# CPU_Logic.net
KiCad netlist of a schematic drawn in Altium Designer
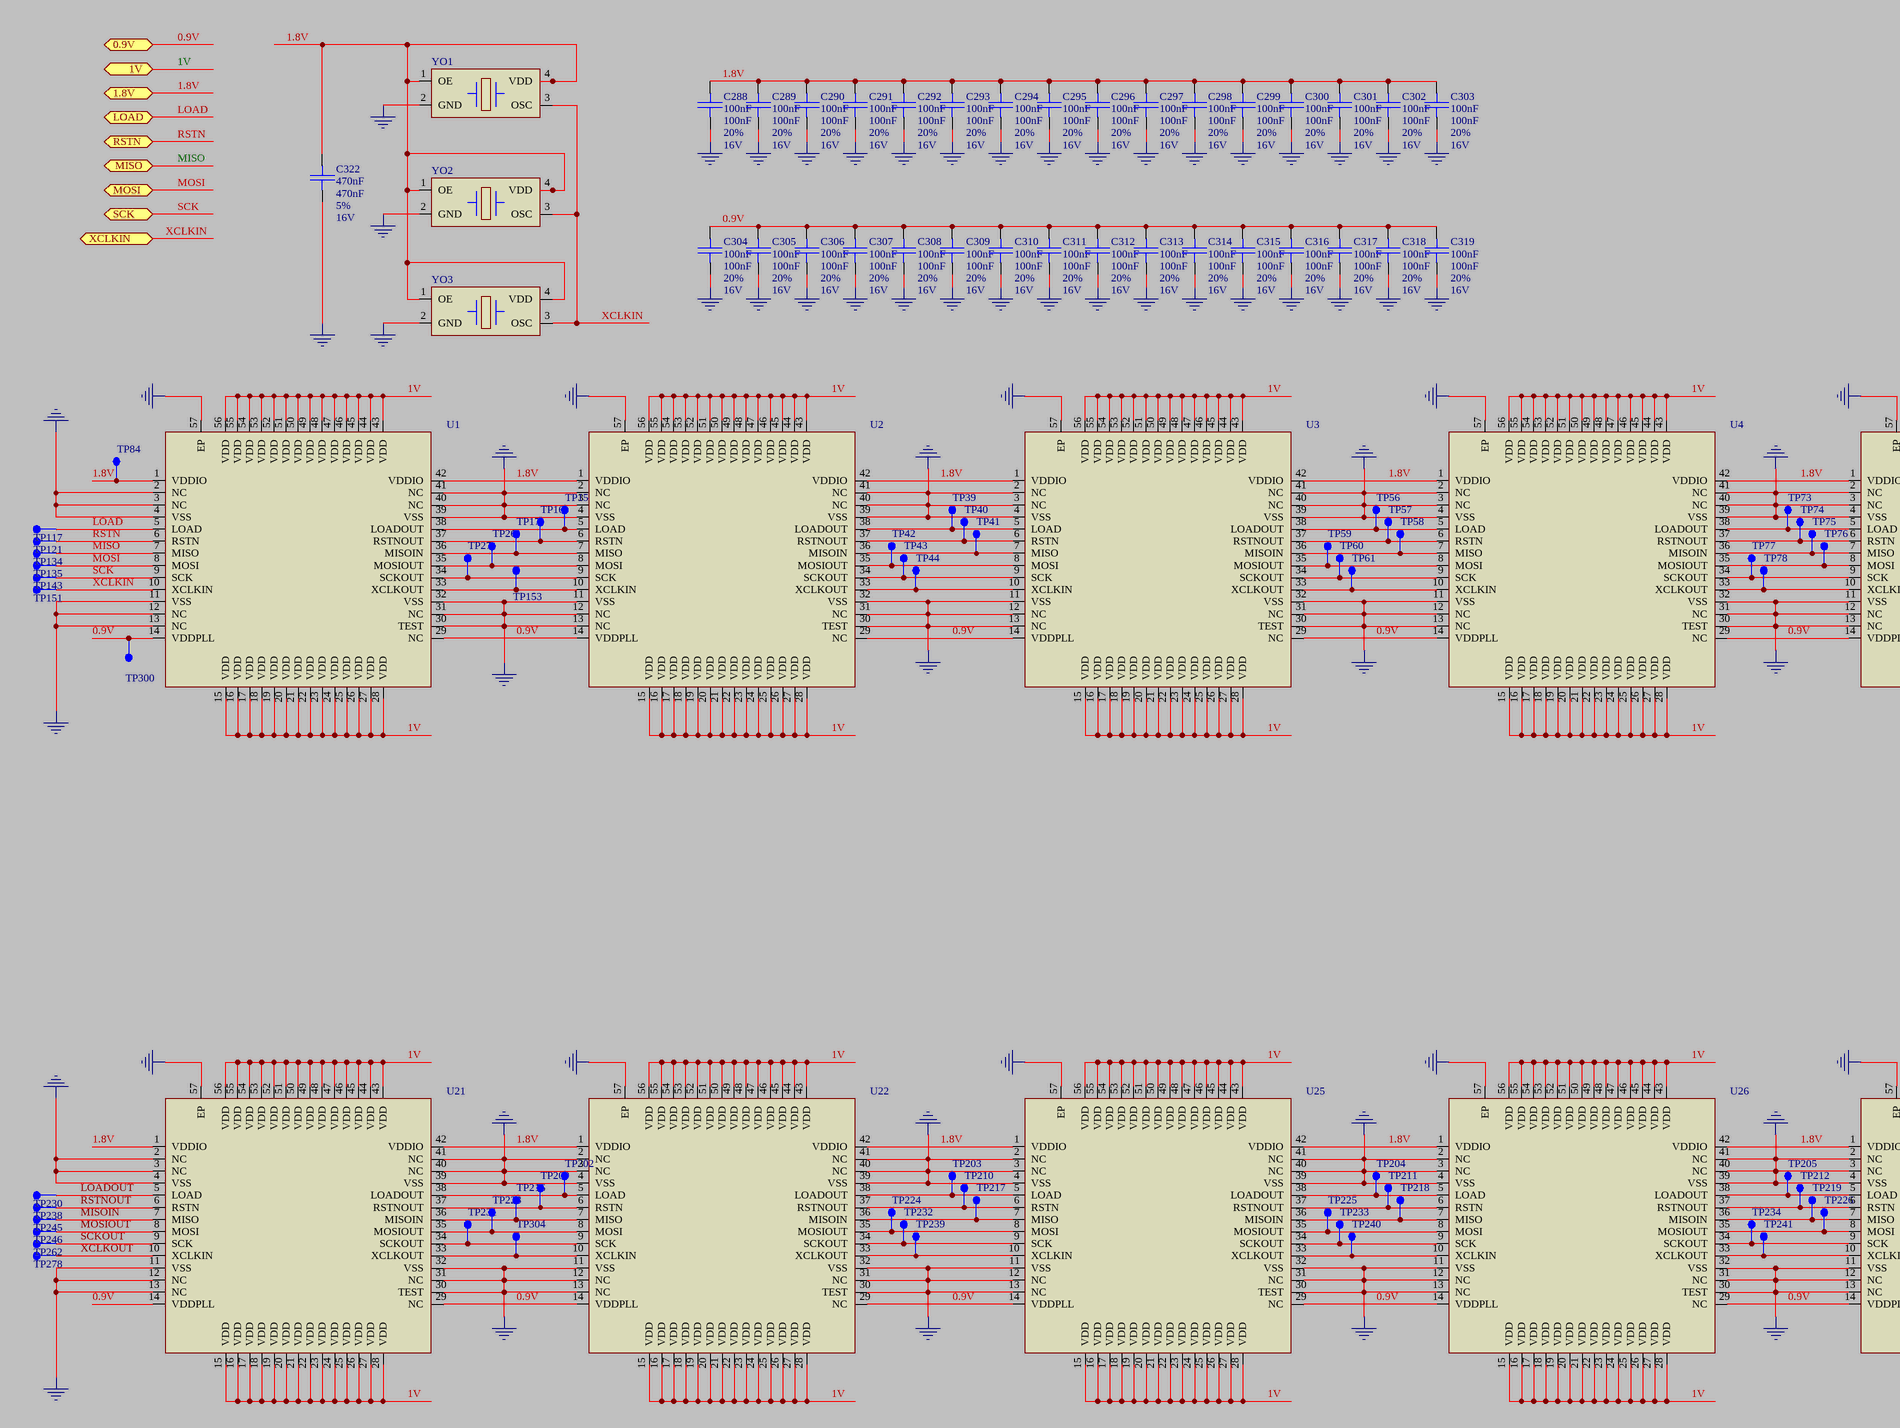
[diagram p0: CPU_Logic.SchDoc, top left]
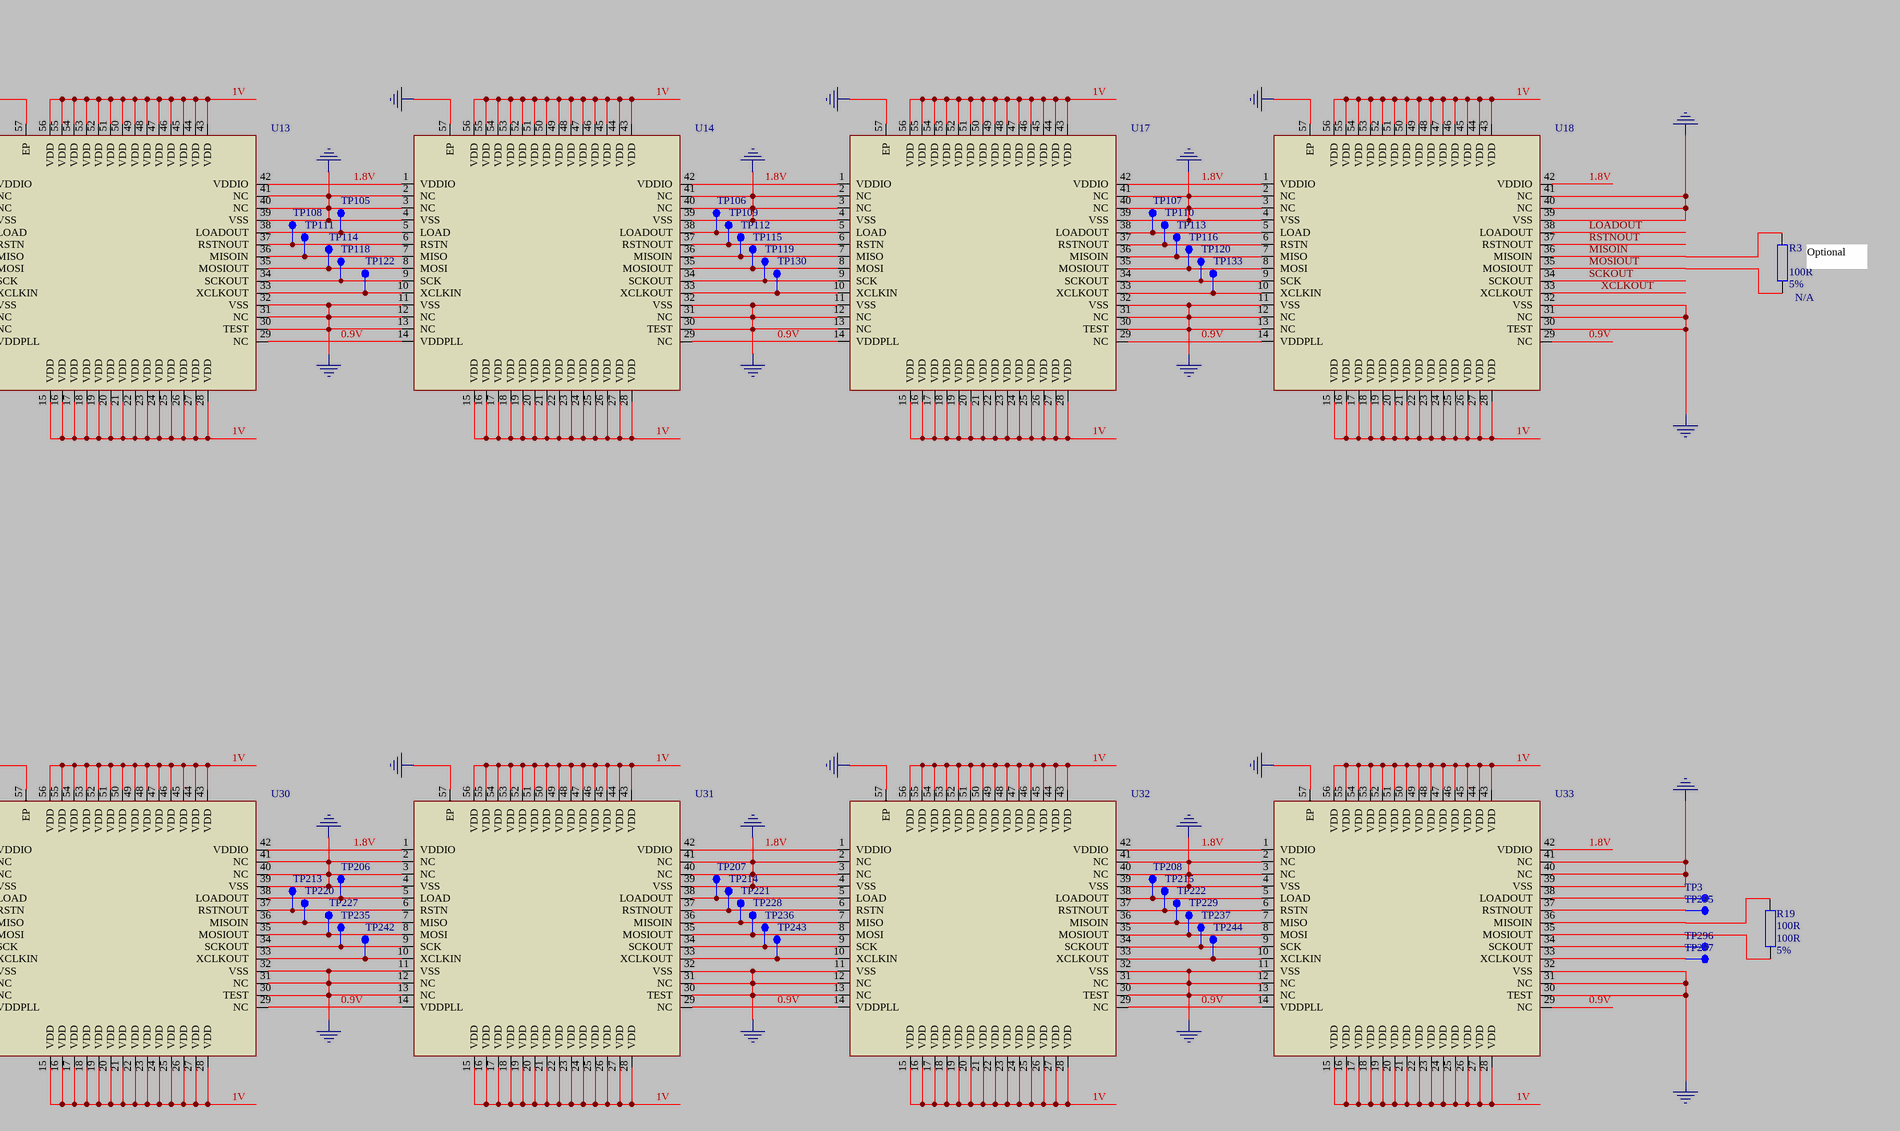
[diagram p1: CPU_Logic.SchDoc, top right]
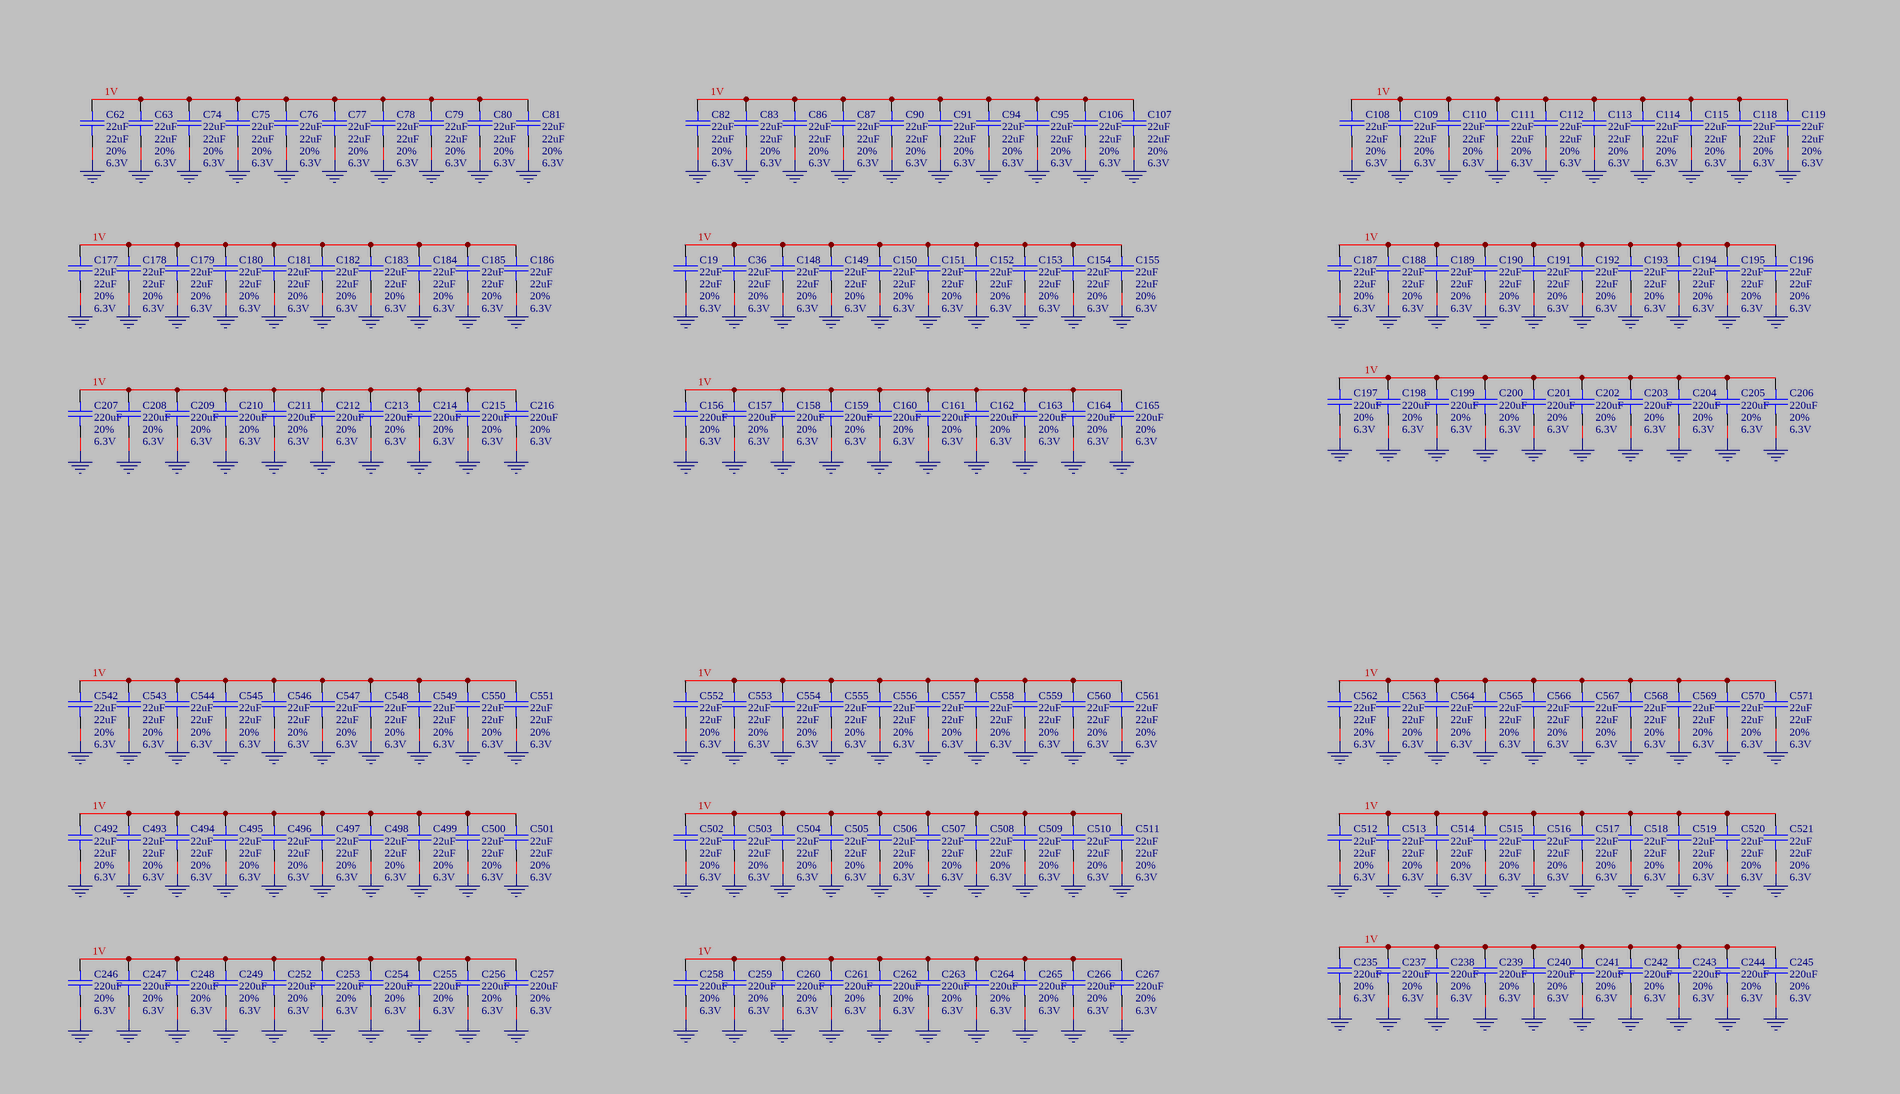
[diagram p2: CPU_Logic.SchDoc, bottom left]
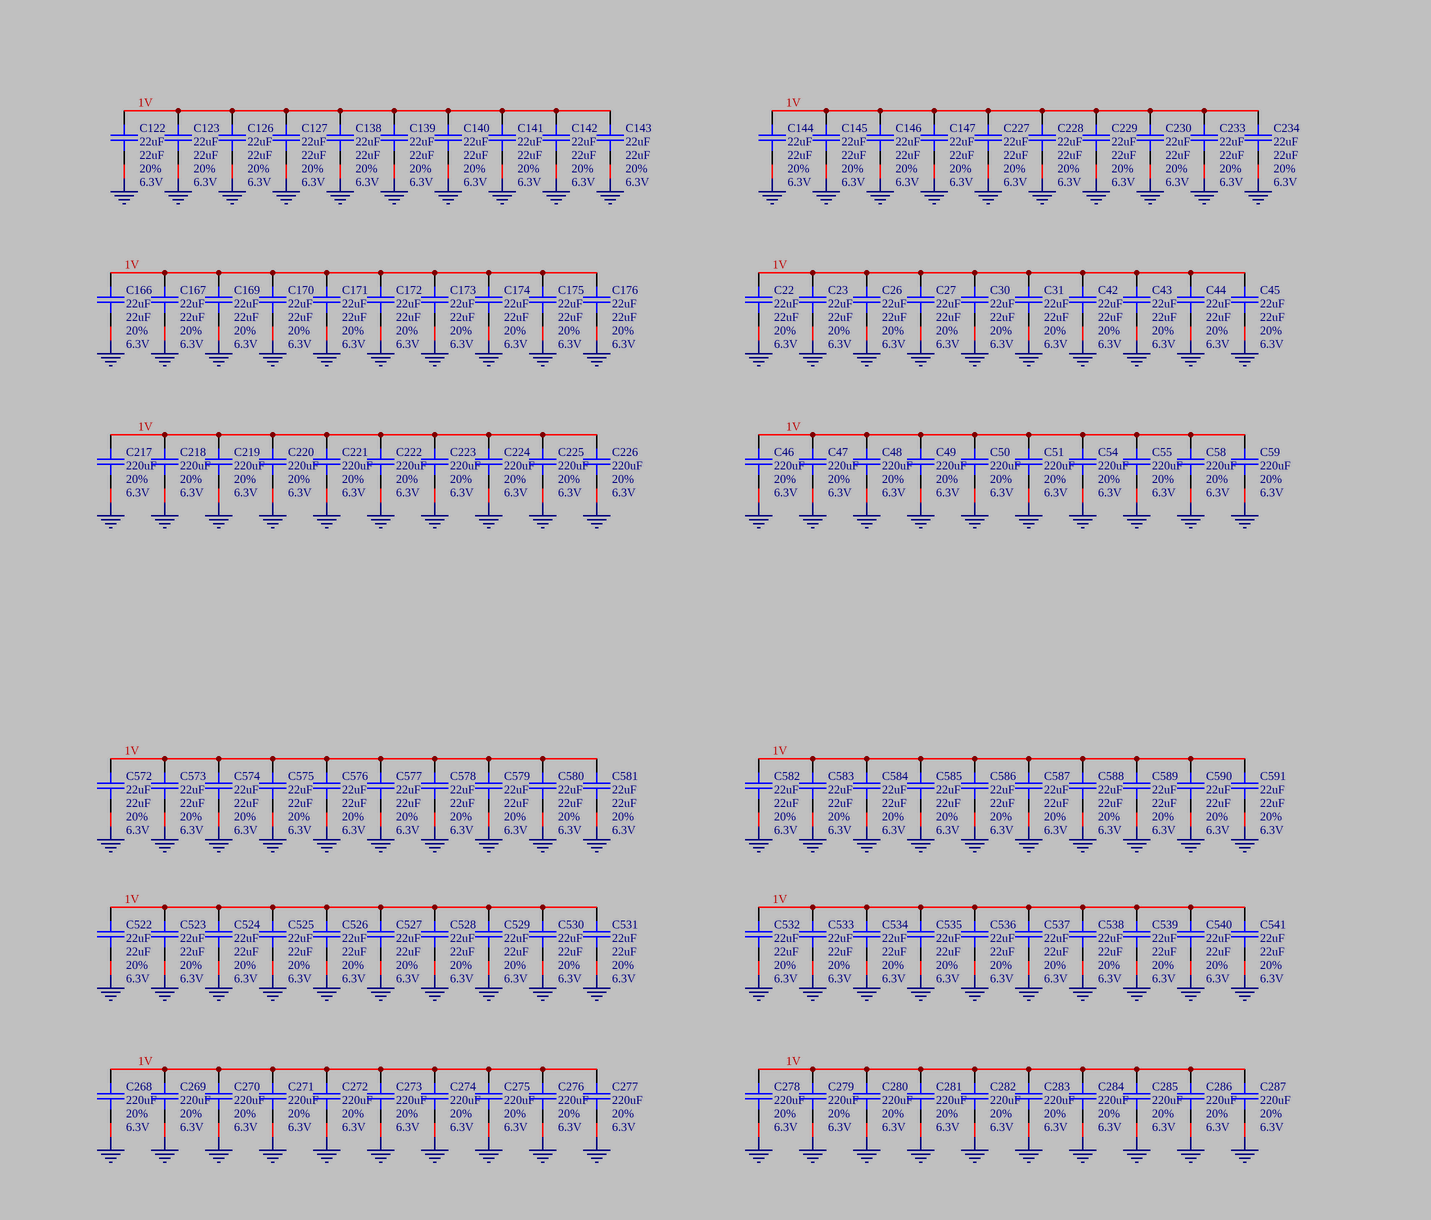
[diagram p3: CPU_Logic.SchDoc, bottom right]

(export (version "E")
  (design (tool "Eeschema 10.0.6"))
  (components
    (comp (ref "C19")
      (value "22uF")
      (footprint "SMD_0805_CAPC2012X145N")
      (fields
        (field (name "DB_PART_NUMBER") "CAP000043686")
        (field (name "DB_VALUE") "22uF")
        (field (name "DB_TOLERANCE") "20%")
        (field (name "DB_VOLTAGE") "6.3V")
        (field (name "DB_MANUFACTURER_PART") "KEMET    C0805C226M9PAC")
        (field (name "DB_APPROVED_BY") "ISHIDDEN=T")
      )
      (libsource (lib "Database_Libs1") (part "C"))
    )
    (comp (ref "C22")
      (value "22uF")
      (footprint "SMD_0805_CAPC2012X145N")
      (fields
        (field (name "DB_PART_NUMBER") "CAP000043686")
        (field (name "DB_VALUE") "22uF")
        (field (name "DB_TOLERANCE") "20%")
        (field (name "DB_VOLTAGE") "6.3V")
        (field (name "DB_MANUFACTURER_PART") "KEMET    C0805C226M9PAC")
        (field (name "DB_APPROVED_BY") "ISHIDDEN=T")
      )
      (libsource (lib "Database_Libs1") (part "C"))
    )
    (comp (ref "C23")
      (value "22uF")
      (footprint "SMD_0805_CAPC2012X145N")
      (fields
        (field (name "DB_PART_NUMBER") "CAP000043686")
        (field (name "DB_VALUE") "22uF")
        (field (name "DB_TOLERANCE") "20%")
        (field (name "DB_VOLTAGE") "6.3V")
        (field (name "DB_MANUFACTURER_PART") "KEMET    C0805C226M9PAC")
        (field (name "DB_APPROVED_BY") "ISHIDDEN=T")
      )
      (libsource (lib "Database_Libs1") (part "C"))
    )
    (comp (ref "C26")
      (value "22uF")
      (footprint "SMD_0805_CAPC2012X145N")
      (fields
        (field (name "DB_PART_NUMBER") "CAP000043686")
        (field (name "DB_VALUE") "22uF")
        (field (name "DB_TOLERANCE") "20%")
        (field (name "DB_VOLTAGE") "6.3V")
        (field (name "DB_MANUFACTURER_PART") "KEMET    C0805C226M9PAC")
        (field (name "DB_APPROVED_BY") "ISHIDDEN=T")
      )
      (libsource (lib "Database_Libs1") (part "C"))
    )
    (comp (ref "C27")
      (value "22uF")
      (footprint "SMD_0805_CAPC2012X145N")
      (fields
        (field (name "DB_PART_NUMBER") "CAP000043686")
        (field (name "DB_VALUE") "22uF")
        (field (name "DB_TOLERANCE") "20%")
        (field (name "DB_VOLTAGE") "6.3V")
        (field (name "DB_MANUFACTURER_PART") "KEMET    C0805C226M9PAC")
        (field (name "DB_APPROVED_BY") "ISHIDDEN=T")
      )
      (libsource (lib "Database_Libs1") (part "C"))
    )
    (comp (ref "C30")
      (value "22uF")
      (footprint "SMD_0805_CAPC2012X145N")
      (fields
        (field (name "DB_PART_NUMBER") "CAP000043686")
        (field (name "DB_VALUE") "22uF")
        (field (name "DB_TOLERANCE") "20%")
        (field (name "DB_VOLTAGE") "6.3V")
        (field (name "DB_MANUFACTURER_PART") "KEMET    C0805C226M9PAC")
        (field (name "DB_APPROVED_BY") "ISHIDDEN=T")
      )
      (libsource (lib "Database_Libs1") (part "C"))
    )
    (comp (ref "C31")
      (value "22uF")
      (footprint "SMD_0805_CAPC2012X145N")
      (fields
        (field (name "DB_PART_NUMBER") "CAP000043686")
        (field (name "DB_VALUE") "22uF")
        (field (name "DB_TOLERANCE") "20%")
        (field (name "DB_VOLTAGE") "6.3V")
        (field (name "DB_MANUFACTURER_PART") "KEMET    C0805C226M9PAC")
        (field (name "DB_APPROVED_BY") "ISHIDDEN=T")
      )
      (libsource (lib "Database_Libs1") (part "C"))
    )
    (comp (ref "C36")
      (value "22uF")
      (footprint "SMD_0805_CAPC2012X145N")
      (fields
        (field (name "DB_PART_NUMBER") "CAP000043686")
        (field (name "DB_VALUE") "22uF")
        (field (name "DB_TOLERANCE") "20%")
        (field (name "DB_VOLTAGE") "6.3V")
        (field (name "DB_MANUFACTURER_PART") "KEMET    C0805C226M9PAC")
        (field (name "DB_APPROVED_BY") "ISHIDDEN=T")
      )
      (libsource (lib "Database_Libs1") (part "C"))
    )
    (comp (ref "C42")
      (value "22uF")
      (footprint "SMD_0805_CAPC2012X145N")
      (fields
        (field (name "DB_PART_NUMBER") "CAP000043686")
        (field (name "DB_VALUE") "22uF")
        (field (name "DB_TOLERANCE") "20%")
        (field (name "DB_VOLTAGE") "6.3V")
        (field (name "DB_MANUFACTURER_PART") "KEMET    C0805C226M9PAC")
        (field (name "DB_APPROVED_BY") "ISHIDDEN=T")
      )
      (libsource (lib "Database_Libs1") (part "C"))
    )
    (comp (ref "C43")
      (value "22uF")
      (footprint "SMD_0805_CAPC2012X145N")
      (fields
        (field (name "DB_PART_NUMBER") "CAP000043686")
        (field (name "DB_VALUE") "22uF")
        (field (name "DB_TOLERANCE") "20%")
        (field (name "DB_VOLTAGE") "6.3V")
        (field (name "DB_MANUFACTURER_PART") "KEMET    C0805C226M9PAC")
        (field (name "DB_APPROVED_BY") "ISHIDDEN=T")
      )
      (libsource (lib "Database_Libs1") (part "C"))
    )
    (comp (ref "C44")
      (value "22uF")
      (footprint "SMD_0805_CAPC2012X145N")
      (fields
        (field (name "DB_PART_NUMBER") "CAP000043686")
        (field (name "DB_VALUE") "22uF")
        (field (name "DB_TOLERANCE") "20%")
        (field (name "DB_VOLTAGE") "6.3V")
        (field (name "DB_MANUFACTURER_PART") "KEMET    C0805C226M9PAC")
        (field (name "DB_APPROVED_BY") "ISHIDDEN=T")
      )
      (libsource (lib "Database_Libs1") (part "C"))
    )
    (comp (ref "C45")
      (value "22uF")
      (footprint "SMD_0805_CAPC2012X145N")
      (fields
        (field (name "DB_PART_NUMBER") "CAP000043686")
        (field (name "DB_VALUE") "22uF")
        (field (name "DB_TOLERANCE") "20%")
        (field (name "DB_VOLTAGE") "6.3V")
        (field (name "DB_MANUFACTURER_PART") "KEMET    C0805C226M9PAC")
        (field (name "DB_APPROVED_BY") "ISHIDDEN=T")
      )
      (libsource (lib "Database_Libs1") (part "C"))
    )
    (comp (ref "C46")
      (value "220uF")
      (footprint "SMD_1210_CAPC3225X279N")
      (fields
        (field (name "DB_PART_NUMBER") "CAP000047355")
        (field (name "DB_VALUE") "220uF")
        (field (name "DB_TOLERANCE") "20%")
        (field (name "DB_VOLTAGE") "6.3V")
        (field (name "DB_MANUFACTURER_PART") "SAMSUNG    CL32A227MQVNNNE")
        (field (name "DB_APPROVED_BY") "VSN")
      )
      (libsource (lib "Database_Libs1") (part "C"))
    )
    (comp (ref "C47")
      (value "220uF")
      (footprint "SMD_1210_CAPC3225X279N")
      (fields
        (field (name "DB_PART_NUMBER") "CAP000047355")
        (field (name "DB_VALUE") "220uF")
        (field (name "DB_TOLERANCE") "20%")
        (field (name "DB_VOLTAGE") "6.3V")
        (field (name "DB_MANUFACTURER_PART") "SAMSUNG    CL32A227MQVNNNE")
        (field (name "DB_APPROVED_BY") "VSN")
      )
      (libsource (lib "Database_Libs1") (part "C"))
    )
    (comp (ref "C48")
      (value "220uF")
      (footprint "SMD_1210_CAPC3225X279N")
      (fields
        (field (name "DB_PART_NUMBER") "CAP000047355")
        (field (name "DB_VALUE") "220uF")
        (field (name "DB_TOLERANCE") "20%")
        (field (name "DB_VOLTAGE") "6.3V")
        (field (name "DB_MANUFACTURER_PART") "SAMSUNG    CL32A227MQVNNNE")
        (field (name "DB_APPROVED_BY") "VSN")
      )
      (libsource (lib "Database_Libs1") (part "C"))
    )
    (comp (ref "C49")
      (value "220uF")
      (footprint "SMD_1210_CAPC3225X279N")
      (fields
        (field (name "DB_PART_NUMBER") "CAP000047355")
        (field (name "DB_VALUE") "220uF")
        (field (name "DB_TOLERANCE") "20%")
        (field (name "DB_VOLTAGE") "6.3V")
        (field (name "DB_MANUFACTURER_PART") "SAMSUNG    CL32A227MQVNNNE")
        (field (name "DB_APPROVED_BY") "VSN")
      )
      (libsource (lib "Database_Libs1") (part "C"))
    )
    (comp (ref "C50")
      (value "220uF")
      (footprint "SMD_1210_CAPC3225X279N")
      (fields
        (field (name "DB_PART_NUMBER") "CAP000047355")
        (field (name "DB_VALUE") "220uF")
        (field (name "DB_TOLERANCE") "20%")
        (field (name "DB_VOLTAGE") "6.3V")
        (field (name "DB_MANUFACTURER_PART") "SAMSUNG    CL32A227MQVNNNE")
        (field (name "DB_APPROVED_BY") "VSN")
      )
      (libsource (lib "Database_Libs1") (part "C"))
    )
    (comp (ref "C51")
      (value "220uF")
      (footprint "SMD_1210_CAPC3225X279N")
      (fields
        (field (name "DB_PART_NUMBER") "CAP000047355")
        (field (name "DB_VALUE") "220uF")
        (field (name "DB_TOLERANCE") "20%")
        (field (name "DB_VOLTAGE") "6.3V")
        (field (name "DB_MANUFACTURER_PART") "SAMSUNG    CL32A227MQVNNNE")
        (field (name "DB_APPROVED_BY") "VSN")
      )
      (libsource (lib "Database_Libs1") (part "C"))
    )
    (comp (ref "C54")
      (value "220uF")
      (footprint "SMD_1210_CAPC3225X279N")
      (fields
        (field (name "DB_PART_NUMBER") "CAP000047355")
        (field (name "DB_VALUE") "220uF")
        (field (name "DB_TOLERANCE") "20%")
        (field (name "DB_VOLTAGE") "6.3V")
        (field (name "DB_MANUFACTURER_PART") "SAMSUNG    CL32A227MQVNNNE")
        (field (name "DB_APPROVED_BY") "VSN")
      )
      (libsource (lib "Database_Libs1") (part "C"))
    )
    (comp (ref "C55")
      (value "220uF")
      (footprint "SMD_1210_CAPC3225X279N")
      (fields
        (field (name "DB_PART_NUMBER") "CAP000047355")
        (field (name "DB_VALUE") "220uF")
        (field (name "DB_TOLERANCE") "20%")
        (field (name "DB_VOLTAGE") "6.3V")
        (field (name "DB_MANUFACTURER_PART") "SAMSUNG    CL32A227MQVNNNE")
        (field (name "DB_APPROVED_BY") "VSN")
      )
      (libsource (lib "Database_Libs1") (part "C"))
    )
    (comp (ref "C58")
      (value "220uF")
      (footprint "SMD_1210_CAPC3225X279N")
      (fields
        (field (name "DB_PART_NUMBER") "CAP000047355")
        (field (name "DB_VALUE") "220uF")
        (field (name "DB_TOLERANCE") "20%")
        (field (name "DB_VOLTAGE") "6.3V")
        (field (name "DB_MANUFACTURER_PART") "SAMSUNG    CL32A227MQVNNNE")
        (field (name "DB_APPROVED_BY") "VSN")
      )
      (libsource (lib "Database_Libs1") (part "C"))
    )
    (comp (ref "C59")
      (value "220uF")
      (footprint "SMD_1210_CAPC3225X279N")
      (fields
        (field (name "DB_PART_NUMBER") "CAP000047355")
        (field (name "DB_VALUE") "220uF")
        (field (name "DB_TOLERANCE") "20%")
        (field (name "DB_VOLTAGE") "6.3V")
        (field (name "DB_MANUFACTURER_PART") "SAMSUNG    CL32A227MQVNNNE")
        (field (name "DB_APPROVED_BY") "VSN")
      )
      (libsource (lib "Database_Libs1") (part "C"))
    )
    (comp (ref "C62")
      (value "22uF")
      (footprint "SMD_0805_CAPC2012X145N")
      (fields
        (field (name "DB_PART_NUMBER") "CAP000043686")
        (field (name "DB_VALUE") "22uF")
        (field (name "DB_TOLERANCE") "20%")
        (field (name "DB_VOLTAGE") "6.3V")
        (field (name "DB_MANUFACTURER_PART") "KEMET    C0805C226M9PAC")
        (field (name "DB_APPROVED_BY") "ISHIDDEN=T")
      )
      (libsource (lib "Database_Libs1") (part "C"))
    )
    (comp (ref "C63")
      (value "22uF")
      (footprint "SMD_0805_CAPC2012X145N")
      (fields
        (field (name "DB_PART_NUMBER") "CAP000043686")
        (field (name "DB_VALUE") "22uF")
        (field (name "DB_TOLERANCE") "20%")
        (field (name "DB_VOLTAGE") "6.3V")
        (field (name "DB_MANUFACTURER_PART") "KEMET    C0805C226M9PAC")
        (field (name "DB_APPROVED_BY") "ISHIDDEN=T")
      )
      (libsource (lib "Database_Libs1") (part "C"))
    )
    (comp (ref "C74")
      (value "22uF")
      (footprint "SMD_0805_CAPC2012X145N")
      (fields
        (field (name "DB_PART_NUMBER") "CAP000043686")
        (field (name "DB_VALUE") "22uF")
        (field (name "DB_TOLERANCE") "20%")
        (field (name "DB_VOLTAGE") "6.3V")
        (field (name "DB_MANUFACTURER_PART") "KEMET    C0805C226M9PAC")
        (field (name "DB_APPROVED_BY") "ISHIDDEN=T")
      )
      (libsource (lib "Database_Libs1") (part "C"))
    )
    (comp (ref "C75")
      (value "22uF")
      (footprint "SMD_0805_CAPC2012X145N")
      (fields
        (field (name "DB_PART_NUMBER") "CAP000043686")
        (field (name "DB_VALUE") "22uF")
        (field (name "DB_TOLERANCE") "20%")
        (field (name "DB_VOLTAGE") "6.3V")
        (field (name "DB_MANUFACTURER_PART") "KEMET    C0805C226M9PAC")
        (field (name "DB_APPROVED_BY") "ISHIDDEN=T")
      )
      (libsource (lib "Database_Libs1") (part "C"))
    )
    (comp (ref "C76")
      (value "22uF")
      (footprint "SMD_0805_CAPC2012X145N")
      (fields
        (field (name "DB_PART_NUMBER") "CAP000043686")
        (field (name "DB_VALUE") "22uF")
        (field (name "DB_TOLERANCE") "20%")
        (field (name "DB_VOLTAGE") "6.3V")
        (field (name "DB_MANUFACTURER_PART") "KEMET    C0805C226M9PAC")
        (field (name "DB_APPROVED_BY") "ISHIDDEN=T")
      )
      (libsource (lib "Database_Libs1") (part "C"))
    )
    (comp (ref "C77")
      (value "22uF")
      (footprint "SMD_0805_CAPC2012X145N")
      (fields
        (field (name "DB_PART_NUMBER") "CAP000043686")
        (field (name "DB_VALUE") "22uF")
        (field (name "DB_TOLERANCE") "20%")
        (field (name "DB_VOLTAGE") "6.3V")
        (field (name "DB_MANUFACTURER_PART") "KEMET    C0805C226M9PAC")
        (field (name "DB_APPROVED_BY") "ISHIDDEN=T")
      )
      (libsource (lib "Database_Libs1") (part "C"))
    )
    (comp (ref "C78")
      (value "22uF")
      (footprint "SMD_0805_CAPC2012X145N")
      (fields
        (field (name "DB_PART_NUMBER") "CAP000043686")
        (field (name "DB_VALUE") "22uF")
        (field (name "DB_TOLERANCE") "20%")
        (field (name "DB_VOLTAGE") "6.3V")
        (field (name "DB_MANUFACTURER_PART") "KEMET    C0805C226M9PAC")
        (field (name "DB_APPROVED_BY") "ISHIDDEN=T")
      )
      (libsource (lib "Database_Libs1") (part "C"))
    )
    (comp (ref "C79")
      (value "22uF")
      (footprint "SMD_0805_CAPC2012X145N")
      (fields
        (field (name "DB_PART_NUMBER") "CAP000043686")
        (field (name "DB_VALUE") "22uF")
        (field (name "DB_TOLERANCE") "20%")
        (field (name "DB_VOLTAGE") "6.3V")
        (field (name "DB_MANUFACTURER_PART") "KEMET    C0805C226M9PAC")
        (field (name "DB_APPROVED_BY") "ISHIDDEN=T")
      )
      (libsource (lib "Database_Libs1") (part "C"))
    )
    (comp (ref "C80")
      (value "22uF")
      (footprint "SMD_0805_CAPC2012X145N")
      (fields
        (field (name "DB_PART_NUMBER") "CAP000043686")
        (field (name "DB_VALUE") "22uF")
        (field (name "DB_TOLERANCE") "20%")
        (field (name "DB_VOLTAGE") "6.3V")
        (field (name "DB_MANUFACTURER_PART") "KEMET    C0805C226M9PAC")
        (field (name "DB_APPROVED_BY") "ISHIDDEN=T")
      )
      (libsource (lib "Database_Libs1") (part "C"))
    )
    (comp (ref "C81")
      (value "22uF")
      (footprint "SMD_0805_CAPC2012X145N")
      (fields
        (field (name "DB_PART_NUMBER") "CAP000043686")
        (field (name "DB_VALUE") "22uF")
        (field (name "DB_TOLERANCE") "20%")
        (field (name "DB_VOLTAGE") "6.3V")
        (field (name "DB_MANUFACTURER_PART") "KEMET    C0805C226M9PAC")
        (field (name "DB_APPROVED_BY") "ISHIDDEN=T")
      )
      (libsource (lib "Database_Libs1") (part "C"))
    )
    (comp (ref "C82")
      (value "22uF")
      (footprint "SMD_0805_CAPC2012X145N")
      (fields
        (field (name "DB_PART_NUMBER") "CAP000043686")
        (field (name "DB_VALUE") "22uF")
        (field (name "DB_TOLERANCE") "20%")
        (field (name "DB_VOLTAGE") "6.3V")
        (field (name "DB_MANUFACTURER_PART") "KEMET    C0805C226M9PAC")
        (field (name "DB_APPROVED_BY") "ISHIDDEN=T")
      )
      (libsource (lib "Database_Libs1") (part "C"))
    )
    (comp (ref "C83")
      (value "22uF")
      (footprint "SMD_0805_CAPC2012X145N")
      (fields
        (field (name "DB_PART_NUMBER") "CAP000043686")
        (field (name "DB_VALUE") "22uF")
        (field (name "DB_TOLERANCE") "20%")
        (field (name "DB_VOLTAGE") "6.3V")
        (field (name "DB_MANUFACTURER_PART") "KEMET    C0805C226M9PAC")
        (field (name "DB_APPROVED_BY") "ISHIDDEN=T")
      )
      (libsource (lib "Database_Libs1") (part "C"))
    )
    (comp (ref "C86")
      (value "22uF")
      (footprint "SMD_0805_CAPC2012X145N")
      (fields
        (field (name "DB_PART_NUMBER") "CAP000043686")
        (field (name "DB_VALUE") "22uF")
        (field (name "DB_TOLERANCE") "20%")
        (field (name "DB_VOLTAGE") "6.3V")
        (field (name "DB_MANUFACTURER_PART") "KEMET    C0805C226M9PAC")
        (field (name "DB_APPROVED_BY") "ISHIDDEN=T")
      )
      (libsource (lib "Database_Libs1") (part "C"))
    )
    (comp (ref "C87")
      (value "22uF")
      (footprint "SMD_0805_CAPC2012X145N")
      (fields
        (field (name "DB_PART_NUMBER") "CAP000043686")
        (field (name "DB_VALUE") "22uF")
        (field (name "DB_TOLERANCE") "20%")
        (field (name "DB_VOLTAGE") "6.3V")
        (field (name "DB_MANUFACTURER_PART") "KEMET    C0805C226M9PAC")
        (field (name "DB_APPROVED_BY") "ISHIDDEN=T")
      )
      (libsource (lib "Database_Libs1") (part "C"))
    )
    (comp (ref "C90")
      (value "22uF")
      (footprint "SMD_0805_CAPC2012X145N")
      (fields
        (field (name "DB_PART_NUMBER") "CAP000043686")
        (field (name "DB_VALUE") "22uF")
        (field (name "DB_TOLERANCE") "20%")
        (field (name "DB_VOLTAGE") "6.3V")
        (field (name "DB_MANUFACTURER_PART") "KEMET    C0805C226M9PAC")
        (field (name "DB_APPROVED_BY") "ISHIDDEN=T")
      )
      (libsource (lib "Database_Libs1") (part "C"))
    )
    (comp (ref "C91")
      (value "22uF")
      (footprint "SMD_0805_CAPC2012X145N")
      (fields
        (field (name "DB_PART_NUMBER") "CAP000043686")
        (field (name "DB_VALUE") "22uF")
        (field (name "DB_TOLERANCE") "20%")
        (field (name "DB_VOLTAGE") "6.3V")
        (field (name "DB_MANUFACTURER_PART") "KEMET    C0805C226M9PAC")
        (field (name "DB_APPROVED_BY") "ISHIDDEN=T")
      )
      (libsource (lib "Database_Libs1") (part "C"))
    )
    (comp (ref "C94")
      (value "22uF")
      (footprint "SMD_0805_CAPC2012X145N")
      (fields
        (field (name "DB_PART_NUMBER") "CAP000043686")
        (field (name "DB_VALUE") "22uF")
        (field (name "DB_TOLERANCE") "20%")
        (field (name "DB_VOLTAGE") "6.3V")
        (field (name "DB_MANUFACTURER_PART") "KEMET    C0805C226M9PAC")
        (field (name "DB_APPROVED_BY") "ISHIDDEN=T")
      )
      (libsource (lib "Database_Libs1") (part "C"))
    )
    (comp (ref "C95")
      (value "22uF")
      (footprint "SMD_0805_CAPC2012X145N")
      (fields
        (field (name "DB_PART_NUMBER") "CAP000043686")
        (field (name "DB_VALUE") "22uF")
        (field (name "DB_TOLERANCE") "20%")
        (field (name "DB_VOLTAGE") "6.3V")
        (field (name "DB_MANUFACTURER_PART") "KEMET    C0805C226M9PAC")
        (field (name "DB_APPROVED_BY") "ISHIDDEN=T")
      )
      (libsource (lib "Database_Libs1") (part "C"))
    )
    (comp (ref "C106")
      (value "22uF")
      (footprint "SMD_0805_CAPC2012X145N")
      (fields
        (field (name "DB_PART_NUMBER") "CAP000043686")
        (field (name "DB_VALUE") "22uF")
        (field (name "DB_TOLERANCE") "20%")
        (field (name "DB_VOLTAGE") "6.3V")
        (field (name "DB_MANUFACTURER_PART") "KEMET    C0805C226M9PAC")
        (field (name "DB_APPROVED_BY") "ISHIDDEN=T")
      )
      (libsource (lib "Database_Libs1") (part "C"))
    )
    (comp (ref "C107")
      (value "22uF")
      (footprint "SMD_0805_CAPC2012X145N")
      (fields
        (field (name "DB_PART_NUMBER") "CAP000043686")
        (field (name "DB_VALUE") "22uF")
        (field (name "DB_TOLERANCE") "20%")
        (field (name "DB_VOLTAGE") "6.3V")
        (field (name "DB_MANUFACTURER_PART") "KEMET    C0805C226M9PAC")
        (field (name "DB_APPROVED_BY") "ISHIDDEN=T")
      )
      (libsource (lib "Database_Libs1") (part "C"))
    )
    (comp (ref "C108")
      (value "22uF")
      (footprint "SMD_0805_CAPC2012X145N")
      (fields
        (field (name "DB_PART_NUMBER") "CAP000043686")
        (field (name "DB_VALUE") "22uF")
        (field (name "DB_TOLERANCE") "20%")
        (field (name "DB_VOLTAGE") "6.3V")
        (field (name "DB_MANUFACTURER_PART") "KEMET    C0805C226M9PAC")
        (field (name "DB_APPROVED_BY") "ISHIDDEN=T")
      )
      (libsource (lib "Database_Libs1") (part "C"))
    )
    (comp (ref "C109")
      (value "22uF")
      (footprint "SMD_0805_CAPC2012X145N")
      (fields
        (field (name "DB_PART_NUMBER") "CAP000043686")
        (field (name "DB_VALUE") "22uF")
        (field (name "DB_TOLERANCE") "20%")
        (field (name "DB_VOLTAGE") "6.3V")
        (field (name "DB_MANUFACTURER_PART") "KEMET    C0805C226M9PAC")
        (field (name "DB_APPROVED_BY") "ISHIDDEN=T")
      )
      (libsource (lib "Database_Libs1") (part "C"))
    )
    (comp (ref "C110")
      (value "22uF")
      (footprint "SMD_0805_CAPC2012X145N")
      (fields
        (field (name "DB_PART_NUMBER") "CAP000043686")
        (field (name "DB_VALUE") "22uF")
        (field (name "DB_TOLERANCE") "20%")
        (field (name "DB_VOLTAGE") "6.3V")
        (field (name "DB_MANUFACTURER_PART") "KEMET    C0805C226M9PAC")
        (field (name "DB_APPROVED_BY") "ISHIDDEN=T")
      )
      (libsource (lib "Database_Libs1") (part "C"))
    )
    (comp (ref "C111")
      (value "22uF")
      (footprint "SMD_0805_CAPC2012X145N")
      (fields
        (field (name "DB_PART_NUMBER") "CAP000043686")
        (field (name "DB_VALUE") "22uF")
        (field (name "DB_TOLERANCE") "20%")
        (field (name "DB_VOLTAGE") "6.3V")
        (field (name "DB_MANUFACTURER_PART") "KEMET    C0805C226M9PAC")
        (field (name "DB_APPROVED_BY") "ISHIDDEN=T")
      )
      (libsource (lib "Database_Libs1") (part "C"))
    )
    (comp (ref "C112")
      (value "22uF")
      (footprint "SMD_0805_CAPC2012X145N")
      (fields
        (field (name "DB_PART_NUMBER") "CAP000043686")
        (field (name "DB_VALUE") "22uF")
        (field (name "DB_TOLERANCE") "20%")
        (field (name "DB_VOLTAGE") "6.3V")
        (field (name "DB_MANUFACTURER_PART") "KEMET    C0805C226M9PAC")
        (field (name "DB_APPROVED_BY") "ISHIDDEN=T")
      )
      (libsource (lib "Database_Libs1") (part "C"))
    )
    (comp (ref "C113")
      (value "22uF")
      (footprint "SMD_0805_CAPC2012X145N")
      (fields
        (field (name "DB_PART_NUMBER") "CAP000043686")
        (field (name "DB_VALUE") "22uF")
        (field (name "DB_TOLERANCE") "20%")
        (field (name "DB_VOLTAGE") "6.3V")
        (field (name "DB_MANUFACTURER_PART") "KEMET    C0805C226M9PAC")
        (field (name "DB_APPROVED_BY") "ISHIDDEN=T")
      )
      (libsource (lib "Database_Libs1") (part "C"))
    )
    (comp (ref "C114")
      (value "22uF")
      (footprint "SMD_0805_CAPC2012X145N")
      (fields
        (field (name "DB_PART_NUMBER") "CAP000043686")
        (field (name "DB_VALUE") "22uF")
        (field (name "DB_TOLERANCE") "20%")
        (field (name "DB_VOLTAGE") "6.3V")
        (field (name "DB_MANUFACTURER_PART") "KEMET    C0805C226M9PAC")
        (field (name "DB_APPROVED_BY") "ISHIDDEN=T")
      )
      (libsource (lib "Database_Libs1") (part "C"))
    )
    (comp (ref "C115")
      (value "22uF")
      (footprint "SMD_0805_CAPC2012X145N")
      (fields
        (field (name "DB_PART_NUMBER") "CAP000043686")
        (field (name "DB_VALUE") "22uF")
        (field (name "DB_TOLERANCE") "20%")
        (field (name "DB_VOLTAGE") "6.3V")
        (field (name "DB_MANUFACTURER_PART") "KEMET    C0805C226M9PAC")
        (field (name "DB_APPROVED_BY") "ISHIDDEN=T")
      )
      (libsource (lib "Database_Libs1") (part "C"))
    )
    (comp (ref "C118")
      (value "22uF")
      (footprint "SMD_0805_CAPC2012X145N")
      (fields
        (field (name "DB_PART_NUMBER") "CAP000043686")
        (field (name "DB_VALUE") "22uF")
        (field (name "DB_TOLERANCE") "20%")
        (field (name "DB_VOLTAGE") "6.3V")
        (field (name "DB_MANUFACTURER_PART") "KEMET    C0805C226M9PAC")
        (field (name "DB_APPROVED_BY") "ISHIDDEN=T")
      )
      (libsource (lib "Database_Libs1") (part "C"))
    )
    (comp (ref "C119")
      (value "22uF")
      (footprint "SMD_0805_CAPC2012X145N")
      (fields
        (field (name "DB_PART_NUMBER") "CAP000043686")
        (field (name "DB_VALUE") "22uF")
        (field (name "DB_TOLERANCE") "20%")
        (field (name "DB_VOLTAGE") "6.3V")
        (field (name "DB_MANUFACTURER_PART") "KEMET    C0805C226M9PAC")
        (field (name "DB_APPROVED_BY") "ISHIDDEN=T")
      )
      (libsource (lib "Database_Libs1") (part "C"))
    )
    (comp (ref "C122")
      (value "22uF")
      (footprint "SMD_0805_CAPC2012X145N")
      (fields
        (field (name "DB_PART_NUMBER") "CAP000043686")
        (field (name "DB_VALUE") "22uF")
        (field (name "DB_TOLERANCE") "20%")
        (field (name "DB_VOLTAGE") "6.3V")
        (field (name "DB_MANUFACTURER_PART") "KEMET    C0805C226M9PAC")
        (field (name "DB_APPROVED_BY") "ISHIDDEN=T")
      )
      (libsource (lib "Database_Libs1") (part "C"))
    )
    (comp (ref "C123")
      (value "22uF")
      (footprint "SMD_0805_CAPC2012X145N")
      (fields
        (field (name "DB_PART_NUMBER") "CAP000043686")
        (field (name "DB_VALUE") "22uF")
        (field (name "DB_TOLERANCE") "20%")
        (field (name "DB_VOLTAGE") "6.3V")
        (field (name "DB_MANUFACTURER_PART") "KEMET    C0805C226M9PAC")
        (field (name "DB_APPROVED_BY") "ISHIDDEN=T")
      )
      (libsource (lib "Database_Libs1") (part "C"))
    )
    (comp (ref "C126")
      (value "22uF")
      (footprint "SMD_0805_CAPC2012X145N")
      (fields
        (field (name "DB_PART_NUMBER") "CAP000043686")
        (field (name "DB_VALUE") "22uF")
        (field (name "DB_TOLERANCE") "20%")
        (field (name "DB_VOLTAGE") "6.3V")
        (field (name "DB_MANUFACTURER_PART") "KEMET    C0805C226M9PAC")
        (field (name "DB_APPROVED_BY") "ISHIDDEN=T")
      )
      (libsource (lib "Database_Libs1") (part "C"))
    )
    (comp (ref "C127")
      (value "22uF")
      (footprint "SMD_0805_CAPC2012X145N")
      (fields
        (field (name "DB_PART_NUMBER") "CAP000043686")
        (field (name "DB_VALUE") "22uF")
        (field (name "DB_TOLERANCE") "20%")
        (field (name "DB_VOLTAGE") "6.3V")
        (field (name "DB_MANUFACTURER_PART") "KEMET    C0805C226M9PAC")
        (field (name "DB_APPROVED_BY") "ISHIDDEN=T")
      )
      (libsource (lib "Database_Libs1") (part "C"))
    )
    (comp (ref "C138")
      (value "22uF")
      (footprint "SMD_0805_CAPC2012X145N")
      (fields
        (field (name "DB_PART_NUMBER") "CAP000043686")
        (field (name "DB_VALUE") "22uF")
        (field (name "DB_TOLERANCE") "20%")
        (field (name "DB_VOLTAGE") "6.3V")
        (field (name "DB_MANUFACTURER_PART") "KEMET    C0805C226M9PAC")
        (field (name "DB_APPROVED_BY") "ISHIDDEN=T")
      )
      (libsource (lib "Database_Libs1") (part "C"))
    )
    (comp (ref "C139")
      (value "22uF")
      (footprint "SMD_0805_CAPC2012X145N")
      (fields
        (field (name "DB_PART_NUMBER") "CAP000043686")
        (field (name "DB_VALUE") "22uF")
        (field (name "DB_TOLERANCE") "20%")
        (field (name "DB_VOLTAGE") "6.3V")
        (field (name "DB_MANUFACTURER_PART") "KEMET    C0805C226M9PAC")
        (field (name "DB_APPROVED_BY") "ISHIDDEN=T")
      )
      (libsource (lib "Database_Libs1") (part "C"))
    )
    (comp (ref "C140")
      (value "22uF")
      (footprint "SMD_0805_CAPC2012X145N")
      (fields
        (field (name "DB_PART_NUMBER") "CAP000043686")
        (field (name "DB_VALUE") "22uF")
        (field (name "DB_TOLERANCE") "20%")
        (field (name "DB_VOLTAGE") "6.3V")
        (field (name "DB_MANUFACTURER_PART") "KEMET    C0805C226M9PAC")
        (field (name "DB_APPROVED_BY") "ISHIDDEN=T")
      )
      (libsource (lib "Database_Libs1") (part "C"))
    )
    (comp (ref "C141")
      (value "22uF")
      (footprint "SMD_0805_CAPC2012X145N")
      (fields
        (field (name "DB_PART_NUMBER") "CAP000043686")
        (field (name "DB_VALUE") "22uF")
        (field (name "DB_TOLERANCE") "20%")
        (field (name "DB_VOLTAGE") "6.3V")
        (field (name "DB_MANUFACTURER_PART") "KEMET    C0805C226M9PAC")
        (field (name "DB_APPROVED_BY") "ISHIDDEN=T")
      )
      (libsource (lib "Database_Libs1") (part "C"))
    )
    (comp (ref "C142")
      (value "22uF")
      (footprint "SMD_0805_CAPC2012X145N")
      (fields
        (field (name "DB_PART_NUMBER") "CAP000043686")
        (field (name "DB_VALUE") "22uF")
        (field (name "DB_TOLERANCE") "20%")
        (field (name "DB_VOLTAGE") "6.3V")
        (field (name "DB_MANUFACTURER_PART") "KEMET    C0805C226M9PAC")
        (field (name "DB_APPROVED_BY") "ISHIDDEN=T")
      )
      (libsource (lib "Database_Libs1") (part "C"))
    )
    (comp (ref "C143")
      (value "22uF")
      (footprint "SMD_0805_CAPC2012X145N")
      (fields
        (field (name "DB_PART_NUMBER") "CAP000043686")
        (field (name "DB_VALUE") "22uF")
        (field (name "DB_TOLERANCE") "20%")
        (field (name "DB_VOLTAGE") "6.3V")
        (field (name "DB_MANUFACTURER_PART") "KEMET    C0805C226M9PAC")
        (field (name "DB_APPROVED_BY") "ISHIDDEN=T")
      )
      (libsource (lib "Database_Libs1") (part "C"))
    )
    (comp (ref "C144")
      (value "22uF")
      (footprint "SMD_0805_CAPC2012X145N")
      (fields
        (field (name "DB_PART_NUMBER") "CAP000043686")
        (field (name "DB_VALUE") "22uF")
        (field (name "DB_TOLERANCE") "20%")
        (field (name "DB_VOLTAGE") "6.3V")
        (field (name "DB_MANUFACTURER_PART") "KEMET    C0805C226M9PAC")
        (field (name "DB_APPROVED_BY") "ISHIDDEN=T")
      )
      (libsource (lib "Database_Libs1") (part "C"))
    )
    (comp (ref "C145")
      (value "22uF")
      (footprint "SMD_0805_CAPC2012X145N")
      (fields
        (field (name "DB_PART_NUMBER") "CAP000043686")
        (field (name "DB_VALUE") "22uF")
        (field (name "DB_TOLERANCE") "20%")
        (field (name "DB_VOLTAGE") "6.3V")
        (field (name "DB_MANUFACTURER_PART") "KEMET    C0805C226M9PAC")
        (field (name "DB_APPROVED_BY") "ISHIDDEN=T")
      )
      (libsource (lib "Database_Libs1") (part "C"))
    )
    (comp (ref "C146")
      (value "22uF")
      (footprint "SMD_0805_CAPC2012X145N")
      (fields
        (field (name "DB_PART_NUMBER") "CAP000043686")
        (field (name "DB_VALUE") "22uF")
        (field (name "DB_TOLERANCE") "20%")
        (field (name "DB_VOLTAGE") "6.3V")
        (field (name "DB_MANUFACTURER_PART") "KEMET    C0805C226M9PAC")
        (field (name "DB_APPROVED_BY") "ISHIDDEN=T")
      )
      (libsource (lib "Database_Libs1") (part "C"))
    )
    (comp (ref "C147")
      (value "22uF")
      (footprint "SMD_0805_CAPC2012X145N")
      (fields
        (field (name "DB_PART_NUMBER") "CAP000043686")
        (field (name "DB_VALUE") "22uF")
        (field (name "DB_TOLERANCE") "20%")
        (field (name "DB_VOLTAGE") "6.3V")
        (field (name "DB_MANUFACTURER_PART") "KEMET    C0805C226M9PAC")
        (field (name "DB_APPROVED_BY") "ISHIDDEN=T")
      )
      (libsource (lib "Database_Libs1") (part "C"))
    )
    (comp (ref "C148")
      (value "22uF")
      (footprint "SMD_0805_CAPC2012X145N")
      (fields
        (field (name "DB_PART_NUMBER") "CAP000043686")
        (field (name "DB_VALUE") "22uF")
        (field (name "DB_TOLERANCE") "20%")
        (field (name "DB_VOLTAGE") "6.3V")
        (field (name "DB_MANUFACTURER_PART") "KEMET    C0805C226M9PAC")
        (field (name "DB_APPROVED_BY") "ISHIDDEN=T")
      )
      (libsource (lib "Database_Libs1") (part "C"))
    )
    (comp (ref "C149")
      (value "22uF")
      (footprint "SMD_0805_CAPC2012X145N")
      (fields
        (field (name "DB_PART_NUMBER") "CAP000043686")
        (field (name "DB_VALUE") "22uF")
        (field (name "DB_TOLERANCE") "20%")
        (field (name "DB_VOLTAGE") "6.3V")
        (field (name "DB_MANUFACTURER_PART") "KEMET    C0805C226M9PAC")
        (field (name "DB_APPROVED_BY") "ISHIDDEN=T")
      )
      (libsource (lib "Database_Libs1") (part "C"))
    )
    (comp (ref "C150")
      (value "22uF")
      (footprint "SMD_0805_CAPC2012X145N")
      (fields
        (field (name "DB_PART_NUMBER") "CAP000043686")
        (field (name "DB_VALUE") "22uF")
        (field (name "DB_TOLERANCE") "20%")
        (field (name "DB_VOLTAGE") "6.3V")
        (field (name "DB_MANUFACTURER_PART") "KEMET    C0805C226M9PAC")
        (field (name "DB_APPROVED_BY") "ISHIDDEN=T")
      )
      (libsource (lib "Database_Libs1") (part "C"))
    )
    (comp (ref "C151")
      (value "22uF")
      (footprint "SMD_0805_CAPC2012X145N")
      (fields
        (field (name "DB_PART_NUMBER") "CAP000043686")
        (field (name "DB_VALUE") "22uF")
        (field (name "DB_TOLERANCE") "20%")
        (field (name "DB_VOLTAGE") "6.3V")
        (field (name "DB_MANUFACTURER_PART") "KEMET    C0805C226M9PAC")
        (field (name "DB_APPROVED_BY") "ISHIDDEN=T")
      )
      (libsource (lib "Database_Libs1") (part "C"))
    )
    (comp (ref "C152")
      (value "22uF")
      (footprint "SMD_0805_CAPC2012X145N")
      (fields
        (field (name "DB_PART_NUMBER") "CAP000043686")
        (field (name "DB_VALUE") "22uF")
        (field (name "DB_TOLERANCE") "20%")
        (field (name "DB_VOLTAGE") "6.3V")
        (field (name "DB_MANUFACTURER_PART") "KEMET    C0805C226M9PAC")
        (field (name "DB_APPROVED_BY") "ISHIDDEN=T")
      )
      (libsource (lib "Database_Libs1") (part "C"))
    )
    (comp (ref "C153")
      (value "22uF")
      (footprint "SMD_0805_CAPC2012X145N")
      (fields
        (field (name "DB_PART_NUMBER") "CAP000043686")
        (field (name "DB_VALUE") "22uF")
        (field (name "DB_TOLERANCE") "20%")
        (field (name "DB_VOLTAGE") "6.3V")
        (field (name "DB_MANUFACTURER_PART") "KEMET    C0805C226M9PAC")
        (field (name "DB_APPROVED_BY") "ISHIDDEN=T")
      )
      (libsource (lib "Database_Libs1") (part "C"))
    )
    (comp (ref "C154")
      (value "22uF")
      (footprint "SMD_0805_CAPC2012X145N")
      (fields
        (field (name "DB_PART_NUMBER") "CAP000043686")
        (field (name "DB_VALUE") "22uF")
        (field (name "DB_TOLERANCE") "20%")
        (field (name "DB_VOLTAGE") "6.3V")
        (field (name "DB_MANUFACTURER_PART") "KEMET    C0805C226M9PAC")
        (field (name "DB_APPROVED_BY") "ISHIDDEN=T")
      )
      (libsource (lib "Database_Libs1") (part "C"))
    )
    (comp (ref "C155")
      (value "22uF")
      (footprint "SMD_0805_CAPC2012X145N")
      (fields
        (field (name "DB_PART_NUMBER") "CAP000043686")
        (field (name "DB_VALUE") "22uF")
        (field (name "DB_TOLERANCE") "20%")
        (field (name "DB_VOLTAGE") "6.3V")
        (field (name "DB_MANUFACTURER_PART") "KEMET    C0805C226M9PAC")
        (field (name "DB_APPROVED_BY") "ISHIDDEN=T")
      )
      (libsource (lib "Database_Libs1") (part "C"))
    )
    (comp (ref "C156")
      (value "220uF")
      (footprint "SMD_1210_CAPC3225X279N")
      (fields
        (field (name "DB_PART_NUMBER") "CAP000047355")
        (field (name "DB_VALUE") "220uF")
        (field (name "DB_TOLERANCE") "20%")
        (field (name "DB_VOLTAGE") "6.3V")
        (field (name "DB_MANUFACTURER_PART") "SAMSUNG    CL32A227MQVNNNE")
        (field (name "DB_APPROVED_BY") "VSN")
      )
      (libsource (lib "Database_Libs1") (part "C"))
    )
    (comp (ref "C157")
      (value "220uF")
      (footprint "SMD_1210_CAPC3225X279N")
      (fields
        (field (name "DB_PART_NUMBER") "CAP000047355")
        (field (name "DB_VALUE") "220uF")
        (field (name "DB_TOLERANCE") "20%")
        (field (name "DB_VOLTAGE") "6.3V")
        (field (name "DB_MANUFACTURER_PART") "SAMSUNG    CL32A227MQVNNNE")
        (field (name "DB_APPROVED_BY") "VSN")
      )
      (libsource (lib "Database_Libs1") (part "C"))
    )
    (comp (ref "C158")
      (value "220uF")
      (footprint "SMD_1210_CAPC3225X279N")
      (fields
        (field (name "DB_PART_NUMBER") "CAP000047355")
        (field (name "DB_VALUE") "220uF")
        (field (name "DB_TOLERANCE") "20%")
        (field (name "DB_VOLTAGE") "6.3V")
        (field (name "DB_MANUFACTURER_PART") "SAMSUNG    CL32A227MQVNNNE")
        (field (name "DB_APPROVED_BY") "VSN")
      )
      (libsource (lib "Database_Libs1") (part "C"))
    )
    (comp (ref "C159")
      (value "220uF")
      (footprint "SMD_1210_CAPC3225X279N")
      (fields
        (field (name "DB_PART_NUMBER") "CAP000047355")
        (field (name "DB_VALUE") "220uF")
        (field (name "DB_TOLERANCE") "20%")
        (field (name "DB_VOLTAGE") "6.3V")
        (field (name "DB_MANUFACTURER_PART") "SAMSUNG    CL32A227MQVNNNE")
        (field (name "DB_APPROVED_BY") "VSN")
      )
      (libsource (lib "Database_Libs1") (part "C"))
    )
    (comp (ref "C160")
      (value "220uF")
      (footprint "SMD_1210_CAPC3225X279N")
      (fields
        (field (name "DB_PART_NUMBER") "CAP000047355")
        (field (name "DB_VALUE") "220uF")
        (field (name "DB_TOLERANCE") "20%")
        (field (name "DB_VOLTAGE") "6.3V")
        (field (name "DB_MANUFACTURER_PART") "SAMSUNG    CL32A227MQVNNNE")
        (field (name "DB_APPROVED_BY") "VSN")
      )
      (libsource (lib "Database_Libs1") (part "C"))
    )
    (comp (ref "C161")
      (value "220uF")
      (footprint "SMD_1210_CAPC3225X279N")
      (fields
        (field (name "DB_PART_NUMBER") "CAP000047355")
        (field (name "DB_VALUE") "220uF")
        (field (name "DB_TOLERANCE") "20%")
        (field (name "DB_VOLTAGE") "6.3V")
        (field (name "DB_MANUFACTURER_PART") "SAMSUNG    CL32A227MQVNNNE")
        (field (name "DB_APPROVED_BY") "VSN")
      )
      (libsource (lib "Database_Libs1") (part "C"))
    )
    (comp (ref "C162")
      (value "220uF")
      (footprint "SMD_1210_CAPC3225X279N")
      (fields
        (field (name "DB_PART_NUMBER") "CAP000047355")
        (field (name "DB_VALUE") "220uF")
        (field (name "DB_TOLERANCE") "20%")
        (field (name "DB_VOLTAGE") "6.3V")
        (field (name "DB_MANUFACTURER_PART") "SAMSUNG    CL32A227MQVNNNE")
        (field (name "DB_APPROVED_BY") "VSN")
      )
      (libsource (lib "Database_Libs1") (part "C"))
    )
    (comp (ref "C163")
      (value "220uF")
      (footprint "SMD_1210_CAPC3225X279N")
      (fields
        (field (name "DB_PART_NUMBER") "CAP000047355")
        (field (name "DB_VALUE") "220uF")
        (field (name "DB_TOLERANCE") "20%")
        (field (name "DB_VOLTAGE") "6.3V")
        (field (name "DB_MANUFACTURER_PART") "SAMSUNG    CL32A227MQVNNNE")
        (field (name "DB_APPROVED_BY") "VSN")
      )
      (libsource (lib "Database_Libs1") (part "C"))
    )
    (comp (ref "C164")
      (value "220uF")
      (footprint "SMD_1210_CAPC3225X279N")
      (fields
        (field (name "DB_PART_NUMBER") "CAP000047355")
        (field (name "DB_VALUE") "220uF")
        (field (name "DB_TOLERANCE") "20%")
        (field (name "DB_VOLTAGE") "6.3V")
        (field (name "DB_MANUFACTURER_PART") "SAMSUNG    CL32A227MQVNNNE")
        (field (name "DB_APPROVED_BY") "VSN")
      )
      (libsource (lib "Database_Libs1") (part "C"))
    )
    (comp (ref "C165")
      (value "220uF")
      (footprint "SMD_1210_CAPC3225X279N")
      (fields
        (field (name "DB_PART_NUMBER") "CAP000047355")
        (field (name "DB_VALUE") "220uF")
        (field (name "DB_TOLERANCE") "20%")
        (field (name "DB_VOLTAGE") "6.3V")
        (field (name "DB_MANUFACTURER_PART") "SAMSUNG    CL32A227MQVNNNE")
        (field (name "DB_APPROVED_BY") "VSN")
      )
      (libsource (lib "Database_Libs1") (part "C"))
    )
    (comp (ref "C166")
      (value "22uF")
      (footprint "SMD_0805_CAPC2012X145N")
      (fields
        (field (name "DB_PART_NUMBER") "CAP000043686")
        (field (name "DB_VALUE") "22uF")
        (field (name "DB_TOLERANCE") "20%")
        (field (name "DB_VOLTAGE") "6.3V")
        (field (name "DB_MANUFACTURER_PART") "KEMET    C0805C226M9PAC")
        (field (name "DB_APPROVED_BY") "ISHIDDEN=T")
      )
      (libsource (lib "Database_Libs1") (part "C"))
    )
    (comp (ref "C167")
      (value "22uF")
      (footprint "SMD_0805_CAPC2012X145N")
      (fields
        (field (name "DB_PART_NUMBER") "CAP000043686")
        (field (name "DB_VALUE") "22uF")
        (field (name "DB_TOLERANCE") "20%")
        (field (name "DB_VOLTAGE") "6.3V")
        (field (name "DB_MANUFACTURER_PART") "KEMET    C0805C226M9PAC")
        (field (name "DB_APPROVED_BY") "ISHIDDEN=T")
      )
      (libsource (lib "Database_Libs1") (part "C"))
    )
    (comp (ref "C169")
      (value "22uF")
      (footprint "SMD_0805_CAPC2012X145N")
      (fields
        (field (name "DB_PART_NUMBER") "CAP000043686")
        (field (name "DB_VALUE") "22uF")
        (field (name "DB_TOLERANCE") "20%")
        (field (name "DB_VOLTAGE") "6.3V")
        (field (name "DB_MANUFACTURER_PART") "KEMET    C0805C226M9PAC")
        (field (name "DB_APPROVED_BY") "ISHIDDEN=T")
      )
      (libsource (lib "Database_Libs1") (part "C"))
    )
    (comp (ref "C170")
      (value "22uF")
      (footprint "SMD_0805_CAPC2012X145N")
      (fields
        (field (name "DB_PART_NUMBER") "CAP000043686")
        (field (name "DB_VALUE") "22uF")
        (field (name "DB_TOLERANCE") "20%")
        (field (name "DB_VOLTAGE") "6.3V")
        (field (name "DB_MANUFACTURER_PART") "KEMET    C0805C226M9PAC")
        (field (name "DB_APPROVED_BY") "ISHIDDEN=T")
      )
      (libsource (lib "Database_Libs1") (part "C"))
    )
    (comp (ref "C171")
      (value "22uF")
      (footprint "SMD_0805_CAPC2012X145N")
      (fields
        (field (name "DB_PART_NUMBER") "CAP000043686")
        (field (name "DB_VALUE") "22uF")
        (field (name "DB_TOLERANCE") "20%")
        (field (name "DB_VOLTAGE") "6.3V")
        (field (name "DB_MANUFACTURER_PART") "KEMET    C0805C226M9PAC")
        (field (name "DB_APPROVED_BY") "ISHIDDEN=T")
      )
      (libsource (lib "Database_Libs1") (part "C"))
    )
    (comp (ref "C172")
      (value "22uF")
      (footprint "SMD_0805_CAPC2012X145N")
      (fields
        (field (name "DB_PART_NUMBER") "CAP000043686")
        (field (name "DB_VALUE") "22uF")
        (field (name "DB_TOLERANCE") "20%")
        (field (name "DB_VOLTAGE") "6.3V")
        (field (name "DB_MANUFACTURER_PART") "KEMET    C0805C226M9PAC")
        (field (name "DB_APPROVED_BY") "ISHIDDEN=T")
      )
      (libsource (lib "Database_Libs1") (part "C"))
    )
    (comp (ref "C173")
      (value "22uF")
      (footprint "SMD_0805_CAPC2012X145N")
      (fields
        (field (name "DB_PART_NUMBER") "CAP000043686")
        (field (name "DB_VALUE") "22uF")
        (field (name "DB_TOLERANCE") "20%")
        (field (name "DB_VOLTAGE") "6.3V")
        (field (name "DB_MANUFACTURER_PART") "KEMET    C0805C226M9PAC")
        (field (name "DB_APPROVED_BY") "ISHIDDEN=T")
      )
      (libsource (lib "Database_Libs1") (part "C"))
    )
    (comp (ref "C174")
      (value "22uF")
      (footprint "SMD_0805_CAPC2012X145N")
      (fields
        (field (name "DB_PART_NUMBER") "CAP000043686")
        (field (name "DB_VALUE") "22uF")
        (field (name "DB_TOLERANCE") "20%")
        (field (name "DB_VOLTAGE") "6.3V")
        (field (name "DB_MANUFACTURER_PART") "KEMET    C0805C226M9PAC")
        (field (name "DB_APPROVED_BY") "ISHIDDEN=T")
      )
      (libsource (lib "Database_Libs1") (part "C"))
    )
    (comp (ref "C175")
      (value "22uF")
      (footprint "SMD_0805_CAPC2012X145N")
      (fields
        (field (name "DB_PART_NUMBER") "CAP000043686")
        (field (name "DB_VALUE") "22uF")
        (field (name "DB_TOLERANCE") "20%")
        (field (name "DB_VOLTAGE") "6.3V")
        (field (name "DB_MANUFACTURER_PART") "KEMET    C0805C226M9PAC")
        (field (name "DB_APPROVED_BY") "ISHIDDEN=T")
      )
      (libsource (lib "Database_Libs1") (part "C"))
    )
    (comp (ref "C176")
      (value "22uF")
      (footprint "SMD_0805_CAPC2012X145N")
      (fields
        (field (name "DB_PART_NUMBER") "CAP000043686")
        (field (name "DB_VALUE") "22uF")
        (field (name "DB_TOLERANCE") "20%")
        (field (name "DB_VOLTAGE") "6.3V")
        (field (name "DB_MANUFACTURER_PART") "KEMET    C0805C226M9PAC")
        (field (name "DB_APPROVED_BY") "ISHIDDEN=T")
      )
      (libsource (lib "Database_Libs1") (part "C"))
    )
    (comp (ref "C177")
      (value "22uF")
      (footprint "SMD_0805_CAPC2012X145N")
      (fields
        (field (name "DB_PART_NUMBER") "CAP000043686")
        (field (name "DB_VALUE") "22uF")
        (field (name "DB_TOLERANCE") "20%")
        (field (name "DB_VOLTAGE") "6.3V")
        (field (name "DB_MANUFACTURER_PART") "KEMET    C0805C226M9PAC")
        (field (name "DB_APPROVED_BY") "ISHIDDEN=T")
      )
      (libsource (lib "Database_Libs1") (part "C"))
    )
    (comp (ref "C178")
      (value "22uF")
      (footprint "SMD_0805_CAPC2012X145N")
      (fields
        (field (name "DB_PART_NUMBER") "CAP000043686")
        (field (name "DB_VALUE") "22uF")
        (field (name "DB_TOLERANCE") "20%")
        (field (name "DB_VOLTAGE") "6.3V")
        (field (name "DB_MANUFACTURER_PART") "KEMET    C0805C226M9PAC")
        (field (name "DB_APPROVED_BY") "ISHIDDEN=T")
      )
      (libsource (lib "Database_Libs1") (part "C"))
    )
    (comp (ref "C179")
      (value "22uF")
      (footprint "SMD_0805_CAPC2012X145N")
      (fields
        (field (name "DB_PART_NUMBER") "CAP000043686")
        (field (name "DB_VALUE") "22uF")
        (field (name "DB_TOLERANCE") "20%")
        (field (name "DB_VOLTAGE") "6.3V")
        (field (name "DB_MANUFACTURER_PART") "KEMET    C0805C226M9PAC")
        (field (name "DB_APPROVED_BY") "ISHIDDEN=T")
      )
      (libsource (lib "Database_Libs1") (part "C"))
    )
    (comp (ref "C180")
      (value "22uF")
      (footprint "SMD_0805_CAPC2012X145N")
      (fields
        (field (name "DB_PART_NUMBER") "CAP000043686")
        (field (name "DB_VALUE") "22uF")
        (field (name "DB_TOLERANCE") "20%")
        (field (name "DB_VOLTAGE") "6.3V")
        (field (name "DB_MANUFACTURER_PART") "KEMET    C0805C226M9PAC")
        (field (name "DB_APPROVED_BY") "ISHIDDEN=T")
      )
      (libsource (lib "Database_Libs1") (part "C"))
    )
    (comp (ref "C181")
      (value "22uF")
      (footprint "SMD_0805_CAPC2012X145N")
      (fields
        (field (name "DB_PART_NUMBER") "CAP000043686")
        (field (name "DB_VALUE") "22uF")
        (field (name "DB_TOLERANCE") "20%")
        (field (name "DB_VOLTAGE") "6.3V")
        (field (name "DB_MANUFACTURER_PART") "KEMET    C0805C226M9PAC")
        (field (name "DB_APPROVED_BY") "ISHIDDEN=T")
      )
      (libsource (lib "Database_Libs1") (part "C"))
    )
    (comp (ref "C182")
      (value "22uF")
      (footprint "SMD_0805_CAPC2012X145N")
      (fields
        (field (name "DB_PART_NUMBER") "CAP000043686")
        (field (name "DB_VALUE") "22uF")
        (field (name "DB_TOLERANCE") "20%")
        (field (name "DB_VOLTAGE") "6.3V")
        (field (name "DB_MANUFACTURER_PART") "KEMET    C0805C226M9PAC")
        (field (name "DB_APPROVED_BY") "ISHIDDEN=T")
      )
      (libsource (lib "Database_Libs1") (part "C"))
    )
    (comp (ref "C183")
      (value "22uF")
      (footprint "SMD_0805_CAPC2012X145N")
      (fields
        (field (name "DB_PART_NUMBER") "CAP000043686")
        (field (name "DB_VALUE") "22uF")
        (field (name "DB_TOLERANCE") "20%")
        (field (name "DB_VOLTAGE") "6.3V")
        (field (name "DB_MANUFACTURER_PART") "KEMET    C0805C226M9PAC")
        (field (name "DB_APPROVED_BY") "ISHIDDEN=T")
      )
      (libsource (lib "Database_Libs1") (part "C"))
    )
    (comp (ref "C184")
      (value "22uF")
      (footprint "SMD_0805_CAPC2012X145N")
      (fields
        (field (name "DB_PART_NUMBER") "CAP000043686")
        (field (name "DB_VALUE") "22uF")
        (field (name "DB_TOLERANCE") "20%")
        (field (name "DB_VOLTAGE") "6.3V")
        (field (name "DB_MANUFACTURER_PART") "KEMET    C0805C226M9PAC")
        (field (name "DB_APPROVED_BY") "ISHIDDEN=T")
      )
      (libsource (lib "Database_Libs1") (part "C"))
    )
    (comp (ref "C185")
      (value "22uF")
      (footprint "SMD_0805_CAPC2012X145N")
      (fields
        (field (name "DB_PART_NUMBER") "CAP000043686")
        (field (name "DB_VALUE") "22uF")
        (field (name "DB_TOLERANCE") "20%")
        (field (name "DB_VOLTAGE") "6.3V")
        (field (name "DB_MANUFACTURER_PART") "KEMET    C0805C226M9PAC")
        (field (name "DB_APPROVED_BY") "ISHIDDEN=T")
      )
      (libsource (lib "Database_Libs1") (part "C"))
    )
    (comp (ref "C186")
      (value "22uF")
      (footprint "SMD_0805_CAPC2012X145N")
      (fields
        (field (name "DB_PART_NUMBER") "CAP000043686")
        (field (name "DB_VALUE") "22uF")
        (field (name "DB_TOLERANCE") "20%")
        (field (name "DB_VOLTAGE") "6.3V")
        (field (name "DB_MANUFACTURER_PART") "KEMET    C0805C226M9PAC")
        (field (name "DB_APPROVED_BY") "ISHIDDEN=T")
      )
      (libsource (lib "Database_Libs1") (part "C"))
    )
    (comp (ref "C187")
      (value "22uF")
      (footprint "SMD_0805_CAPC2012X145N")
      (fields
        (field (name "DB_PART_NUMBER") "CAP000043686")
        (field (name "DB_VALUE") "22uF")
        (field (name "DB_TOLERANCE") "20%")
        (field (name "DB_VOLTAGE") "6.3V")
        (field (name "DB_MANUFACTURER_PART") "KEMET    C0805C226M9PAC")
        (field (name "DB_APPROVED_BY") "ISHIDDEN=T")
      )
      (libsource (lib "Database_Libs1") (part "C"))
    )
    (comp (ref "C188")
      (value "22uF")
      (footprint "SMD_0805_CAPC2012X145N")
      (fields
        (field (name "DB_PART_NUMBER") "CAP000043686")
        (field (name "DB_VALUE") "22uF")
        (field (name "DB_TOLERANCE") "20%")
        (field (name "DB_VOLTAGE") "6.3V")
        (field (name "DB_MANUFACTURER_PART") "KEMET    C0805C226M9PAC")
        (field (name "DB_APPROVED_BY") "ISHIDDEN=T")
      )
      (libsource (lib "Database_Libs1") (part "C"))
    )
    (comp (ref "C189")
      (value "22uF")
      (footprint "SMD_0805_CAPC2012X145N")
      (fields
        (field (name "DB_PART_NUMBER") "CAP000043686")
        (field (name "DB_VALUE") "22uF")
        (field (name "DB_TOLERANCE") "20%")
        (field (name "DB_VOLTAGE") "6.3V")
        (field (name "DB_MANUFACTURER_PART") "KEMET    C0805C226M9PAC")
        (field (name "DB_APPROVED_BY") "ISHIDDEN=T")
      )
      (libsource (lib "Database_Libs1") (part "C"))
    )
    (comp (ref "C190")
      (value "22uF")
      (footprint "SMD_0805_CAPC2012X145N")
      (fields
        (field (name "DB_PART_NUMBER") "CAP000043686")
        (field (name "DB_VALUE") "22uF")
        (field (name "DB_TOLERANCE") "20%")
        (field (name "DB_VOLTAGE") "6.3V")
        (field (name "DB_MANUFACTURER_PART") "KEMET    C0805C226M9PAC")
        (field (name "DB_APPROVED_BY") "ISHIDDEN=T")
      )
      (libsource (lib "Database_Libs1") (part "C"))
    )
    (comp (ref "C191")
      (value "22uF")
      (footprint "SMD_0805_CAPC2012X145N")
      (fields
        (field (name "DB_PART_NUMBER") "CAP000043686")
        (field (name "DB_VALUE") "22uF")
        (field (name "DB_TOLERANCE") "20%")
        (field (name "DB_VOLTAGE") "6.3V")
        (field (name "DB_MANUFACTURER_PART") "KEMET    C0805C226M9PAC")
        (field (name "DB_APPROVED_BY") "ISHIDDEN=T")
      )
      (libsource (lib "Database_Libs1") (part "C"))
    )
    (comp (ref "C192")
      (value "22uF")
      (footprint "SMD_0805_CAPC2012X145N")
      (fields
        (field (name "DB_PART_NUMBER") "CAP000043686")
        (field (name "DB_VALUE") "22uF")
        (field (name "DB_TOLERANCE") "20%")
        (field (name "DB_VOLTAGE") "6.3V")
        (field (name "DB_MANUFACTURER_PART") "KEMET    C0805C226M9PAC")
        (field (name "DB_APPROVED_BY") "ISHIDDEN=T")
      )
      (libsource (lib "Database_Libs1") (part "C"))
    )
    (comp (ref "C193")
      (value "22uF")
      (footprint "SMD_0805_CAPC2012X145N")
      (fields
        (field (name "DB_PART_NUMBER") "CAP000043686")
        (field (name "DB_VALUE") "22uF")
        (field (name "DB_TOLERANCE") "20%")
        (field (name "DB_VOLTAGE") "6.3V")
        (field (name "DB_MANUFACTURER_PART") "KEMET    C0805C226M9PAC")
        (field (name "DB_APPROVED_BY") "ISHIDDEN=T")
      )
      (libsource (lib "Database_Libs1") (part "C"))
    )
    (comp (ref "C194")
      (value "22uF")
      (footprint "SMD_0805_CAPC2012X145N")
      (fields
        (field (name "DB_PART_NUMBER") "CAP000043686")
        (field (name "DB_VALUE") "22uF")
        (field (name "DB_TOLERANCE") "20%")
        (field (name "DB_VOLTAGE") "6.3V")
        (field (name "DB_MANUFACTURER_PART") "KEMET    C0805C226M9PAC")
        (field (name "DB_APPROVED_BY") "ISHIDDEN=T")
      )
      (libsource (lib "Database_Libs1") (part "C"))
    )
    (comp (ref "C195")
      (value "22uF")
      (footprint "SMD_0805_CAPC2012X145N")
      (fields
        (field (name "DB_PART_NUMBER") "CAP000043686")
        (field (name "DB_VALUE") "22uF")
        (field (name "DB_TOLERANCE") "20%")
        (field (name "DB_VOLTAGE") "6.3V")
        (field (name "DB_MANUFACTURER_PART") "KEMET    C0805C226M9PAC")
        (field (name "DB_APPROVED_BY") "ISHIDDEN=T")
      )
      (libsource (lib "Database_Libs1") (part "C"))
    )
    (comp (ref "C196")
      (value "22uF")
      (footprint "SMD_0805_CAPC2012X145N")
      (fields
        (field (name "DB_PART_NUMBER") "CAP000043686")
        (field (name "DB_VALUE") "22uF")
        (field (name "DB_TOLERANCE") "20%")
        (field (name "DB_VOLTAGE") "6.3V")
        (field (name "DB_MANUFACTURER_PART") "KEMET    C0805C226M9PAC")
        (field (name "DB_APPROVED_BY") "ISHIDDEN=T")
      )
      (libsource (lib "Database_Libs1") (part "C"))
    )
    (comp (ref "C197")
      (value "220uF")
      (footprint "SMD_1210_CAPC3225X279N")
      (fields
        (field (name "DB_PART_NUMBER") "CAP000047355")
        (field (name "DB_VALUE") "220uF")
        (field (name "DB_TOLERANCE") "20%")
        (field (name "DB_VOLTAGE") "6.3V")
        (field (name "DB_MANUFACTURER_PART") "SAMSUNG    CL32A227MQVNNNE")
        (field (name "DB_APPROVED_BY") "VSN")
      )
      (libsource (lib "Database_Libs1") (part "C"))
    )
    (comp (ref "C198")
      (value "220uF")
      (footprint "SMD_1210_CAPC3225X279N")
      (fields
        (field (name "DB_PART_NUMBER") "CAP000047355")
        (field (name "DB_VALUE") "220uF")
        (field (name "DB_TOLERANCE") "20%")
        (field (name "DB_VOLTAGE") "6.3V")
        (field (name "DB_MANUFACTURER_PART") "SAMSUNG    CL32A227MQVNNNE")
        (field (name "DB_APPROVED_BY") "VSN")
      )
      (libsource (lib "Database_Libs1") (part "C"))
    )
    (comp (ref "C199")
      (value "220uF")
      (footprint "SMD_1210_CAPC3225X279N")
      (fields
        (field (name "DB_PART_NUMBER") "CAP000047355")
        (field (name "DB_VALUE") "220uF")
        (field (name "DB_TOLERANCE") "20%")
        (field (name "DB_VOLTAGE") "6.3V")
        (field (name "DB_MANUFACTURER_PART") "SAMSUNG    CL32A227MQVNNNE")
        (field (name "DB_APPROVED_BY") "VSN")
      )
      (libsource (lib "Database_Libs1") (part "C"))
    )
    (comp (ref "C200")
      (value "220uF")
      (footprint "SMD_1210_CAPC3225X279N")
      (fields
        (field (name "DB_PART_NUMBER") "CAP000047355")
        (field (name "DB_VALUE") "220uF")
        (field (name "DB_TOLERANCE") "20%")
        (field (name "DB_VOLTAGE") "6.3V")
        (field (name "DB_MANUFACTURER_PART") "SAMSUNG    CL32A227MQVNNNE")
        (field (name "DB_APPROVED_BY") "VSN")
      )
      (libsource (lib "Database_Libs1") (part "C"))
    )
    (comp (ref "C201")
      (value "220uF")
      (footprint "SMD_1210_CAPC3225X279N")
      (fields
        (field (name "DB_PART_NUMBER") "CAP000047355")
        (field (name "DB_VALUE") "220uF")
        (field (name "DB_TOLERANCE") "20%")
        (field (name "DB_VOLTAGE") "6.3V")
        (field (name "DB_MANUFACTURER_PART") "SAMSUNG    CL32A227MQVNNNE")
        (field (name "DB_APPROVED_BY") "VSN")
      )
      (libsource (lib "Database_Libs1") (part "C"))
    )
    (comp (ref "C202")
      (value "220uF")
      (footprint "SMD_1210_CAPC3225X279N")
      (fields
        (field (name "DB_PART_NUMBER") "CAP000047355")
        (field (name "DB_VALUE") "220uF")
        (field (name "DB_TOLERANCE") "20%")
        (field (name "DB_VOLTAGE") "6.3V")
        (field (name "DB_MANUFACTURER_PART") "SAMSUNG    CL32A227MQVNNNE")
        (field (name "DB_APPROVED_BY") "VSN")
      )
      (libsource (lib "Database_Libs1") (part "C"))
    )
    (comp (ref "C203")
      (value "220uF")
      (footprint "SMD_1210_CAPC3225X279N")
      (fields
        (field (name "DB_PART_NUMBER") "CAP000047355")
        (field (name "DB_VALUE") "220uF")
        (field (name "DB_TOLERANCE") "20%")
        (field (name "DB_VOLTAGE") "6.3V")
        (field (name "DB_MANUFACTURER_PART") "SAMSUNG    CL32A227MQVNNNE")
        (field (name "DB_APPROVED_BY") "VSN")
      )
      (libsource (lib "Database_Libs1") (part "C"))
    )
    (comp (ref "C204")
      (value "220uF")
      (footprint "SMD_1210_CAPC3225X279N")
      (fields
        (field (name "DB_PART_NUMBER") "CAP000047355")
        (field (name "DB_VALUE") "220uF")
        (field (name "DB_TOLERANCE") "20%")
        (field (name "DB_VOLTAGE") "6.3V")
        (field (name "DB_MANUFACTURER_PART") "SAMSUNG    CL32A227MQVNNNE")
        (field (name "DB_APPROVED_BY") "VSN")
      )
      (libsource (lib "Database_Libs1") (part "C"))
    )
    (comp (ref "C205")
      (value "220uF")
      (footprint "SMD_1210_CAPC3225X279N")
      (fields
        (field (name "DB_PART_NUMBER") "CAP000047355")
        (field (name "DB_VALUE") "220uF")
        (field (name "DB_TOLERANCE") "20%")
        (field (name "DB_VOLTAGE") "6.3V")
        (field (name "DB_MANUFACTURER_PART") "SAMSUNG    CL32A227MQVNNNE")
        (field (name "DB_APPROVED_BY") "VSN")
      )
      (libsource (lib "Database_Libs1") (part "C"))
    )
    (comp (ref "C206")
      (value "220uF")
      (footprint "SMD_1210_CAPC3225X279N")
      (fields
        (field (name "DB_PART_NUMBER") "CAP000047355")
        (field (name "DB_VALUE") "220uF")
        (field (name "DB_TOLERANCE") "20%")
        (field (name "DB_VOLTAGE") "6.3V")
        (field (name "DB_MANUFACTURER_PART") "SAMSUNG    CL32A227MQVNNNE")
        (field (name "DB_APPROVED_BY") "VSN")
      )
      (libsource (lib "Database_Libs1") (part "C"))
    )
    (comp (ref "C207")
      (value "220uF")
      (footprint "SMD_1210_CAPC3225X279N")
      (fields
        (field (name "DB_PART_NUMBER") "CAP000047355")
        (field (name "DB_VALUE") "220uF")
        (field (name "DB_TOLERANCE") "20%")
        (field (name "DB_VOLTAGE") "6.3V")
        (field (name "DB_MANUFACTURER_PART") "SAMSUNG    CL32A227MQVNNNE")
        (field (name "DB_APPROVED_BY") "VSN")
      )
      (libsource (lib "Database_Libs1") (part "C"))
    )
    (comp (ref "C208")
      (value "220uF")
      (footprint "SMD_1210_CAPC3225X279N")
      (fields
        (field (name "DB_PART_NUMBER") "CAP000047355")
        (field (name "DB_VALUE") "220uF")
        (field (name "DB_TOLERANCE") "20%")
        (field (name "DB_VOLTAGE") "6.3V")
        (field (name "DB_MANUFACTURER_PART") "SAMSUNG    CL32A227MQVNNNE")
        (field (name "DB_APPROVED_BY") "VSN")
      )
      (libsource (lib "Database_Libs1") (part "C"))
    )
    (comp (ref "C209")
      (value "220uF")
      (footprint "SMD_1210_CAPC3225X279N")
      (fields
        (field (name "DB_PART_NUMBER") "CAP000047355")
        (field (name "DB_VALUE") "220uF")
        (field (name "DB_TOLERANCE") "20%")
        (field (name "DB_VOLTAGE") "6.3V")
        (field (name "DB_MANUFACTURER_PART") "SAMSUNG    CL32A227MQVNNNE")
        (field (name "DB_APPROVED_BY") "VSN")
      )
      (libsource (lib "Database_Libs1") (part "C"))
    )
    (comp (ref "C210")
      (value "220uF")
      (footprint "SMD_1210_CAPC3225X279N")
      (fields
        (field (name "DB_PART_NUMBER") "CAP000047355")
        (field (name "DB_VALUE") "220uF")
        (field (name "DB_TOLERANCE") "20%")
        (field (name "DB_VOLTAGE") "6.3V")
        (field (name "DB_MANUFACTURER_PART") "SAMSUNG    CL32A227MQVNNNE")
        (field (name "DB_APPROVED_BY") "VSN")
      )
      (libsource (lib "Database_Libs1") (part "C"))
    )
    (comp (ref "C211")
      (value "220uF")
      (footprint "SMD_1210_CAPC3225X279N")
      (fields
        (field (name "DB_PART_NUMBER") "CAP000047355")
        (field (name "DB_VALUE") "220uF")
        (field (name "DB_TOLERANCE") "20%")
        (field (name "DB_VOLTAGE") "6.3V")
        (field (name "DB_MANUFACTURER_PART") "SAMSUNG    CL32A227MQVNNNE")
        (field (name "DB_APPROVED_BY") "VSN")
      )
      (libsource (lib "Database_Libs1") (part "C"))
    )
    (comp (ref "C212")
      (value "220uF")
      (footprint "SMD_1210_CAPC3225X279N")
      (fields
        (field (name "DB_PART_NUMBER") "CAP000047355")
        (field (name "DB_VALUE") "220uF")
        (field (name "DB_TOLERANCE") "20%")
        (field (name "DB_VOLTAGE") "6.3V")
        (field (name "DB_MANUFACTURER_PART") "SAMSUNG    CL32A227MQVNNNE")
        (field (name "DB_APPROVED_BY") "VSN")
      )
      (libsource (lib "Database_Libs1") (part "C"))
    )
    (comp (ref "C213")
      (value "220uF")
      (footprint "SMD_1210_CAPC3225X279N")
      (fields
        (field (name "DB_PART_NUMBER") "CAP000047355")
        (field (name "DB_VALUE") "220uF")
        (field (name "DB_TOLERANCE") "20%")
        (field (name "DB_VOLTAGE") "6.3V")
        (field (name "DB_MANUFACTURER_PART") "SAMSUNG    CL32A227MQVNNNE")
        (field (name "DB_APPROVED_BY") "VSN")
      )
      (libsource (lib "Database_Libs1") (part "C"))
    )
    (comp (ref "C214")
      (value "220uF")
      (footprint "SMD_1210_CAPC3225X279N")
      (fields
        (field (name "DB_PART_NUMBER") "CAP000047355")
        (field (name "DB_VALUE") "220uF")
        (field (name "DB_TOLERANCE") "20%")
        (field (name "DB_VOLTAGE") "6.3V")
        (field (name "DB_MANUFACTURER_PART") "SAMSUNG    CL32A227MQVNNNE")
        (field (name "DB_APPROVED_BY") "VSN")
      )
      (libsource (lib "Database_Libs1") (part "C"))
    )
    (comp (ref "C215")
      (value "220uF")
      (footprint "SMD_1210_CAPC3225X279N")
      (fields
        (field (name "DB_PART_NUMBER") "CAP000047355")
        (field (name "DB_VALUE") "220uF")
        (field (name "DB_TOLERANCE") "20%")
        (field (name "DB_VOLTAGE") "6.3V")
        (field (name "DB_MANUFACTURER_PART") "SAMSUNG    CL32A227MQVNNNE")
        (field (name "DB_APPROVED_BY") "VSN")
      )
      (libsource (lib "Database_Libs1") (part "C"))
    )
    (comp (ref "C216")
      (value "220uF")
      (footprint "SMD_1210_CAPC3225X279N")
      (fields
        (field (name "DB_PART_NUMBER") "CAP000047355")
        (field (name "DB_VALUE") "220uF")
        (field (name "DB_TOLERANCE") "20%")
        (field (name "DB_VOLTAGE") "6.3V")
        (field (name "DB_MANUFACTURER_PART") "SAMSUNG    CL32A227MQVNNNE")
        (field (name "DB_APPROVED_BY") "VSN")
      )
      (libsource (lib "Database_Libs1") (part "C"))
    )
    (comp (ref "C217")
      (value "220uF")
      (footprint "SMD_1210_CAPC3225X279N")
      (fields
        (field (name "DB_PART_NUMBER") "CAP000047355")
        (field (name "DB_VALUE") "220uF")
        (field (name "DB_TOLERANCE") "20%")
        (field (name "DB_VOLTAGE") "6.3V")
        (field (name "DB_MANUFACTURER_PART") "SAMSUNG    CL32A227MQVNNNE")
        (field (name "DB_APPROVED_BY") "VSN")
      )
      (libsource (lib "Database_Libs1") (part "C"))
    )
    (comp (ref "C218")
      (value "220uF")
      (footprint "SMD_1210_CAPC3225X279N")
      (fields
        (field (name "DB_PART_NUMBER") "CAP000047355")
        (field (name "DB_VALUE") "220uF")
        (field (name "DB_TOLERANCE") "20%")
        (field (name "DB_VOLTAGE") "6.3V")
        (field (name "DB_MANUFACTURER_PART") "SAMSUNG    CL32A227MQVNNNE")
        (field (name "DB_APPROVED_BY") "VSN")
      )
      (libsource (lib "Database_Libs1") (part "C"))
    )
    (comp (ref "C219")
      (value "220uF")
      (footprint "SMD_1210_CAPC3225X279N")
      (fields
        (field (name "DB_PART_NUMBER") "CAP000047355")
        (field (name "DB_VALUE") "220uF")
        (field (name "DB_TOLERANCE") "20%")
        (field (name "DB_VOLTAGE") "6.3V")
        (field (name "DB_MANUFACTURER_PART") "SAMSUNG    CL32A227MQVNNNE")
        (field (name "DB_APPROVED_BY") "VSN")
      )
      (libsource (lib "Database_Libs1") (part "C"))
    )
    (comp (ref "C220")
      (value "220uF")
      (footprint "SMD_1210_CAPC3225X279N")
      (fields
        (field (name "DB_PART_NUMBER") "CAP000047355")
        (field (name "DB_VALUE") "220uF")
        (field (name "DB_TOLERANCE") "20%")
        (field (name "DB_VOLTAGE") "6.3V")
        (field (name "DB_MANUFACTURER_PART") "SAMSUNG    CL32A227MQVNNNE")
        (field (name "DB_APPROVED_BY") "VSN")
      )
      (libsource (lib "Database_Libs1") (part "C"))
    )
    (comp (ref "C221")
      (value "220uF")
      (footprint "SMD_1210_CAPC3225X279N")
      (fields
        (field (name "DB_PART_NUMBER") "CAP000047355")
        (field (name "DB_VALUE") "220uF")
        (field (name "DB_TOLERANCE") "20%")
        (field (name "DB_VOLTAGE") "6.3V")
        (field (name "DB_MANUFACTURER_PART") "SAMSUNG    CL32A227MQVNNNE")
        (field (name "DB_APPROVED_BY") "VSN")
      )
      (libsource (lib "Database_Libs1") (part "C"))
    )
    (comp (ref "C222")
      (value "220uF")
      (footprint "SMD_1210_CAPC3225X279N")
      (fields
        (field (name "DB_PART_NUMBER") "CAP000047355")
        (field (name "DB_VALUE") "220uF")
        (field (name "DB_TOLERANCE") "20%")
        (field (name "DB_VOLTAGE") "6.3V")
        (field (name "DB_MANUFACTURER_PART") "SAMSUNG    CL32A227MQVNNNE")
        (field (name "DB_APPROVED_BY") "VSN")
      )
      (libsource (lib "Database_Libs1") (part "C"))
    )
    (comp (ref "C223")
      (value "220uF")
      (footprint "SMD_1210_CAPC3225X279N")
      (fields
        (field (name "DB_PART_NUMBER") "CAP000047355")
        (field (name "DB_VALUE") "220uF")
        (field (name "DB_TOLERANCE") "20%")
        (field (name "DB_VOLTAGE") "6.3V")
        (field (name "DB_MANUFACTURER_PART") "SAMSUNG    CL32A227MQVNNNE")
        (field (name "DB_APPROVED_BY") "VSN")
      )
      (libsource (lib "Database_Libs1") (part "C"))
    )
    (comp (ref "C224")
      (value "220uF")
      (footprint "SMD_1210_CAPC3225X279N")
      (fields
        (field (name "DB_PART_NUMBER") "CAP000047355")
        (field (name "DB_VALUE") "220uF")
        (field (name "DB_TOLERANCE") "20%")
        (field (name "DB_VOLTAGE") "6.3V")
        (field (name "DB_MANUFACTURER_PART") "SAMSUNG    CL32A227MQVNNNE")
        (field (name "DB_APPROVED_BY") "VSN")
      )
      (libsource (lib "Database_Libs1") (part "C"))
    )
    (comp (ref "C225")
      (value "220uF")
      (footprint "SMD_1210_CAPC3225X279N")
      (fields
        (field (name "DB_PART_NUMBER") "CAP000047355")
        (field (name "DB_VALUE") "220uF")
        (field (name "DB_TOLERANCE") "20%")
        (field (name "DB_VOLTAGE") "6.3V")
        (field (name "DB_MANUFACTURER_PART") "SAMSUNG    CL32A227MQVNNNE")
        (field (name "DB_APPROVED_BY") "VSN")
      )
      (libsource (lib "Database_Libs1") (part "C"))
    )
    (comp (ref "C226")
      (value "220uF")
      (footprint "SMD_1210_CAPC3225X279N")
      (fields
        (field (name "DB_PART_NUMBER") "CAP000047355")
        (field (name "DB_VALUE") "220uF")
        (field (name "DB_TOLERANCE") "20%")
        (field (name "DB_VOLTAGE") "6.3V")
        (field (name "DB_MANUFACTURER_PART") "SAMSUNG    CL32A227MQVNNNE")
        (field (name "DB_APPROVED_BY") "VSN")
      )
      (libsource (lib "Database_Libs1") (part "C"))
    )
    (comp (ref "C227")
      (value "22uF")
      (footprint "SMD_0805_CAPC2012X145N")
      (fields
        (field (name "DB_PART_NUMBER") "CAP000043686")
        (field (name "DB_VALUE") "22uF")
        (field (name "DB_TOLERANCE") "20%")
        (field (name "DB_VOLTAGE") "6.3V")
        (field (name "DB_MANUFACTURER_PART") "KEMET    C0805C226M9PAC")
        (field (name "DB_APPROVED_BY") "ISHIDDEN=T")
      )
      (libsource (lib "Database_Libs1") (part "C"))
    )
    (comp (ref "C228")
      (value "22uF")
      (footprint "SMD_0805_CAPC2012X145N")
      (fields
        (field (name "DB_PART_NUMBER") "CAP000043686")
        (field (name "DB_VALUE") "22uF")
        (field (name "DB_TOLERANCE") "20%")
        (field (name "DB_VOLTAGE") "6.3V")
        (field (name "DB_MANUFACTURER_PART") "KEMET    C0805C226M9PAC")
        (field (name "DB_APPROVED_BY") "ISHIDDEN=T")
      )
      (libsource (lib "Database_Libs1") (part "C"))
    )
    (comp (ref "C229")
      (value "22uF")
      (footprint "SMD_0805_CAPC2012X145N")
      (fields
        (field (name "DB_PART_NUMBER") "CAP000043686")
        (field (name "DB_VALUE") "22uF")
        (field (name "DB_TOLERANCE") "20%")
        (field (name "DB_VOLTAGE") "6.3V")
        (field (name "DB_MANUFACTURER_PART") "KEMET    C0805C226M9PAC")
        (field (name "DB_APPROVED_BY") "ISHIDDEN=T")
      )
      (libsource (lib "Database_Libs1") (part "C"))
    )
    (comp (ref "C230")
      (value "22uF")
      (footprint "SMD_0805_CAPC2012X145N")
      (fields
        (field (name "DB_PART_NUMBER") "CAP000043686")
        (field (name "DB_VALUE") "22uF")
        (field (name "DB_TOLERANCE") "20%")
        (field (name "DB_VOLTAGE") "6.3V")
        (field (name "DB_MANUFACTURER_PART") "KEMET    C0805C226M9PAC")
        (field (name "DB_APPROVED_BY") "ISHIDDEN=T")
      )
      (libsource (lib "Database_Libs1") (part "C"))
    )
    (comp (ref "C233")
      (value "22uF")
      (footprint "SMD_0805_CAPC2012X145N")
      (fields
        (field (name "DB_PART_NUMBER") "CAP000043686")
        (field (name "DB_VALUE") "22uF")
        (field (name "DB_TOLERANCE") "20%")
        (field (name "DB_VOLTAGE") "6.3V")
        (field (name "DB_MANUFACTURER_PART") "KEMET    C0805C226M9PAC")
        (field (name "DB_APPROVED_BY") "ISHIDDEN=T")
      )
      (libsource (lib "Database_Libs1") (part "C"))
    )
    (comp (ref "C234")
      (value "22uF")
      (footprint "SMD_0805_CAPC2012X145N")
      (fields
        (field (name "DB_PART_NUMBER") "CAP000043686")
        (field (name "DB_VALUE") "22uF")
        (field (name "DB_TOLERANCE") "20%")
        (field (name "DB_VOLTAGE") "6.3V")
        (field (name "DB_MANUFACTURER_PART") "KEMET    C0805C226M9PAC")
        (field (name "DB_APPROVED_BY") "ISHIDDEN=T")
      )
      (libsource (lib "Database_Libs1") (part "C"))
    )
    (comp (ref "C235")
      (value "220uF")
      (footprint "SMD_1210_CAPC3225X279N")
      (fields
        (field (name "DB_PART_NUMBER") "CAP000047355")
        (field (name "DB_VALUE") "220uF")
        (field (name "DB_TOLERANCE") "20%")
        (field (name "DB_VOLTAGE") "6.3V")
        (field (name "DB_MANUFACTURER_PART") "SAMSUNG    CL32A227MQVNNNE")
        (field (name "DB_APPROVED_BY") "VSN")
      )
      (libsource (lib "Database_Libs1") (part "C"))
    )
    (comp (ref "C237")
      (value "220uF")
      (footprint "SMD_1210_CAPC3225X279N")
      (fields
        (field (name "DB_PART_NUMBER") "CAP000047355")
        (field (name "DB_VALUE") "220uF")
        (field (name "DB_TOLERANCE") "20%")
        (field (name "DB_VOLTAGE") "6.3V")
        (field (name "DB_MANUFACTURER_PART") "SAMSUNG    CL32A227MQVNNNE")
        (field (name "DB_APPROVED_BY") "VSN")
      )
      (libsource (lib "Database_Libs1") (part "C"))
    )
    (comp (ref "C238")
      (value "220uF")
      (footprint "SMD_1210_CAPC3225X279N")
      (fields
        (field (name "DB_PART_NUMBER") "CAP000047355")
        (field (name "DB_VALUE") "220uF")
        (field (name "DB_TOLERANCE") "20%")
        (field (name "DB_VOLTAGE") "6.3V")
        (field (name "DB_MANUFACTURER_PART") "SAMSUNG    CL32A227MQVNNNE")
        (field (name "DB_APPROVED_BY") "VSN")
      )
      (libsource (lib "Database_Libs1") (part "C"))
    )
    (comp (ref "C239")
      (value "220uF")
      (footprint "SMD_1210_CAPC3225X279N")
      (fields
        (field (name "DB_PART_NUMBER") "CAP000047355")
        (field (name "DB_VALUE") "220uF")
        (field (name "DB_TOLERANCE") "20%")
        (field (name "DB_VOLTAGE") "6.3V")
        (field (name "DB_MANUFACTURER_PART") "SAMSUNG    CL32A227MQVNNNE")
        (field (name "DB_APPROVED_BY") "VSN")
      )
      (libsource (lib "Database_Libs1") (part "C"))
    )
    (comp (ref "C240")
      (value "220uF")
      (footprint "SMD_1210_CAPC3225X279N")
      (fields
        (field (name "DB_PART_NUMBER") "CAP000047355")
        (field (name "DB_VALUE") "220uF")
        (field (name "DB_TOLERANCE") "20%")
        (field (name "DB_VOLTAGE") "6.3V")
        (field (name "DB_MANUFACTURER_PART") "SAMSUNG    CL32A227MQVNNNE")
        (field (name "DB_APPROVED_BY") "VSN")
      )
      (libsource (lib "Database_Libs1") (part "C"))
    )
    (comp (ref "C241")
      (value "220uF")
      (footprint "SMD_1210_CAPC3225X279N")
      (fields
        (field (name "DB_PART_NUMBER") "CAP000047355")
        (field (name "DB_VALUE") "220uF")
        (field (name "DB_TOLERANCE") "20%")
        (field (name "DB_VOLTAGE") "6.3V")
        (field (name "DB_MANUFACTURER_PART") "SAMSUNG    CL32A227MQVNNNE")
        (field (name "DB_APPROVED_BY") "VSN")
      )
      (libsource (lib "Database_Libs1") (part "C"))
    )
    (comp (ref "C242")
      (value "220uF")
      (footprint "SMD_1210_CAPC3225X279N")
      (fields
        (field (name "DB_PART_NUMBER") "CAP000047355")
        (field (name "DB_VALUE") "220uF")
        (field (name "DB_TOLERANCE") "20%")
        (field (name "DB_VOLTAGE") "6.3V")
        (field (name "DB_MANUFACTURER_PART") "SAMSUNG    CL32A227MQVNNNE")
        (field (name "DB_APPROVED_BY") "VSN")
      )
      (libsource (lib "Database_Libs1") (part "C"))
    )
    (comp (ref "C243")
      (value "220uF")
      (footprint "SMD_1210_CAPC3225X279N")
      (fields
        (field (name "DB_PART_NUMBER") "CAP000047355")
        (field (name "DB_VALUE") "220uF")
        (field (name "DB_TOLERANCE") "20%")
        (field (name "DB_VOLTAGE") "6.3V")
        (field (name "DB_MANUFACTURER_PART") "SAMSUNG    CL32A227MQVNNNE")
        (field (name "DB_APPROVED_BY") "VSN")
      )
      (libsource (lib "Database_Libs1") (part "C"))
    )
    (comp (ref "C244")
      (value "220uF")
      (footprint "SMD_1210_CAPC3225X279N")
      (fields
        (field (name "DB_PART_NUMBER") "CAP000047355")
        (field (name "DB_VALUE") "220uF")
        (field (name "DB_TOLERANCE") "20%")
        (field (name "DB_VOLTAGE") "6.3V")
        (field (name "DB_MANUFACTURER_PART") "SAMSUNG    CL32A227MQVNNNE")
        (field (name "DB_APPROVED_BY") "VSN")
      )
      (libsource (lib "Database_Libs1") (part "C"))
    )
    (comp (ref "C245")
      (value "220uF")
      (footprint "SMD_1210_CAPC3225X279N")
      (fields
        (field (name "DB_PART_NUMBER") "CAP000047355")
        (field (name "DB_VALUE") "220uF")
        (field (name "DB_TOLERANCE") "20%")
        (field (name "DB_VOLTAGE") "6.3V")
        (field (name "DB_MANUFACTURER_PART") "SAMSUNG    CL32A227MQVNNNE")
        (field (name "DB_APPROVED_BY") "VSN")
      )
      (libsource (lib "Database_Libs1") (part "C"))
    )
    (comp (ref "C246")
      (value "220uF")
      (footprint "SMD_1210_CAPC3225X279N")
      (fields
        (field (name "DB_PART_NUMBER") "CAP000047355")
        (field (name "DB_VALUE") "220uF")
        (field (name "DB_TOLERANCE") "20%")
        (field (name "DB_VOLTAGE") "6.3V")
        (field (name "DB_MANUFACTURER_PART") "SAMSUNG    CL32A227MQVNNNE")
        (field (name "DB_APPROVED_BY") "VSN")
      )
      (libsource (lib "Database_Libs1") (part "C"))
    )
    (comp (ref "C247")
      (value "220uF")
      (footprint "SMD_1210_CAPC3225X279N")
      (fields
        (field (name "DB_PART_NUMBER") "CAP000047355")
        (field (name "DB_VALUE") "220uF")
        (field (name "DB_TOLERANCE") "20%")
        (field (name "DB_VOLTAGE") "6.3V")
        (field (name "DB_MANUFACTURER_PART") "SAMSUNG    CL32A227MQVNNNE")
        (field (name "DB_APPROVED_BY") "VSN")
      )
      (libsource (lib "Database_Libs1") (part "C"))
    )
    (comp (ref "C248")
      (value "220uF")
      (footprint "SMD_1210_CAPC3225X279N")
      (fields
        (field (name "DB_PART_NUMBER") "CAP000047355")
        (field (name "DB_VALUE") "220uF")
        (field (name "DB_TOLERANCE") "20%")
        (field (name "DB_VOLTAGE") "6.3V")
        (field (name "DB_MANUFACTURER_PART") "SAMSUNG    CL32A227MQVNNNE")
        (field (name "DB_APPROVED_BY") "VSN")
      )
      (libsource (lib "Database_Libs1") (part "C"))
    )
    (comp (ref "C249")
      (value "220uF")
      (footprint "SMD_1210_CAPC3225X279N")
      (fields
        (field (name "DB_PART_NUMBER") "CAP000047355")
        (field (name "DB_VALUE") "220uF")
        (field (name "DB_TOLERANCE") "20%")
        (field (name "DB_VOLTAGE") "6.3V")
        (field (name "DB_MANUFACTURER_PART") "SAMSUNG    CL32A227MQVNNNE")
        (field (name "DB_APPROVED_BY") "VSN")
      )
      (libsource (lib "Database_Libs1") (part "C"))
    )
    (comp (ref "C252")
      (value "220uF")
      (footprint "SMD_1210_CAPC3225X279N")
      (fields
        (field (name "DB_PART_NUMBER") "CAP000047355")
        (field (name "DB_VALUE") "220uF")
        (field (name "DB_TOLERANCE") "20%")
        (field (name "DB_VOLTAGE") "6.3V")
        (field (name "DB_MANUFACTURER_PART") "SAMSUNG    CL32A227MQVNNNE")
        (field (name "DB_APPROVED_BY") "VSN")
      )
      (libsource (lib "Database_Libs1") (part "C"))
    )
    (comp (ref "C253")
      (value "220uF")
      (footprint "SMD_1210_CAPC3225X279N")
      (fields
        (field (name "DB_PART_NUMBER") "CAP000047355")
        (field (name "DB_VALUE") "220uF")
        (field (name "DB_TOLERANCE") "20%")
        (field (name "DB_VOLTAGE") "6.3V")
        (field (name "DB_MANUFACTURER_PART") "SAMSUNG    CL32A227MQVNNNE")
        (field (name "DB_APPROVED_BY") "VSN")
      )
      (libsource (lib "Database_Libs1") (part "C"))
    )
    (comp (ref "C254")
      (value "220uF")
      (footprint "SMD_1210_CAPC3225X279N")
      (fields
        (field (name "DB_PART_NUMBER") "CAP000047355")
        (field (name "DB_VALUE") "220uF")
        (field (name "DB_TOLERANCE") "20%")
        (field (name "DB_VOLTAGE") "6.3V")
        (field (name "DB_MANUFACTURER_PART") "SAMSUNG    CL32A227MQVNNNE")
        (field (name "DB_APPROVED_BY") "VSN")
      )
      (libsource (lib "Database_Libs1") (part "C"))
    )
    (comp (ref "C255")
      (value "220uF")
      (footprint "SMD_1210_CAPC3225X279N")
      (fields
        (field (name "DB_PART_NUMBER") "CAP000047355")
        (field (name "DB_VALUE") "220uF")
        (field (name "DB_TOLERANCE") "20%")
        (field (name "DB_VOLTAGE") "6.3V")
        (field (name "DB_MANUFACTURER_PART") "SAMSUNG    CL32A227MQVNNNE")
        (field (name "DB_APPROVED_BY") "VSN")
      )
      (libsource (lib "Database_Libs1") (part "C"))
    )
    (comp (ref "C256")
      (value "220uF")
      (footprint "SMD_1210_CAPC3225X279N")
      (fields
        (field (name "DB_PART_NUMBER") "CAP000047355")
        (field (name "DB_VALUE") "220uF")
        (field (name "DB_TOLERANCE") "20%")
        (field (name "DB_VOLTAGE") "6.3V")
        (field (name "DB_MANUFACTURER_PART") "SAMSUNG    CL32A227MQVNNNE")
        (field (name "DB_APPROVED_BY") "VSN")
      )
      (libsource (lib "Database_Libs1") (part "C"))
    )
    (comp (ref "C257")
      (value "220uF")
      (footprint "SMD_1210_CAPC3225X279N")
      (fields
        (field (name "DB_PART_NUMBER") "CAP000047355")
        (field (name "DB_VALUE") "220uF")
        (field (name "DB_TOLERANCE") "20%")
        (field (name "DB_VOLTAGE") "6.3V")
        (field (name "DB_MANUFACTURER_PART") "SAMSUNG    CL32A227MQVNNNE")
        (field (name "DB_APPROVED_BY") "VSN")
      )
      (libsource (lib "Database_Libs1") (part "C"))
    )
    (comp (ref "C258")
      (value "220uF")
      (footprint "SMD_1210_CAPC3225X279N")
      (fields
        (field (name "DB_PART_NUMBER") "CAP000047355")
        (field (name "DB_VALUE") "220uF")
        (field (name "DB_TOLERANCE") "20%")
        (field (name "DB_VOLTAGE") "6.3V")
        (field (name "DB_MANUFACTURER_PART") "SAMSUNG    CL32A227MQVNNNE")
        (field (name "DB_APPROVED_BY") "VSN")
      )
      (libsource (lib "Database_Libs1") (part "C"))
    )
    (comp (ref "C259")
      (value "220uF")
      (footprint "SMD_1210_CAPC3225X279N")
      (fields
        (field (name "DB_PART_NUMBER") "CAP000047355")
        (field (name "DB_VALUE") "220uF")
        (field (name "DB_TOLERANCE") "20%")
        (field (name "DB_VOLTAGE") "6.3V")
        (field (name "DB_MANUFACTURER_PART") "SAMSUNG    CL32A227MQVNNNE")
        (field (name "DB_APPROVED_BY") "VSN")
      )
      (libsource (lib "Database_Libs1") (part "C"))
    )
    (comp (ref "C260")
      (value "220uF")
      (footprint "SMD_1210_CAPC3225X279N")
      (fields
        (field (name "DB_PART_NUMBER") "CAP000047355")
        (field (name "DB_VALUE") "220uF")
        (field (name "DB_TOLERANCE") "20%")
        (field (name "DB_VOLTAGE") "6.3V")
        (field (name "DB_MANUFACTURER_PART") "SAMSUNG    CL32A227MQVNNNE")
        (field (name "DB_APPROVED_BY") "VSN")
      )
      (libsource (lib "Database_Libs1") (part "C"))
    )
    (comp (ref "C261")
      (value "220uF")
      (footprint "SMD_1210_CAPC3225X279N")
      (fields
        (field (name "DB_PART_NUMBER") "CAP000047355")
        (field (name "DB_VALUE") "220uF")
        (field (name "DB_TOLERANCE") "20%")
        (field (name "DB_VOLTAGE") "6.3V")
        (field (name "DB_MANUFACTURER_PART") "SAMSUNG    CL32A227MQVNNNE")
        (field (name "DB_APPROVED_BY") "VSN")
      )
      (libsource (lib "Database_Libs1") (part "C"))
    )
    (comp (ref "C262")
      (value "220uF")
      (footprint "SMD_1210_CAPC3225X279N")
      (fields
        (field (name "DB_PART_NUMBER") "CAP000047355")
        (field (name "DB_VALUE") "220uF")
        (field (name "DB_TOLERANCE") "20%")
        (field (name "DB_VOLTAGE") "6.3V")
        (field (name "DB_MANUFACTURER_PART") "SAMSUNG    CL32A227MQVNNNE")
        (field (name "DB_APPROVED_BY") "VSN")
      )
      (libsource (lib "Database_Libs1") (part "C"))
    )
    (comp (ref "C263")
      (value "220uF")
      (footprint "SMD_1210_CAPC3225X279N")
      (fields
        (field (name "DB_PART_NUMBER") "CAP000047355")
        (field (name "DB_VALUE") "220uF")
        (field (name "DB_TOLERANCE") "20%")
        (field (name "DB_VOLTAGE") "6.3V")
        (field (name "DB_MANUFACTURER_PART") "SAMSUNG    CL32A227MQVNNNE")
        (field (name "DB_APPROVED_BY") "VSN")
      )
      (libsource (lib "Database_Libs1") (part "C"))
    )
    (comp (ref "C264")
      (value "220uF")
      (footprint "SMD_1210_CAPC3225X279N")
      (fields
        (field (name "DB_PART_NUMBER") "CAP000047355")
        (field (name "DB_VALUE") "220uF")
        (field (name "DB_TOLERANCE") "20%")
        (field (name "DB_VOLTAGE") "6.3V")
        (field (name "DB_MANUFACTURER_PART") "SAMSUNG    CL32A227MQVNNNE")
        (field (name "DB_APPROVED_BY") "VSN")
      )
      (libsource (lib "Database_Libs1") (part "C"))
    )
    (comp (ref "C265")
      (value "220uF")
      (footprint "SMD_1210_CAPC3225X279N")
      (fields
        (field (name "DB_PART_NUMBER") "CAP000047355")
        (field (name "DB_VALUE") "220uF")
        (field (name "DB_TOLERANCE") "20%")
        (field (name "DB_VOLTAGE") "6.3V")
        (field (name "DB_MANUFACTURER_PART") "SAMSUNG    CL32A227MQVNNNE")
        (field (name "DB_APPROVED_BY") "VSN")
      )
      (libsource (lib "Database_Libs1") (part "C"))
    )
    (comp (ref "C266")
      (value "220uF")
      (footprint "SMD_1210_CAPC3225X279N")
      (fields
        (field (name "DB_PART_NUMBER") "CAP000047355")
        (field (name "DB_VALUE") "220uF")
        (field (name "DB_TOLERANCE") "20%")
        (field (name "DB_VOLTAGE") "6.3V")
        (field (name "DB_MANUFACTURER_PART") "SAMSUNG    CL32A227MQVNNNE")
        (field (name "DB_APPROVED_BY") "VSN")
      )
      (libsource (lib "Database_Libs1") (part "C"))
    )
    (comp (ref "C267")
      (value "220uF")
      (footprint "SMD_1210_CAPC3225X279N")
      (fields
        (field (name "DB_PART_NUMBER") "CAP000047355")
        (field (name "DB_VALUE") "220uF")
        (field (name "DB_TOLERANCE") "20%")
        (field (name "DB_VOLTAGE") "6.3V")
        (field (name "DB_MANUFACTURER_PART") "SAMSUNG    CL32A227MQVNNNE")
        (field (name "DB_APPROVED_BY") "VSN")
      )
      (libsource (lib "Database_Libs1") (part "C"))
    )
    (comp (ref "C268")
      (value "220uF")
      (footprint "SMD_1210_CAPC3225X279N")
      (fields
        (field (name "DB_PART_NUMBER") "CAP000047355")
        (field (name "DB_VALUE") "220uF")
        (field (name "DB_TOLERANCE") "20%")
        (field (name "DB_VOLTAGE") "6.3V")
        (field (name "DB_MANUFACTURER_PART") "SAMSUNG    CL32A227MQVNNNE")
        (field (name "DB_APPROVED_BY") "VSN")
      )
      (libsource (lib "Database_Libs1") (part "C"))
    )
    (comp (ref "C269")
      (value "220uF")
      (footprint "SMD_1210_CAPC3225X279N")
      (fields
        (field (name "DB_PART_NUMBER") "CAP000047355")
        (field (name "DB_VALUE") "220uF")
        (field (name "DB_TOLERANCE") "20%")
        (field (name "DB_VOLTAGE") "6.3V")
        (field (name "DB_MANUFACTURER_PART") "SAMSUNG    CL32A227MQVNNNE")
        (field (name "DB_APPROVED_BY") "VSN")
      )
      (libsource (lib "Database_Libs1") (part "C"))
    )
    (comp (ref "C270")
      (value "220uF")
      (footprint "SMD_1210_CAPC3225X279N")
      (fields
        (field (name "DB_PART_NUMBER") "CAP000047355")
        (field (name "DB_VALUE") "220uF")
        (field (name "DB_TOLERANCE") "20%")
        (field (name "DB_VOLTAGE") "6.3V")
        (field (name "DB_MANUFACTURER_PART") "SAMSUNG    CL32A227MQVNNNE")
        (field (name "DB_APPROVED_BY") "VSN")
      )
      (libsource (lib "Database_Libs1") (part "C"))
    )
    (comp (ref "C271")
      (value "220uF")
      (footprint "SMD_1210_CAPC3225X279N")
      (fields
        (field (name "DB_PART_NUMBER") "CAP000047355")
        (field (name "DB_VALUE") "220uF")
        (field (name "DB_TOLERANCE") "20%")
        (field (name "DB_VOLTAGE") "6.3V")
        (field (name "DB_MANUFACTURER_PART") "SAMSUNG    CL32A227MQVNNNE")
        (field (name "DB_APPROVED_BY") "VSN")
      )
      (libsource (lib "Database_Libs1") (part "C"))
    )
    (comp (ref "C272")
      (value "220uF")
      (footprint "SMD_1210_CAPC3225X279N")
      (fields
        (field (name "DB_PART_NUMBER") "CAP000047355")
        (field (name "DB_VALUE") "220uF")
        (field (name "DB_TOLERANCE") "20%")
        (field (name "DB_VOLTAGE") "6.3V")
        (field (name "DB_MANUFACTURER_PART") "SAMSUNG    CL32A227MQVNNNE")
        (field (name "DB_APPROVED_BY") "VSN")
      )
      (libsource (lib "Database_Libs1") (part "C"))
    )
    (comp (ref "C273")
      (value "220uF")
      (footprint "SMD_1210_CAPC3225X279N")
      (fields
        (field (name "DB_PART_NUMBER") "CAP000047355")
        (field (name "DB_VALUE") "220uF")
        (field (name "DB_TOLERANCE") "20%")
        (field (name "DB_VOLTAGE") "6.3V")
        (field (name "DB_MANUFACTURER_PART") "SAMSUNG    CL32A227MQVNNNE")
        (field (name "DB_APPROVED_BY") "VSN")
      )
      (libsource (lib "Database_Libs1") (part "C"))
    )
    (comp (ref "C274")
      (value "220uF")
      (footprint "SMD_1210_CAPC3225X279N")
      (fields
        (field (name "DB_PART_NUMBER") "CAP000047355")
        (field (name "DB_VALUE") "220uF")
        (field (name "DB_TOLERANCE") "20%")
        (field (name "DB_VOLTAGE") "6.3V")
        (field (name "DB_MANUFACTURER_PART") "SAMSUNG    CL32A227MQVNNNE")
        (field (name "DB_APPROVED_BY") "VSN")
      )
      (libsource (lib "Database_Libs1") (part "C"))
    )
    (comp (ref "C275")
      (value "220uF")
      (footprint "SMD_1210_CAPC3225X279N")
      (fields
        (field (name "DB_PART_NUMBER") "CAP000047355")
        (field (name "DB_VALUE") "220uF")
        (field (name "DB_TOLERANCE") "20%")
        (field (name "DB_VOLTAGE") "6.3V")
        (field (name "DB_MANUFACTURER_PART") "SAMSUNG    CL32A227MQVNNNE")
        (field (name "DB_APPROVED_BY") "VSN")
      )
      (libsource (lib "Database_Libs1") (part "C"))
    )
    (comp (ref "C276")
      (value "220uF")
      (footprint "SMD_1210_CAPC3225X279N")
      (fields
        (field (name "DB_PART_NUMBER") "CAP000047355")
        (field (name "DB_VALUE") "220uF")
        (field (name "DB_TOLERANCE") "20%")
        (field (name "DB_VOLTAGE") "6.3V")
        (field (name "DB_MANUFACTURER_PART") "SAMSUNG    CL32A227MQVNNNE")
        (field (name "DB_APPROVED_BY") "VSN")
      )
      (libsource (lib "Database_Libs1") (part "C"))
    )
    (comp (ref "C277")
      (value "220uF")
      (footprint "SMD_1210_CAPC3225X279N")
      (fields
        (field (name "DB_PART_NUMBER") "CAP000047355")
        (field (name "DB_VALUE") "220uF")
        (field (name "DB_TOLERANCE") "20%")
        (field (name "DB_VOLTAGE") "6.3V")
        (field (name "DB_MANUFACTURER_PART") "SAMSUNG    CL32A227MQVNNNE")
        (field (name "DB_APPROVED_BY") "VSN")
      )
      (libsource (lib "Database_Libs1") (part "C"))
    )
    (comp (ref "C278")
      (value "220uF")
      (footprint "SMD_1210_CAPC3225X279N")
      (fields
        (field (name "DB_PART_NUMBER") "CAP000047355")
        (field (name "DB_VALUE") "220uF")
        (field (name "DB_TOLERANCE") "20%")
        (field (name "DB_VOLTAGE") "6.3V")
        (field (name "DB_MANUFACTURER_PART") "SAMSUNG    CL32A227MQVNNNE")
        (field (name "DB_APPROVED_BY") "VSN")
      )
      (libsource (lib "Database_Libs1") (part "C"))
    )
    (comp (ref "C279")
      (value "220uF")
      (footprint "SMD_1210_CAPC3225X279N")
      (fields
        (field (name "DB_PART_NUMBER") "CAP000047355")
        (field (name "DB_VALUE") "220uF")
        (field (name "DB_TOLERANCE") "20%")
        (field (name "DB_VOLTAGE") "6.3V")
        (field (name "DB_MANUFACTURER_PART") "SAMSUNG    CL32A227MQVNNNE")
        (field (name "DB_APPROVED_BY") "VSN")
      )
      (libsource (lib "Database_Libs1") (part "C"))
    )
    (comp (ref "C280")
      (value "220uF")
      (footprint "SMD_1210_CAPC3225X279N")
      (fields
        (field (name "DB_PART_NUMBER") "CAP000047355")
        (field (name "DB_VALUE") "220uF")
        (field (name "DB_TOLERANCE") "20%")
        (field (name "DB_VOLTAGE") "6.3V")
        (field (name "DB_MANUFACTURER_PART") "SAMSUNG    CL32A227MQVNNNE")
        (field (name "DB_APPROVED_BY") "VSN")
      )
      (libsource (lib "Database_Libs1") (part "C"))
    )
    (comp (ref "C281")
      (value "220uF")
      (footprint "SMD_1210_CAPC3225X279N")
      (fields
        (field (name "DB_PART_NUMBER") "CAP000047355")
        (field (name "DB_VALUE") "220uF")
        (field (name "DB_TOLERANCE") "20%")
        (field (name "DB_VOLTAGE") "6.3V")
        (field (name "DB_MANUFACTURER_PART") "SAMSUNG    CL32A227MQVNNNE")
        (field (name "DB_APPROVED_BY") "VSN")
      )
      (libsource (lib "Database_Libs1") (part "C"))
    )
    (comp (ref "C282")
      (value "220uF")
      (footprint "SMD_1210_CAPC3225X279N")
      (fields
        (field (name "DB_PART_NUMBER") "CAP000047355")
        (field (name "DB_VALUE") "220uF")
        (field (name "DB_TOLERANCE") "20%")
        (field (name "DB_VOLTAGE") "6.3V")
        (field (name "DB_MANUFACTURER_PART") "SAMSUNG    CL32A227MQVNNNE")
        (field (name "DB_APPROVED_BY") "VSN")
      )
      (libsource (lib "Database_Libs1") (part "C"))
    )
    (comp (ref "C283")
      (value "220uF")
      (footprint "SMD_1210_CAPC3225X279N")
      (fields
        (field (name "DB_PART_NUMBER") "CAP000047355")
        (field (name "DB_VALUE") "220uF")
        (field (name "DB_TOLERANCE") "20%")
        (field (name "DB_VOLTAGE") "6.3V")
        (field (name "DB_MANUFACTURER_PART") "SAMSUNG    CL32A227MQVNNNE")
        (field (name "DB_APPROVED_BY") "VSN")
      )
      (libsource (lib "Database_Libs1") (part "C"))
    )
    (comp (ref "C284")
      (value "220uF")
      (footprint "SMD_1210_CAPC3225X279N")
      (fields
        (field (name "DB_PART_NUMBER") "CAP000047355")
        (field (name "DB_VALUE") "220uF")
        (field (name "DB_TOLERANCE") "20%")
        (field (name "DB_VOLTAGE") "6.3V")
        (field (name "DB_MANUFACTURER_PART") "SAMSUNG    CL32A227MQVNNNE")
        (field (name "DB_APPROVED_BY") "VSN")
      )
      (libsource (lib "Database_Libs1") (part "C"))
    )
    (comp (ref "C285")
      (value "220uF")
      (footprint "SMD_1210_CAPC3225X279N")
      (fields
        (field (name "DB_PART_NUMBER") "CAP000047355")
        (field (name "DB_VALUE") "220uF")
        (field (name "DB_TOLERANCE") "20%")
        (field (name "DB_VOLTAGE") "6.3V")
        (field (name "DB_MANUFACTURER_PART") "SAMSUNG    CL32A227MQVNNNE")
        (field (name "DB_APPROVED_BY") "VSN")
      )
      (libsource (lib "Database_Libs1") (part "C"))
    )
    (comp (ref "C286")
      (value "220uF")
      (footprint "SMD_1210_CAPC3225X279N")
      (fields
        (field (name "DB_PART_NUMBER") "CAP000047355")
        (field (name "DB_VALUE") "220uF")
        (field (name "DB_TOLERANCE") "20%")
        (field (name "DB_VOLTAGE") "6.3V")
        (field (name "DB_MANUFACTURER_PART") "SAMSUNG    CL32A227MQVNNNE")
        (field (name "DB_APPROVED_BY") "VSN")
      )
      (libsource (lib "Database_Libs1") (part "C"))
    )
    (comp (ref "C287")
      (value "220uF")
      (footprint "SMD_1210_CAPC3225X279N")
      (fields
        (field (name "DB_PART_NUMBER") "CAP000047355")
        (field (name "DB_VALUE") "220uF")
        (field (name "DB_TOLERANCE") "20%")
        (field (name "DB_VOLTAGE") "6.3V")
        (field (name "DB_MANUFACTURER_PART") "SAMSUNG    CL32A227MQVNNNE")
        (field (name "DB_APPROVED_BY") "VSN")
      )
      (libsource (lib "Database_Libs1") (part "C"))
    )
    (comp (ref "C288")
      (value "100nF")
      (footprint "SMD_0603_CAPC1608X95N")
      (fields
        (field (name "DB_PART_NUMBER") "CAP000027236")
        (field (name "DB_VALUE") "100nF")
        (field (name "DB_TOLERANCE") "20%")
        (field (name "DB_VOLTAGE") "16V")
        (field (name "DB_MANUFACTURER_PART") "KEMET    C0603C104M4RAC")
        (field (name "DB_APPROVED_BY") "ISHIDDEN=T")
      )
      (libsource (lib "Database_Libs1") (part "C"))
    )
    (comp (ref "C289")
      (value "100nF")
      (footprint "SMD_0603_CAPC1608X95N")
      (fields
        (field (name "DB_PART_NUMBER") "CAP000027236")
        (field (name "DB_VALUE") "100nF")
        (field (name "DB_TOLERANCE") "20%")
        (field (name "DB_VOLTAGE") "16V")
        (field (name "DB_MANUFACTURER_PART") "KEMET    C0603C104M4RAC")
        (field (name "DB_APPROVED_BY") "ISHIDDEN=T")
      )
      (libsource (lib "Database_Libs1") (part "C"))
    )
    (comp (ref "C290")
      (value "100nF")
      (footprint "SMD_0603_CAPC1608X95N")
      (fields
        (field (name "DB_PART_NUMBER") "CAP000027236")
        (field (name "DB_VALUE") "100nF")
        (field (name "DB_TOLERANCE") "20%")
        (field (name "DB_VOLTAGE") "16V")
        (field (name "DB_MANUFACTURER_PART") "KEMET    C0603C104M4RAC")
        (field (name "DB_APPROVED_BY") "ISHIDDEN=T")
      )
      (libsource (lib "Database_Libs1") (part "C"))
    )
    (comp (ref "C291")
      (value "100nF")
      (footprint "SMD_0603_CAPC1608X95N")
      (fields
        (field (name "DB_PART_NUMBER") "CAP000027236")
        (field (name "DB_VALUE") "100nF")
        (field (name "DB_TOLERANCE") "20%")
        (field (name "DB_VOLTAGE") "16V")
        (field (name "DB_MANUFACTURER_PART") "KEMET    C0603C104M4RAC")
        (field (name "DB_APPROVED_BY") "ISHIDDEN=T")
      )
      (libsource (lib "Database_Libs1") (part "C"))
    )
    (comp (ref "C292")
      (value "100nF")
      (footprint "SMD_0603_CAPC1608X95N")
      (fields
        (field (name "DB_PART_NUMBER") "CAP000027236")
        (field (name "DB_VALUE") "100nF")
        (field (name "DB_TOLERANCE") "20%")
        (field (name "DB_VOLTAGE") "16V")
        (field (name "DB_MANUFACTURER_PART") "KEMET    C0603C104M4RAC")
        (field (name "DB_APPROVED_BY") "ISHIDDEN=T")
      )
      (libsource (lib "Database_Libs1") (part "C"))
    )
    (comp (ref "C293")
      (value "100nF")
      (footprint "SMD_0603_CAPC1608X95N")
      (fields
        (field (name "DB_PART_NUMBER") "CAP000027236")
        (field (name "DB_VALUE") "100nF")
        (field (name "DB_TOLERANCE") "20%")
        (field (name "DB_VOLTAGE") "16V")
        (field (name "DB_MANUFACTURER_PART") "KEMET    C0603C104M4RAC")
        (field (name "DB_APPROVED_BY") "ISHIDDEN=T")
      )
      (libsource (lib "Database_Libs1") (part "C"))
    )
    (comp (ref "C294")
      (value "100nF")
      (footprint "SMD_0603_CAPC1608X95N")
      (fields
        (field (name "DB_PART_NUMBER") "CAP000027236")
        (field (name "DB_VALUE") "100nF")
        (field (name "DB_TOLERANCE") "20%")
        (field (name "DB_VOLTAGE") "16V")
        (field (name "DB_MANUFACTURER_PART") "KEMET    C0603C104M4RAC")
        (field (name "DB_APPROVED_BY") "ISHIDDEN=T")
      )
      (libsource (lib "Database_Libs1") (part "C"))
    )
    (comp (ref "C295")
      (value "100nF")
      (footprint "SMD_0603_CAPC1608X95N")
      (fields
        (field (name "DB_PART_NUMBER") "CAP000027236")
        (field (name "DB_VALUE") "100nF")
        (field (name "DB_TOLERANCE") "20%")
        (field (name "DB_VOLTAGE") "16V")
        (field (name "DB_MANUFACTURER_PART") "KEMET    C0603C104M4RAC")
        (field (name "DB_APPROVED_BY") "ISHIDDEN=T")
      )
      (libsource (lib "Database_Libs1") (part "C"))
    )
    (comp (ref "C296")
      (value "100nF")
      (footprint "SMD_0603_CAPC1608X95N")
      (fields
        (field (name "DB_PART_NUMBER") "CAP000027236")
        (field (name "DB_VALUE") "100nF")
        (field (name "DB_TOLERANCE") "20%")
        (field (name "DB_VOLTAGE") "16V")
        (field (name "DB_MANUFACTURER_PART") "KEMET    C0603C104M4RAC")
        (field (name "DB_APPROVED_BY") "ISHIDDEN=T")
      )
      (libsource (lib "Database_Libs1") (part "C"))
    )
    (comp (ref "C297")
      (value "100nF")
      (footprint "SMD_0603_CAPC1608X95N")
      (fields
        (field (name "DB_PART_NUMBER") "CAP000027236")
        (field (name "DB_VALUE") "100nF")
        (field (name "DB_TOLERANCE") "20%")
        (field (name "DB_VOLTAGE") "16V")
        (field (name "DB_MANUFACTURER_PART") "KEMET    C0603C104M4RAC")
        (field (name "DB_APPROVED_BY") "ISHIDDEN=T")
      )
      (libsource (lib "Database_Libs1") (part "C"))
    )
    (comp (ref "C298")
      (value "100nF")
      (footprint "SMD_0603_CAPC1608X95N")
      (fields
        (field (name "DB_PART_NUMBER") "CAP000027236")
        (field (name "DB_VALUE") "100nF")
        (field (name "DB_TOLERANCE") "20%")
        (field (name "DB_VOLTAGE") "16V")
        (field (name "DB_MANUFACTURER_PART") "KEMET    C0603C104M4RAC")
        (field (name "DB_APPROVED_BY") "ISHIDDEN=T")
      )
      (libsource (lib "Database_Libs1") (part "C"))
    )
    (comp (ref "C299")
      (value "100nF")
      (footprint "SMD_0603_CAPC1608X95N")
      (fields
        (field (name "DB_PART_NUMBER") "CAP000027236")
        (field (name "DB_VALUE") "100nF")
        (field (name "DB_TOLERANCE") "20%")
        (field (name "DB_VOLTAGE") "16V")
        (field (name "DB_MANUFACTURER_PART") "KEMET    C0603C104M4RAC")
        (field (name "DB_APPROVED_BY") "ISHIDDEN=T")
      )
      (libsource (lib "Database_Libs1") (part "C"))
    )
    (comp (ref "C300")
      (value "100nF")
      (footprint "SMD_0603_CAPC1608X95N")
      (fields
        (field (name "DB_PART_NUMBER") "CAP000027236")
        (field (name "DB_VALUE") "100nF")
        (field (name "DB_TOLERANCE") "20%")
        (field (name "DB_VOLTAGE") "16V")
        (field (name "DB_MANUFACTURER_PART") "KEMET    C0603C104M4RAC")
        (field (name "DB_APPROVED_BY") "ISHIDDEN=T")
      )
      (libsource (lib "Database_Libs1") (part "C"))
    )
    (comp (ref "C301")
      (value "100nF")
      (footprint "SMD_0603_CAPC1608X95N")
      (fields
        (field (name "DB_PART_NUMBER") "CAP000027236")
        (field (name "DB_VALUE") "100nF")
        (field (name "DB_TOLERANCE") "20%")
        (field (name "DB_VOLTAGE") "16V")
        (field (name "DB_MANUFACTURER_PART") "KEMET    C0603C104M4RAC")
        (field (name "DB_APPROVED_BY") "ISHIDDEN=T")
      )
      (libsource (lib "Database_Libs1") (part "C"))
    )
    (comp (ref "C302")
      (value "100nF")
      (footprint "SMD_0603_CAPC1608X95N")
      (fields
        (field (name "DB_PART_NUMBER") "CAP000027236")
        (field (name "DB_VALUE") "100nF")
        (field (name "DB_TOLERANCE") "20%")
        (field (name "DB_VOLTAGE") "16V")
        (field (name "DB_MANUFACTURER_PART") "KEMET    C0603C104M4RAC")
        (field (name "DB_APPROVED_BY") "ISHIDDEN=T")
      )
      (libsource (lib "Database_Libs1") (part "C"))
    )
    (comp (ref "C303")
      (value "100nF")
      (footprint "SMD_0603_CAPC1608X95N")
      (fields
        (field (name "DB_PART_NUMBER") "CAP000027236")
        (field (name "DB_VALUE") "100nF")
        (field (name "DB_TOLERANCE") "20%")
        (field (name "DB_VOLTAGE") "16V")
        (field (name "DB_MANUFACTURER_PART") "KEMET    C0603C104M4RAC")
        (field (name "DB_APPROVED_BY") "ISHIDDEN=T")
      )
      (libsource (lib "Database_Libs1") (part "C"))
    )
    (comp (ref "C304")
      (value "100nF")
      (footprint "SMD_0603_CAPC1608X95N")
      (fields
        (field (name "DB_PART_NUMBER") "CAP000027236")
        (field (name "DB_VALUE") "100nF")
        (field (name "DB_TOLERANCE") "20%")
        (field (name "DB_VOLTAGE") "16V")
        (field (name "DB_MANUFACTURER_PART") "KEMET    C0603C104M4RAC")
        (field (name "DB_APPROVED_BY") "ISHIDDEN=T")
      )
      (libsource (lib "Database_Libs1") (part "C"))
    )
    (comp (ref "C305")
      (value "100nF")
      (footprint "SMD_0603_CAPC1608X95N")
      (fields
        (field (name "DB_PART_NUMBER") "CAP000027236")
        (field (name "DB_VALUE") "100nF")
        (field (name "DB_TOLERANCE") "20%")
        (field (name "DB_VOLTAGE") "16V")
        (field (name "DB_MANUFACTURER_PART") "KEMET    C0603C104M4RAC")
        (field (name "DB_APPROVED_BY") "ISHIDDEN=T")
      )
      (libsource (lib "Database_Libs1") (part "C"))
    )
    (comp (ref "C306")
      (value "100nF")
      (footprint "SMD_0603_CAPC1608X95N")
      (fields
        (field (name "DB_PART_NUMBER") "CAP000027236")
        (field (name "DB_VALUE") "100nF")
        (field (name "DB_TOLERANCE") "20%")
        (field (name "DB_VOLTAGE") "16V")
        (field (name "DB_MANUFACTURER_PART") "KEMET    C0603C104M4RAC")
        (field (name "DB_APPROVED_BY") "ISHIDDEN=T")
      )
      (libsource (lib "Database_Libs1") (part "C"))
    )
    (comp (ref "C307")
      (value "100nF")
      (footprint "SMD_0603_CAPC1608X95N")
      (fields
        (field (name "DB_PART_NUMBER") "CAP000027236")
        (field (name "DB_VALUE") "100nF")
        (field (name "DB_TOLERANCE") "20%")
        (field (name "DB_VOLTAGE") "16V")
        (field (name "DB_MANUFACTURER_PART") "KEMET    C0603C104M4RAC")
        (field (name "DB_APPROVED_BY") "ISHIDDEN=T")
      )
      (libsource (lib "Database_Libs1") (part "C"))
    )
    (comp (ref "C308")
      (value "100nF")
      (footprint "SMD_0603_CAPC1608X95N")
      (fields
        (field (name "DB_PART_NUMBER") "CAP000027236")
        (field (name "DB_VALUE") "100nF")
        (field (name "DB_TOLERANCE") "20%")
        (field (name "DB_VOLTAGE") "16V")
        (field (name "DB_MANUFACTURER_PART") "KEMET    C0603C104M4RAC")
        (field (name "DB_APPROVED_BY") "ISHIDDEN=T")
      )
      (libsource (lib "Database_Libs1") (part "C"))
    )
    (comp (ref "C309")
      (value "100nF")
      (footprint "SMD_0603_CAPC1608X95N")
      (fields
        (field (name "DB_PART_NUMBER") "CAP000027236")
        (field (name "DB_VALUE") "100nF")
        (field (name "DB_TOLERANCE") "20%")
        (field (name "DB_VOLTAGE") "16V")
        (field (name "DB_MANUFACTURER_PART") "KEMET    C0603C104M4RAC")
        (field (name "DB_APPROVED_BY") "ISHIDDEN=T")
      )
      (libsource (lib "Database_Libs1") (part "C"))
    )
    (comp (ref "C310")
      (value "100nF")
      (footprint "SMD_0603_CAPC1608X95N")
      (fields
        (field (name "DB_PART_NUMBER") "CAP000027236")
        (field (name "DB_VALUE") "100nF")
        (field (name "DB_TOLERANCE") "20%")
        (field (name "DB_VOLTAGE") "16V")
        (field (name "DB_MANUFACTURER_PART") "KEMET    C0603C104M4RAC")
        (field (name "DB_APPROVED_BY") "ISHIDDEN=T")
      )
      (libsource (lib "Database_Libs1") (part "C"))
    )
    (comp (ref "C311")
      (value "100nF")
      (footprint "SMD_0603_CAPC1608X95N")
      (fields
        (field (name "DB_PART_NUMBER") "CAP000027236")
        (field (name "DB_VALUE") "100nF")
        (field (name "DB_TOLERANCE") "20%")
        (field (name "DB_VOLTAGE") "16V")
        (field (name "DB_MANUFACTURER_PART") "KEMET    C0603C104M4RAC")
        (field (name "DB_APPROVED_BY") "ISHIDDEN=T")
      )
      (libsource (lib "Database_Libs1") (part "C"))
    )
    (comp (ref "C312")
      (value "100nF")
      (footprint "SMD_0603_CAPC1608X95N")
      (fields
        (field (name "DB_PART_NUMBER") "CAP000027236")
        (field (name "DB_VALUE") "100nF")
        (field (name "DB_TOLERANCE") "20%")
        (field (name "DB_VOLTAGE") "16V")
        (field (name "DB_MANUFACTURER_PART") "KEMET    C0603C104M4RAC")
        (field (name "DB_APPROVED_BY") "ISHIDDEN=T")
      )
      (libsource (lib "Database_Libs1") (part "C"))
    )
    (comp (ref "C313")
      (value "100nF")
      (footprint "SMD_0603_CAPC1608X95N")
      (fields
        (field (name "DB_PART_NUMBER") "CAP000027236")
        (field (name "DB_VALUE") "100nF")
        (field (name "DB_TOLERANCE") "20%")
        (field (name "DB_VOLTAGE") "16V")
        (field (name "DB_MANUFACTURER_PART") "KEMET    C0603C104M4RAC")
        (field (name "DB_APPROVED_BY") "ISHIDDEN=T")
      )
      (libsource (lib "Database_Libs1") (part "C"))
    )
    (comp (ref "C314")
      (value "100nF")
      (footprint "SMD_0603_CAPC1608X95N")
      (fields
        (field (name "DB_PART_NUMBER") "CAP000027236")
        (field (name "DB_VALUE") "100nF")
        (field (name "DB_TOLERANCE") "20%")
        (field (name "DB_VOLTAGE") "16V")
        (field (name "DB_MANUFACTURER_PART") "KEMET    C0603C104M4RAC")
        (field (name "DB_APPROVED_BY") "ISHIDDEN=T")
      )
      (libsource (lib "Database_Libs1") (part "C"))
    )
    (comp (ref "C315")
      (value "100nF")
      (footprint "SMD_0603_CAPC1608X95N")
      (fields
        (field (name "DB_PART_NUMBER") "CAP000027236")
        (field (name "DB_VALUE") "100nF")
        (field (name "DB_TOLERANCE") "20%")
        (field (name "DB_VOLTAGE") "16V")
        (field (name "DB_MANUFACTURER_PART") "KEMET    C0603C104M4RAC")
        (field (name "DB_APPROVED_BY") "ISHIDDEN=T")
      )
      (libsource (lib "Database_Libs1") (part "C"))
    )
    (comp (ref "C316")
      (value "100nF")
      (footprint "SMD_0603_CAPC1608X95N")
      (fields
        (field (name "DB_PART_NUMBER") "CAP000027236")
        (field (name "DB_VALUE") "100nF")
        (field (name "DB_TOLERANCE") "20%")
        (field (name "DB_VOLTAGE") "16V")
        (field (name "DB_MANUFACTURER_PART") "KEMET    C0603C104M4RAC")
        (field (name "DB_APPROVED_BY") "ISHIDDEN=T")
      )
      (libsource (lib "Database_Libs1") (part "C"))
    )
    (comp (ref "C317")
      (value "100nF")
      (footprint "SMD_0603_CAPC1608X95N")
      (fields
        (field (name "DB_PART_NUMBER") "CAP000027236")
        (field (name "DB_VALUE") "100nF")
        (field (name "DB_TOLERANCE") "20%")
        (field (name "DB_VOLTAGE") "16V")
        (field (name "DB_MANUFACTURER_PART") "KEMET    C0603C104M4RAC")
        (field (name "DB_APPROVED_BY") "ISHIDDEN=T")
      )
      (libsource (lib "Database_Libs1") (part "C"))
    )
    (comp (ref "C318")
      (value "100nF")
      (footprint "SMD_0603_CAPC1608X95N")
      (fields
        (field (name "DB_PART_NUMBER") "CAP000027236")
        (field (name "DB_VALUE") "100nF")
        (field (name "DB_TOLERANCE") "20%")
        (field (name "DB_VOLTAGE") "16V")
        (field (name "DB_MANUFACTURER_PART") "KEMET    C0603C104M4RAC")
        (field (name "DB_APPROVED_BY") "ISHIDDEN=T")
      )
      (libsource (lib "Database_Libs1") (part "C"))
    )
    (comp (ref "C319")
      (value "100nF")
      (footprint "SMD_0603_CAPC1608X95N")
      (fields
        (field (name "DB_PART_NUMBER") "CAP000027236")
        (field (name "DB_VALUE") "100nF")
        (field (name "DB_TOLERANCE") "20%")
        (field (name "DB_VOLTAGE") "16V")
        (field (name "DB_MANUFACTURER_PART") "KEMET    C0603C104M4RAC")
        (field (name "DB_APPROVED_BY") "ISHIDDEN=T")
      )
      (libsource (lib "Database_Libs1") (part "C"))
    )
    (comp (ref "C322")
      (value "470nF")
      (footprint "SMD_0603_CAPC1608X95N")
      (fields
        (field (name "DB_PART_NUMBER") "CAP000028169")
        (field (name "DB_VALUE") "470nF")
        (field (name "DB_TOLERANCE") "5%")
        (field (name "DB_VOLTAGE") "16V")
        (field (name "DB_MANUFACTURER_PART") "KEMET    C0603C474J4RAC")
        (field (name "DB_APPROVED_BY") "ISHIDDEN=T")
      )
      (libsource (lib "Database_Libs1") (part "C"))
    )
    (comp (ref "C492")
      (value "22uF")
      (footprint "SMD_0805_CAPC2012X145N")
      (fields
        (field (name "DB_PART_NUMBER") "CAP000043686")
        (field (name "DB_VALUE") "22uF")
        (field (name "DB_TOLERANCE") "20%")
        (field (name "DB_VOLTAGE") "6.3V")
        (field (name "DB_MANUFACTURER_PART") "KEMET    C0805C226M9PAC")
        (field (name "DB_APPROVED_BY") "ISHIDDEN=T")
      )
      (libsource (lib "Database_Libs1") (part "C"))
    )
    (comp (ref "C493")
      (value "22uF")
      (footprint "SMD_0805_CAPC2012X145N")
      (fields
        (field (name "DB_PART_NUMBER") "CAP000043686")
        (field (name "DB_VALUE") "22uF")
        (field (name "DB_TOLERANCE") "20%")
        (field (name "DB_VOLTAGE") "6.3V")
        (field (name "DB_MANUFACTURER_PART") "KEMET    C0805C226M9PAC")
        (field (name "DB_APPROVED_BY") "ISHIDDEN=T")
      )
      (libsource (lib "Database_Libs1") (part "C"))
    )
    (comp (ref "C494")
      (value "22uF")
      (footprint "SMD_0805_CAPC2012X145N")
      (fields
        (field (name "DB_PART_NUMBER") "CAP000043686")
        (field (name "DB_VALUE") "22uF")
        (field (name "DB_TOLERANCE") "20%")
        (field (name "DB_VOLTAGE") "6.3V")
        (field (name "DB_MANUFACTURER_PART") "KEMET    C0805C226M9PAC")
        (field (name "DB_APPROVED_BY") "ISHIDDEN=T")
      )
      (libsource (lib "Database_Libs1") (part "C"))
    )
    (comp (ref "C495")
      (value "22uF")
      (footprint "SMD_0805_CAPC2012X145N")
      (fields
        (field (name "DB_PART_NUMBER") "CAP000043686")
        (field (name "DB_VALUE") "22uF")
        (field (name "DB_TOLERANCE") "20%")
        (field (name "DB_VOLTAGE") "6.3V")
        (field (name "DB_MANUFACTURER_PART") "KEMET    C0805C226M9PAC")
        (field (name "DB_APPROVED_BY") "ISHIDDEN=T")
      )
      (libsource (lib "Database_Libs1") (part "C"))
    )
    (comp (ref "C496")
      (value "22uF")
      (footprint "SMD_0805_CAPC2012X145N")
      (fields
        (field (name "DB_PART_NUMBER") "CAP000043686")
        (field (name "DB_VALUE") "22uF")
        (field (name "DB_TOLERANCE") "20%")
        (field (name "DB_VOLTAGE") "6.3V")
        (field (name "DB_MANUFACTURER_PART") "KEMET    C0805C226M9PAC")
        (field (name "DB_APPROVED_BY") "ISHIDDEN=T")
      )
      (libsource (lib "Database_Libs1") (part "C"))
    )
    (comp (ref "C497")
      (value "22uF")
      (footprint "SMD_0805_CAPC2012X145N")
      (fields
        (field (name "DB_PART_NUMBER") "CAP000043686")
        (field (name "DB_VALUE") "22uF")
        (field (name "DB_TOLERANCE") "20%")
        (field (name "DB_VOLTAGE") "6.3V")
        (field (name "DB_MANUFACTURER_PART") "KEMET    C0805C226M9PAC")
        (field (name "DB_APPROVED_BY") "ISHIDDEN=T")
      )
      (libsource (lib "Database_Libs1") (part "C"))
    )
    (comp (ref "C498")
      (value "22uF")
      (footprint "SMD_0805_CAPC2012X145N")
      (fields
        (field (name "DB_PART_NUMBER") "CAP000043686")
        (field (name "DB_VALUE") "22uF")
        (field (name "DB_TOLERANCE") "20%")
        (field (name "DB_VOLTAGE") "6.3V")
        (field (name "DB_MANUFACTURER_PART") "KEMET    C0805C226M9PAC")
        (field (name "DB_APPROVED_BY") "ISHIDDEN=T")
      )
      (libsource (lib "Database_Libs1") (part "C"))
    )
    (comp (ref "C499")
      (value "22uF")
      (footprint "SMD_0805_CAPC2012X145N")
      (fields
        (field (name "DB_PART_NUMBER") "CAP000043686")
        (field (name "DB_VALUE") "22uF")
        (field (name "DB_TOLERANCE") "20%")
        (field (name "DB_VOLTAGE") "6.3V")
        (field (name "DB_MANUFACTURER_PART") "KEMET    C0805C226M9PAC")
        (field (name "DB_APPROVED_BY") "ISHIDDEN=T")
      )
      (libsource (lib "Database_Libs1") (part "C"))
    )
    (comp (ref "C500")
      (value "22uF")
      (footprint "SMD_0805_CAPC2012X145N")
      (fields
        (field (name "DB_PART_NUMBER") "CAP000043686")
        (field (name "DB_VALUE") "22uF")
        (field (name "DB_TOLERANCE") "20%")
        (field (name "DB_VOLTAGE") "6.3V")
        (field (name "DB_MANUFACTURER_PART") "KEMET    C0805C226M9PAC")
        (field (name "DB_APPROVED_BY") "ISHIDDEN=T")
      )
      (libsource (lib "Database_Libs1") (part "C"))
    )
    (comp (ref "C501")
      (value "22uF")
      (footprint "SMD_0805_CAPC2012X145N")
      (fields
        (field (name "DB_PART_NUMBER") "CAP000043686")
        (field (name "DB_VALUE") "22uF")
        (field (name "DB_TOLERANCE") "20%")
        (field (name "DB_VOLTAGE") "6.3V")
        (field (name "DB_MANUFACTURER_PART") "KEMET    C0805C226M9PAC")
        (field (name "DB_APPROVED_BY") "ISHIDDEN=T")
      )
      (libsource (lib "Database_Libs1") (part "C"))
    )
    (comp (ref "C502")
      (value "22uF")
      (footprint "SMD_0805_CAPC2012X145N")
      (fields
        (field (name "DB_PART_NUMBER") "CAP000043686")
        (field (name "DB_VALUE") "22uF")
        (field (name "DB_TOLERANCE") "20%")
        (field (name "DB_VOLTAGE") "6.3V")
        (field (name "DB_MANUFACTURER_PART") "KEMET    C0805C226M9PAC")
        (field (name "DB_APPROVED_BY") "ISHIDDEN=T")
      )
      (libsource (lib "Database_Libs1") (part "C"))
    )
    (comp (ref "C503")
      (value "22uF")
      (footprint "SMD_0805_CAPC2012X145N")
      (fields
        (field (name "DB_PART_NUMBER") "CAP000043686")
        (field (name "DB_VALUE") "22uF")
        (field (name "DB_TOLERANCE") "20%")
        (field (name "DB_VOLTAGE") "6.3V")
        (field (name "DB_MANUFACTURER_PART") "KEMET    C0805C226M9PAC")
        (field (name "DB_APPROVED_BY") "ISHIDDEN=T")
      )
      (libsource (lib "Database_Libs1") (part "C"))
    )
    (comp (ref "C504")
      (value "22uF")
      (footprint "SMD_0805_CAPC2012X145N")
      (fields
        (field (name "DB_PART_NUMBER") "CAP000043686")
        (field (name "DB_VALUE") "22uF")
        (field (name "DB_TOLERANCE") "20%")
        (field (name "DB_VOLTAGE") "6.3V")
        (field (name "DB_MANUFACTURER_PART") "KEMET    C0805C226M9PAC")
        (field (name "DB_APPROVED_BY") "ISHIDDEN=T")
      )
      (libsource (lib "Database_Libs1") (part "C"))
    )
    (comp (ref "C505")
      (value "22uF")
      (footprint "SMD_0805_CAPC2012X145N")
      (fields
        (field (name "DB_PART_NUMBER") "CAP000043686")
        (field (name "DB_VALUE") "22uF")
        (field (name "DB_TOLERANCE") "20%")
        (field (name "DB_VOLTAGE") "6.3V")
        (field (name "DB_MANUFACTURER_PART") "KEMET    C0805C226M9PAC")
        (field (name "DB_APPROVED_BY") "ISHIDDEN=T")
      )
      (libsource (lib "Database_Libs1") (part "C"))
    )
    (comp (ref "C506")
      (value "22uF")
      (footprint "SMD_0805_CAPC2012X145N")
      (fields
        (field (name "DB_PART_NUMBER") "CAP000043686")
        (field (name "DB_VALUE") "22uF")
        (field (name "DB_TOLERANCE") "20%")
        (field (name "DB_VOLTAGE") "6.3V")
        (field (name "DB_MANUFACTURER_PART") "KEMET    C0805C226M9PAC")
        (field (name "DB_APPROVED_BY") "ISHIDDEN=T")
      )
      (libsource (lib "Database_Libs1") (part "C"))
    )
    (comp (ref "C507")
      (value "22uF")
      (footprint "SMD_0805_CAPC2012X145N")
      (fields
        (field (name "DB_PART_NUMBER") "CAP000043686")
        (field (name "DB_VALUE") "22uF")
        (field (name "DB_TOLERANCE") "20%")
        (field (name "DB_VOLTAGE") "6.3V")
        (field (name "DB_MANUFACTURER_PART") "KEMET    C0805C226M9PAC")
        (field (name "DB_APPROVED_BY") "ISHIDDEN=T")
      )
      (libsource (lib "Database_Libs1") (part "C"))
    )
    (comp (ref "C508")
      (value "22uF")
      (footprint "SMD_0805_CAPC2012X145N")
      (fields
        (field (name "DB_PART_NUMBER") "CAP000043686")
        (field (name "DB_VALUE") "22uF")
        (field (name "DB_TOLERANCE") "20%")
        (field (name "DB_VOLTAGE") "6.3V")
        (field (name "DB_MANUFACTURER_PART") "KEMET    C0805C226M9PAC")
        (field (name "DB_APPROVED_BY") "ISHIDDEN=T")
      )
      (libsource (lib "Database_Libs1") (part "C"))
    )
    (comp (ref "C509")
      (value "22uF")
      (footprint "SMD_0805_CAPC2012X145N")
      (fields
        (field (name "DB_PART_NUMBER") "CAP000043686")
        (field (name "DB_VALUE") "22uF")
        (field (name "DB_TOLERANCE") "20%")
        (field (name "DB_VOLTAGE") "6.3V")
        (field (name "DB_MANUFACTURER_PART") "KEMET    C0805C226M9PAC")
        (field (name "DB_APPROVED_BY") "ISHIDDEN=T")
      )
      (libsource (lib "Database_Libs1") (part "C"))
    )
    (comp (ref "C510")
      (value "22uF")
      (footprint "SMD_0805_CAPC2012X145N")
      (fields
        (field (name "DB_PART_NUMBER") "CAP000043686")
        (field (name "DB_VALUE") "22uF")
        (field (name "DB_TOLERANCE") "20%")
        (field (name "DB_VOLTAGE") "6.3V")
        (field (name "DB_MANUFACTURER_PART") "KEMET    C0805C226M9PAC")
        (field (name "DB_APPROVED_BY") "ISHIDDEN=T")
      )
      (libsource (lib "Database_Libs1") (part "C"))
    )
    (comp (ref "C511")
      (value "22uF")
      (footprint "SMD_0805_CAPC2012X145N")
      (fields
        (field (name "DB_PART_NUMBER") "CAP000043686")
        (field (name "DB_VALUE") "22uF")
        (field (name "DB_TOLERANCE") "20%")
        (field (name "DB_VOLTAGE") "6.3V")
        (field (name "DB_MANUFACTURER_PART") "KEMET    C0805C226M9PAC")
        (field (name "DB_APPROVED_BY") "ISHIDDEN=T")
      )
      (libsource (lib "Database_Libs1") (part "C"))
    )
    (comp (ref "C512")
      (value "22uF")
      (footprint "SMD_0805_CAPC2012X145N")
      (fields
        (field (name "DB_PART_NUMBER") "CAP000043686")
        (field (name "DB_VALUE") "22uF")
        (field (name "DB_TOLERANCE") "20%")
        (field (name "DB_VOLTAGE") "6.3V")
        (field (name "DB_MANUFACTURER_PART") "KEMET    C0805C226M9PAC")
        (field (name "DB_APPROVED_BY") "ISHIDDEN=T")
      )
      (libsource (lib "Database_Libs1") (part "C"))
    )
    (comp (ref "C513")
      (value "22uF")
      (footprint "SMD_0805_CAPC2012X145N")
      (fields
        (field (name "DB_PART_NUMBER") "CAP000043686")
        (field (name "DB_VALUE") "22uF")
        (field (name "DB_TOLERANCE") "20%")
        (field (name "DB_VOLTAGE") "6.3V")
        (field (name "DB_MANUFACTURER_PART") "KEMET    C0805C226M9PAC")
        (field (name "DB_APPROVED_BY") "ISHIDDEN=T")
      )
      (libsource (lib "Database_Libs1") (part "C"))
    )
    (comp (ref "C514")
      (value "22uF")
      (footprint "SMD_0805_CAPC2012X145N")
      (fields
        (field (name "DB_PART_NUMBER") "CAP000043686")
        (field (name "DB_VALUE") "22uF")
        (field (name "DB_TOLERANCE") "20%")
        (field (name "DB_VOLTAGE") "6.3V")
        (field (name "DB_MANUFACTURER_PART") "KEMET    C0805C226M9PAC")
        (field (name "DB_APPROVED_BY") "ISHIDDEN=T")
      )
      (libsource (lib "Database_Libs1") (part "C"))
    )
    (comp (ref "C515")
      (value "22uF")
      (footprint "SMD_0805_CAPC2012X145N")
      (fields
        (field (name "DB_PART_NUMBER") "CAP000043686")
        (field (name "DB_VALUE") "22uF")
        (field (name "DB_TOLERANCE") "20%")
        (field (name "DB_VOLTAGE") "6.3V")
        (field (name "DB_MANUFACTURER_PART") "KEMET    C0805C226M9PAC")
        (field (name "DB_APPROVED_BY") "ISHIDDEN=T")
      )
      (libsource (lib "Database_Libs1") (part "C"))
    )
    (comp (ref "C516")
      (value "22uF")
      (footprint "SMD_0805_CAPC2012X145N")
      (fields
        (field (name "DB_PART_NUMBER") "CAP000043686")
        (field (name "DB_VALUE") "22uF")
        (field (name "DB_TOLERANCE") "20%")
        (field (name "DB_VOLTAGE") "6.3V")
        (field (name "DB_MANUFACTURER_PART") "KEMET    C0805C226M9PAC")
        (field (name "DB_APPROVED_BY") "ISHIDDEN=T")
      )
      (libsource (lib "Database_Libs1") (part "C"))
    )
    (comp (ref "C517")
      (value "22uF")
      (footprint "SMD_0805_CAPC2012X145N")
      (fields
        (field (name "DB_PART_NUMBER") "CAP000043686")
        (field (name "DB_VALUE") "22uF")
        (field (name "DB_TOLERANCE") "20%")
        (field (name "DB_VOLTAGE") "6.3V")
        (field (name "DB_MANUFACTURER_PART") "KEMET    C0805C226M9PAC")
        (field (name "DB_APPROVED_BY") "ISHIDDEN=T")
      )
      (libsource (lib "Database_Libs1") (part "C"))
    )
    (comp (ref "C518")
      (value "22uF")
      (footprint "SMD_0805_CAPC2012X145N")
      (fields
        (field (name "DB_PART_NUMBER") "CAP000043686")
        (field (name "DB_VALUE") "22uF")
        (field (name "DB_TOLERANCE") "20%")
        (field (name "DB_VOLTAGE") "6.3V")
        (field (name "DB_MANUFACTURER_PART") "KEMET    C0805C226M9PAC")
        (field (name "DB_APPROVED_BY") "ISHIDDEN=T")
      )
      (libsource (lib "Database_Libs1") (part "C"))
    )
    (comp (ref "C519")
      (value "22uF")
      (footprint "SMD_0805_CAPC2012X145N")
      (fields
        (field (name "DB_PART_NUMBER") "CAP000043686")
        (field (name "DB_VALUE") "22uF")
        (field (name "DB_TOLERANCE") "20%")
        (field (name "DB_VOLTAGE") "6.3V")
        (field (name "DB_MANUFACTURER_PART") "KEMET    C0805C226M9PAC")
        (field (name "DB_APPROVED_BY") "ISHIDDEN=T")
      )
      (libsource (lib "Database_Libs1") (part "C"))
    )
    (comp (ref "C520")
      (value "22uF")
      (footprint "SMD_0805_CAPC2012X145N")
      (fields
        (field (name "DB_PART_NUMBER") "CAP000043686")
        (field (name "DB_VALUE") "22uF")
        (field (name "DB_TOLERANCE") "20%")
        (field (name "DB_VOLTAGE") "6.3V")
        (field (name "DB_MANUFACTURER_PART") "KEMET    C0805C226M9PAC")
        (field (name "DB_APPROVED_BY") "ISHIDDEN=T")
      )
      (libsource (lib "Database_Libs1") (part "C"))
    )
    (comp (ref "C521")
      (value "22uF")
      (footprint "SMD_0805_CAPC2012X145N")
      (fields
        (field (name "DB_PART_NUMBER") "CAP000043686")
        (field (name "DB_VALUE") "22uF")
        (field (name "DB_TOLERANCE") "20%")
        (field (name "DB_VOLTAGE") "6.3V")
        (field (name "DB_MANUFACTURER_PART") "KEMET    C0805C226M9PAC")
        (field (name "DB_APPROVED_BY") "ISHIDDEN=T")
      )
      (libsource (lib "Database_Libs1") (part "C"))
    )
    (comp (ref "C522")
      (value "22uF")
      (footprint "SMD_0805_CAPC2012X145N")
      (fields
        (field (name "DB_PART_NUMBER") "CAP000043686")
        (field (name "DB_VALUE") "22uF")
        (field (name "DB_TOLERANCE") "20%")
        (field (name "DB_VOLTAGE") "6.3V")
        (field (name "DB_MANUFACTURER_PART") "KEMET    C0805C226M9PAC")
        (field (name "DB_APPROVED_BY") "ISHIDDEN=T")
      )
      (libsource (lib "Database_Libs1") (part "C"))
    )
    (comp (ref "C523")
      (value "22uF")
      (footprint "SMD_0805_CAPC2012X145N")
      (fields
        (field (name "DB_PART_NUMBER") "CAP000043686")
        (field (name "DB_VALUE") "22uF")
        (field (name "DB_TOLERANCE") "20%")
        (field (name "DB_VOLTAGE") "6.3V")
        (field (name "DB_MANUFACTURER_PART") "KEMET    C0805C226M9PAC")
        (field (name "DB_APPROVED_BY") "ISHIDDEN=T")
      )
      (libsource (lib "Database_Libs1") (part "C"))
    )
    (comp (ref "C524")
      (value "22uF")
      (footprint "SMD_0805_CAPC2012X145N")
      (fields
        (field (name "DB_PART_NUMBER") "CAP000043686")
        (field (name "DB_VALUE") "22uF")
        (field (name "DB_TOLERANCE") "20%")
        (field (name "DB_VOLTAGE") "6.3V")
        (field (name "DB_MANUFACTURER_PART") "KEMET    C0805C226M9PAC")
        (field (name "DB_APPROVED_BY") "ISHIDDEN=T")
      )
      (libsource (lib "Database_Libs1") (part "C"))
    )
    (comp (ref "C525")
      (value "22uF")
      (footprint "SMD_0805_CAPC2012X145N")
      (fields
        (field (name "DB_PART_NUMBER") "CAP000043686")
        (field (name "DB_VALUE") "22uF")
        (field (name "DB_TOLERANCE") "20%")
        (field (name "DB_VOLTAGE") "6.3V")
        (field (name "DB_MANUFACTURER_PART") "KEMET    C0805C226M9PAC")
        (field (name "DB_APPROVED_BY") "ISHIDDEN=T")
      )
      (libsource (lib "Database_Libs1") (part "C"))
    )
    (comp (ref "C526")
      (value "22uF")
      (footprint "SMD_0805_CAPC2012X145N")
      (fields
        (field (name "DB_PART_NUMBER") "CAP000043686")
        (field (name "DB_VALUE") "22uF")
        (field (name "DB_TOLERANCE") "20%")
        (field (name "DB_VOLTAGE") "6.3V")
        (field (name "DB_MANUFACTURER_PART") "KEMET    C0805C226M9PAC")
        (field (name "DB_APPROVED_BY") "ISHIDDEN=T")
      )
      (libsource (lib "Database_Libs1") (part "C"))
    )
    (comp (ref "C527")
      (value "22uF")
      (footprint "SMD_0805_CAPC2012X145N")
      (fields
        (field (name "DB_PART_NUMBER") "CAP000043686")
        (field (name "DB_VALUE") "22uF")
        (field (name "DB_TOLERANCE") "20%")
        (field (name "DB_VOLTAGE") "6.3V")
        (field (name "DB_MANUFACTURER_PART") "KEMET    C0805C226M9PAC")
        (field (name "DB_APPROVED_BY") "ISHIDDEN=T")
      )
      (libsource (lib "Database_Libs1") (part "C"))
    )
    (comp (ref "C528")
      (value "22uF")
      (footprint "SMD_0805_CAPC2012X145N")
      (fields
        (field (name "DB_PART_NUMBER") "CAP000043686")
        (field (name "DB_VALUE") "22uF")
        (field (name "DB_TOLERANCE") "20%")
        (field (name "DB_VOLTAGE") "6.3V")
        (field (name "DB_MANUFACTURER_PART") "KEMET    C0805C226M9PAC")
        (field (name "DB_APPROVED_BY") "ISHIDDEN=T")
      )
      (libsource (lib "Database_Libs1") (part "C"))
    )
    (comp (ref "C529")
      (value "22uF")
      (footprint "SMD_0805_CAPC2012X145N")
      (fields
        (field (name "DB_PART_NUMBER") "CAP000043686")
        (field (name "DB_VALUE") "22uF")
        (field (name "DB_TOLERANCE") "20%")
        (field (name "DB_VOLTAGE") "6.3V")
        (field (name "DB_MANUFACTURER_PART") "KEMET    C0805C226M9PAC")
        (field (name "DB_APPROVED_BY") "ISHIDDEN=T")
      )
      (libsource (lib "Database_Libs1") (part "C"))
    )
    (comp (ref "C530")
      (value "22uF")
      (footprint "SMD_0805_CAPC2012X145N")
      (fields
        (field (name "DB_PART_NUMBER") "CAP000043686")
        (field (name "DB_VALUE") "22uF")
        (field (name "DB_TOLERANCE") "20%")
        (field (name "DB_VOLTAGE") "6.3V")
        (field (name "DB_MANUFACTURER_PART") "KEMET    C0805C226M9PAC")
        (field (name "DB_APPROVED_BY") "ISHIDDEN=T")
      )
      (libsource (lib "Database_Libs1") (part "C"))
    )
    (comp (ref "C531")
      (value "22uF")
      (footprint "SMD_0805_CAPC2012X145N")
      (fields
        (field (name "DB_PART_NUMBER") "CAP000043686")
        (field (name "DB_VALUE") "22uF")
        (field (name "DB_TOLERANCE") "20%")
        (field (name "DB_VOLTAGE") "6.3V")
        (field (name "DB_MANUFACTURER_PART") "KEMET    C0805C226M9PAC")
        (field (name "DB_APPROVED_BY") "ISHIDDEN=T")
      )
      (libsource (lib "Database_Libs1") (part "C"))
    )
    (comp (ref "C532")
      (value "22uF")
      (footprint "SMD_0805_CAPC2012X145N")
      (fields
        (field (name "DB_PART_NUMBER") "CAP000043686")
        (field (name "DB_VALUE") "22uF")
        (field (name "DB_TOLERANCE") "20%")
        (field (name "DB_VOLTAGE") "6.3V")
        (field (name "DB_MANUFACTURER_PART") "KEMET    C0805C226M9PAC")
        (field (name "DB_APPROVED_BY") "ISHIDDEN=T")
      )
      (libsource (lib "Database_Libs1") (part "C"))
    )
    (comp (ref "C533")
      (value "22uF")
      (footprint "SMD_0805_CAPC2012X145N")
      (fields
        (field (name "DB_PART_NUMBER") "CAP000043686")
        (field (name "DB_VALUE") "22uF")
        (field (name "DB_TOLERANCE") "20%")
        (field (name "DB_VOLTAGE") "6.3V")
        (field (name "DB_MANUFACTURER_PART") "KEMET    C0805C226M9PAC")
        (field (name "DB_APPROVED_BY") "ISHIDDEN=T")
      )
      (libsource (lib "Database_Libs1") (part "C"))
    )
    (comp (ref "C534")
      (value "22uF")
      (footprint "SMD_0805_CAPC2012X145N")
      (fields
        (field (name "DB_PART_NUMBER") "CAP000043686")
        (field (name "DB_VALUE") "22uF")
        (field (name "DB_TOLERANCE") "20%")
        (field (name "DB_VOLTAGE") "6.3V")
        (field (name "DB_MANUFACTURER_PART") "KEMET    C0805C226M9PAC")
        (field (name "DB_APPROVED_BY") "ISHIDDEN=T")
      )
      (libsource (lib "Database_Libs1") (part "C"))
    )
    (comp (ref "C535")
      (value "22uF")
      (footprint "SMD_0805_CAPC2012X145N")
      (fields
        (field (name "DB_PART_NUMBER") "CAP000043686")
        (field (name "DB_VALUE") "22uF")
        (field (name "DB_TOLERANCE") "20%")
        (field (name "DB_VOLTAGE") "6.3V")
        (field (name "DB_MANUFACTURER_PART") "KEMET    C0805C226M9PAC")
        (field (name "DB_APPROVED_BY") "ISHIDDEN=T")
      )
      (libsource (lib "Database_Libs1") (part "C"))
    )
    (comp (ref "C536")
      (value "22uF")
      (footprint "SMD_0805_CAPC2012X145N")
      (fields
        (field (name "DB_PART_NUMBER") "CAP000043686")
        (field (name "DB_VALUE") "22uF")
        (field (name "DB_TOLERANCE") "20%")
        (field (name "DB_VOLTAGE") "6.3V")
        (field (name "DB_MANUFACTURER_PART") "KEMET    C0805C226M9PAC")
        (field (name "DB_APPROVED_BY") "ISHIDDEN=T")
      )
      (libsource (lib "Database_Libs1") (part "C"))
    )
    (comp (ref "C537")
      (value "22uF")
      (footprint "SMD_0805_CAPC2012X145N")
      (fields
        (field (name "DB_PART_NUMBER") "CAP000043686")
        (field (name "DB_VALUE") "22uF")
        (field (name "DB_TOLERANCE") "20%")
        (field (name "DB_VOLTAGE") "6.3V")
        (field (name "DB_MANUFACTURER_PART") "KEMET    C0805C226M9PAC")
        (field (name "DB_APPROVED_BY") "ISHIDDEN=T")
      )
      (libsource (lib "Database_Libs1") (part "C"))
    )
    (comp (ref "C538")
      (value "22uF")
      (footprint "SMD_0805_CAPC2012X145N")
      (fields
        (field (name "DB_PART_NUMBER") "CAP000043686")
        (field (name "DB_VALUE") "22uF")
        (field (name "DB_TOLERANCE") "20%")
        (field (name "DB_VOLTAGE") "6.3V")
        (field (name "DB_MANUFACTURER_PART") "KEMET    C0805C226M9PAC")
        (field (name "DB_APPROVED_BY") "ISHIDDEN=T")
      )
      (libsource (lib "Database_Libs1") (part "C"))
    )
    (comp (ref "C539")
      (value "22uF")
      (footprint "SMD_0805_CAPC2012X145N")
      (fields
        (field (name "DB_PART_NUMBER") "CAP000043686")
        (field (name "DB_VALUE") "22uF")
        (field (name "DB_TOLERANCE") "20%")
        (field (name "DB_VOLTAGE") "6.3V")
        (field (name "DB_MANUFACTURER_PART") "KEMET    C0805C226M9PAC")
        (field (name "DB_APPROVED_BY") "ISHIDDEN=T")
      )
      (libsource (lib "Database_Libs1") (part "C"))
    )
    (comp (ref "C540")
      (value "22uF")
      (footprint "SMD_0805_CAPC2012X145N")
      (fields
        (field (name "DB_PART_NUMBER") "CAP000043686")
        (field (name "DB_VALUE") "22uF")
        (field (name "DB_TOLERANCE") "20%")
        (field (name "DB_VOLTAGE") "6.3V")
        (field (name "DB_MANUFACTURER_PART") "KEMET    C0805C226M9PAC")
        (field (name "DB_APPROVED_BY") "ISHIDDEN=T")
      )
      (libsource (lib "Database_Libs1") (part "C"))
    )
    (comp (ref "C541")
      (value "22uF")
      (footprint "SMD_0805_CAPC2012X145N")
      (fields
        (field (name "DB_PART_NUMBER") "CAP000043686")
        (field (name "DB_VALUE") "22uF")
        (field (name "DB_TOLERANCE") "20%")
        (field (name "DB_VOLTAGE") "6.3V")
        (field (name "DB_MANUFACTURER_PART") "KEMET    C0805C226M9PAC")
        (field (name "DB_APPROVED_BY") "ISHIDDEN=T")
      )
      (libsource (lib "Database_Libs1") (part "C"))
    )
    (comp (ref "C542")
      (value "22uF")
      (footprint "SMD_0805_CAPC2012X145N")
      (fields
        (field (name "DB_PART_NUMBER") "CAP000043686")
        (field (name "DB_VALUE") "22uF")
        (field (name "DB_TOLERANCE") "20%")
        (field (name "DB_VOLTAGE") "6.3V")
        (field (name "DB_MANUFACTURER_PART") "KEMET    C0805C226M9PAC")
        (field (name "DB_APPROVED_BY") "ISHIDDEN=T")
      )
      (libsource (lib "Database_Libs1") (part "C"))
    )
    (comp (ref "C543")
      (value "22uF")
      (footprint "SMD_0805_CAPC2012X145N")
      (fields
        (field (name "DB_PART_NUMBER") "CAP000043686")
        (field (name "DB_VALUE") "22uF")
        (field (name "DB_TOLERANCE") "20%")
        (field (name "DB_VOLTAGE") "6.3V")
        (field (name "DB_MANUFACTURER_PART") "KEMET    C0805C226M9PAC")
        (field (name "DB_APPROVED_BY") "ISHIDDEN=T")
      )
      (libsource (lib "Database_Libs1") (part "C"))
    )
    (comp (ref "C544")
      (value "22uF")
      (footprint "SMD_0805_CAPC2012X145N")
      (fields
        (field (name "DB_PART_NUMBER") "CAP000043686")
        (field (name "DB_VALUE") "22uF")
        (field (name "DB_TOLERANCE") "20%")
        (field (name "DB_VOLTAGE") "6.3V")
        (field (name "DB_MANUFACTURER_PART") "KEMET    C0805C226M9PAC")
        (field (name "DB_APPROVED_BY") "ISHIDDEN=T")
      )
      (libsource (lib "Database_Libs1") (part "C"))
    )
    (comp (ref "C545")
      (value "22uF")
      (footprint "SMD_0805_CAPC2012X145N")
      (fields
        (field (name "DB_PART_NUMBER") "CAP000043686")
        (field (name "DB_VALUE") "22uF")
        (field (name "DB_TOLERANCE") "20%")
        (field (name "DB_VOLTAGE") "6.3V")
        (field (name "DB_MANUFACTURER_PART") "KEMET    C0805C226M9PAC")
        (field (name "DB_APPROVED_BY") "ISHIDDEN=T")
      )
      (libsource (lib "Database_Libs1") (part "C"))
    )
    (comp (ref "C546")
      (value "22uF")
      (footprint "SMD_0805_CAPC2012X145N")
      (fields
        (field (name "DB_PART_NUMBER") "CAP000043686")
        (field (name "DB_VALUE") "22uF")
        (field (name "DB_TOLERANCE") "20%")
        (field (name "DB_VOLTAGE") "6.3V")
        (field (name "DB_MANUFACTURER_PART") "KEMET    C0805C226M9PAC")
        (field (name "DB_APPROVED_BY") "ISHIDDEN=T")
      )
      (libsource (lib "Database_Libs1") (part "C"))
    )
    (comp (ref "C547")
      (value "22uF")
      (footprint "SMD_0805_CAPC2012X145N")
      (fields
        (field (name "DB_PART_NUMBER") "CAP000043686")
        (field (name "DB_VALUE") "22uF")
        (field (name "DB_TOLERANCE") "20%")
        (field (name "DB_VOLTAGE") "6.3V")
        (field (name "DB_MANUFACTURER_PART") "KEMET    C0805C226M9PAC")
        (field (name "DB_APPROVED_BY") "ISHIDDEN=T")
      )
      (libsource (lib "Database_Libs1") (part "C"))
    )
    (comp (ref "C548")
      (value "22uF")
      (footprint "SMD_0805_CAPC2012X145N")
      (fields
        (field (name "DB_PART_NUMBER") "CAP000043686")
        (field (name "DB_VALUE") "22uF")
        (field (name "DB_TOLERANCE") "20%")
        (field (name "DB_VOLTAGE") "6.3V")
        (field (name "DB_MANUFACTURER_PART") "KEMET    C0805C226M9PAC")
        (field (name "DB_APPROVED_BY") "ISHIDDEN=T")
      )
      (libsource (lib "Database_Libs1") (part "C"))
    )
    (comp (ref "C549")
      (value "22uF")
      (footprint "SMD_0805_CAPC2012X145N")
      (fields
        (field (name "DB_PART_NUMBER") "CAP000043686")
        (field (name "DB_VALUE") "22uF")
        (field (name "DB_TOLERANCE") "20%")
        (field (name "DB_VOLTAGE") "6.3V")
        (field (name "DB_MANUFACTURER_PART") "KEMET    C0805C226M9PAC")
        (field (name "DB_APPROVED_BY") "ISHIDDEN=T")
      )
      (libsource (lib "Database_Libs1") (part "C"))
    )
    (comp (ref "C550")
      (value "22uF")
      (footprint "SMD_0805_CAPC2012X145N")
      (fields
        (field (name "DB_PART_NUMBER") "CAP000043686")
        (field (name "DB_VALUE") "22uF")
        (field (name "DB_TOLERANCE") "20%")
        (field (name "DB_VOLTAGE") "6.3V")
        (field (name "DB_MANUFACTURER_PART") "KEMET    C0805C226M9PAC")
        (field (name "DB_APPROVED_BY") "ISHIDDEN=T")
      )
      (libsource (lib "Database_Libs1") (part "C"))
    )
    (comp (ref "C551")
      (value "22uF")
      (footprint "SMD_0805_CAPC2012X145N")
      (fields
        (field (name "DB_PART_NUMBER") "CAP000043686")
        (field (name "DB_VALUE") "22uF")
        (field (name "DB_TOLERANCE") "20%")
        (field (name "DB_VOLTAGE") "6.3V")
        (field (name "DB_MANUFACTURER_PART") "KEMET    C0805C226M9PAC")
        (field (name "DB_APPROVED_BY") "ISHIDDEN=T")
      )
      (libsource (lib "Database_Libs1") (part "C"))
    )
    (comp (ref "C552")
      (value "22uF")
      (footprint "SMD_0805_CAPC2012X145N")
      (fields
        (field (name "DB_PART_NUMBER") "CAP000043686")
        (field (name "DB_VALUE") "22uF")
        (field (name "DB_TOLERANCE") "20%")
        (field (name "DB_VOLTAGE") "6.3V")
        (field (name "DB_MANUFACTURER_PART") "KEMET    C0805C226M9PAC")
        (field (name "DB_APPROVED_BY") "ISHIDDEN=T")
      )
      (libsource (lib "Database_Libs1") (part "C"))
    )
    (comp (ref "C553")
      (value "22uF")
      (footprint "SMD_0805_CAPC2012X145N")
      (fields
        (field (name "DB_PART_NUMBER") "CAP000043686")
        (field (name "DB_VALUE") "22uF")
        (field (name "DB_TOLERANCE") "20%")
        (field (name "DB_VOLTAGE") "6.3V")
        (field (name "DB_MANUFACTURER_PART") "KEMET    C0805C226M9PAC")
        (field (name "DB_APPROVED_BY") "ISHIDDEN=T")
      )
      (libsource (lib "Database_Libs1") (part "C"))
    )
    (comp (ref "C554")
      (value "22uF")
      (footprint "SMD_0805_CAPC2012X145N")
      (fields
        (field (name "DB_PART_NUMBER") "CAP000043686")
        (field (name "DB_VALUE") "22uF")
        (field (name "DB_TOLERANCE") "20%")
        (field (name "DB_VOLTAGE") "6.3V")
        (field (name "DB_MANUFACTURER_PART") "KEMET    C0805C226M9PAC")
        (field (name "DB_APPROVED_BY") "ISHIDDEN=T")
      )
      (libsource (lib "Database_Libs1") (part "C"))
    )
    (comp (ref "C555")
      (value "22uF")
      (footprint "SMD_0805_CAPC2012X145N")
      (fields
        (field (name "DB_PART_NUMBER") "CAP000043686")
        (field (name "DB_VALUE") "22uF")
        (field (name "DB_TOLERANCE") "20%")
        (field (name "DB_VOLTAGE") "6.3V")
        (field (name "DB_MANUFACTURER_PART") "KEMET    C0805C226M9PAC")
        (field (name "DB_APPROVED_BY") "ISHIDDEN=T")
      )
      (libsource (lib "Database_Libs1") (part "C"))
    )
    (comp (ref "C556")
      (value "22uF")
      (footprint "SMD_0805_CAPC2012X145N")
      (fields
        (field (name "DB_PART_NUMBER") "CAP000043686")
        (field (name "DB_VALUE") "22uF")
        (field (name "DB_TOLERANCE") "20%")
        (field (name "DB_VOLTAGE") "6.3V")
        (field (name "DB_MANUFACTURER_PART") "KEMET    C0805C226M9PAC")
        (field (name "DB_APPROVED_BY") "ISHIDDEN=T")
      )
      (libsource (lib "Database_Libs1") (part "C"))
    )
    (comp (ref "C557")
      (value "22uF")
      (footprint "SMD_0805_CAPC2012X145N")
      (fields
        (field (name "DB_PART_NUMBER") "CAP000043686")
        (field (name "DB_VALUE") "22uF")
        (field (name "DB_TOLERANCE") "20%")
        (field (name "DB_VOLTAGE") "6.3V")
        (field (name "DB_MANUFACTURER_PART") "KEMET    C0805C226M9PAC")
        (field (name "DB_APPROVED_BY") "ISHIDDEN=T")
      )
      (libsource (lib "Database_Libs1") (part "C"))
    )
    (comp (ref "C558")
      (value "22uF")
      (footprint "SMD_0805_CAPC2012X145N")
      (fields
        (field (name "DB_PART_NUMBER") "CAP000043686")
        (field (name "DB_VALUE") "22uF")
        (field (name "DB_TOLERANCE") "20%")
        (field (name "DB_VOLTAGE") "6.3V")
        (field (name "DB_MANUFACTURER_PART") "KEMET    C0805C226M9PAC")
        (field (name "DB_APPROVED_BY") "ISHIDDEN=T")
      )
      (libsource (lib "Database_Libs1") (part "C"))
    )
    (comp (ref "C559")
      (value "22uF")
      (footprint "SMD_0805_CAPC2012X145N")
      (fields
        (field (name "DB_PART_NUMBER") "CAP000043686")
        (field (name "DB_VALUE") "22uF")
        (field (name "DB_TOLERANCE") "20%")
        (field (name "DB_VOLTAGE") "6.3V")
        (field (name "DB_MANUFACTURER_PART") "KEMET    C0805C226M9PAC")
        (field (name "DB_APPROVED_BY") "ISHIDDEN=T")
      )
      (libsource (lib "Database_Libs1") (part "C"))
    )
    (comp (ref "C560")
      (value "22uF")
      (footprint "SMD_0805_CAPC2012X145N")
      (fields
        (field (name "DB_PART_NUMBER") "CAP000043686")
        (field (name "DB_VALUE") "22uF")
        (field (name "DB_TOLERANCE") "20%")
        (field (name "DB_VOLTAGE") "6.3V")
        (field (name "DB_MANUFACTURER_PART") "KEMET    C0805C226M9PAC")
        (field (name "DB_APPROVED_BY") "ISHIDDEN=T")
      )
      (libsource (lib "Database_Libs1") (part "C"))
    )
    (comp (ref "C561")
      (value "22uF")
      (footprint "SMD_0805_CAPC2012X145N")
      (fields
        (field (name "DB_PART_NUMBER") "CAP000043686")
        (field (name "DB_VALUE") "22uF")
        (field (name "DB_TOLERANCE") "20%")
        (field (name "DB_VOLTAGE") "6.3V")
        (field (name "DB_MANUFACTURER_PART") "KEMET    C0805C226M9PAC")
        (field (name "DB_APPROVED_BY") "ISHIDDEN=T")
      )
      (libsource (lib "Database_Libs1") (part "C"))
    )
    (comp (ref "C562")
      (value "22uF")
      (footprint "SMD_0805_CAPC2012X145N")
      (fields
        (field (name "DB_PART_NUMBER") "CAP000043686")
        (field (name "DB_VALUE") "22uF")
        (field (name "DB_TOLERANCE") "20%")
        (field (name "DB_VOLTAGE") "6.3V")
        (field (name "DB_MANUFACTURER_PART") "KEMET    C0805C226M9PAC")
        (field (name "DB_APPROVED_BY") "ISHIDDEN=T")
      )
      (libsource (lib "Database_Libs1") (part "C"))
    )
    (comp (ref "C563")
      (value "22uF")
      (footprint "SMD_0805_CAPC2012X145N")
      (fields
        (field (name "DB_PART_NUMBER") "CAP000043686")
        (field (name "DB_VALUE") "22uF")
        (field (name "DB_TOLERANCE") "20%")
        (field (name "DB_VOLTAGE") "6.3V")
        (field (name "DB_MANUFACTURER_PART") "KEMET    C0805C226M9PAC")
        (field (name "DB_APPROVED_BY") "ISHIDDEN=T")
      )
      (libsource (lib "Database_Libs1") (part "C"))
    )
    (comp (ref "C564")
      (value "22uF")
      (footprint "SMD_0805_CAPC2012X145N")
      (fields
        (field (name "DB_PART_NUMBER") "CAP000043686")
        (field (name "DB_VALUE") "22uF")
        (field (name "DB_TOLERANCE") "20%")
        (field (name "DB_VOLTAGE") "6.3V")
        (field (name "DB_MANUFACTURER_PART") "KEMET    C0805C226M9PAC")
        (field (name "DB_APPROVED_BY") "ISHIDDEN=T")
      )
      (libsource (lib "Database_Libs1") (part "C"))
    )
    (comp (ref "C565")
      (value "22uF")
      (footprint "SMD_0805_CAPC2012X145N")
      (fields
        (field (name "DB_PART_NUMBER") "CAP000043686")
        (field (name "DB_VALUE") "22uF")
        (field (name "DB_TOLERANCE") "20%")
        (field (name "DB_VOLTAGE") "6.3V")
        (field (name "DB_MANUFACTURER_PART") "KEMET    C0805C226M9PAC")
        (field (name "DB_APPROVED_BY") "ISHIDDEN=T")
      )
      (libsource (lib "Database_Libs1") (part "C"))
    )
    (comp (ref "C566")
      (value "22uF")
      (footprint "SMD_0805_CAPC2012X145N")
      (fields
        (field (name "DB_PART_NUMBER") "CAP000043686")
        (field (name "DB_VALUE") "22uF")
        (field (name "DB_TOLERANCE") "20%")
        (field (name "DB_VOLTAGE") "6.3V")
        (field (name "DB_MANUFACTURER_PART") "KEMET    C0805C226M9PAC")
        (field (name "DB_APPROVED_BY") "ISHIDDEN=T")
      )
      (libsource (lib "Database_Libs1") (part "C"))
    )
    (comp (ref "C567")
      (value "22uF")
      (footprint "SMD_0805_CAPC2012X145N")
      (fields
        (field (name "DB_PART_NUMBER") "CAP000043686")
        (field (name "DB_VALUE") "22uF")
        (field (name "DB_TOLERANCE") "20%")
        (field (name "DB_VOLTAGE") "6.3V")
        (field (name "DB_MANUFACTURER_PART") "KEMET    C0805C226M9PAC")
        (field (name "DB_APPROVED_BY") "ISHIDDEN=T")
      )
      (libsource (lib "Database_Libs1") (part "C"))
    )
    (comp (ref "C568")
      (value "22uF")
      (footprint "SMD_0805_CAPC2012X145N")
      (fields
        (field (name "DB_PART_NUMBER") "CAP000043686")
        (field (name "DB_VALUE") "22uF")
        (field (name "DB_TOLERANCE") "20%")
        (field (name "DB_VOLTAGE") "6.3V")
        (field (name "DB_MANUFACTURER_PART") "KEMET    C0805C226M9PAC")
        (field (name "DB_APPROVED_BY") "ISHIDDEN=T")
      )
      (libsource (lib "Database_Libs1") (part "C"))
    )
    (comp (ref "C569")
      (value "22uF")
      (footprint "SMD_0805_CAPC2012X145N")
      (fields
        (field (name "DB_PART_NUMBER") "CAP000043686")
        (field (name "DB_VALUE") "22uF")
        (field (name "DB_TOLERANCE") "20%")
        (field (name "DB_VOLTAGE") "6.3V")
        (field (name "DB_MANUFACTURER_PART") "KEMET    C0805C226M9PAC")
        (field (name "DB_APPROVED_BY") "ISHIDDEN=T")
      )
      (libsource (lib "Database_Libs1") (part "C"))
    )
    (comp (ref "C570")
      (value "22uF")
      (footprint "SMD_0805_CAPC2012X145N")
      (fields
        (field (name "DB_PART_NUMBER") "CAP000043686")
        (field (name "DB_VALUE") "22uF")
        (field (name "DB_TOLERANCE") "20%")
        (field (name "DB_VOLTAGE") "6.3V")
        (field (name "DB_MANUFACTURER_PART") "KEMET    C0805C226M9PAC")
        (field (name "DB_APPROVED_BY") "ISHIDDEN=T")
      )
      (libsource (lib "Database_Libs1") (part "C"))
    )
    (comp (ref "C571")
      (value "22uF")
      (footprint "SMD_0805_CAPC2012X145N")
      (fields
        (field (name "DB_PART_NUMBER") "CAP000043686")
        (field (name "DB_VALUE") "22uF")
        (field (name "DB_TOLERANCE") "20%")
        (field (name "DB_VOLTAGE") "6.3V")
        (field (name "DB_MANUFACTURER_PART") "KEMET    C0805C226M9PAC")
        (field (name "DB_APPROVED_BY") "ISHIDDEN=T")
      )
      (libsource (lib "Database_Libs1") (part "C"))
    )
    (comp (ref "C572")
      (value "22uF")
      (footprint "SMD_0805_CAPC2012X145N")
      (fields
        (field (name "DB_PART_NUMBER") "CAP000043686")
        (field (name "DB_VALUE") "22uF")
        (field (name "DB_TOLERANCE") "20%")
        (field (name "DB_VOLTAGE") "6.3V")
        (field (name "DB_MANUFACTURER_PART") "KEMET    C0805C226M9PAC")
        (field (name "DB_APPROVED_BY") "ISHIDDEN=T")
      )
      (libsource (lib "Database_Libs1") (part "C"))
    )
    (comp (ref "C573")
      (value "22uF")
      (footprint "SMD_0805_CAPC2012X145N")
      (fields
        (field (name "DB_PART_NUMBER") "CAP000043686")
        (field (name "DB_VALUE") "22uF")
        (field (name "DB_TOLERANCE") "20%")
        (field (name "DB_VOLTAGE") "6.3V")
        (field (name "DB_MANUFACTURER_PART") "KEMET    C0805C226M9PAC")
        (field (name "DB_APPROVED_BY") "ISHIDDEN=T")
      )
      (libsource (lib "Database_Libs1") (part "C"))
    )
    (comp (ref "C574")
      (value "22uF")
      (footprint "SMD_0805_CAPC2012X145N")
      (fields
        (field (name "DB_PART_NUMBER") "CAP000043686")
        (field (name "DB_VALUE") "22uF")
        (field (name "DB_TOLERANCE") "20%")
        (field (name "DB_VOLTAGE") "6.3V")
        (field (name "DB_MANUFACTURER_PART") "KEMET    C0805C226M9PAC")
        (field (name "DB_APPROVED_BY") "ISHIDDEN=T")
      )
      (libsource (lib "Database_Libs1") (part "C"))
    )
    (comp (ref "C575")
      (value "22uF")
      (footprint "SMD_0805_CAPC2012X145N")
      (fields
        (field (name "DB_PART_NUMBER") "CAP000043686")
        (field (name "DB_VALUE") "22uF")
        (field (name "DB_TOLERANCE") "20%")
        (field (name "DB_VOLTAGE") "6.3V")
        (field (name "DB_MANUFACTURER_PART") "KEMET    C0805C226M9PAC")
        (field (name "DB_APPROVED_BY") "ISHIDDEN=T")
      )
      (libsource (lib "Database_Libs1") (part "C"))
    )
    (comp (ref "C576")
      (value "22uF")
      (footprint "SMD_0805_CAPC2012X145N")
      (fields
        (field (name "DB_PART_NUMBER") "CAP000043686")
        (field (name "DB_VALUE") "22uF")
        (field (name "DB_TOLERANCE") "20%")
        (field (name "DB_VOLTAGE") "6.3V")
        (field (name "DB_MANUFACTURER_PART") "KEMET    C0805C226M9PAC")
        (field (name "DB_APPROVED_BY") "ISHIDDEN=T")
      )
      (libsource (lib "Database_Libs1") (part "C"))
    )
    (comp (ref "C577")
      (value "22uF")
      (footprint "SMD_0805_CAPC2012X145N")
      (fields
        (field (name "DB_PART_NUMBER") "CAP000043686")
        (field (name "DB_VALUE") "22uF")
        (field (name "DB_TOLERANCE") "20%")
        (field (name "DB_VOLTAGE") "6.3V")
        (field (name "DB_MANUFACTURER_PART") "KEMET    C0805C226M9PAC")
        (field (name "DB_APPROVED_BY") "ISHIDDEN=T")
      )
      (libsource (lib "Database_Libs1") (part "C"))
    )
    (comp (ref "C578")
      (value "22uF")
      (footprint "SMD_0805_CAPC2012X145N")
      (fields
        (field (name "DB_PART_NUMBER") "CAP000043686")
        (field (name "DB_VALUE") "22uF")
        (field (name "DB_TOLERANCE") "20%")
        (field (name "DB_VOLTAGE") "6.3V")
        (field (name "DB_MANUFACTURER_PART") "KEMET    C0805C226M9PAC")
        (field (name "DB_APPROVED_BY") "ISHIDDEN=T")
      )
      (libsource (lib "Database_Libs1") (part "C"))
    )
    (comp (ref "C579")
      (value "22uF")
      (footprint "SMD_0805_CAPC2012X145N")
      (fields
        (field (name "DB_PART_NUMBER") "CAP000043686")
        (field (name "DB_VALUE") "22uF")
        (field (name "DB_TOLERANCE") "20%")
        (field (name "DB_VOLTAGE") "6.3V")
        (field (name "DB_MANUFACTURER_PART") "KEMET    C0805C226M9PAC")
        (field (name "DB_APPROVED_BY") "ISHIDDEN=T")
      )
      (libsource (lib "Database_Libs1") (part "C"))
    )
    (comp (ref "C580")
      (value "22uF")
      (footprint "SMD_0805_CAPC2012X145N")
      (fields
        (field (name "DB_PART_NUMBER") "CAP000043686")
        (field (name "DB_VALUE") "22uF")
        (field (name "DB_TOLERANCE") "20%")
        (field (name "DB_VOLTAGE") "6.3V")
        (field (name "DB_MANUFACTURER_PART") "KEMET    C0805C226M9PAC")
        (field (name "DB_APPROVED_BY") "ISHIDDEN=T")
      )
      (libsource (lib "Database_Libs1") (part "C"))
    )
    (comp (ref "C581")
      (value "22uF")
      (footprint "SMD_0805_CAPC2012X145N")
      (fields
        (field (name "DB_PART_NUMBER") "CAP000043686")
        (field (name "DB_VALUE") "22uF")
        (field (name "DB_TOLERANCE") "20%")
        (field (name "DB_VOLTAGE") "6.3V")
        (field (name "DB_MANUFACTURER_PART") "KEMET    C0805C226M9PAC")
        (field (name "DB_APPROVED_BY") "ISHIDDEN=T")
      )
      (libsource (lib "Database_Libs1") (part "C"))
    )
    (comp (ref "C582")
      (value "22uF")
      (footprint "SMD_0805_CAPC2012X145N")
      (fields
        (field (name "DB_PART_NUMBER") "CAP000043686")
        (field (name "DB_VALUE") "22uF")
        (field (name "DB_TOLERANCE") "20%")
        (field (name "DB_VOLTAGE") "6.3V")
        (field (name "DB_MANUFACTURER_PART") "KEMET    C0805C226M9PAC")
        (field (name "DB_APPROVED_BY") "ISHIDDEN=T")
      )
      (libsource (lib "Database_Libs1") (part "C"))
    )
    (comp (ref "C583")
      (value "22uF")
      (footprint "SMD_0805_CAPC2012X145N")
      (fields
        (field (name "DB_PART_NUMBER") "CAP000043686")
        (field (name "DB_VALUE") "22uF")
        (field (name "DB_TOLERANCE") "20%")
        (field (name "DB_VOLTAGE") "6.3V")
        (field (name "DB_MANUFACTURER_PART") "KEMET    C0805C226M9PAC")
        (field (name "DB_APPROVED_BY") "ISHIDDEN=T")
      )
      (libsource (lib "Database_Libs1") (part "C"))
    )
    (comp (ref "C584")
      (value "22uF")
      (footprint "SMD_0805_CAPC2012X145N")
      (fields
        (field (name "DB_PART_NUMBER") "CAP000043686")
        (field (name "DB_VALUE") "22uF")
        (field (name "DB_TOLERANCE") "20%")
        (field (name "DB_VOLTAGE") "6.3V")
        (field (name "DB_MANUFACTURER_PART") "KEMET    C0805C226M9PAC")
        (field (name "DB_APPROVED_BY") "ISHIDDEN=T")
      )
      (libsource (lib "Database_Libs1") (part "C"))
    )
    (comp (ref "C585")
      (value "22uF")
      (footprint "SMD_0805_CAPC2012X145N")
      (fields
        (field (name "DB_PART_NUMBER") "CAP000043686")
        (field (name "DB_VALUE") "22uF")
        (field (name "DB_TOLERANCE") "20%")
        (field (name "DB_VOLTAGE") "6.3V")
        (field (name "DB_MANUFACTURER_PART") "KEMET    C0805C226M9PAC")
        (field (name "DB_APPROVED_BY") "ISHIDDEN=T")
      )
      (libsource (lib "Database_Libs1") (part "C"))
    )
    (comp (ref "C586")
      (value "22uF")
      (footprint "SMD_0805_CAPC2012X145N")
      (fields
        (field (name "DB_PART_NUMBER") "CAP000043686")
        (field (name "DB_VALUE") "22uF")
        (field (name "DB_TOLERANCE") "20%")
        (field (name "DB_VOLTAGE") "6.3V")
        (field (name "DB_MANUFACTURER_PART") "KEMET    C0805C226M9PAC")
        (field (name "DB_APPROVED_BY") "ISHIDDEN=T")
      )
      (libsource (lib "Database_Libs1") (part "C"))
    )
    (comp (ref "C587")
      (value "22uF")
      (footprint "SMD_0805_CAPC2012X145N")
      (fields
        (field (name "DB_PART_NUMBER") "CAP000043686")
        (field (name "DB_VALUE") "22uF")
        (field (name "DB_TOLERANCE") "20%")
        (field (name "DB_VOLTAGE") "6.3V")
        (field (name "DB_MANUFACTURER_PART") "KEMET    C0805C226M9PAC")
        (field (name "DB_APPROVED_BY") "ISHIDDEN=T")
      )
      (libsource (lib "Database_Libs1") (part "C"))
    )
    (comp (ref "C588")
      (value "22uF")
      (footprint "SMD_0805_CAPC2012X145N")
      (fields
        (field (name "DB_PART_NUMBER") "CAP000043686")
        (field (name "DB_VALUE") "22uF")
        (field (name "DB_TOLERANCE") "20%")
        (field (name "DB_VOLTAGE") "6.3V")
        (field (name "DB_MANUFACTURER_PART") "KEMET    C0805C226M9PAC")
        (field (name "DB_APPROVED_BY") "ISHIDDEN=T")
      )
      (libsource (lib "Database_Libs1") (part "C"))
    )
    (comp (ref "C589")
      (value "22uF")
      (footprint "SMD_0805_CAPC2012X145N")
      (fields
        (field (name "DB_PART_NUMBER") "CAP000043686")
        (field (name "DB_VALUE") "22uF")
        (field (name "DB_TOLERANCE") "20%")
        (field (name "DB_VOLTAGE") "6.3V")
        (field (name "DB_MANUFACTURER_PART") "KEMET    C0805C226M9PAC")
        (field (name "DB_APPROVED_BY") "ISHIDDEN=T")
      )
      (libsource (lib "Database_Libs1") (part "C"))
    )
    (comp (ref "C590")
      (value "22uF")
      (footprint "SMD_0805_CAPC2012X145N")
      (fields
        (field (name "DB_PART_NUMBER") "CAP000043686")
        (field (name "DB_VALUE") "22uF")
        (field (name "DB_TOLERANCE") "20%")
        (field (name "DB_VOLTAGE") "6.3V")
        (field (name "DB_MANUFACTURER_PART") "KEMET    C0805C226M9PAC")
        (field (name "DB_APPROVED_BY") "ISHIDDEN=T")
      )
      (libsource (lib "Database_Libs1") (part "C"))
    )
    (comp (ref "C591")
      (value "22uF")
      (footprint "SMD_0805_CAPC2012X145N")
      (fields
        (field (name "DB_PART_NUMBER") "CAP000043686")
        (field (name "DB_VALUE") "22uF")
        (field (name "DB_TOLERANCE") "20%")
        (field (name "DB_VOLTAGE") "6.3V")
        (field (name "DB_MANUFACTURER_PART") "KEMET    C0805C226M9PAC")
        (field (name "DB_APPROVED_BY") "ISHIDDEN=T")
      )
      (libsource (lib "Database_Libs1") (part "C"))
    )
    (comp (ref "R3")
      (value "100R")
      (footprint "SMD_0603_RESC1608X55N")
      (fields
        (field (name "DB_PART_NUMBER") "RES000006398")
        (field (name "DB_VALUE") "100R")
        (field (name "DB_TOLERANCE") "5%")
        (field (name "DB_MANUFACTURER_PART") "YAGEO    RC0603JR-07100R")
        (field (name "ASSEMBLY") "N/A")
        (field (name "DB_APPROVED_BY") "ISHIDDEN=T")
      )
      (libsource (lib "Database_Libs1") (part "R"))
    )
    (comp (ref "R19")
      (value "100R")
      (footprint "SMD_0603_RESC1608X55N")
      (fields
        (field (name "DB_PART_NUMBER") "RES000006398")
        (field (name "DB_VALUE") "100R")
        (field (name "DB_TOLERANCE") "5%")
        (field (name "DB_MANUFACTURER_PART") "YAGEO    RC0603JR-07100R")
        (field (name "DB_APPROVED_BY") "ISHIDDEN=T")
      )
      (libsource (lib "Database_Libs1") (part "R"))
    )
    (comp (ref "TP3")
      (value "100_254")
      (footprint "SMD_TP_100-254")
      (fields
        (field (name "DB_PART_NUMBER") "TPO000000001")
        (field (name "DB_MANUFACTURER_PART") "ISHIDDEN=T")
        (field (name "DB_APPROVED_BY") "ISHIDDEN=T")
      )
      (libsource (lib "Database_Libs1") (part "TEST_POINT_1"))
    )
    (comp (ref "TP15")
      (value "100_254")
      (footprint "SMD_TP_100-254")
      (fields
        (field (name "DB_PART_NUMBER") "TPO000000001")
        (field (name "DB_MANUFACTURER_PART") "ISHIDDEN=T")
        (field (name "DB_APPROVED_BY") "ISHIDDEN=T")
      )
      (libsource (lib "Database_Libs1") (part "TEST_POINT_1"))
    )
    (comp (ref "TP16")
      (value "100_254")
      (footprint "SMD_TP_100-254")
      (fields
        (field (name "DB_PART_NUMBER") "TPO000000001")
        (field (name "DB_MANUFACTURER_PART") "ISHIDDEN=T")
        (field (name "DB_APPROVED_BY") "ISHIDDEN=T")
      )
      (libsource (lib "Database_Libs1") (part "TEST_POINT_1"))
    )
    (comp (ref "TP17")
      (value "100_254")
      (footprint "SMD_TP_100-254")
      (fields
        (field (name "DB_PART_NUMBER") "TPO000000001")
        (field (name "DB_MANUFACTURER_PART") "ISHIDDEN=T")
        (field (name "DB_APPROVED_BY") "ISHIDDEN=T")
      )
      (libsource (lib "Database_Libs1") (part "TEST_POINT_1"))
    )
    (comp (ref "TP26")
      (value "100_254")
      (footprint "SMD_TP_100-254")
      (fields
        (field (name "DB_PART_NUMBER") "TPO000000001")
        (field (name "DB_MANUFACTURER_PART") "ISHIDDEN=T")
        (field (name "DB_APPROVED_BY") "ISHIDDEN=T")
      )
      (libsource (lib "Database_Libs1") (part "TEST_POINT_1"))
    )
    (comp (ref "TP27")
      (value "100_254")
      (footprint "SMD_TP_100-254")
      (fields
        (field (name "DB_PART_NUMBER") "TPO000000001")
        (field (name "DB_MANUFACTURER_PART") "ISHIDDEN=T")
        (field (name "DB_APPROVED_BY") "ISHIDDEN=T")
      )
      (libsource (lib "Database_Libs1") (part "TEST_POINT_1"))
    )
    (comp (ref "TP39")
      (value "100_254")
      (footprint "SMD_TP_100-254")
      (fields
        (field (name "DB_PART_NUMBER") "TPO000000001")
        (field (name "DB_MANUFACTURER_PART") "ISHIDDEN=T")
        (field (name "DB_APPROVED_BY") "ISHIDDEN=T")
      )
      (libsource (lib "Database_Libs1") (part "TEST_POINT_1"))
    )
    (comp (ref "TP40")
      (value "100_254")
      (footprint "SMD_TP_100-254")
      (fields
        (field (name "DB_PART_NUMBER") "TPO000000001")
        (field (name "DB_MANUFACTURER_PART") "ISHIDDEN=T")
        (field (name "DB_APPROVED_BY") "ISHIDDEN=T")
      )
      (libsource (lib "Database_Libs1") (part "TEST_POINT_1"))
    )
    (comp (ref "TP41")
      (value "100_254")
      (footprint "SMD_TP_100-254")
      (fields
        (field (name "DB_PART_NUMBER") "TPO000000001")
        (field (name "DB_MANUFACTURER_PART") "ISHIDDEN=T")
        (field (name "DB_APPROVED_BY") "ISHIDDEN=T")
      )
      (libsource (lib "Database_Libs1") (part "TEST_POINT_1"))
    )
    (comp (ref "TP42")
      (value "100_254")
      (footprint "SMD_TP_100-254")
      (fields
        (field (name "DB_PART_NUMBER") "TPO000000001")
        (field (name "DB_MANUFACTURER_PART") "ISHIDDEN=T")
        (field (name "DB_APPROVED_BY") "ISHIDDEN=T")
      )
      (libsource (lib "Database_Libs1") (part "TEST_POINT_1"))
    )
    (comp (ref "TP43")
      (value "100_254")
      (footprint "SMD_TP_100-254")
      (fields
        (field (name "DB_PART_NUMBER") "TPO000000001")
        (field (name "DB_MANUFACTURER_PART") "ISHIDDEN=T")
        (field (name "DB_APPROVED_BY") "ISHIDDEN=T")
      )
      (libsource (lib "Database_Libs1") (part "TEST_POINT_1"))
    )
    (comp (ref "TP44")
      (value "100_254")
      (footprint "SMD_TP_100-254")
      (fields
        (field (name "DB_PART_NUMBER") "TPO000000001")
        (field (name "DB_MANUFACTURER_PART") "ISHIDDEN=T")
        (field (name "DB_APPROVED_BY") "ISHIDDEN=T")
      )
      (libsource (lib "Database_Libs1") (part "TEST_POINT_1"))
    )
    (comp (ref "TP56")
      (value "100_254")
      (footprint "SMD_TP_100-254")
      (fields
        (field (name "DB_PART_NUMBER") "TPO000000001")
        (field (name "DB_MANUFACTURER_PART") "ISHIDDEN=T")
        (field (name "DB_APPROVED_BY") "ISHIDDEN=T")
      )
      (libsource (lib "Database_Libs1") (part "TEST_POINT_1"))
    )
    (comp (ref "TP57")
      (value "100_254")
      (footprint "SMD_TP_100-254")
      (fields
        (field (name "DB_PART_NUMBER") "TPO000000001")
        (field (name "DB_MANUFACTURER_PART") "ISHIDDEN=T")
        (field (name "DB_APPROVED_BY") "ISHIDDEN=T")
      )
      (libsource (lib "Database_Libs1") (part "TEST_POINT_1"))
    )
    (comp (ref "TP58")
      (value "100_254")
      (footprint "SMD_TP_100-254")
      (fields
        (field (name "DB_PART_NUMBER") "TPO000000001")
        (field (name "DB_MANUFACTURER_PART") "ISHIDDEN=T")
        (field (name "DB_APPROVED_BY") "ISHIDDEN=T")
      )
      (libsource (lib "Database_Libs1") (part "TEST_POINT_1"))
    )
    (comp (ref "TP59")
      (value "100_254")
      (footprint "SMD_TP_100-254")
      (fields
        (field (name "DB_PART_NUMBER") "TPO000000001")
        (field (name "DB_MANUFACTURER_PART") "ISHIDDEN=T")
        (field (name "DB_APPROVED_BY") "ISHIDDEN=T")
      )
      (libsource (lib "Database_Libs1") (part "TEST_POINT_1"))
    )
    (comp (ref "TP60")
      (value "100_254")
      (footprint "SMD_TP_100-254")
      (fields
        (field (name "DB_PART_NUMBER") "TPO000000001")
        (field (name "DB_MANUFACTURER_PART") "ISHIDDEN=T")
        (field (name "DB_APPROVED_BY") "ISHIDDEN=T")
      )
      (libsource (lib "Database_Libs1") (part "TEST_POINT_1"))
    )
    (comp (ref "TP61")
      (value "100_254")
      (footprint "SMD_TP_100-254")
      (fields
        (field (name "DB_PART_NUMBER") "TPO000000001")
        (field (name "DB_MANUFACTURER_PART") "ISHIDDEN=T")
        (field (name "DB_APPROVED_BY") "ISHIDDEN=T")
      )
      (libsource (lib "Database_Libs1") (part "TEST_POINT_1"))
    )
    (comp (ref "TP73")
      (value "100_254")
      (footprint "SMD_TP_100-254")
      (fields
        (field (name "DB_PART_NUMBER") "TPO000000001")
        (field (name "DB_MANUFACTURER_PART") "ISHIDDEN=T")
        (field (name "DB_APPROVED_BY") "ISHIDDEN=T")
      )
      (libsource (lib "Database_Libs1") (part "TEST_POINT_1"))
    )
    (comp (ref "TP74")
      (value "100_254")
      (footprint "SMD_TP_100-254")
      (fields
        (field (name "DB_PART_NUMBER") "TPO000000001")
        (field (name "DB_MANUFACTURER_PART") "ISHIDDEN=T")
        (field (name "DB_APPROVED_BY") "ISHIDDEN=T")
      )
      (libsource (lib "Database_Libs1") (part "TEST_POINT_1"))
    )
    (comp (ref "TP75")
      (value "100_254")
      (footprint "SMD_TP_100-254")
      (fields
        (field (name "DB_PART_NUMBER") "TPO000000001")
        (field (name "DB_MANUFACTURER_PART") "ISHIDDEN=T")
        (field (name "DB_APPROVED_BY") "ISHIDDEN=T")
      )
      (libsource (lib "Database_Libs1") (part "TEST_POINT_1"))
    )
    (comp (ref "TP76")
      (value "100_254")
      (footprint "SMD_TP_100-254")
      (fields
        (field (name "DB_PART_NUMBER") "TPO000000001")
        (field (name "DB_MANUFACTURER_PART") "ISHIDDEN=T")
        (field (name "DB_APPROVED_BY") "ISHIDDEN=T")
      )
      (libsource (lib "Database_Libs1") (part "TEST_POINT_1"))
    )
    (comp (ref "TP77")
      (value "100_254")
      (footprint "SMD_TP_100-254")
      (fields
        (field (name "DB_PART_NUMBER") "TPO000000001")
        (field (name "DB_MANUFACTURER_PART") "ISHIDDEN=T")
        (field (name "DB_APPROVED_BY") "ISHIDDEN=T")
      )
      (libsource (lib "Database_Libs1") (part "TEST_POINT_1"))
    )
    (comp (ref "TP78")
      (value "100_254")
      (footprint "SMD_TP_100-254")
      (fields
        (field (name "DB_PART_NUMBER") "TPO000000001")
        (field (name "DB_MANUFACTURER_PART") "ISHIDDEN=T")
        (field (name "DB_APPROVED_BY") "ISHIDDEN=T")
      )
      (libsource (lib "Database_Libs1") (part "TEST_POINT_1"))
    )
    (comp (ref "TP84")
      (value "100_254")
      (footprint "SMD_TP_100-254")
      (fields
        (field (name "DB_PART_NUMBER") "TPO000000001")
        (field (name "DB_MANUFACTURER_PART") "ISHIDDEN=T")
        (field (name "DB_APPROVED_BY") "ISHIDDEN=T")
      )
      (libsource (lib "Database_Libs1") (part "TEST_POINT_1"))
    )
    (comp (ref "TP105")
      (value "100_254")
      (footprint "SMD_TP_100-254")
      (fields
        (field (name "DB_PART_NUMBER") "TPO000000001")
        (field (name "DB_MANUFACTURER_PART") "ISHIDDEN=T")
        (field (name "DB_APPROVED_BY") "ISHIDDEN=T")
      )
      (libsource (lib "Database_Libs1") (part "TEST_POINT_1"))
    )
    (comp (ref "TP106")
      (value "100_254")
      (footprint "SMD_TP_100-254")
      (fields
        (field (name "DB_PART_NUMBER") "TPO000000001")
        (field (name "DB_MANUFACTURER_PART") "ISHIDDEN=T")
        (field (name "DB_APPROVED_BY") "ISHIDDEN=T")
      )
      (libsource (lib "Database_Libs1") (part "TEST_POINT_1"))
    )
    (comp (ref "TP107")
      (value "100_254")
      (footprint "SMD_TP_100-254")
      (fields
        (field (name "DB_PART_NUMBER") "TPO000000001")
        (field (name "DB_MANUFACTURER_PART") "ISHIDDEN=T")
        (field (name "DB_APPROVED_BY") "ISHIDDEN=T")
      )
      (libsource (lib "Database_Libs1") (part "TEST_POINT_1"))
    )
    (comp (ref "TP108")
      (value "100_254")
      (footprint "SMD_TP_100-254")
      (fields
        (field (name "DB_PART_NUMBER") "TPO000000001")
        (field (name "DB_MANUFACTURER_PART") "ISHIDDEN=T")
        (field (name "DB_APPROVED_BY") "ISHIDDEN=T")
      )
      (libsource (lib "Database_Libs1") (part "TEST_POINT_1"))
    )
    (comp (ref "TP109")
      (value "100_254")
      (footprint "SMD_TP_100-254")
      (fields
        (field (name "DB_PART_NUMBER") "TPO000000001")
        (field (name "DB_MANUFACTURER_PART") "ISHIDDEN=T")
        (field (name "DB_APPROVED_BY") "ISHIDDEN=T")
      )
      (libsource (lib "Database_Libs1") (part "TEST_POINT_1"))
    )
    (comp (ref "TP110")
      (value "100_254")
      (footprint "SMD_TP_100-254")
      (fields
        (field (name "DB_PART_NUMBER") "TPO000000001")
        (field (name "DB_MANUFACTURER_PART") "ISHIDDEN=T")
        (field (name "DB_APPROVED_BY") "ISHIDDEN=T")
      )
      (libsource (lib "Database_Libs1") (part "TEST_POINT_1"))
    )
    (comp (ref "TP111")
      (value "100_254")
      (footprint "SMD_TP_100-254")
      (fields
        (field (name "DB_PART_NUMBER") "TPO000000001")
        (field (name "DB_MANUFACTURER_PART") "ISHIDDEN=T")
        (field (name "DB_APPROVED_BY") "ISHIDDEN=T")
      )
      (libsource (lib "Database_Libs1") (part "TEST_POINT_1"))
    )
    (comp (ref "TP112")
      (value "100_254")
      (footprint "SMD_TP_100-254")
      (fields
        (field (name "DB_PART_NUMBER") "TPO000000001")
        (field (name "DB_MANUFACTURER_PART") "ISHIDDEN=T")
        (field (name "DB_APPROVED_BY") "ISHIDDEN=T")
      )
      (libsource (lib "Database_Libs1") (part "TEST_POINT_1"))
    )
    (comp (ref "TP113")
      (value "100_254")
      (footprint "SMD_TP_100-254")
      (fields
        (field (name "DB_PART_NUMBER") "TPO000000001")
        (field (name "DB_MANUFACTURER_PART") "ISHIDDEN=T")
        (field (name "DB_APPROVED_BY") "ISHIDDEN=T")
      )
      (libsource (lib "Database_Libs1") (part "TEST_POINT_1"))
    )
    (comp (ref "TP114")
      (value "100_254")
      (footprint "SMD_TP_100-254")
      (fields
        (field (name "DB_PART_NUMBER") "TPO000000001")
        (field (name "DB_MANUFACTURER_PART") "ISHIDDEN=T")
        (field (name "DB_APPROVED_BY") "ISHIDDEN=T")
      )
      (libsource (lib "Database_Libs1") (part "TEST_POINT_1"))
    )
    (comp (ref "TP115")
      (value "100_254")
      (footprint "SMD_TP_100-254")
      (fields
        (field (name "DB_PART_NUMBER") "TPO000000001")
        (field (name "DB_MANUFACTURER_PART") "ISHIDDEN=T")
        (field (name "DB_APPROVED_BY") "ISHIDDEN=T")
      )
      (libsource (lib "Database_Libs1") (part "TEST_POINT_1"))
    )
    (comp (ref "TP116")
      (value "100_254")
      (footprint "SMD_TP_100-254")
      (fields
        (field (name "DB_PART_NUMBER") "TPO000000001")
        (field (name "DB_MANUFACTURER_PART") "ISHIDDEN=T")
        (field (name "DB_APPROVED_BY") "ISHIDDEN=T")
      )
      (libsource (lib "Database_Libs1") (part "TEST_POINT_1"))
    )
    (comp (ref "TP117")
      (value "100_254")
      (footprint "SMD_TP_100-254")
      (fields
        (field (name "DB_PART_NUMBER") "TPO000000001")
        (field (name "DB_MANUFACTURER_PART") "ISHIDDEN=T")
        (field (name "DB_APPROVED_BY") "ISHIDDEN=T")
      )
      (libsource (lib "Database_Libs1") (part "TEST_POINT_1"))
    )
    (comp (ref "TP118")
      (value "100_254")
      (footprint "SMD_TP_100-254")
      (fields
        (field (name "DB_PART_NUMBER") "TPO000000001")
        (field (name "DB_MANUFACTURER_PART") "ISHIDDEN=T")
        (field (name "DB_APPROVED_BY") "ISHIDDEN=T")
      )
      (libsource (lib "Database_Libs1") (part "TEST_POINT_1"))
    )
    (comp (ref "TP119")
      (value "100_254")
      (footprint "SMD_TP_100-254")
      (fields
        (field (name "DB_PART_NUMBER") "TPO000000001")
        (field (name "DB_MANUFACTURER_PART") "ISHIDDEN=T")
        (field (name "DB_APPROVED_BY") "ISHIDDEN=T")
      )
      (libsource (lib "Database_Libs1") (part "TEST_POINT_1"))
    )
    (comp (ref "TP120")
      (value "100_254")
      (footprint "SMD_TP_100-254")
      (fields
        (field (name "DB_PART_NUMBER") "TPO000000001")
        (field (name "DB_MANUFACTURER_PART") "ISHIDDEN=T")
        (field (name "DB_APPROVED_BY") "ISHIDDEN=T")
      )
      (libsource (lib "Database_Libs1") (part "TEST_POINT_1"))
    )
    (comp (ref "TP121")
      (value "100_254")
      (footprint "SMD_TP_100-254")
      (fields
        (field (name "DB_PART_NUMBER") "TPO000000001")
        (field (name "DB_MANUFACTURER_PART") "ISHIDDEN=T")
        (field (name "DB_APPROVED_BY") "ISHIDDEN=T")
      )
      (libsource (lib "Database_Libs1") (part "TEST_POINT_1"))
    )
    (comp (ref "TP122")
      (value "100_254")
      (footprint "SMD_TP_100-254")
      (fields
        (field (name "DB_PART_NUMBER") "TPO000000001")
        (field (name "DB_MANUFACTURER_PART") "ISHIDDEN=T")
        (field (name "DB_APPROVED_BY") "ISHIDDEN=T")
      )
      (libsource (lib "Database_Libs1") (part "TEST_POINT_1"))
    )
    (comp (ref "TP130")
      (value "100_254")
      (footprint "SMD_TP_100-254")
      (fields
        (field (name "DB_PART_NUMBER") "TPO000000001")
        (field (name "DB_MANUFACTURER_PART") "ISHIDDEN=T")
        (field (name "DB_APPROVED_BY") "ISHIDDEN=T")
      )
      (libsource (lib "Database_Libs1") (part "TEST_POINT_1"))
    )
    (comp (ref "TP133")
      (value "100_254")
      (footprint "SMD_TP_100-254")
      (fields
        (field (name "DB_PART_NUMBER") "TPO000000001")
        (field (name "DB_MANUFACTURER_PART") "ISHIDDEN=T")
        (field (name "DB_APPROVED_BY") "ISHIDDEN=T")
      )
      (libsource (lib "Database_Libs1") (part "TEST_POINT_1"))
    )
    (comp (ref "TP134")
      (value "100_254")
      (footprint "SMD_TP_100-254")
      (fields
        (field (name "DB_PART_NUMBER") "TPO000000001")
        (field (name "DB_MANUFACTURER_PART") "ISHIDDEN=T")
        (field (name "DB_APPROVED_BY") "ISHIDDEN=T")
      )
      (libsource (lib "Database_Libs1") (part "TEST_POINT_1"))
    )
    (comp (ref "TP135")
      (value "100_254")
      (footprint "SMD_TP_100-254")
      (fields
        (field (name "DB_PART_NUMBER") "TPO000000001")
        (field (name "DB_MANUFACTURER_PART") "ISHIDDEN=T")
        (field (name "DB_APPROVED_BY") "ISHIDDEN=T")
      )
      (libsource (lib "Database_Libs1") (part "TEST_POINT_1"))
    )
    (comp (ref "TP143")
      (value "100_254")
      (footprint "SMD_TP_100-254")
      (fields
        (field (name "DB_PART_NUMBER") "TPO000000001")
        (field (name "DB_MANUFACTURER_PART") "ISHIDDEN=T")
        (field (name "DB_APPROVED_BY") "ISHIDDEN=T")
      )
      (libsource (lib "Database_Libs1") (part "TEST_POINT_1"))
    )
    (comp (ref "TP151")
      (value "100_254")
      (footprint "SMD_TP_100-254")
      (fields
        (field (name "DB_PART_NUMBER") "TPO000000001")
        (field (name "DB_MANUFACTURER_PART") "ISHIDDEN=T")
        (field (name "DB_APPROVED_BY") "ISHIDDEN=T")
      )
      (libsource (lib "Database_Libs1") (part "TEST_POINT_1"))
    )
    (comp (ref "TP153")
      (value "100_254")
      (footprint "SMD_TP_100-254")
      (fields
        (field (name "DB_PART_NUMBER") "TPO000000001")
        (field (name "DB_MANUFACTURER_PART") "ISHIDDEN=T")
        (field (name "DB_APPROVED_BY") "ISHIDDEN=T")
      )
      (libsource (lib "Database_Libs1") (part "TEST_POINT_1"))
    )
    (comp (ref "TP202")
      (value "100_254")
      (footprint "SMD_TP_100-254")
      (fields
        (field (name "DB_PART_NUMBER") "TPO000000001")
        (field (name "DB_MANUFACTURER_PART") "ISHIDDEN=T")
        (field (name "DB_APPROVED_BY") "ISHIDDEN=T")
      )
      (libsource (lib "Database_Libs1") (part "TEST_POINT_1"))
    )
    (comp (ref "TP203")
      (value "100_254")
      (footprint "SMD_TP_100-254")
      (fields
        (field (name "DB_PART_NUMBER") "TPO000000001")
        (field (name "DB_MANUFACTURER_PART") "ISHIDDEN=T")
        (field (name "DB_APPROVED_BY") "ISHIDDEN=T")
      )
      (libsource (lib "Database_Libs1") (part "TEST_POINT_1"))
    )
    (comp (ref "TP204")
      (value "100_254")
      (footprint "SMD_TP_100-254")
      (fields
        (field (name "DB_PART_NUMBER") "TPO000000001")
        (field (name "DB_MANUFACTURER_PART") "ISHIDDEN=T")
        (field (name "DB_APPROVED_BY") "ISHIDDEN=T")
      )
      (libsource (lib "Database_Libs1") (part "TEST_POINT_1"))
    )
    (comp (ref "TP205")
      (value "100_254")
      (footprint "SMD_TP_100-254")
      (fields
        (field (name "DB_PART_NUMBER") "TPO000000001")
        (field (name "DB_MANUFACTURER_PART") "ISHIDDEN=T")
        (field (name "DB_APPROVED_BY") "ISHIDDEN=T")
      )
      (libsource (lib "Database_Libs1") (part "TEST_POINT_1"))
    )
    (comp (ref "TP206")
      (value "100_254")
      (footprint "SMD_TP_100-254")
      (fields
        (field (name "DB_PART_NUMBER") "TPO000000001")
        (field (name "DB_MANUFACTURER_PART") "ISHIDDEN=T")
        (field (name "DB_APPROVED_BY") "ISHIDDEN=T")
      )
      (libsource (lib "Database_Libs1") (part "TEST_POINT_1"))
    )
    (comp (ref "TP207")
      (value "100_254")
      (footprint "SMD_TP_100-254")
      (fields
        (field (name "DB_PART_NUMBER") "TPO000000001")
        (field (name "DB_MANUFACTURER_PART") "ISHIDDEN=T")
        (field (name "DB_APPROVED_BY") "ISHIDDEN=T")
      )
      (libsource (lib "Database_Libs1") (part "TEST_POINT_1"))
    )
    (comp (ref "TP208")
      (value "100_254")
      (footprint "SMD_TP_100-254")
      (fields
        (field (name "DB_PART_NUMBER") "TPO000000001")
        (field (name "DB_MANUFACTURER_PART") "ISHIDDEN=T")
        (field (name "DB_APPROVED_BY") "ISHIDDEN=T")
      )
      (libsource (lib "Database_Libs1") (part "TEST_POINT_1"))
    )
    (comp (ref "TP209")
      (value "100_254")
      (footprint "SMD_TP_100-254")
      (fields
        (field (name "DB_PART_NUMBER") "TPO000000001")
        (field (name "DB_MANUFACTURER_PART") "ISHIDDEN=T")
        (field (name "DB_APPROVED_BY") "ISHIDDEN=T")
      )
      (libsource (lib "Database_Libs1") (part "TEST_POINT_1"))
    )
    (comp (ref "TP210")
      (value "100_254")
      (footprint "SMD_TP_100-254")
      (fields
        (field (name "DB_PART_NUMBER") "TPO000000001")
        (field (name "DB_MANUFACTURER_PART") "ISHIDDEN=T")
        (field (name "DB_APPROVED_BY") "ISHIDDEN=T")
      )
      (libsource (lib "Database_Libs1") (part "TEST_POINT_1"))
    )
    (comp (ref "TP211")
      (value "100_254")
      (footprint "SMD_TP_100-254")
      (fields
        (field (name "DB_PART_NUMBER") "TPO000000001")
        (field (name "DB_MANUFACTURER_PART") "ISHIDDEN=T")
        (field (name "DB_APPROVED_BY") "ISHIDDEN=T")
      )
      (libsource (lib "Database_Libs1") (part "TEST_POINT_1"))
    )
    (comp (ref "TP212")
      (value "100_254")
      (footprint "SMD_TP_100-254")
      (fields
        (field (name "DB_PART_NUMBER") "TPO000000001")
        (field (name "DB_MANUFACTURER_PART") "ISHIDDEN=T")
        (field (name "DB_APPROVED_BY") "ISHIDDEN=T")
      )
      (libsource (lib "Database_Libs1") (part "TEST_POINT_1"))
    )
    (comp (ref "TP213")
      (value "100_254")
      (footprint "SMD_TP_100-254")
      (fields
        (field (name "DB_PART_NUMBER") "TPO000000001")
        (field (name "DB_MANUFACTURER_PART") "ISHIDDEN=T")
        (field (name "DB_APPROVED_BY") "ISHIDDEN=T")
      )
      (libsource (lib "Database_Libs1") (part "TEST_POINT_1"))
    )
    (comp (ref "TP214")
      (value "100_254")
      (footprint "SMD_TP_100-254")
      (fields
        (field (name "DB_PART_NUMBER") "TPO000000001")
        (field (name "DB_MANUFACTURER_PART") "ISHIDDEN=T")
        (field (name "DB_APPROVED_BY") "ISHIDDEN=T")
      )
      (libsource (lib "Database_Libs1") (part "TEST_POINT_1"))
    )
    (comp (ref "TP215")
      (value "100_254")
      (footprint "SMD_TP_100-254")
      (fields
        (field (name "DB_PART_NUMBER") "TPO000000001")
        (field (name "DB_MANUFACTURER_PART") "ISHIDDEN=T")
        (field (name "DB_APPROVED_BY") "ISHIDDEN=T")
      )
      (libsource (lib "Database_Libs1") (part "TEST_POINT_1"))
    )
    (comp (ref "TP216")
      (value "100_254")
      (footprint "SMD_TP_100-254")
      (fields
        (field (name "DB_PART_NUMBER") "TPO000000001")
        (field (name "DB_MANUFACTURER_PART") "ISHIDDEN=T")
        (field (name "DB_APPROVED_BY") "ISHIDDEN=T")
      )
      (libsource (lib "Database_Libs1") (part "TEST_POINT_1"))
    )
    (comp (ref "TP217")
      (value "100_254")
      (footprint "SMD_TP_100-254")
      (fields
        (field (name "DB_PART_NUMBER") "TPO000000001")
        (field (name "DB_MANUFACTURER_PART") "ISHIDDEN=T")
        (field (name "DB_APPROVED_BY") "ISHIDDEN=T")
      )
      (libsource (lib "Database_Libs1") (part "TEST_POINT_1"))
    )
    (comp (ref "TP218")
      (value "100_254")
      (footprint "SMD_TP_100-254")
      (fields
        (field (name "DB_PART_NUMBER") "TPO000000001")
        (field (name "DB_MANUFACTURER_PART") "ISHIDDEN=T")
        (field (name "DB_APPROVED_BY") "ISHIDDEN=T")
      )
      (libsource (lib "Database_Libs1") (part "TEST_POINT_1"))
    )
    (comp (ref "TP219")
      (value "100_254")
      (footprint "SMD_TP_100-254")
      (fields
        (field (name "DB_PART_NUMBER") "TPO000000001")
        (field (name "DB_MANUFACTURER_PART") "ISHIDDEN=T")
        (field (name "DB_APPROVED_BY") "ISHIDDEN=T")
      )
      (libsource (lib "Database_Libs1") (part "TEST_POINT_1"))
    )
    (comp (ref "TP220")
      (value "100_254")
      (footprint "SMD_TP_100-254")
      (fields
        (field (name "DB_PART_NUMBER") "TPO000000001")
        (field (name "DB_MANUFACTURER_PART") "ISHIDDEN=T")
        (field (name "DB_APPROVED_BY") "ISHIDDEN=T")
      )
      (libsource (lib "Database_Libs1") (part "TEST_POINT_1"))
    )
    (comp (ref "TP221")
      (value "100_254")
      (footprint "SMD_TP_100-254")
      (fields
        (field (name "DB_PART_NUMBER") "TPO000000001")
        (field (name "DB_MANUFACTURER_PART") "ISHIDDEN=T")
        (field (name "DB_APPROVED_BY") "ISHIDDEN=T")
      )
      (libsource (lib "Database_Libs1") (part "TEST_POINT_1"))
    )
    (comp (ref "TP222")
      (value "100_254")
      (footprint "SMD_TP_100-254")
      (fields
        (field (name "DB_PART_NUMBER") "TPO000000001")
        (field (name "DB_MANUFACTURER_PART") "ISHIDDEN=T")
        (field (name "DB_APPROVED_BY") "ISHIDDEN=T")
      )
      (libsource (lib "Database_Libs1") (part "TEST_POINT_1"))
    )
    (comp (ref "TP223")
      (value "100_254")
      (footprint "SMD_TP_100-254")
      (fields
        (field (name "DB_PART_NUMBER") "TPO000000001")
        (field (name "DB_MANUFACTURER_PART") "ISHIDDEN=T")
        (field (name "DB_APPROVED_BY") "ISHIDDEN=T")
      )
      (libsource (lib "Database_Libs1") (part "TEST_POINT_1"))
    )
    (comp (ref "TP224")
      (value "100_254")
      (footprint "SMD_TP_100-254")
      (fields
        (field (name "DB_PART_NUMBER") "TPO000000001")
        (field (name "DB_MANUFACTURER_PART") "ISHIDDEN=T")
        (field (name "DB_APPROVED_BY") "ISHIDDEN=T")
      )
      (libsource (lib "Database_Libs1") (part "TEST_POINT_1"))
    )
    (comp (ref "TP225")
      (value "100_254")
      (footprint "SMD_TP_100-254")
      (fields
        (field (name "DB_PART_NUMBER") "TPO000000001")
        (field (name "DB_MANUFACTURER_PART") "ISHIDDEN=T")
        (field (name "DB_APPROVED_BY") "ISHIDDEN=T")
      )
      (libsource (lib "Database_Libs1") (part "TEST_POINT_1"))
    )
    (comp (ref "TP226")
      (value "100_254")
      (footprint "SMD_TP_100-254")
      (fields
        (field (name "DB_PART_NUMBER") "TPO000000001")
        (field (name "DB_MANUFACTURER_PART") "ISHIDDEN=T")
        (field (name "DB_APPROVED_BY") "ISHIDDEN=T")
      )
      (libsource (lib "Database_Libs1") (part "TEST_POINT_1"))
    )
    (comp (ref "TP227")
      (value "100_254")
      (footprint "SMD_TP_100-254")
      (fields
        (field (name "DB_PART_NUMBER") "TPO000000001")
        (field (name "DB_MANUFACTURER_PART") "ISHIDDEN=T")
        (field (name "DB_APPROVED_BY") "ISHIDDEN=T")
      )
      (libsource (lib "Database_Libs1") (part "TEST_POINT_1"))
    )
    (comp (ref "TP228")
      (value "100_254")
      (footprint "SMD_TP_100-254")
      (fields
        (field (name "DB_PART_NUMBER") "TPO000000001")
        (field (name "DB_MANUFACTURER_PART") "ISHIDDEN=T")
        (field (name "DB_APPROVED_BY") "ISHIDDEN=T")
      )
      (libsource (lib "Database_Libs1") (part "TEST_POINT_1"))
    )
    (comp (ref "TP229")
      (value "100_254")
      (footprint "SMD_TP_100-254")
      (fields
        (field (name "DB_PART_NUMBER") "TPO000000001")
        (field (name "DB_MANUFACTURER_PART") "ISHIDDEN=T")
        (field (name "DB_APPROVED_BY") "ISHIDDEN=T")
      )
      (libsource (lib "Database_Libs1") (part "TEST_POINT_1"))
    )
    (comp (ref "TP230")
      (value "100_254")
      (footprint "SMD_TP_100-254")
      (fields
        (field (name "DB_PART_NUMBER") "TPO000000001")
        (field (name "DB_MANUFACTURER_PART") "ISHIDDEN=T")
        (field (name "DB_APPROVED_BY") "ISHIDDEN=T")
      )
      (libsource (lib "Database_Libs1") (part "TEST_POINT_1"))
    )
    (comp (ref "TP231")
      (value "100_254")
      (footprint "SMD_TP_100-254")
      (fields
        (field (name "DB_PART_NUMBER") "TPO000000001")
        (field (name "DB_MANUFACTURER_PART") "ISHIDDEN=T")
        (field (name "DB_APPROVED_BY") "ISHIDDEN=T")
      )
      (libsource (lib "Database_Libs1") (part "TEST_POINT_1"))
    )
    (comp (ref "TP232")
      (value "100_254")
      (footprint "SMD_TP_100-254")
      (fields
        (field (name "DB_PART_NUMBER") "TPO000000001")
        (field (name "DB_MANUFACTURER_PART") "ISHIDDEN=T")
        (field (name "DB_APPROVED_BY") "ISHIDDEN=T")
      )
      (libsource (lib "Database_Libs1") (part "TEST_POINT_1"))
    )
    (comp (ref "TP233")
      (value "100_254")
      (footprint "SMD_TP_100-254")
      (fields
        (field (name "DB_PART_NUMBER") "TPO000000001")
        (field (name "DB_MANUFACTURER_PART") "ISHIDDEN=T")
        (field (name "DB_APPROVED_BY") "ISHIDDEN=T")
      )
      (libsource (lib "Database_Libs1") (part "TEST_POINT_1"))
    )
    (comp (ref "TP234")
      (value "100_254")
      (footprint "SMD_TP_100-254")
      (fields
        (field (name "DB_PART_NUMBER") "TPO000000001")
        (field (name "DB_MANUFACTURER_PART") "ISHIDDEN=T")
        (field (name "DB_APPROVED_BY") "ISHIDDEN=T")
      )
      (libsource (lib "Database_Libs1") (part "TEST_POINT_1"))
    )
    (comp (ref "TP235")
      (value "100_254")
      (footprint "SMD_TP_100-254")
      (fields
        (field (name "DB_PART_NUMBER") "TPO000000001")
        (field (name "DB_MANUFACTURER_PART") "ISHIDDEN=T")
        (field (name "DB_APPROVED_BY") "ISHIDDEN=T")
      )
      (libsource (lib "Database_Libs1") (part "TEST_POINT_1"))
    )
    (comp (ref "TP236")
      (value "100_254")
      (footprint "SMD_TP_100-254")
      (fields
        (field (name "DB_PART_NUMBER") "TPO000000001")
        (field (name "DB_MANUFACTURER_PART") "ISHIDDEN=T")
        (field (name "DB_APPROVED_BY") "ISHIDDEN=T")
      )
      (libsource (lib "Database_Libs1") (part "TEST_POINT_1"))
    )
    (comp (ref "TP237")
      (value "100_254")
      (footprint "SMD_TP_100-254")
      (fields
        (field (name "DB_PART_NUMBER") "TPO000000001")
        (field (name "DB_MANUFACTURER_PART") "ISHIDDEN=T")
        (field (name "DB_APPROVED_BY") "ISHIDDEN=T")
      )
      (libsource (lib "Database_Libs1") (part "TEST_POINT_1"))
    )
    (comp (ref "TP238")
      (value "100_254")
      (footprint "SMD_TP_100-254")
      (fields
        (field (name "DB_PART_NUMBER") "TPO000000001")
        (field (name "DB_MANUFACTURER_PART") "ISHIDDEN=T")
        (field (name "DB_APPROVED_BY") "ISHIDDEN=T")
      )
      (libsource (lib "Database_Libs1") (part "TEST_POINT_1"))
    )
    (comp (ref "TP239")
      (value "100_254")
      (footprint "SMD_TP_100-254")
      (fields
        (field (name "DB_PART_NUMBER") "TPO000000001")
        (field (name "DB_MANUFACTURER_PART") "ISHIDDEN=T")
        (field (name "DB_APPROVED_BY") "ISHIDDEN=T")
      )
      (libsource (lib "Database_Libs1") (part "TEST_POINT_1"))
    )
    (comp (ref "TP240")
      (value "100_254")
      (footprint "SMD_TP_100-254")
      (fields
        (field (name "DB_PART_NUMBER") "TPO000000001")
        (field (name "DB_MANUFACTURER_PART") "ISHIDDEN=T")
        (field (name "DB_APPROVED_BY") "ISHIDDEN=T")
      )
      (libsource (lib "Database_Libs1") (part "TEST_POINT_1"))
    )
    (comp (ref "TP241")
      (value "100_254")
      (footprint "SMD_TP_100-254")
      (fields
        (field (name "DB_PART_NUMBER") "TPO000000001")
        (field (name "DB_MANUFACTURER_PART") "ISHIDDEN=T")
        (field (name "DB_APPROVED_BY") "ISHIDDEN=T")
      )
      (libsource (lib "Database_Libs1") (part "TEST_POINT_1"))
    )
    (comp (ref "TP242")
      (value "100_254")
      (footprint "SMD_TP_100-254")
      (fields
        (field (name "DB_PART_NUMBER") "TPO000000001")
        (field (name "DB_MANUFACTURER_PART") "ISHIDDEN=T")
        (field (name "DB_APPROVED_BY") "ISHIDDEN=T")
      )
      (libsource (lib "Database_Libs1") (part "TEST_POINT_1"))
    )
    (comp (ref "TP243")
      (value "100_254")
      (footprint "SMD_TP_100-254")
      (fields
        (field (name "DB_PART_NUMBER") "TPO000000001")
        (field (name "DB_MANUFACTURER_PART") "ISHIDDEN=T")
        (field (name "DB_APPROVED_BY") "ISHIDDEN=T")
      )
      (libsource (lib "Database_Libs1") (part "TEST_POINT_1"))
    )
    (comp (ref "TP244")
      (value "100_254")
      (footprint "SMD_TP_100-254")
      (fields
        (field (name "DB_PART_NUMBER") "TPO000000001")
        (field (name "DB_MANUFACTURER_PART") "ISHIDDEN=T")
        (field (name "DB_APPROVED_BY") "ISHIDDEN=T")
      )
      (libsource (lib "Database_Libs1") (part "TEST_POINT_1"))
    )
    (comp (ref "TP245")
      (value "100_254")
      (footprint "SMD_TP_100-254")
      (fields
        (field (name "DB_PART_NUMBER") "TPO000000001")
        (field (name "DB_MANUFACTURER_PART") "ISHIDDEN=T")
        (field (name "DB_APPROVED_BY") "ISHIDDEN=T")
      )
      (libsource (lib "Database_Libs1") (part "TEST_POINT_1"))
    )
    (comp (ref "TP246")
      (value "100_254")
      (footprint "SMD_TP_100-254")
      (fields
        (field (name "DB_PART_NUMBER") "TPO000000001")
        (field (name "DB_MANUFACTURER_PART") "ISHIDDEN=T")
        (field (name "DB_APPROVED_BY") "ISHIDDEN=T")
      )
      (libsource (lib "Database_Libs1") (part "TEST_POINT_1"))
    )
    (comp (ref "TP262")
      (value "100_254")
      (footprint "SMD_TP_100-254")
      (fields
        (field (name "DB_PART_NUMBER") "TPO000000001")
        (field (name "DB_MANUFACTURER_PART") "ISHIDDEN=T")
        (field (name "DB_APPROVED_BY") "ISHIDDEN=T")
      )
      (libsource (lib "Database_Libs1") (part "TEST_POINT_1"))
    )
    (comp (ref "TP278")
      (value "100_254")
      (footprint "SMD_TP_100-254")
      (fields
        (field (name "DB_PART_NUMBER") "TPO000000001")
        (field (name "DB_MANUFACTURER_PART") "ISHIDDEN=T")
        (field (name "DB_APPROVED_BY") "ISHIDDEN=T")
      )
      (libsource (lib "Database_Libs1") (part "TEST_POINT_1"))
    )
    (comp (ref "TP295")
      (value "100_254")
      (footprint "SMD_TP_100-254")
      (fields
        (field (name "DB_PART_NUMBER") "TPO000000001")
        (field (name "DB_MANUFACTURER_PART") "ISHIDDEN=T")
        (field (name "DB_APPROVED_BY") "ISHIDDEN=T")
      )
      (libsource (lib "Database_Libs1") (part "TEST_POINT_1"))
    )
    (comp (ref "TP296")
      (value "100_254")
      (footprint "SMD_TP_100-254")
      (fields
        (field (name "DB_PART_NUMBER") "TPO000000001")
        (field (name "DB_MANUFACTURER_PART") "ISHIDDEN=T")
        (field (name "DB_APPROVED_BY") "ISHIDDEN=T")
      )
      (libsource (lib "Database_Libs1") (part "TEST_POINT_1"))
    )
    (comp (ref "TP297")
      (value "100_254")
      (footprint "SMD_TP_100-254")
      (fields
        (field (name "DB_PART_NUMBER") "TPO000000001")
        (field (name "DB_MANUFACTURER_PART") "ISHIDDEN=T")
        (field (name "DB_APPROVED_BY") "ISHIDDEN=T")
      )
      (libsource (lib "Database_Libs1") (part "TEST_POINT_1"))
    )
    (comp (ref "TP300")
      (value "100_254")
      (footprint "SMD_TP_100-254")
      (fields
        (field (name "DB_PART_NUMBER") "TPO000000001")
        (field (name "DB_MANUFACTURER_PART") "ISHIDDEN=T")
        (field (name "DB_APPROVED_BY") "ISHIDDEN=T")
      )
      (libsource (lib "Database_Libs1") (part "TEST_POINT_1"))
    )
    (comp (ref "TP304")
      (value "100_254")
      (footprint "SMD_TP_100-254")
      (fields
        (field (name "DB_PART_NUMBER") "TPO000000001")
        (field (name "DB_MANUFACTURER_PART") "ISHIDDEN=T")
        (field (name "DB_APPROVED_BY") "ISHIDDEN=T")
      )
      (libsource (lib "Database_Libs1") (part "TEST_POINT_1"))
    )
    (comp (ref "U1")
      (value "IC_A3222Q56")
      (footprint "SMD_QFN50P800X800X80-57N")
      (libsource (lib "RockerBox") (part "IC_A3222Q56"))
    )
    (comp (ref "U2")
      (value "IC_A3222Q56")
      (footprint "SMD_QFN50P800X800X80-57N")
      (libsource (lib "RockerBox") (part "IC_A3222Q56"))
    )
    (comp (ref "U3")
      (value "IC_A3222Q56")
      (footprint "SMD_QFN50P800X800X80-57N")
      (libsource (lib "RockerBox") (part "IC_A3222Q56"))
    )
    (comp (ref "U4")
      (value "IC_A3222Q56")
      (footprint "SMD_QFN50P800X800X80-57N")
      (libsource (lib "RockerBox") (part "IC_A3222Q56"))
    )
    (comp (ref "U13")
      (value "IC_A3222Q56")
      (footprint "SMD_QFN50P800X800X80-57N")
      (libsource (lib "RockerBox") (part "IC_A3222Q56"))
    )
    (comp (ref "U14")
      (value "IC_A3222Q56")
      (footprint "SMD_QFN50P800X800X80-57N")
      (libsource (lib "RockerBox") (part "IC_A3222Q56"))
    )
    (comp (ref "U17")
      (value "IC_A3222Q56")
      (footprint "SMD_QFN50P800X800X80-57N")
      (libsource (lib "RockerBox") (part "IC_A3222Q56"))
    )
    (comp (ref "U18")
      (value "IC_A3222Q56")
      (footprint "SMD_QFN50P800X800X80-57N")
      (libsource (lib "RockerBox") (part "IC_A3222Q56"))
    )
    (comp (ref "U21")
      (value "IC_A3222Q56")
      (footprint "SMD_QFN50P800X800X80-57N")
      (libsource (lib "RockerBox") (part "IC_A3222Q56"))
    )
    (comp (ref "U22")
      (value "IC_A3222Q56")
      (footprint "SMD_QFN50P800X800X80-57N")
      (libsource (lib "RockerBox") (part "IC_A3222Q56"))
    )
    (comp (ref "U25")
      (value "IC_A3222Q56")
      (footprint "SMD_QFN50P800X800X80-57N")
      (libsource (lib "RockerBox") (part "IC_A3222Q56"))
    )
    (comp (ref "U26")
      (value "IC_A3222Q56")
      (footprint "SMD_QFN50P800X800X80-57N")
      (libsource (lib "RockerBox") (part "IC_A3222Q56"))
    )
    (comp (ref "U30")
      (value "IC_A3222Q56")
      (footprint "SMD_QFN50P800X800X80-57N")
      (libsource (lib "RockerBox") (part "IC_A3222Q56"))
    )
    (comp (ref "U31")
      (value "IC_A3222Q56")
      (footprint "SMD_QFN50P800X800X80-57N")
      (libsource (lib "RockerBox") (part "IC_A3222Q56"))
    )
    (comp (ref "U32")
      (value "IC_A3222Q56")
      (footprint "SMD_QFN50P800X800X80-57N")
      (libsource (lib "RockerBox") (part "IC_A3222Q56"))
    )
    (comp (ref "U33")
      (value "IC_A3222Q56")
      (footprint "SMD_QFN50P800X800X80-57N")
      (libsource (lib "RockerBox") (part "IC_A3222Q56"))
    )
    (comp (ref "YO1")
      (value "~")
      (footprint "SMD_OSCCF320X400X90-4N")
      (libsource (lib "RockerBox") (part "XTAL_OE1GND2OSC3VDD4"))
    )
    (comp (ref "YO2")
      (value "~")
      (footprint "SMD_OSCCF250X320X90-4N")
      (libsource (lib "RockerBox") (part "XTAL_OE1GND2OSC3VDD4"))
    )
    (comp (ref "YO3")
      (value "~")
      (footprint "SMD_OSCCF200X250X90-4N")
      (libsource (lib "RockerBox") (part "XTAL_OE1GND2OSC3VDD4"))
    )
  )
  (nets
    (net (code "1") (name "/0.9V") (class "Default")
      (node (ref "C304") (pin "2") (pinfunction "2_2") (pintype "passive"))
      (node (ref "C305") (pin "2") (pinfunction "2_2") (pintype "passive"))
      (node (ref "C306") (pin "2") (pinfunction "2_2") (pintype "passive"))
      (node (ref "C307") (pin "2") (pinfunction "2_2") (pintype "passive"))
      (node (ref "C308") (pin "2") (pinfunction "2_2") (pintype "passive"))
      (node (ref "C309") (pin "2") (pinfunction "2_2") (pintype "passive"))
      (node (ref "C310") (pin "2") (pinfunction "2_2") (pintype "passive"))
      (node (ref "C311") (pin "2") (pinfunction "2_2") (pintype "passive"))
      (node (ref "C312") (pin "2") (pinfunction "2_2") (pintype "passive"))
      (node (ref "C313") (pin "2") (pinfunction "2_2") (pintype "passive"))
      (node (ref "C314") (pin "2") (pinfunction "2_2") (pintype "passive"))
      (node (ref "C315") (pin "2") (pinfunction "2_2") (pintype "passive"))
      (node (ref "C316") (pin "2") (pinfunction "2_2") (pintype "passive"))
      (node (ref "C317") (pin "2") (pinfunction "2_2") (pintype "passive"))
      (node (ref "C318") (pin "2") (pinfunction "2_2") (pintype "passive"))
      (node (ref "C319") (pin "2") (pinfunction "2_2") (pintype "passive"))
      (node (ref "TP300") (pin "1") (pinfunction "1_1") (pintype "passive"))
      (node (ref "U1") (pin "14") (pinfunction "VDDPLL_14") (pintype "passive"))
      (node (ref "U1") (pin "29") (pinfunction "NC_29") (pintype "passive"))
      (node (ref "U13") (pin "14") (pinfunction "VDDPLL_14") (pintype "passive"))
      (node (ref "U13") (pin "29") (pinfunction "NC_29") (pintype "passive"))
      (node (ref "U14") (pin "14") (pinfunction "VDDPLL_14") (pintype "passive"))
      (node (ref "U14") (pin "29") (pinfunction "NC_29") (pintype "passive"))
      (node (ref "U17") (pin "14") (pinfunction "VDDPLL_14") (pintype "passive"))
      (node (ref "U17") (pin "29") (pinfunction "NC_29") (pintype "passive"))
      (node (ref "U18") (pin "14") (pinfunction "VDDPLL_14") (pintype "passive"))
      (node (ref "U18") (pin "29") (pinfunction "NC_29") (pintype "passive"))
      (node (ref "U2") (pin "14") (pinfunction "VDDPLL_14") (pintype "passive"))
      (node (ref "U2") (pin "29") (pinfunction "NC_29") (pintype "passive"))
      (node (ref "U21") (pin "14") (pinfunction "VDDPLL_14") (pintype "passive"))
      (node (ref "U21") (pin "29") (pinfunction "NC_29") (pintype "passive"))
      (node (ref "U22") (pin "14") (pinfunction "VDDPLL_14") (pintype "passive"))
      (node (ref "U22") (pin "29") (pinfunction "NC_29") (pintype "passive"))
      (node (ref "U25") (pin "14") (pinfunction "VDDPLL_14") (pintype "passive"))
      (node (ref "U25") (pin "29") (pinfunction "NC_29") (pintype "passive"))
      (node (ref "U26") (pin "14") (pinfunction "VDDPLL_14") (pintype "passive"))
      (node (ref "U26") (pin "29") (pinfunction "NC_29") (pintype "passive"))
      (node (ref "U3") (pin "14") (pinfunction "VDDPLL_14") (pintype "passive"))
      (node (ref "U3") (pin "29") (pinfunction "NC_29") (pintype "passive"))
      (node (ref "U30") (pin "14") (pinfunction "VDDPLL_14") (pintype "passive"))
      (node (ref "U30") (pin "29") (pinfunction "NC_29") (pintype "passive"))
      (node (ref "U31") (pin "14") (pinfunction "VDDPLL_14") (pintype "passive"))
      (node (ref "U31") (pin "29") (pinfunction "NC_29") (pintype "passive"))
      (node (ref "U32") (pin "14") (pinfunction "VDDPLL_14") (pintype "passive"))
      (node (ref "U32") (pin "29") (pinfunction "NC_29") (pintype "passive"))
      (node (ref "U33") (pin "14") (pinfunction "VDDPLL_14") (pintype "passive"))
      (node (ref "U33") (pin "29") (pinfunction "NC_29") (pintype "passive"))
      (node (ref "U4") (pin "14") (pinfunction "VDDPLL_14") (pintype "passive"))
      (node (ref "U4") (pin "29") (pinfunction "NC_29") (pintype "passive"))
    )
    (net (code "2") (name "/1.8V") (class "Default")
      (node (ref "C288") (pin "2") (pinfunction "2_2") (pintype "passive"))
      (node (ref "C289") (pin "2") (pinfunction "2_2") (pintype "passive"))
      (node (ref "C290") (pin "2") (pinfunction "2_2") (pintype "passive"))
      (node (ref "C291") (pin "2") (pinfunction "2_2") (pintype "passive"))
      (node (ref "C292") (pin "2") (pinfunction "2_2") (pintype "passive"))
      (node (ref "C293") (pin "2") (pinfunction "2_2") (pintype "passive"))
      (node (ref "C294") (pin "2") (pinfunction "2_2") (pintype "passive"))
      (node (ref "C295") (pin "2") (pinfunction "2_2") (pintype "passive"))
      (node (ref "C296") (pin "2") (pinfunction "2_2") (pintype "passive"))
      (node (ref "C297") (pin "2") (pinfunction "2_2") (pintype "passive"))
      (node (ref "C298") (pin "2") (pinfunction "2_2") (pintype "passive"))
      (node (ref "C299") (pin "2") (pinfunction "2_2") (pintype "passive"))
      (node (ref "C300") (pin "2") (pinfunction "2_2") (pintype "passive"))
      (node (ref "C301") (pin "2") (pinfunction "2_2") (pintype "passive"))
      (node (ref "C302") (pin "2") (pinfunction "2_2") (pintype "passive"))
      (node (ref "C303") (pin "2") (pinfunction "2_2") (pintype "passive"))
      (node (ref "C322") (pin "2") (pinfunction "2_2") (pintype "passive"))
      (node (ref "TP84") (pin "1") (pinfunction "1_1") (pintype "passive"))
      (node (ref "U1") (pin "1") (pinfunction "VDDIO_1") (pintype "passive"))
      (node (ref "U1") (pin "42") (pinfunction "VDDIO_42") (pintype "passive"))
      (node (ref "U13") (pin "1") (pinfunction "VDDIO_1") (pintype "passive"))
      (node (ref "U13") (pin "42") (pinfunction "VDDIO_42") (pintype "passive"))
      (node (ref "U14") (pin "1") (pinfunction "VDDIO_1") (pintype "passive"))
      (node (ref "U14") (pin "42") (pinfunction "VDDIO_42") (pintype "passive"))
      (node (ref "U17") (pin "1") (pinfunction "VDDIO_1") (pintype "passive"))
      (node (ref "U17") (pin "42") (pinfunction "VDDIO_42") (pintype "passive"))
      (node (ref "U18") (pin "1") (pinfunction "VDDIO_1") (pintype "passive"))
      (node (ref "U18") (pin "42") (pinfunction "VDDIO_42") (pintype "passive"))
      (node (ref "U2") (pin "1") (pinfunction "VDDIO_1") (pintype "passive"))
      (node (ref "U2") (pin "42") (pinfunction "VDDIO_42") (pintype "passive"))
      (node (ref "U21") (pin "1") (pinfunction "VDDIO_1") (pintype "passive"))
      (node (ref "U21") (pin "42") (pinfunction "VDDIO_42") (pintype "passive"))
      (node (ref "U22") (pin "1") (pinfunction "VDDIO_1") (pintype "passive"))
      (node (ref "U22") (pin "42") (pinfunction "VDDIO_42") (pintype "passive"))
      (node (ref "U25") (pin "1") (pinfunction "VDDIO_1") (pintype "passive"))
      (node (ref "U25") (pin "42") (pinfunction "VDDIO_42") (pintype "passive"))
      (node (ref "U26") (pin "1") (pinfunction "VDDIO_1") (pintype "passive"))
      (node (ref "U26") (pin "42") (pinfunction "VDDIO_42") (pintype "passive"))
      (node (ref "U3") (pin "1") (pinfunction "VDDIO_1") (pintype "passive"))
      (node (ref "U3") (pin "42") (pinfunction "VDDIO_42") (pintype "passive"))
      (node (ref "U30") (pin "1") (pinfunction "VDDIO_1") (pintype "passive"))
      (node (ref "U30") (pin "42") (pinfunction "VDDIO_42") (pintype "passive"))
      (node (ref "U31") (pin "1") (pinfunction "VDDIO_1") (pintype "passive"))
      (node (ref "U31") (pin "42") (pinfunction "VDDIO_42") (pintype "passive"))
      (node (ref "U32") (pin "1") (pinfunction "VDDIO_1") (pintype "passive"))
      (node (ref "U32") (pin "42") (pinfunction "VDDIO_42") (pintype "passive"))
      (node (ref "U33") (pin "1") (pinfunction "VDDIO_1") (pintype "passive"))
      (node (ref "U33") (pin "42") (pinfunction "VDDIO_42") (pintype "passive"))
      (node (ref "U4") (pin "1") (pinfunction "VDDIO_1") (pintype "passive"))
      (node (ref "U4") (pin "42") (pinfunction "VDDIO_42") (pintype "passive"))
      (node (ref "YO1") (pin "1") (pinfunction "OE_1") (pintype "passive"))
      (node (ref "YO1") (pin "4") (pinfunction "VDD_4") (pintype "passive"))
      (node (ref "YO2") (pin "1") (pinfunction "OE_1") (pintype "passive"))
      (node (ref "YO2") (pin "4") (pinfunction "VDD_4") (pintype "passive"))
      (node (ref "YO3") (pin "1") (pinfunction "OE_1") (pintype "passive"))
      (node (ref "YO3") (pin "4") (pinfunction "VDD_4") (pintype "passive"))
    )
    (net (code "3") (name "/1V") (class "Default")
      (node (ref "C106") (pin "2") (pinfunction "2_2") (pintype "passive"))
      (node (ref "C107") (pin "2") (pinfunction "2_2") (pintype "passive"))
      (node (ref "C108") (pin "2") (pinfunction "2_2") (pintype "passive"))
      (node (ref "C109") (pin "2") (pinfunction "2_2") (pintype "passive"))
      (node (ref "C110") (pin "2") (pinfunction "2_2") (pintype "passive"))
      (node (ref "C111") (pin "2") (pinfunction "2_2") (pintype "passive"))
      (node (ref "C112") (pin "2") (pinfunction "2_2") (pintype "passive"))
      (node (ref "C113") (pin "2") (pinfunction "2_2") (pintype "passive"))
      (node (ref "C114") (pin "2") (pinfunction "2_2") (pintype "passive"))
      (node (ref "C115") (pin "2") (pinfunction "2_2") (pintype "passive"))
      (node (ref "C118") (pin "2") (pinfunction "2_2") (pintype "passive"))
      (node (ref "C119") (pin "2") (pinfunction "2_2") (pintype "passive"))
      (node (ref "C122") (pin "2") (pinfunction "2_2") (pintype "passive"))
      (node (ref "C123") (pin "2") (pinfunction "2_2") (pintype "passive"))
      (node (ref "C126") (pin "2") (pinfunction "2_2") (pintype "passive"))
      (node (ref "C127") (pin "2") (pinfunction "2_2") (pintype "passive"))
      (node (ref "C138") (pin "2") (pinfunction "2_2") (pintype "passive"))
      (node (ref "C139") (pin "2") (pinfunction "2_2") (pintype "passive"))
      (node (ref "C140") (pin "2") (pinfunction "2_2") (pintype "passive"))
      (node (ref "C141") (pin "2") (pinfunction "2_2") (pintype "passive"))
      (node (ref "C142") (pin "2") (pinfunction "2_2") (pintype "passive"))
      (node (ref "C143") (pin "2") (pinfunction "2_2") (pintype "passive"))
      (node (ref "C144") (pin "2") (pinfunction "2_2") (pintype "passive"))
      (node (ref "C145") (pin "2") (pinfunction "2_2") (pintype "passive"))
      (node (ref "C146") (pin "2") (pinfunction "2_2") (pintype "passive"))
      (node (ref "C147") (pin "2") (pinfunction "2_2") (pintype "passive"))
      (node (ref "C148") (pin "2") (pinfunction "2_2") (pintype "passive"))
      (node (ref "C149") (pin "2") (pinfunction "2_2") (pintype "passive"))
      (node (ref "C150") (pin "2") (pinfunction "2_2") (pintype "passive"))
      (node (ref "C151") (pin "2") (pinfunction "2_2") (pintype "passive"))
      (node (ref "C152") (pin "2") (pinfunction "2_2") (pintype "passive"))
      (node (ref "C153") (pin "2") (pinfunction "2_2") (pintype "passive"))
      (node (ref "C154") (pin "2") (pinfunction "2_2") (pintype "passive"))
      (node (ref "C155") (pin "2") (pinfunction "2_2") (pintype "passive"))
      (node (ref "C156") (pin "2") (pinfunction "2_2") (pintype "passive"))
      (node (ref "C157") (pin "2") (pinfunction "2_2") (pintype "passive"))
      (node (ref "C158") (pin "2") (pinfunction "2_2") (pintype "passive"))
      (node (ref "C159") (pin "2") (pinfunction "2_2") (pintype "passive"))
      (node (ref "C160") (pin "2") (pinfunction "2_2") (pintype "passive"))
      (node (ref "C161") (pin "2") (pinfunction "2_2") (pintype "passive"))
      (node (ref "C162") (pin "2") (pinfunction "2_2") (pintype "passive"))
      (node (ref "C163") (pin "2") (pinfunction "2_2") (pintype "passive"))
      (node (ref "C164") (pin "2") (pinfunction "2_2") (pintype "passive"))
      (node (ref "C165") (pin "2") (pinfunction "2_2") (pintype "passive"))
      (node (ref "C166") (pin "2") (pinfunction "2_2") (pintype "passive"))
      (node (ref "C167") (pin "2") (pinfunction "2_2") (pintype "passive"))
      (node (ref "C169") (pin "2") (pinfunction "2_2") (pintype "passive"))
      (node (ref "C170") (pin "2") (pinfunction "2_2") (pintype "passive"))
      (node (ref "C171") (pin "2") (pinfunction "2_2") (pintype "passive"))
      (node (ref "C172") (pin "2") (pinfunction "2_2") (pintype "passive"))
      (node (ref "C173") (pin "2") (pinfunction "2_2") (pintype "passive"))
      (node (ref "C174") (pin "2") (pinfunction "2_2") (pintype "passive"))
      (node (ref "C175") (pin "2") (pinfunction "2_2") (pintype "passive"))
      (node (ref "C176") (pin "2") (pinfunction "2_2") (pintype "passive"))
      (node (ref "C177") (pin "2") (pinfunction "2_2") (pintype "passive"))
      (node (ref "C178") (pin "2") (pinfunction "2_2") (pintype "passive"))
      (node (ref "C179") (pin "2") (pinfunction "2_2") (pintype "passive"))
      (node (ref "C180") (pin "2") (pinfunction "2_2") (pintype "passive"))
      (node (ref "C181") (pin "2") (pinfunction "2_2") (pintype "passive"))
      (node (ref "C182") (pin "2") (pinfunction "2_2") (pintype "passive"))
      (node (ref "C183") (pin "2") (pinfunction "2_2") (pintype "passive"))
      (node (ref "C184") (pin "2") (pinfunction "2_2") (pintype "passive"))
      (node (ref "C185") (pin "2") (pinfunction "2_2") (pintype "passive"))
      (node (ref "C186") (pin "2") (pinfunction "2_2") (pintype "passive"))
      (node (ref "C187") (pin "2") (pinfunction "2_2") (pintype "passive"))
      (node (ref "C188") (pin "2") (pinfunction "2_2") (pintype "passive"))
      (node (ref "C189") (pin "2") (pinfunction "2_2") (pintype "passive"))
      (node (ref "C19") (pin "2") (pinfunction "2_2") (pintype "passive"))
      (node (ref "C190") (pin "2") (pinfunction "2_2") (pintype "passive"))
      (node (ref "C191") (pin "2") (pinfunction "2_2") (pintype "passive"))
      (node (ref "C192") (pin "2") (pinfunction "2_2") (pintype "passive"))
      (node (ref "C193") (pin "2") (pinfunction "2_2") (pintype "passive"))
      (node (ref "C194") (pin "2") (pinfunction "2_2") (pintype "passive"))
      (node (ref "C195") (pin "2") (pinfunction "2_2") (pintype "passive"))
      (node (ref "C196") (pin "2") (pinfunction "2_2") (pintype "passive"))
      (node (ref "C197") (pin "2") (pinfunction "2_2") (pintype "passive"))
      (node (ref "C198") (pin "2") (pinfunction "2_2") (pintype "passive"))
      (node (ref "C199") (pin "2") (pinfunction "2_2") (pintype "passive"))
      (node (ref "C200") (pin "2") (pinfunction "2_2") (pintype "passive"))
      (node (ref "C201") (pin "2") (pinfunction "2_2") (pintype "passive"))
      (node (ref "C202") (pin "2") (pinfunction "2_2") (pintype "passive"))
      (node (ref "C203") (pin "2") (pinfunction "2_2") (pintype "passive"))
      (node (ref "C204") (pin "2") (pinfunction "2_2") (pintype "passive"))
      (node (ref "C205") (pin "2") (pinfunction "2_2") (pintype "passive"))
      (node (ref "C206") (pin "2") (pinfunction "2_2") (pintype "passive"))
      (node (ref "C207") (pin "2") (pinfunction "2_2") (pintype "passive"))
      (node (ref "C208") (pin "2") (pinfunction "2_2") (pintype "passive"))
      (node (ref "C209") (pin "2") (pinfunction "2_2") (pintype "passive"))
      (node (ref "C210") (pin "2") (pinfunction "2_2") (pintype "passive"))
      (node (ref "C211") (pin "2") (pinfunction "2_2") (pintype "passive"))
      (node (ref "C212") (pin "2") (pinfunction "2_2") (pintype "passive"))
      (node (ref "C213") (pin "2") (pinfunction "2_2") (pintype "passive"))
      (node (ref "C214") (pin "2") (pinfunction "2_2") (pintype "passive"))
      (node (ref "C215") (pin "2") (pinfunction "2_2") (pintype "passive"))
      (node (ref "C216") (pin "2") (pinfunction "2_2") (pintype "passive"))
      (node (ref "C217") (pin "2") (pinfunction "2_2") (pintype "passive"))
      (node (ref "C218") (pin "2") (pinfunction "2_2") (pintype "passive"))
      (node (ref "C219") (pin "2") (pinfunction "2_2") (pintype "passive"))
      (node (ref "C22") (pin "2") (pinfunction "2_2") (pintype "passive"))
      (node (ref "C220") (pin "2") (pinfunction "2_2") (pintype "passive"))
      (node (ref "C221") (pin "2") (pinfunction "2_2") (pintype "passive"))
      (node (ref "C222") (pin "2") (pinfunction "2_2") (pintype "passive"))
      (node (ref "C223") (pin "2") (pinfunction "2_2") (pintype "passive"))
      (node (ref "C224") (pin "2") (pinfunction "2_2") (pintype "passive"))
      (node (ref "C225") (pin "2") (pinfunction "2_2") (pintype "passive"))
      (node (ref "C226") (pin "2") (pinfunction "2_2") (pintype "passive"))
      (node (ref "C227") (pin "2") (pinfunction "2_2") (pintype "passive"))
      (node (ref "C228") (pin "2") (pinfunction "2_2") (pintype "passive"))
      (node (ref "C229") (pin "2") (pinfunction "2_2") (pintype "passive"))
      (node (ref "C23") (pin "2") (pinfunction "2_2") (pintype "passive"))
      (node (ref "C230") (pin "2") (pinfunction "2_2") (pintype "passive"))
      (node (ref "C233") (pin "2") (pinfunction "2_2") (pintype "passive"))
      (node (ref "C234") (pin "2") (pinfunction "2_2") (pintype "passive"))
      (node (ref "C235") (pin "2") (pinfunction "2_2") (pintype "passive"))
      (node (ref "C237") (pin "2") (pinfunction "2_2") (pintype "passive"))
      (node (ref "C238") (pin "2") (pinfunction "2_2") (pintype "passive"))
      (node (ref "C239") (pin "2") (pinfunction "2_2") (pintype "passive"))
      (node (ref "C240") (pin "2") (pinfunction "2_2") (pintype "passive"))
      (node (ref "C241") (pin "2") (pinfunction "2_2") (pintype "passive"))
      (node (ref "C242") (pin "2") (pinfunction "2_2") (pintype "passive"))
      (node (ref "C243") (pin "2") (pinfunction "2_2") (pintype "passive"))
      (node (ref "C244") (pin "2") (pinfunction "2_2") (pintype "passive"))
      (node (ref "C245") (pin "2") (pinfunction "2_2") (pintype "passive"))
      (node (ref "C246") (pin "2") (pinfunction "2_2") (pintype "passive"))
      (node (ref "C247") (pin "2") (pinfunction "2_2") (pintype "passive"))
      (node (ref "C248") (pin "2") (pinfunction "2_2") (pintype "passive"))
      (node (ref "C249") (pin "2") (pinfunction "2_2") (pintype "passive"))
      (node (ref "C252") (pin "2") (pinfunction "2_2") (pintype "passive"))
      (node (ref "C253") (pin "2") (pinfunction "2_2") (pintype "passive"))
      (node (ref "C254") (pin "2") (pinfunction "2_2") (pintype "passive"))
      (node (ref "C255") (pin "2") (pinfunction "2_2") (pintype "passive"))
      (node (ref "C256") (pin "2") (pinfunction "2_2") (pintype "passive"))
      (node (ref "C257") (pin "2") (pinfunction "2_2") (pintype "passive"))
      (node (ref "C258") (pin "2") (pinfunction "2_2") (pintype "passive"))
      (node (ref "C259") (pin "2") (pinfunction "2_2") (pintype "passive"))
      (node (ref "C26") (pin "2") (pinfunction "2_2") (pintype "passive"))
      (node (ref "C260") (pin "2") (pinfunction "2_2") (pintype "passive"))
      (node (ref "C261") (pin "2") (pinfunction "2_2") (pintype "passive"))
      (node (ref "C262") (pin "2") (pinfunction "2_2") (pintype "passive"))
      (node (ref "C263") (pin "2") (pinfunction "2_2") (pintype "passive"))
      (node (ref "C264") (pin "2") (pinfunction "2_2") (pintype "passive"))
      (node (ref "C265") (pin "2") (pinfunction "2_2") (pintype "passive"))
      (node (ref "C266") (pin "2") (pinfunction "2_2") (pintype "passive"))
      (node (ref "C267") (pin "2") (pinfunction "2_2") (pintype "passive"))
      (node (ref "C268") (pin "2") (pinfunction "2_2") (pintype "passive"))
      (node (ref "C269") (pin "2") (pinfunction "2_2") (pintype "passive"))
      (node (ref "C27") (pin "2") (pinfunction "2_2") (pintype "passive"))
      (node (ref "C270") (pin "2") (pinfunction "2_2") (pintype "passive"))
      (node (ref "C271") (pin "2") (pinfunction "2_2") (pintype "passive"))
      (node (ref "C272") (pin "2") (pinfunction "2_2") (pintype "passive"))
      (node (ref "C273") (pin "2") (pinfunction "2_2") (pintype "passive"))
      (node (ref "C274") (pin "2") (pinfunction "2_2") (pintype "passive"))
      (node (ref "C275") (pin "2") (pinfunction "2_2") (pintype "passive"))
      (node (ref "C276") (pin "2") (pinfunction "2_2") (pintype "passive"))
      (node (ref "C277") (pin "2") (pinfunction "2_2") (pintype "passive"))
      (node (ref "C278") (pin "2") (pinfunction "2_2") (pintype "passive"))
      (node (ref "C279") (pin "2") (pinfunction "2_2") (pintype "passive"))
      (node (ref "C280") (pin "2") (pinfunction "2_2") (pintype "passive"))
      (node (ref "C281") (pin "2") (pinfunction "2_2") (pintype "passive"))
      (node (ref "C282") (pin "2") (pinfunction "2_2") (pintype "passive"))
      (node (ref "C283") (pin "2") (pinfunction "2_2") (pintype "passive"))
      (node (ref "C284") (pin "2") (pinfunction "2_2") (pintype "passive"))
      (node (ref "C285") (pin "2") (pinfunction "2_2") (pintype "passive"))
      (node (ref "C286") (pin "2") (pinfunction "2_2") (pintype "passive"))
      (node (ref "C287") (pin "2") (pinfunction "2_2") (pintype "passive"))
      (node (ref "C30") (pin "2") (pinfunction "2_2") (pintype "passive"))
      (node (ref "C31") (pin "2") (pinfunction "2_2") (pintype "passive"))
      (node (ref "C36") (pin "2") (pinfunction "2_2") (pintype "passive"))
      (node (ref "C42") (pin "2") (pinfunction "2_2") (pintype "passive"))
      (node (ref "C43") (pin "2") (pinfunction "2_2") (pintype "passive"))
      (node (ref "C44") (pin "2") (pinfunction "2_2") (pintype "passive"))
      (node (ref "C45") (pin "2") (pinfunction "2_2") (pintype "passive"))
      (node (ref "C46") (pin "2") (pinfunction "2_2") (pintype "passive"))
      (node (ref "C47") (pin "2") (pinfunction "2_2") (pintype "passive"))
      (node (ref "C48") (pin "2") (pinfunction "2_2") (pintype "passive"))
      (node (ref "C49") (pin "2") (pinfunction "2_2") (pintype "passive"))
      (node (ref "C492") (pin "2") (pinfunction "2_2") (pintype "passive"))
      (node (ref "C493") (pin "2") (pinfunction "2_2") (pintype "passive"))
      (node (ref "C494") (pin "2") (pinfunction "2_2") (pintype "passive"))
      (node (ref "C495") (pin "2") (pinfunction "2_2") (pintype "passive"))
      (node (ref "C496") (pin "2") (pinfunction "2_2") (pintype "passive"))
      (node (ref "C497") (pin "2") (pinfunction "2_2") (pintype "passive"))
      (node (ref "C498") (pin "2") (pinfunction "2_2") (pintype "passive"))
      (node (ref "C499") (pin "2") (pinfunction "2_2") (pintype "passive"))
      (node (ref "C50") (pin "2") (pinfunction "2_2") (pintype "passive"))
      (node (ref "C500") (pin "2") (pinfunction "2_2") (pintype "passive"))
      (node (ref "C501") (pin "2") (pinfunction "2_2") (pintype "passive"))
      (node (ref "C502") (pin "2") (pinfunction "2_2") (pintype "passive"))
      (node (ref "C503") (pin "2") (pinfunction "2_2") (pintype "passive"))
      (node (ref "C504") (pin "2") (pinfunction "2_2") (pintype "passive"))
      (node (ref "C505") (pin "2") (pinfunction "2_2") (pintype "passive"))
      (node (ref "C506") (pin "2") (pinfunction "2_2") (pintype "passive"))
      (node (ref "C507") (pin "2") (pinfunction "2_2") (pintype "passive"))
      (node (ref "C508") (pin "2") (pinfunction "2_2") (pintype "passive"))
      (node (ref "C509") (pin "2") (pinfunction "2_2") (pintype "passive"))
      (node (ref "C51") (pin "2") (pinfunction "2_2") (pintype "passive"))
      (node (ref "C510") (pin "2") (pinfunction "2_2") (pintype "passive"))
      (node (ref "C511") (pin "2") (pinfunction "2_2") (pintype "passive"))
      (node (ref "C512") (pin "2") (pinfunction "2_2") (pintype "passive"))
      (node (ref "C513") (pin "2") (pinfunction "2_2") (pintype "passive"))
      (node (ref "C514") (pin "2") (pinfunction "2_2") (pintype "passive"))
      (node (ref "C515") (pin "2") (pinfunction "2_2") (pintype "passive"))
      (node (ref "C516") (pin "2") (pinfunction "2_2") (pintype "passive"))
      (node (ref "C517") (pin "2") (pinfunction "2_2") (pintype "passive"))
      (node (ref "C518") (pin "2") (pinfunction "2_2") (pintype "passive"))
      (node (ref "C519") (pin "2") (pinfunction "2_2") (pintype "passive"))
      (node (ref "C520") (pin "2") (pinfunction "2_2") (pintype "passive"))
      (node (ref "C521") (pin "2") (pinfunction "2_2") (pintype "passive"))
      (node (ref "C522") (pin "2") (pinfunction "2_2") (pintype "passive"))
      (node (ref "C523") (pin "2") (pinfunction "2_2") (pintype "passive"))
      (node (ref "C524") (pin "2") (pinfunction "2_2") (pintype "passive"))
      (node (ref "C525") (pin "2") (pinfunction "2_2") (pintype "passive"))
      (node (ref "C526") (pin "2") (pinfunction "2_2") (pintype "passive"))
      (node (ref "C527") (pin "2") (pinfunction "2_2") (pintype "passive"))
      (node (ref "C528") (pin "2") (pinfunction "2_2") (pintype "passive"))
      (node (ref "C529") (pin "2") (pinfunction "2_2") (pintype "passive"))
      (node (ref "C530") (pin "2") (pinfunction "2_2") (pintype "passive"))
      (node (ref "C531") (pin "2") (pinfunction "2_2") (pintype "passive"))
      (node (ref "C532") (pin "2") (pinfunction "2_2") (pintype "passive"))
      (node (ref "C533") (pin "2") (pinfunction "2_2") (pintype "passive"))
      (node (ref "C534") (pin "2") (pinfunction "2_2") (pintype "passive"))
      (node (ref "C535") (pin "2") (pinfunction "2_2") (pintype "passive"))
      (node (ref "C536") (pin "2") (pinfunction "2_2") (pintype "passive"))
      (node (ref "C537") (pin "2") (pinfunction "2_2") (pintype "passive"))
      (node (ref "C538") (pin "2") (pinfunction "2_2") (pintype "passive"))
      (node (ref "C539") (pin "2") (pinfunction "2_2") (pintype "passive"))
      (node (ref "C54") (pin "2") (pinfunction "2_2") (pintype "passive"))
      (node (ref "C540") (pin "2") (pinfunction "2_2") (pintype "passive"))
      (node (ref "C541") (pin "2") (pinfunction "2_2") (pintype "passive"))
      (node (ref "C542") (pin "2") (pinfunction "2_2") (pintype "passive"))
      (node (ref "C543") (pin "2") (pinfunction "2_2") (pintype "passive"))
      (node (ref "C544") (pin "2") (pinfunction "2_2") (pintype "passive"))
      (node (ref "C545") (pin "2") (pinfunction "2_2") (pintype "passive"))
      (node (ref "C546") (pin "2") (pinfunction "2_2") (pintype "passive"))
      (node (ref "C547") (pin "2") (pinfunction "2_2") (pintype "passive"))
      (node (ref "C548") (pin "2") (pinfunction "2_2") (pintype "passive"))
      (node (ref "C549") (pin "2") (pinfunction "2_2") (pintype "passive"))
      (node (ref "C55") (pin "2") (pinfunction "2_2") (pintype "passive"))
      (node (ref "C550") (pin "2") (pinfunction "2_2") (pintype "passive"))
      (node (ref "C551") (pin "2") (pinfunction "2_2") (pintype "passive"))
      (node (ref "C552") (pin "2") (pinfunction "2_2") (pintype "passive"))
      (node (ref "C553") (pin "2") (pinfunction "2_2") (pintype "passive"))
      (node (ref "C554") (pin "2") (pinfunction "2_2") (pintype "passive"))
      (node (ref "C555") (pin "2") (pinfunction "2_2") (pintype "passive"))
      (node (ref "C556") (pin "2") (pinfunction "2_2") (pintype "passive"))
      (node (ref "C557") (pin "2") (pinfunction "2_2") (pintype "passive"))
      (node (ref "C558") (pin "2") (pinfunction "2_2") (pintype "passive"))
      (node (ref "C559") (pin "2") (pinfunction "2_2") (pintype "passive"))
      (node (ref "C560") (pin "2") (pinfunction "2_2") (pintype "passive"))
      (node (ref "C561") (pin "2") (pinfunction "2_2") (pintype "passive"))
      (node (ref "C562") (pin "2") (pinfunction "2_2") (pintype "passive"))
      (node (ref "C563") (pin "2") (pinfunction "2_2") (pintype "passive"))
      (node (ref "C564") (pin "2") (pinfunction "2_2") (pintype "passive"))
      (node (ref "C565") (pin "2") (pinfunction "2_2") (pintype "passive"))
      (node (ref "C566") (pin "2") (pinfunction "2_2") (pintype "passive"))
      (node (ref "C567") (pin "2") (pinfunction "2_2") (pintype "passive"))
      (node (ref "C568") (pin "2") (pinfunction "2_2") (pintype "passive"))
      (node (ref "C569") (pin "2") (pinfunction "2_2") (pintype "passive"))
      (node (ref "C570") (pin "2") (pinfunction "2_2") (pintype "passive"))
      (node (ref "C571") (pin "2") (pinfunction "2_2") (pintype "passive"))
      (node (ref "C572") (pin "2") (pinfunction "2_2") (pintype "passive"))
      (node (ref "C573") (pin "2") (pinfunction "2_2") (pintype "passive"))
      (node (ref "C574") (pin "2") (pinfunction "2_2") (pintype "passive"))
      (node (ref "C575") (pin "2") (pinfunction "2_2") (pintype "passive"))
      (node (ref "C576") (pin "2") (pinfunction "2_2") (pintype "passive"))
      (node (ref "C577") (pin "2") (pinfunction "2_2") (pintype "passive"))
      (node (ref "C578") (pin "2") (pinfunction "2_2") (pintype "passive"))
      (node (ref "C579") (pin "2") (pinfunction "2_2") (pintype "passive"))
      (node (ref "C58") (pin "2") (pinfunction "2_2") (pintype "passive"))
      (node (ref "C580") (pin "2") (pinfunction "2_2") (pintype "passive"))
      (node (ref "C581") (pin "2") (pinfunction "2_2") (pintype "passive"))
      (node (ref "C582") (pin "2") (pinfunction "2_2") (pintype "passive"))
      (node (ref "C583") (pin "2") (pinfunction "2_2") (pintype "passive"))
      (node (ref "C584") (pin "2") (pinfunction "2_2") (pintype "passive"))
      (node (ref "C585") (pin "2") (pinfunction "2_2") (pintype "passive"))
      (node (ref "C586") (pin "2") (pinfunction "2_2") (pintype "passive"))
      (node (ref "C587") (pin "2") (pinfunction "2_2") (pintype "passive"))
      (node (ref "C588") (pin "2") (pinfunction "2_2") (pintype "passive"))
      (node (ref "C589") (pin "2") (pinfunction "2_2") (pintype "passive"))
      (node (ref "C59") (pin "2") (pinfunction "2_2") (pintype "passive"))
      (node (ref "C590") (pin "2") (pinfunction "2_2") (pintype "passive"))
      (node (ref "C591") (pin "2") (pinfunction "2_2") (pintype "passive"))
      (node (ref "C62") (pin "2") (pinfunction "2_2") (pintype "passive"))
      (node (ref "C63") (pin "2") (pinfunction "2_2") (pintype "passive"))
      (node (ref "C74") (pin "2") (pinfunction "2_2") (pintype "passive"))
      (node (ref "C75") (pin "2") (pinfunction "2_2") (pintype "passive"))
      (node (ref "C76") (pin "2") (pinfunction "2_2") (pintype "passive"))
      (node (ref "C77") (pin "2") (pinfunction "2_2") (pintype "passive"))
      (node (ref "C78") (pin "2") (pinfunction "2_2") (pintype "passive"))
      (node (ref "C79") (pin "2") (pinfunction "2_2") (pintype "passive"))
      (node (ref "C80") (pin "2") (pinfunction "2_2") (pintype "passive"))
      (node (ref "C81") (pin "2") (pinfunction "2_2") (pintype "passive"))
      (node (ref "C82") (pin "2") (pinfunction "2_2") (pintype "passive"))
      (node (ref "C83") (pin "2") (pinfunction "2_2") (pintype "passive"))
      (node (ref "C86") (pin "2") (pinfunction "2_2") (pintype "passive"))
      (node (ref "C87") (pin "2") (pinfunction "2_2") (pintype "passive"))
      (node (ref "C90") (pin "2") (pinfunction "2_2") (pintype "passive"))
      (node (ref "C91") (pin "2") (pinfunction "2_2") (pintype "passive"))
      (node (ref "C94") (pin "2") (pinfunction "2_2") (pintype "passive"))
      (node (ref "C95") (pin "2") (pinfunction "2_2") (pintype "passive"))
      (node (ref "U1") (pin "15") (pinfunction "VDD_15") (pintype "passive"))
      (node (ref "U1") (pin "16") (pinfunction "VDD_16") (pintype "passive"))
      (node (ref "U1") (pin "17") (pinfunction "VDD_17") (pintype "passive"))
      (node (ref "U1") (pin "18") (pinfunction "VDD_18") (pintype "passive"))
      (node (ref "U1") (pin "19") (pinfunction "VDD_19") (pintype "passive"))
      (node (ref "U1") (pin "20") (pinfunction "VDD_20") (pintype "passive"))
      (node (ref "U1") (pin "21") (pinfunction "VDD_21") (pintype "passive"))
      (node (ref "U1") (pin "22") (pinfunction "VDD_22") (pintype "passive"))
      (node (ref "U1") (pin "23") (pinfunction "VDD_23") (pintype "passive"))
      (node (ref "U1") (pin "24") (pinfunction "VDD_24") (pintype "passive"))
      (node (ref "U1") (pin "25") (pinfunction "VDD_25") (pintype "passive"))
      (node (ref "U1") (pin "26") (pinfunction "VDD_26") (pintype "passive"))
      (node (ref "U1") (pin "27") (pinfunction "VDD_27") (pintype "passive"))
      (node (ref "U1") (pin "28") (pinfunction "VDD_28") (pintype "passive"))
      (node (ref "U1") (pin "43") (pinfunction "VDD_43") (pintype "passive"))
      (node (ref "U1") (pin "44") (pinfunction "VDD_44") (pintype "passive"))
      (node (ref "U1") (pin "45") (pinfunction "VDD_45") (pintype "passive"))
      (node (ref "U1") (pin "46") (pinfunction "VDD_46") (pintype "passive"))
      (node (ref "U1") (pin "47") (pinfunction "VDD_47") (pintype "passive"))
      (node (ref "U1") (pin "48") (pinfunction "VDD_48") (pintype "passive"))
      (node (ref "U1") (pin "49") (pinfunction "VDD_49") (pintype "passive"))
      (node (ref "U1") (pin "50") (pinfunction "VDD_50") (pintype "passive"))
      (node (ref "U1") (pin "51") (pinfunction "VDD_51") (pintype "passive"))
      (node (ref "U1") (pin "52") (pinfunction "VDD_52") (pintype "passive"))
      (node (ref "U1") (pin "53") (pinfunction "VDD_53") (pintype "passive"))
      (node (ref "U1") (pin "54") (pinfunction "VDD_54") (pintype "passive"))
      (node (ref "U1") (pin "55") (pinfunction "VDD_55") (pintype "passive"))
      (node (ref "U1") (pin "56") (pinfunction "VDD_56") (pintype "passive"))
      (node (ref "U13") (pin "15") (pinfunction "VDD_15") (pintype "passive"))
      (node (ref "U13") (pin "16") (pinfunction "VDD_16") (pintype "passive"))
      (node (ref "U13") (pin "17") (pinfunction "VDD_17") (pintype "passive"))
      (node (ref "U13") (pin "18") (pinfunction "VDD_18") (pintype "passive"))
      (node (ref "U13") (pin "19") (pinfunction "VDD_19") (pintype "passive"))
      (node (ref "U13") (pin "20") (pinfunction "VDD_20") (pintype "passive"))
      (node (ref "U13") (pin "21") (pinfunction "VDD_21") (pintype "passive"))
      (node (ref "U13") (pin "22") (pinfunction "VDD_22") (pintype "passive"))
      (node (ref "U13") (pin "23") (pinfunction "VDD_23") (pintype "passive"))
      (node (ref "U13") (pin "24") (pinfunction "VDD_24") (pintype "passive"))
      (node (ref "U13") (pin "25") (pinfunction "VDD_25") (pintype "passive"))
      (node (ref "U13") (pin "26") (pinfunction "VDD_26") (pintype "passive"))
      (node (ref "U13") (pin "27") (pinfunction "VDD_27") (pintype "passive"))
      (node (ref "U13") (pin "28") (pinfunction "VDD_28") (pintype "passive"))
      (node (ref "U13") (pin "43") (pinfunction "VDD_43") (pintype "passive"))
      (node (ref "U13") (pin "44") (pinfunction "VDD_44") (pintype "passive"))
      (node (ref "U13") (pin "45") (pinfunction "VDD_45") (pintype "passive"))
      (node (ref "U13") (pin "46") (pinfunction "VDD_46") (pintype "passive"))
      (node (ref "U13") (pin "47") (pinfunction "VDD_47") (pintype "passive"))
      (node (ref "U13") (pin "48") (pinfunction "VDD_48") (pintype "passive"))
      (node (ref "U13") (pin "49") (pinfunction "VDD_49") (pintype "passive"))
      (node (ref "U13") (pin "50") (pinfunction "VDD_50") (pintype "passive"))
      (node (ref "U13") (pin "51") (pinfunction "VDD_51") (pintype "passive"))
      (node (ref "U13") (pin "52") (pinfunction "VDD_52") (pintype "passive"))
      (node (ref "U13") (pin "53") (pinfunction "VDD_53") (pintype "passive"))
      (node (ref "U13") (pin "54") (pinfunction "VDD_54") (pintype "passive"))
      (node (ref "U13") (pin "55") (pinfunction "VDD_55") (pintype "passive"))
      (node (ref "U13") (pin "56") (pinfunction "VDD_56") (pintype "passive"))
      (node (ref "U14") (pin "15") (pinfunction "VDD_15") (pintype "passive"))
      (node (ref "U14") (pin "16") (pinfunction "VDD_16") (pintype "passive"))
      (node (ref "U14") (pin "17") (pinfunction "VDD_17") (pintype "passive"))
      (node (ref "U14") (pin "18") (pinfunction "VDD_18") (pintype "passive"))
      (node (ref "U14") (pin "19") (pinfunction "VDD_19") (pintype "passive"))
      (node (ref "U14") (pin "20") (pinfunction "VDD_20") (pintype "passive"))
      (node (ref "U14") (pin "21") (pinfunction "VDD_21") (pintype "passive"))
      (node (ref "U14") (pin "22") (pinfunction "VDD_22") (pintype "passive"))
      (node (ref "U14") (pin "23") (pinfunction "VDD_23") (pintype "passive"))
      (node (ref "U14") (pin "24") (pinfunction "VDD_24") (pintype "passive"))
      (node (ref "U14") (pin "25") (pinfunction "VDD_25") (pintype "passive"))
      (node (ref "U14") (pin "26") (pinfunction "VDD_26") (pintype "passive"))
      (node (ref "U14") (pin "27") (pinfunction "VDD_27") (pintype "passive"))
      (node (ref "U14") (pin "28") (pinfunction "VDD_28") (pintype "passive"))
      (node (ref "U14") (pin "43") (pinfunction "VDD_43") (pintype "passive"))
      (node (ref "U14") (pin "44") (pinfunction "VDD_44") (pintype "passive"))
      (node (ref "U14") (pin "45") (pinfunction "VDD_45") (pintype "passive"))
      (node (ref "U14") (pin "46") (pinfunction "VDD_46") (pintype "passive"))
      (node (ref "U14") (pin "47") (pinfunction "VDD_47") (pintype "passive"))
      (node (ref "U14") (pin "48") (pinfunction "VDD_48") (pintype "passive"))
      (node (ref "U14") (pin "49") (pinfunction "VDD_49") (pintype "passive"))
      (node (ref "U14") (pin "50") (pinfunction "VDD_50") (pintype "passive"))
      (node (ref "U14") (pin "51") (pinfunction "VDD_51") (pintype "passive"))
      (node (ref "U14") (pin "52") (pinfunction "VDD_52") (pintype "passive"))
      (node (ref "U14") (pin "53") (pinfunction "VDD_53") (pintype "passive"))
      (node (ref "U14") (pin "54") (pinfunction "VDD_54") (pintype "passive"))
      (node (ref "U14") (pin "55") (pinfunction "VDD_55") (pintype "passive"))
      (node (ref "U14") (pin "56") (pinfunction "VDD_56") (pintype "passive"))
      (node (ref "U17") (pin "15") (pinfunction "VDD_15") (pintype "passive"))
      (node (ref "U17") (pin "16") (pinfunction "VDD_16") (pintype "passive"))
      (node (ref "U17") (pin "17") (pinfunction "VDD_17") (pintype "passive"))
      (node (ref "U17") (pin "18") (pinfunction "VDD_18") (pintype "passive"))
      (node (ref "U17") (pin "19") (pinfunction "VDD_19") (pintype "passive"))
      (node (ref "U17") (pin "20") (pinfunction "VDD_20") (pintype "passive"))
      (node (ref "U17") (pin "21") (pinfunction "VDD_21") (pintype "passive"))
      (node (ref "U17") (pin "22") (pinfunction "VDD_22") (pintype "passive"))
      (node (ref "U17") (pin "23") (pinfunction "VDD_23") (pintype "passive"))
      (node (ref "U17") (pin "24") (pinfunction "VDD_24") (pintype "passive"))
      (node (ref "U17") (pin "25") (pinfunction "VDD_25") (pintype "passive"))
      (node (ref "U17") (pin "26") (pinfunction "VDD_26") (pintype "passive"))
      (node (ref "U17") (pin "27") (pinfunction "VDD_27") (pintype "passive"))
      (node (ref "U17") (pin "28") (pinfunction "VDD_28") (pintype "passive"))
      (node (ref "U17") (pin "43") (pinfunction "VDD_43") (pintype "passive"))
      (node (ref "U17") (pin "44") (pinfunction "VDD_44") (pintype "passive"))
      (node (ref "U17") (pin "45") (pinfunction "VDD_45") (pintype "passive"))
      (node (ref "U17") (pin "46") (pinfunction "VDD_46") (pintype "passive"))
      (node (ref "U17") (pin "47") (pinfunction "VDD_47") (pintype "passive"))
      (node (ref "U17") (pin "48") (pinfunction "VDD_48") (pintype "passive"))
      (node (ref "U17") (pin "49") (pinfunction "VDD_49") (pintype "passive"))
      (node (ref "U17") (pin "50") (pinfunction "VDD_50") (pintype "passive"))
      (node (ref "U17") (pin "51") (pinfunction "VDD_51") (pintype "passive"))
      (node (ref "U17") (pin "52") (pinfunction "VDD_52") (pintype "passive"))
      (node (ref "U17") (pin "53") (pinfunction "VDD_53") (pintype "passive"))
      (node (ref "U17") (pin "54") (pinfunction "VDD_54") (pintype "passive"))
      (node (ref "U17") (pin "55") (pinfunction "VDD_55") (pintype "passive"))
      (node (ref "U17") (pin "56") (pinfunction "VDD_56") (pintype "passive"))
      (node (ref "U18") (pin "15") (pinfunction "VDD_15") (pintype "passive"))
      (node (ref "U18") (pin "16") (pinfunction "VDD_16") (pintype "passive"))
      (node (ref "U18") (pin "17") (pinfunction "VDD_17") (pintype "passive"))
      (node (ref "U18") (pin "18") (pinfunction "VDD_18") (pintype "passive"))
      (node (ref "U18") (pin "19") (pinfunction "VDD_19") (pintype "passive"))
      (node (ref "U18") (pin "20") (pinfunction "VDD_20") (pintype "passive"))
      (node (ref "U18") (pin "21") (pinfunction "VDD_21") (pintype "passive"))
      (node (ref "U18") (pin "22") (pinfunction "VDD_22") (pintype "passive"))
      (node (ref "U18") (pin "23") (pinfunction "VDD_23") (pintype "passive"))
      (node (ref "U18") (pin "24") (pinfunction "VDD_24") (pintype "passive"))
      (node (ref "U18") (pin "25") (pinfunction "VDD_25") (pintype "passive"))
      (node (ref "U18") (pin "26") (pinfunction "VDD_26") (pintype "passive"))
      (node (ref "U18") (pin "27") (pinfunction "VDD_27") (pintype "passive"))
      (node (ref "U18") (pin "28") (pinfunction "VDD_28") (pintype "passive"))
      (node (ref "U18") (pin "43") (pinfunction "VDD_43") (pintype "passive"))
      (node (ref "U18") (pin "44") (pinfunction "VDD_44") (pintype "passive"))
      (node (ref "U18") (pin "45") (pinfunction "VDD_45") (pintype "passive"))
      (node (ref "U18") (pin "46") (pinfunction "VDD_46") (pintype "passive"))
      (node (ref "U18") (pin "47") (pinfunction "VDD_47") (pintype "passive"))
      (node (ref "U18") (pin "48") (pinfunction "VDD_48") (pintype "passive"))
      (node (ref "U18") (pin "49") (pinfunction "VDD_49") (pintype "passive"))
      (node (ref "U18") (pin "50") (pinfunction "VDD_50") (pintype "passive"))
      (node (ref "U18") (pin "51") (pinfunction "VDD_51") (pintype "passive"))
      (node (ref "U18") (pin "52") (pinfunction "VDD_52") (pintype "passive"))
      (node (ref "U18") (pin "53") (pinfunction "VDD_53") (pintype "passive"))
      (node (ref "U18") (pin "54") (pinfunction "VDD_54") (pintype "passive"))
      (node (ref "U18") (pin "55") (pinfunction "VDD_55") (pintype "passive"))
      (node (ref "U18") (pin "56") (pinfunction "VDD_56") (pintype "passive"))
      (node (ref "U2") (pin "15") (pinfunction "VDD_15") (pintype "passive"))
      (node (ref "U2") (pin "16") (pinfunction "VDD_16") (pintype "passive"))
      (node (ref "U2") (pin "17") (pinfunction "VDD_17") (pintype "passive"))
      (node (ref "U2") (pin "18") (pinfunction "VDD_18") (pintype "passive"))
      (node (ref "U2") (pin "19") (pinfunction "VDD_19") (pintype "passive"))
      (node (ref "U2") (pin "20") (pinfunction "VDD_20") (pintype "passive"))
      (node (ref "U2") (pin "21") (pinfunction "VDD_21") (pintype "passive"))
      (node (ref "U2") (pin "22") (pinfunction "VDD_22") (pintype "passive"))
      (node (ref "U2") (pin "23") (pinfunction "VDD_23") (pintype "passive"))
      (node (ref "U2") (pin "24") (pinfunction "VDD_24") (pintype "passive"))
      (node (ref "U2") (pin "25") (pinfunction "VDD_25") (pintype "passive"))
      (node (ref "U2") (pin "26") (pinfunction "VDD_26") (pintype "passive"))
      (node (ref "U2") (pin "27") (pinfunction "VDD_27") (pintype "passive"))
      (node (ref "U2") (pin "28") (pinfunction "VDD_28") (pintype "passive"))
      (node (ref "U2") (pin "43") (pinfunction "VDD_43") (pintype "passive"))
      (node (ref "U2") (pin "44") (pinfunction "VDD_44") (pintype "passive"))
      (node (ref "U2") (pin "45") (pinfunction "VDD_45") (pintype "passive"))
      (node (ref "U2") (pin "46") (pinfunction "VDD_46") (pintype "passive"))
      (node (ref "U2") (pin "47") (pinfunction "VDD_47") (pintype "passive"))
      (node (ref "U2") (pin "48") (pinfunction "VDD_48") (pintype "passive"))
      (node (ref "U2") (pin "49") (pinfunction "VDD_49") (pintype "passive"))
      (node (ref "U2") (pin "50") (pinfunction "VDD_50") (pintype "passive"))
      (node (ref "U2") (pin "51") (pinfunction "VDD_51") (pintype "passive"))
      (node (ref "U2") (pin "52") (pinfunction "VDD_52") (pintype "passive"))
      (node (ref "U2") (pin "53") (pinfunction "VDD_53") (pintype "passive"))
      (node (ref "U2") (pin "54") (pinfunction "VDD_54") (pintype "passive"))
      (node (ref "U2") (pin "55") (pinfunction "VDD_55") (pintype "passive"))
      (node (ref "U2") (pin "56") (pinfunction "VDD_56") (pintype "passive"))
      (node (ref "U21") (pin "15") (pinfunction "VDD_15") (pintype "passive"))
      (node (ref "U21") (pin "16") (pinfunction "VDD_16") (pintype "passive"))
      (node (ref "U21") (pin "17") (pinfunction "VDD_17") (pintype "passive"))
      (node (ref "U21") (pin "18") (pinfunction "VDD_18") (pintype "passive"))
      (node (ref "U21") (pin "19") (pinfunction "VDD_19") (pintype "passive"))
      (node (ref "U21") (pin "20") (pinfunction "VDD_20") (pintype "passive"))
      (node (ref "U21") (pin "21") (pinfunction "VDD_21") (pintype "passive"))
      (node (ref "U21") (pin "22") (pinfunction "VDD_22") (pintype "passive"))
      (node (ref "U21") (pin "23") (pinfunction "VDD_23") (pintype "passive"))
      (node (ref "U21") (pin "24") (pinfunction "VDD_24") (pintype "passive"))
      (node (ref "U21") (pin "25") (pinfunction "VDD_25") (pintype "passive"))
      (node (ref "U21") (pin "26") (pinfunction "VDD_26") (pintype "passive"))
      (node (ref "U21") (pin "27") (pinfunction "VDD_27") (pintype "passive"))
      (node (ref "U21") (pin "28") (pinfunction "VDD_28") (pintype "passive"))
      (node (ref "U21") (pin "43") (pinfunction "VDD_43") (pintype "passive"))
      (node (ref "U21") (pin "44") (pinfunction "VDD_44") (pintype "passive"))
      (node (ref "U21") (pin "45") (pinfunction "VDD_45") (pintype "passive"))
      (node (ref "U21") (pin "46") (pinfunction "VDD_46") (pintype "passive"))
      (node (ref "U21") (pin "47") (pinfunction "VDD_47") (pintype "passive"))
      (node (ref "U21") (pin "48") (pinfunction "VDD_48") (pintype "passive"))
      (node (ref "U21") (pin "49") (pinfunction "VDD_49") (pintype "passive"))
      (node (ref "U21") (pin "50") (pinfunction "VDD_50") (pintype "passive"))
      (node (ref "U21") (pin "51") (pinfunction "VDD_51") (pintype "passive"))
      (node (ref "U21") (pin "52") (pinfunction "VDD_52") (pintype "passive"))
      (node (ref "U21") (pin "53") (pinfunction "VDD_53") (pintype "passive"))
      (node (ref "U21") (pin "54") (pinfunction "VDD_54") (pintype "passive"))
      (node (ref "U21") (pin "55") (pinfunction "VDD_55") (pintype "passive"))
      (node (ref "U21") (pin "56") (pinfunction "VDD_56") (pintype "passive"))
      (node (ref "U22") (pin "15") (pinfunction "VDD_15") (pintype "passive"))
      (node (ref "U22") (pin "16") (pinfunction "VDD_16") (pintype "passive"))
      (node (ref "U22") (pin "17") (pinfunction "VDD_17") (pintype "passive"))
      (node (ref "U22") (pin "18") (pinfunction "VDD_18") (pintype "passive"))
      (node (ref "U22") (pin "19") (pinfunction "VDD_19") (pintype "passive"))
      (node (ref "U22") (pin "20") (pinfunction "VDD_20") (pintype "passive"))
      (node (ref "U22") (pin "21") (pinfunction "VDD_21") (pintype "passive"))
      (node (ref "U22") (pin "22") (pinfunction "VDD_22") (pintype "passive"))
      (node (ref "U22") (pin "23") (pinfunction "VDD_23") (pintype "passive"))
      (node (ref "U22") (pin "24") (pinfunction "VDD_24") (pintype "passive"))
      (node (ref "U22") (pin "25") (pinfunction "VDD_25") (pintype "passive"))
      (node (ref "U22") (pin "26") (pinfunction "VDD_26") (pintype "passive"))
      (node (ref "U22") (pin "27") (pinfunction "VDD_27") (pintype "passive"))
      (node (ref "U22") (pin "28") (pinfunction "VDD_28") (pintype "passive"))
      (node (ref "U22") (pin "43") (pinfunction "VDD_43") (pintype "passive"))
      (node (ref "U22") (pin "44") (pinfunction "VDD_44") (pintype "passive"))
      (node (ref "U22") (pin "45") (pinfunction "VDD_45") (pintype "passive"))
      (node (ref "U22") (pin "46") (pinfunction "VDD_46") (pintype "passive"))
      (node (ref "U22") (pin "47") (pinfunction "VDD_47") (pintype "passive"))
      (node (ref "U22") (pin "48") (pinfunction "VDD_48") (pintype "passive"))
      (node (ref "U22") (pin "49") (pinfunction "VDD_49") (pintype "passive"))
      (node (ref "U22") (pin "50") (pinfunction "VDD_50") (pintype "passive"))
      (node (ref "U22") (pin "51") (pinfunction "VDD_51") (pintype "passive"))
      (node (ref "U22") (pin "52") (pinfunction "VDD_52") (pintype "passive"))
      (node (ref "U22") (pin "53") (pinfunction "VDD_53") (pintype "passive"))
      (node (ref "U22") (pin "54") (pinfunction "VDD_54") (pintype "passive"))
      (node (ref "U22") (pin "55") (pinfunction "VDD_55") (pintype "passive"))
      (node (ref "U22") (pin "56") (pinfunction "VDD_56") (pintype "passive"))
      (node (ref "U25") (pin "15") (pinfunction "VDD_15") (pintype "passive"))
      (node (ref "U25") (pin "16") (pinfunction "VDD_16") (pintype "passive"))
      (node (ref "U25") (pin "17") (pinfunction "VDD_17") (pintype "passive"))
      (node (ref "U25") (pin "18") (pinfunction "VDD_18") (pintype "passive"))
      (node (ref "U25") (pin "19") (pinfunction "VDD_19") (pintype "passive"))
      (node (ref "U25") (pin "20") (pinfunction "VDD_20") (pintype "passive"))
      (node (ref "U25") (pin "21") (pinfunction "VDD_21") (pintype "passive"))
      (node (ref "U25") (pin "22") (pinfunction "VDD_22") (pintype "passive"))
      (node (ref "U25") (pin "23") (pinfunction "VDD_23") (pintype "passive"))
      (node (ref "U25") (pin "24") (pinfunction "VDD_24") (pintype "passive"))
      (node (ref "U25") (pin "25") (pinfunction "VDD_25") (pintype "passive"))
      (node (ref "U25") (pin "26") (pinfunction "VDD_26") (pintype "passive"))
      (node (ref "U25") (pin "27") (pinfunction "VDD_27") (pintype "passive"))
      (node (ref "U25") (pin "28") (pinfunction "VDD_28") (pintype "passive"))
      (node (ref "U25") (pin "43") (pinfunction "VDD_43") (pintype "passive"))
      (node (ref "U25") (pin "44") (pinfunction "VDD_44") (pintype "passive"))
      (node (ref "U25") (pin "45") (pinfunction "VDD_45") (pintype "passive"))
      (node (ref "U25") (pin "46") (pinfunction "VDD_46") (pintype "passive"))
      (node (ref "U25") (pin "47") (pinfunction "VDD_47") (pintype "passive"))
      (node (ref "U25") (pin "48") (pinfunction "VDD_48") (pintype "passive"))
      (node (ref "U25") (pin "49") (pinfunction "VDD_49") (pintype "passive"))
      (node (ref "U25") (pin "50") (pinfunction "VDD_50") (pintype "passive"))
      (node (ref "U25") (pin "51") (pinfunction "VDD_51") (pintype "passive"))
      (node (ref "U25") (pin "52") (pinfunction "VDD_52") (pintype "passive"))
      (node (ref "U25") (pin "53") (pinfunction "VDD_53") (pintype "passive"))
      (node (ref "U25") (pin "54") (pinfunction "VDD_54") (pintype "passive"))
      (node (ref "U25") (pin "55") (pinfunction "VDD_55") (pintype "passive"))
      (node (ref "U25") (pin "56") (pinfunction "VDD_56") (pintype "passive"))
      (node (ref "U26") (pin "15") (pinfunction "VDD_15") (pintype "passive"))
      (node (ref "U26") (pin "16") (pinfunction "VDD_16") (pintype "passive"))
      (node (ref "U26") (pin "17") (pinfunction "VDD_17") (pintype "passive"))
      (node (ref "U26") (pin "18") (pinfunction "VDD_18") (pintype "passive"))
      (node (ref "U26") (pin "19") (pinfunction "VDD_19") (pintype "passive"))
      (node (ref "U26") (pin "20") (pinfunction "VDD_20") (pintype "passive"))
      (node (ref "U26") (pin "21") (pinfunction "VDD_21") (pintype "passive"))
      (node (ref "U26") (pin "22") (pinfunction "VDD_22") (pintype "passive"))
      (node (ref "U26") (pin "23") (pinfunction "VDD_23") (pintype "passive"))
      (node (ref "U26") (pin "24") (pinfunction "VDD_24") (pintype "passive"))
      (node (ref "U26") (pin "25") (pinfunction "VDD_25") (pintype "passive"))
      (node (ref "U26") (pin "26") (pinfunction "VDD_26") (pintype "passive"))
      (node (ref "U26") (pin "27") (pinfunction "VDD_27") (pintype "passive"))
      (node (ref "U26") (pin "28") (pinfunction "VDD_28") (pintype "passive"))
      (node (ref "U26") (pin "43") (pinfunction "VDD_43") (pintype "passive"))
      (node (ref "U26") (pin "44") (pinfunction "VDD_44") (pintype "passive"))
      (node (ref "U26") (pin "45") (pinfunction "VDD_45") (pintype "passive"))
      (node (ref "U26") (pin "46") (pinfunction "VDD_46") (pintype "passive"))
      (node (ref "U26") (pin "47") (pinfunction "VDD_47") (pintype "passive"))
      (node (ref "U26") (pin "48") (pinfunction "VDD_48") (pintype "passive"))
      (node (ref "U26") (pin "49") (pinfunction "VDD_49") (pintype "passive"))
      (node (ref "U26") (pin "50") (pinfunction "VDD_50") (pintype "passive"))
      (node (ref "U26") (pin "51") (pinfunction "VDD_51") (pintype "passive"))
      (node (ref "U26") (pin "52") (pinfunction "VDD_52") (pintype "passive"))
      (node (ref "U26") (pin "53") (pinfunction "VDD_53") (pintype "passive"))
      (node (ref "U26") (pin "54") (pinfunction "VDD_54") (pintype "passive"))
      (node (ref "U26") (pin "55") (pinfunction "VDD_55") (pintype "passive"))
      (node (ref "U26") (pin "56") (pinfunction "VDD_56") (pintype "passive"))
      (node (ref "U3") (pin "15") (pinfunction "VDD_15") (pintype "passive"))
      (node (ref "U3") (pin "16") (pinfunction "VDD_16") (pintype "passive"))
      (node (ref "U3") (pin "17") (pinfunction "VDD_17") (pintype "passive"))
      (node (ref "U3") (pin "18") (pinfunction "VDD_18") (pintype "passive"))
      (node (ref "U3") (pin "19") (pinfunction "VDD_19") (pintype "passive"))
      (node (ref "U3") (pin "20") (pinfunction "VDD_20") (pintype "passive"))
      (node (ref "U3") (pin "21") (pinfunction "VDD_21") (pintype "passive"))
      (node (ref "U3") (pin "22") (pinfunction "VDD_22") (pintype "passive"))
      (node (ref "U3") (pin "23") (pinfunction "VDD_23") (pintype "passive"))
      (node (ref "U3") (pin "24") (pinfunction "VDD_24") (pintype "passive"))
      (node (ref "U3") (pin "25") (pinfunction "VDD_25") (pintype "passive"))
      (node (ref "U3") (pin "26") (pinfunction "VDD_26") (pintype "passive"))
      (node (ref "U3") (pin "27") (pinfunction "VDD_27") (pintype "passive"))
      (node (ref "U3") (pin "28") (pinfunction "VDD_28") (pintype "passive"))
      (node (ref "U3") (pin "43") (pinfunction "VDD_43") (pintype "passive"))
      (node (ref "U3") (pin "44") (pinfunction "VDD_44") (pintype "passive"))
      (node (ref "U3") (pin "45") (pinfunction "VDD_45") (pintype "passive"))
      (node (ref "U3") (pin "46") (pinfunction "VDD_46") (pintype "passive"))
      (node (ref "U3") (pin "47") (pinfunction "VDD_47") (pintype "passive"))
      (node (ref "U3") (pin "48") (pinfunction "VDD_48") (pintype "passive"))
      (node (ref "U3") (pin "49") (pinfunction "VDD_49") (pintype "passive"))
      (node (ref "U3") (pin "50") (pinfunction "VDD_50") (pintype "passive"))
      (node (ref "U3") (pin "51") (pinfunction "VDD_51") (pintype "passive"))
      (node (ref "U3") (pin "52") (pinfunction "VDD_52") (pintype "passive"))
      (node (ref "U3") (pin "53") (pinfunction "VDD_53") (pintype "passive"))
      (node (ref "U3") (pin "54") (pinfunction "VDD_54") (pintype "passive"))
      (node (ref "U3") (pin "55") (pinfunction "VDD_55") (pintype "passive"))
      (node (ref "U3") (pin "56") (pinfunction "VDD_56") (pintype "passive"))
      (node (ref "U30") (pin "15") (pinfunction "VDD_15") (pintype "passive"))
      (node (ref "U30") (pin "16") (pinfunction "VDD_16") (pintype "passive"))
      (node (ref "U30") (pin "17") (pinfunction "VDD_17") (pintype "passive"))
      (node (ref "U30") (pin "18") (pinfunction "VDD_18") (pintype "passive"))
      (node (ref "U30") (pin "19") (pinfunction "VDD_19") (pintype "passive"))
      (node (ref "U30") (pin "20") (pinfunction "VDD_20") (pintype "passive"))
      (node (ref "U30") (pin "21") (pinfunction "VDD_21") (pintype "passive"))
      (node (ref "U30") (pin "22") (pinfunction "VDD_22") (pintype "passive"))
      (node (ref "U30") (pin "23") (pinfunction "VDD_23") (pintype "passive"))
      (node (ref "U30") (pin "24") (pinfunction "VDD_24") (pintype "passive"))
      (node (ref "U30") (pin "25") (pinfunction "VDD_25") (pintype "passive"))
      (node (ref "U30") (pin "26") (pinfunction "VDD_26") (pintype "passive"))
      (node (ref "U30") (pin "27") (pinfunction "VDD_27") (pintype "passive"))
      (node (ref "U30") (pin "28") (pinfunction "VDD_28") (pintype "passive"))
      (node (ref "U30") (pin "43") (pinfunction "VDD_43") (pintype "passive"))
      (node (ref "U30") (pin "44") (pinfunction "VDD_44") (pintype "passive"))
      (node (ref "U30") (pin "45") (pinfunction "VDD_45") (pintype "passive"))
      (node (ref "U30") (pin "46") (pinfunction "VDD_46") (pintype "passive"))
      (node (ref "U30") (pin "47") (pinfunction "VDD_47") (pintype "passive"))
      (node (ref "U30") (pin "48") (pinfunction "VDD_48") (pintype "passive"))
      (node (ref "U30") (pin "49") (pinfunction "VDD_49") (pintype "passive"))
      (node (ref "U30") (pin "50") (pinfunction "VDD_50") (pintype "passive"))
      (node (ref "U30") (pin "51") (pinfunction "VDD_51") (pintype "passive"))
      (node (ref "U30") (pin "52") (pinfunction "VDD_52") (pintype "passive"))
      (node (ref "U30") (pin "53") (pinfunction "VDD_53") (pintype "passive"))
      (node (ref "U30") (pin "54") (pinfunction "VDD_54") (pintype "passive"))
      (node (ref "U30") (pin "55") (pinfunction "VDD_55") (pintype "passive"))
      (node (ref "U30") (pin "56") (pinfunction "VDD_56") (pintype "passive"))
      (node (ref "U31") (pin "15") (pinfunction "VDD_15") (pintype "passive"))
      (node (ref "U31") (pin "16") (pinfunction "VDD_16") (pintype "passive"))
      (node (ref "U31") (pin "17") (pinfunction "VDD_17") (pintype "passive"))
      (node (ref "U31") (pin "18") (pinfunction "VDD_18") (pintype "passive"))
      (node (ref "U31") (pin "19") (pinfunction "VDD_19") (pintype "passive"))
      (node (ref "U31") (pin "20") (pinfunction "VDD_20") (pintype "passive"))
      (node (ref "U31") (pin "21") (pinfunction "VDD_21") (pintype "passive"))
      (node (ref "U31") (pin "22") (pinfunction "VDD_22") (pintype "passive"))
      (node (ref "U31") (pin "23") (pinfunction "VDD_23") (pintype "passive"))
      (node (ref "U31") (pin "24") (pinfunction "VDD_24") (pintype "passive"))
      (node (ref "U31") (pin "25") (pinfunction "VDD_25") (pintype "passive"))
      (node (ref "U31") (pin "26") (pinfunction "VDD_26") (pintype "passive"))
      (node (ref "U31") (pin "27") (pinfunction "VDD_27") (pintype "passive"))
      (node (ref "U31") (pin "28") (pinfunction "VDD_28") (pintype "passive"))
      (node (ref "U31") (pin "43") (pinfunction "VDD_43") (pintype "passive"))
      (node (ref "U31") (pin "44") (pinfunction "VDD_44") (pintype "passive"))
      (node (ref "U31") (pin "45") (pinfunction "VDD_45") (pintype "passive"))
      (node (ref "U31") (pin "46") (pinfunction "VDD_46") (pintype "passive"))
      (node (ref "U31") (pin "47") (pinfunction "VDD_47") (pintype "passive"))
      (node (ref "U31") (pin "48") (pinfunction "VDD_48") (pintype "passive"))
      (node (ref "U31") (pin "49") (pinfunction "VDD_49") (pintype "passive"))
      (node (ref "U31") (pin "50") (pinfunction "VDD_50") (pintype "passive"))
      (node (ref "U31") (pin "51") (pinfunction "VDD_51") (pintype "passive"))
      (node (ref "U31") (pin "52") (pinfunction "VDD_52") (pintype "passive"))
      (node (ref "U31") (pin "53") (pinfunction "VDD_53") (pintype "passive"))
      (node (ref "U31") (pin "54") (pinfunction "VDD_54") (pintype "passive"))
      (node (ref "U31") (pin "55") (pinfunction "VDD_55") (pintype "passive"))
      (node (ref "U31") (pin "56") (pinfunction "VDD_56") (pintype "passive"))
      (node (ref "U32") (pin "15") (pinfunction "VDD_15") (pintype "passive"))
      (node (ref "U32") (pin "16") (pinfunction "VDD_16") (pintype "passive"))
      (node (ref "U32") (pin "17") (pinfunction "VDD_17") (pintype "passive"))
      (node (ref "U32") (pin "18") (pinfunction "VDD_18") (pintype "passive"))
      (node (ref "U32") (pin "19") (pinfunction "VDD_19") (pintype "passive"))
      (node (ref "U32") (pin "20") (pinfunction "VDD_20") (pintype "passive"))
      (node (ref "U32") (pin "21") (pinfunction "VDD_21") (pintype "passive"))
      (node (ref "U32") (pin "22") (pinfunction "VDD_22") (pintype "passive"))
      (node (ref "U32") (pin "23") (pinfunction "VDD_23") (pintype "passive"))
      (node (ref "U32") (pin "24") (pinfunction "VDD_24") (pintype "passive"))
      (node (ref "U32") (pin "25") (pinfunction "VDD_25") (pintype "passive"))
      (node (ref "U32") (pin "26") (pinfunction "VDD_26") (pintype "passive"))
      (node (ref "U32") (pin "27") (pinfunction "VDD_27") (pintype "passive"))
      (node (ref "U32") (pin "28") (pinfunction "VDD_28") (pintype "passive"))
      (node (ref "U32") (pin "43") (pinfunction "VDD_43") (pintype "passive"))
      (node (ref "U32") (pin "44") (pinfunction "VDD_44") (pintype "passive"))
      (node (ref "U32") (pin "45") (pinfunction "VDD_45") (pintype "passive"))
      (node (ref "U32") (pin "46") (pinfunction "VDD_46") (pintype "passive"))
      (node (ref "U32") (pin "47") (pinfunction "VDD_47") (pintype "passive"))
      (node (ref "U32") (pin "48") (pinfunction "VDD_48") (pintype "passive"))
      (node (ref "U32") (pin "49") (pinfunction "VDD_49") (pintype "passive"))
      (node (ref "U32") (pin "50") (pinfunction "VDD_50") (pintype "passive"))
      (node (ref "U32") (pin "51") (pinfunction "VDD_51") (pintype "passive"))
      (node (ref "U32") (pin "52") (pinfunction "VDD_52") (pintype "passive"))
      (node (ref "U32") (pin "53") (pinfunction "VDD_53") (pintype "passive"))
      (node (ref "U32") (pin "54") (pinfunction "VDD_54") (pintype "passive"))
      (node (ref "U32") (pin "55") (pinfunction "VDD_55") (pintype "passive"))
      (node (ref "U32") (pin "56") (pinfunction "VDD_56") (pintype "passive"))
      (node (ref "U33") (pin "15") (pinfunction "VDD_15") (pintype "passive"))
      (node (ref "U33") (pin "16") (pinfunction "VDD_16") (pintype "passive"))
      (node (ref "U33") (pin "17") (pinfunction "VDD_17") (pintype "passive"))
      (node (ref "U33") (pin "18") (pinfunction "VDD_18") (pintype "passive"))
      (node (ref "U33") (pin "19") (pinfunction "VDD_19") (pintype "passive"))
      (node (ref "U33") (pin "20") (pinfunction "VDD_20") (pintype "passive"))
      (node (ref "U33") (pin "21") (pinfunction "VDD_21") (pintype "passive"))
      (node (ref "U33") (pin "22") (pinfunction "VDD_22") (pintype "passive"))
      (node (ref "U33") (pin "23") (pinfunction "VDD_23") (pintype "passive"))
      (node (ref "U33") (pin "24") (pinfunction "VDD_24") (pintype "passive"))
      (node (ref "U33") (pin "25") (pinfunction "VDD_25") (pintype "passive"))
      (node (ref "U33") (pin "26") (pinfunction "VDD_26") (pintype "passive"))
      (node (ref "U33") (pin "27") (pinfunction "VDD_27") (pintype "passive"))
      (node (ref "U33") (pin "28") (pinfunction "VDD_28") (pintype "passive"))
      (node (ref "U33") (pin "43") (pinfunction "VDD_43") (pintype "passive"))
      (node (ref "U33") (pin "44") (pinfunction "VDD_44") (pintype "passive"))
      (node (ref "U33") (pin "45") (pinfunction "VDD_45") (pintype "passive"))
      (node (ref "U33") (pin "46") (pinfunction "VDD_46") (pintype "passive"))
      (node (ref "U33") (pin "47") (pinfunction "VDD_47") (pintype "passive"))
      (node (ref "U33") (pin "48") (pinfunction "VDD_48") (pintype "passive"))
      (node (ref "U33") (pin "49") (pinfunction "VDD_49") (pintype "passive"))
      (node (ref "U33") (pin "50") (pinfunction "VDD_50") (pintype "passive"))
      (node (ref "U33") (pin "51") (pinfunction "VDD_51") (pintype "passive"))
      (node (ref "U33") (pin "52") (pinfunction "VDD_52") (pintype "passive"))
      (node (ref "U33") (pin "53") (pinfunction "VDD_53") (pintype "passive"))
      (node (ref "U33") (pin "54") (pinfunction "VDD_54") (pintype "passive"))
      (node (ref "U33") (pin "55") (pinfunction "VDD_55") (pintype "passive"))
      (node (ref "U33") (pin "56") (pinfunction "VDD_56") (pintype "passive"))
      (node (ref "U4") (pin "15") (pinfunction "VDD_15") (pintype "passive"))
      (node (ref "U4") (pin "16") (pinfunction "VDD_16") (pintype "passive"))
      (node (ref "U4") (pin "17") (pinfunction "VDD_17") (pintype "passive"))
      (node (ref "U4") (pin "18") (pinfunction "VDD_18") (pintype "passive"))
      (node (ref "U4") (pin "19") (pinfunction "VDD_19") (pintype "passive"))
      (node (ref "U4") (pin "20") (pinfunction "VDD_20") (pintype "passive"))
      (node (ref "U4") (pin "21") (pinfunction "VDD_21") (pintype "passive"))
      (node (ref "U4") (pin "22") (pinfunction "VDD_22") (pintype "passive"))
      (node (ref "U4") (pin "23") (pinfunction "VDD_23") (pintype "passive"))
      (node (ref "U4") (pin "24") (pinfunction "VDD_24") (pintype "passive"))
      (node (ref "U4") (pin "25") (pinfunction "VDD_25") (pintype "passive"))
      (node (ref "U4") (pin "26") (pinfunction "VDD_26") (pintype "passive"))
      (node (ref "U4") (pin "27") (pinfunction "VDD_27") (pintype "passive"))
      (node (ref "U4") (pin "28") (pinfunction "VDD_28") (pintype "passive"))
      (node (ref "U4") (pin "43") (pinfunction "VDD_43") (pintype "passive"))
      (node (ref "U4") (pin "44") (pinfunction "VDD_44") (pintype "passive"))
      (node (ref "U4") (pin "45") (pinfunction "VDD_45") (pintype "passive"))
      (node (ref "U4") (pin "46") (pinfunction "VDD_46") (pintype "passive"))
      (node (ref "U4") (pin "47") (pinfunction "VDD_47") (pintype "passive"))
      (node (ref "U4") (pin "48") (pinfunction "VDD_48") (pintype "passive"))
      (node (ref "U4") (pin "49") (pinfunction "VDD_49") (pintype "passive"))
      (node (ref "U4") (pin "50") (pinfunction "VDD_50") (pintype "passive"))
      (node (ref "U4") (pin "51") (pinfunction "VDD_51") (pintype "passive"))
      (node (ref "U4") (pin "52") (pinfunction "VDD_52") (pintype "passive"))
      (node (ref "U4") (pin "53") (pinfunction "VDD_53") (pintype "passive"))
      (node (ref "U4") (pin "54") (pinfunction "VDD_54") (pintype "passive"))
      (node (ref "U4") (pin "55") (pinfunction "VDD_55") (pintype "passive"))
      (node (ref "U4") (pin "56") (pinfunction "VDD_56") (pintype "passive"))
    )
    (net (code "4") (name "/LOAD") (class "Default")
      (node (ref "TP117") (pin "1") (pinfunction "1_1") (pintype "passive"))
      (node (ref "U1") (pin "5") (pinfunction "LOAD_5") (pintype "passive"))
    )
    (net (code "5") (name "/LOADOUT") (class "Default")
      (node (ref "TP230") (pin "1") (pinfunction "1_1") (pintype "passive"))
      (node (ref "U18") (pin "38") (pinfunction "LOADOUT_38") (pintype "passive"))
      (node (ref "U21") (pin "5") (pinfunction "LOAD_5") (pintype "passive"))
    )
    (net (code "6") (name "/MISO") (class "Default")
      (node (ref "TP134") (pin "1") (pinfunction "1_1") (pintype "passive"))
      (node (ref "U1") (pin "7") (pinfunction "MISO_7") (pintype "passive"))
    )
    (net (code "7") (name "/MISOIN") (class "Default")
      (node (ref "R3") (pin "1") (pinfunction "1_1") (pintype "passive"))
      (node (ref "TP245") (pin "1") (pinfunction "1_1") (pintype "passive"))
      (node (ref "U18") (pin "36") (pinfunction "MISOIN_36") (pintype "passive"))
      (node (ref "U21") (pin "7") (pinfunction "MISO_7") (pintype "passive"))
    )
    (net (code "8") (name "/MOSI") (class "Default")
      (node (ref "TP135") (pin "1") (pinfunction "1_1") (pintype "passive"))
      (node (ref "U1") (pin "8") (pinfunction "MOSI_8") (pintype "passive"))
    )
    (net (code "9") (name "/MOSIOUT") (class "Default")
      (node (ref "R3") (pin "2") (pinfunction "2_2") (pintype "passive"))
      (node (ref "TP246") (pin "1") (pinfunction "1_1") (pintype "passive"))
      (node (ref "U18") (pin "35") (pinfunction "MOSIOUT_35") (pintype "passive"))
      (node (ref "U21") (pin "8") (pinfunction "MOSI_8") (pintype "passive"))
    )
    (net (code "10") (name "/RSTN") (class "Default")
      (node (ref "TP121") (pin "1") (pinfunction "1_1") (pintype "passive"))
      (node (ref "U1") (pin "6") (pinfunction "RSTN_6") (pintype "passive"))
    )
    (net (code "11") (name "/RSTNOUT") (class "Default")
      (node (ref "TP238") (pin "1") (pinfunction "1_1") (pintype "passive"))
      (node (ref "U18") (pin "37") (pinfunction "RSTNOUT_37") (pintype "passive"))
      (node (ref "U21") (pin "6") (pinfunction "RSTN_6") (pintype "passive"))
    )
    (net (code "12") (name "/SCK") (class "Default")
      (node (ref "TP143") (pin "1") (pinfunction "1_1") (pintype "passive"))
      (node (ref "U1") (pin "9") (pinfunction "SCK_9") (pintype "passive"))
    )
    (net (code "13") (name "/SCKOUT") (class "Default")
      (node (ref "TP262") (pin "1") (pinfunction "1_1") (pintype "passive"))
      (node (ref "U18") (pin "34") (pinfunction "SCKOUT_34") (pintype "passive"))
      (node (ref "U21") (pin "9") (pinfunction "SCK_9") (pintype "passive"))
    )
    (net (code "14") (name "/XCLKIN") (class "Default")
      (node (ref "TP151") (pin "1") (pinfunction "1_1") (pintype "passive"))
      (node (ref "U1") (pin "10") (pinfunction "XCLKIN_10") (pintype "passive"))
      (node (ref "YO1") (pin "3") (pinfunction "OSC_3") (pintype "passive"))
      (node (ref "YO2") (pin "3") (pinfunction "OSC_3") (pintype "passive"))
      (node (ref "YO3") (pin "3") (pinfunction "OSC_3") (pintype "passive"))
    )
    (net (code "15") (name "/XCLKOUT") (class "Default")
      (node (ref "TP278") (pin "1") (pinfunction "1_1") (pintype "passive"))
      (node (ref "U18") (pin "33") (pinfunction "XCLKOUT_33") (pintype "passive"))
      (node (ref "U21") (pin "10") (pinfunction "XCLKIN_10") (pintype "passive"))
    )
    (net (code "16") (name "GND") (class "Default")
      (node (ref "C106") (pin "1") (pinfunction "1_1") (pintype "passive"))
      (node (ref "C107") (pin "1") (pinfunction "1_1") (pintype "passive"))
      (node (ref "C108") (pin "1") (pinfunction "1_1") (pintype "passive"))
      (node (ref "C109") (pin "1") (pinfunction "1_1") (pintype "passive"))
      (node (ref "C110") (pin "1") (pinfunction "1_1") (pintype "passive"))
      (node (ref "C111") (pin "1") (pinfunction "1_1") (pintype "passive"))
      (node (ref "C112") (pin "1") (pinfunction "1_1") (pintype "passive"))
      (node (ref "C113") (pin "1") (pinfunction "1_1") (pintype "passive"))
      (node (ref "C114") (pin "1") (pinfunction "1_1") (pintype "passive"))
      (node (ref "C115") (pin "1") (pinfunction "1_1") (pintype "passive"))
      (node (ref "C118") (pin "1") (pinfunction "1_1") (pintype "passive"))
      (node (ref "C119") (pin "1") (pinfunction "1_1") (pintype "passive"))
      (node (ref "C122") (pin "1") (pinfunction "1_1") (pintype "passive"))
      (node (ref "C123") (pin "1") (pinfunction "1_1") (pintype "passive"))
      (node (ref "C126") (pin "1") (pinfunction "1_1") (pintype "passive"))
      (node (ref "C127") (pin "1") (pinfunction "1_1") (pintype "passive"))
      (node (ref "C138") (pin "1") (pinfunction "1_1") (pintype "passive"))
      (node (ref "C139") (pin "1") (pinfunction "1_1") (pintype "passive"))
      (node (ref "C140") (pin "1") (pinfunction "1_1") (pintype "passive"))
      (node (ref "C141") (pin "1") (pinfunction "1_1") (pintype "passive"))
      (node (ref "C142") (pin "1") (pinfunction "1_1") (pintype "passive"))
      (node (ref "C143") (pin "1") (pinfunction "1_1") (pintype "passive"))
      (node (ref "C144") (pin "1") (pinfunction "1_1") (pintype "passive"))
      (node (ref "C145") (pin "1") (pinfunction "1_1") (pintype "passive"))
      (node (ref "C146") (pin "1") (pinfunction "1_1") (pintype "passive"))
      (node (ref "C147") (pin "1") (pinfunction "1_1") (pintype "passive"))
      (node (ref "C148") (pin "1") (pinfunction "1_1") (pintype "passive"))
      (node (ref "C149") (pin "1") (pinfunction "1_1") (pintype "passive"))
      (node (ref "C150") (pin "1") (pinfunction "1_1") (pintype "passive"))
      (node (ref "C151") (pin "1") (pinfunction "1_1") (pintype "passive"))
      (node (ref "C152") (pin "1") (pinfunction "1_1") (pintype "passive"))
      (node (ref "C153") (pin "1") (pinfunction "1_1") (pintype "passive"))
      (node (ref "C154") (pin "1") (pinfunction "1_1") (pintype "passive"))
      (node (ref "C155") (pin "1") (pinfunction "1_1") (pintype "passive"))
      (node (ref "C156") (pin "1") (pinfunction "1_1") (pintype "passive"))
      (node (ref "C157") (pin "1") (pinfunction "1_1") (pintype "passive"))
      (node (ref "C158") (pin "1") (pinfunction "1_1") (pintype "passive"))
      (node (ref "C159") (pin "1") (pinfunction "1_1") (pintype "passive"))
      (node (ref "C160") (pin "1") (pinfunction "1_1") (pintype "passive"))
      (node (ref "C161") (pin "1") (pinfunction "1_1") (pintype "passive"))
      (node (ref "C162") (pin "1") (pinfunction "1_1") (pintype "passive"))
      (node (ref "C163") (pin "1") (pinfunction "1_1") (pintype "passive"))
      (node (ref "C164") (pin "1") (pinfunction "1_1") (pintype "passive"))
      (node (ref "C165") (pin "1") (pinfunction "1_1") (pintype "passive"))
      (node (ref "C166") (pin "1") (pinfunction "1_1") (pintype "passive"))
      (node (ref "C167") (pin "1") (pinfunction "1_1") (pintype "passive"))
      (node (ref "C169") (pin "1") (pinfunction "1_1") (pintype "passive"))
      (node (ref "C170") (pin "1") (pinfunction "1_1") (pintype "passive"))
      (node (ref "C171") (pin "1") (pinfunction "1_1") (pintype "passive"))
      (node (ref "C172") (pin "1") (pinfunction "1_1") (pintype "passive"))
      (node (ref "C173") (pin "1") (pinfunction "1_1") (pintype "passive"))
      (node (ref "C174") (pin "1") (pinfunction "1_1") (pintype "passive"))
      (node (ref "C175") (pin "1") (pinfunction "1_1") (pintype "passive"))
      (node (ref "C176") (pin "1") (pinfunction "1_1") (pintype "passive"))
      (node (ref "C177") (pin "1") (pinfunction "1_1") (pintype "passive"))
      (node (ref "C178") (pin "1") (pinfunction "1_1") (pintype "passive"))
      (node (ref "C179") (pin "1") (pinfunction "1_1") (pintype "passive"))
      (node (ref "C180") (pin "1") (pinfunction "1_1") (pintype "passive"))
      (node (ref "C181") (pin "1") (pinfunction "1_1") (pintype "passive"))
      (node (ref "C182") (pin "1") (pinfunction "1_1") (pintype "passive"))
      (node (ref "C183") (pin "1") (pinfunction "1_1") (pintype "passive"))
      (node (ref "C184") (pin "1") (pinfunction "1_1") (pintype "passive"))
      (node (ref "C185") (pin "1") (pinfunction "1_1") (pintype "passive"))
      (node (ref "C186") (pin "1") (pinfunction "1_1") (pintype "passive"))
      (node (ref "C187") (pin "1") (pinfunction "1_1") (pintype "passive"))
      (node (ref "C188") (pin "1") (pinfunction "1_1") (pintype "passive"))
      (node (ref "C189") (pin "1") (pinfunction "1_1") (pintype "passive"))
      (node (ref "C19") (pin "1") (pinfunction "1_1") (pintype "passive"))
      (node (ref "C190") (pin "1") (pinfunction "1_1") (pintype "passive"))
      (node (ref "C191") (pin "1") (pinfunction "1_1") (pintype "passive"))
      (node (ref "C192") (pin "1") (pinfunction "1_1") (pintype "passive"))
      (node (ref "C193") (pin "1") (pinfunction "1_1") (pintype "passive"))
      (node (ref "C194") (pin "1") (pinfunction "1_1") (pintype "passive"))
      (node (ref "C195") (pin "1") (pinfunction "1_1") (pintype "passive"))
      (node (ref "C196") (pin "1") (pinfunction "1_1") (pintype "passive"))
      (node (ref "C197") (pin "1") (pinfunction "1_1") (pintype "passive"))
      (node (ref "C198") (pin "1") (pinfunction "1_1") (pintype "passive"))
      (node (ref "C199") (pin "1") (pinfunction "1_1") (pintype "passive"))
      (node (ref "C200") (pin "1") (pinfunction "1_1") (pintype "passive"))
      (node (ref "C201") (pin "1") (pinfunction "1_1") (pintype "passive"))
      (node (ref "C202") (pin "1") (pinfunction "1_1") (pintype "passive"))
      (node (ref "C203") (pin "1") (pinfunction "1_1") (pintype "passive"))
      (node (ref "C204") (pin "1") (pinfunction "1_1") (pintype "passive"))
      (node (ref "C205") (pin "1") (pinfunction "1_1") (pintype "passive"))
      (node (ref "C206") (pin "1") (pinfunction "1_1") (pintype "passive"))
      (node (ref "C207") (pin "1") (pinfunction "1_1") (pintype "passive"))
      (node (ref "C208") (pin "1") (pinfunction "1_1") (pintype "passive"))
      (node (ref "C209") (pin "1") (pinfunction "1_1") (pintype "passive"))
      (node (ref "C210") (pin "1") (pinfunction "1_1") (pintype "passive"))
      (node (ref "C211") (pin "1") (pinfunction "1_1") (pintype "passive"))
      (node (ref "C212") (pin "1") (pinfunction "1_1") (pintype "passive"))
      (node (ref "C213") (pin "1") (pinfunction "1_1") (pintype "passive"))
      (node (ref "C214") (pin "1") (pinfunction "1_1") (pintype "passive"))
      (node (ref "C215") (pin "1") (pinfunction "1_1") (pintype "passive"))
      (node (ref "C216") (pin "1") (pinfunction "1_1") (pintype "passive"))
      (node (ref "C217") (pin "1") (pinfunction "1_1") (pintype "passive"))
      (node (ref "C218") (pin "1") (pinfunction "1_1") (pintype "passive"))
      (node (ref "C219") (pin "1") (pinfunction "1_1") (pintype "passive"))
      (node (ref "C22") (pin "1") (pinfunction "1_1") (pintype "passive"))
      (node (ref "C220") (pin "1") (pinfunction "1_1") (pintype "passive"))
      (node (ref "C221") (pin "1") (pinfunction "1_1") (pintype "passive"))
      (node (ref "C222") (pin "1") (pinfunction "1_1") (pintype "passive"))
      (node (ref "C223") (pin "1") (pinfunction "1_1") (pintype "passive"))
      (node (ref "C224") (pin "1") (pinfunction "1_1") (pintype "passive"))
      (node (ref "C225") (pin "1") (pinfunction "1_1") (pintype "passive"))
      (node (ref "C226") (pin "1") (pinfunction "1_1") (pintype "passive"))
      (node (ref "C227") (pin "1") (pinfunction "1_1") (pintype "passive"))
      (node (ref "C228") (pin "1") (pinfunction "1_1") (pintype "passive"))
      (node (ref "C229") (pin "1") (pinfunction "1_1") (pintype "passive"))
      (node (ref "C23") (pin "1") (pinfunction "1_1") (pintype "passive"))
      (node (ref "C230") (pin "1") (pinfunction "1_1") (pintype "passive"))
      (node (ref "C233") (pin "1") (pinfunction "1_1") (pintype "passive"))
      (node (ref "C234") (pin "1") (pinfunction "1_1") (pintype "passive"))
      (node (ref "C235") (pin "1") (pinfunction "1_1") (pintype "passive"))
      (node (ref "C237") (pin "1") (pinfunction "1_1") (pintype "passive"))
      (node (ref "C238") (pin "1") (pinfunction "1_1") (pintype "passive"))
      (node (ref "C239") (pin "1") (pinfunction "1_1") (pintype "passive"))
      (node (ref "C240") (pin "1") (pinfunction "1_1") (pintype "passive"))
      (node (ref "C241") (pin "1") (pinfunction "1_1") (pintype "passive"))
      (node (ref "C242") (pin "1") (pinfunction "1_1") (pintype "passive"))
      (node (ref "C243") (pin "1") (pinfunction "1_1") (pintype "passive"))
      (node (ref "C244") (pin "1") (pinfunction "1_1") (pintype "passive"))
      (node (ref "C245") (pin "1") (pinfunction "1_1") (pintype "passive"))
      (node (ref "C246") (pin "1") (pinfunction "1_1") (pintype "passive"))
      (node (ref "C247") (pin "1") (pinfunction "1_1") (pintype "passive"))
      (node (ref "C248") (pin "1") (pinfunction "1_1") (pintype "passive"))
      (node (ref "C249") (pin "1") (pinfunction "1_1") (pintype "passive"))
      (node (ref "C252") (pin "1") (pinfunction "1_1") (pintype "passive"))
      (node (ref "C253") (pin "1") (pinfunction "1_1") (pintype "passive"))
      (node (ref "C254") (pin "1") (pinfunction "1_1") (pintype "passive"))
      (node (ref "C255") (pin "1") (pinfunction "1_1") (pintype "passive"))
      (node (ref "C256") (pin "1") (pinfunction "1_1") (pintype "passive"))
      (node (ref "C257") (pin "1") (pinfunction "1_1") (pintype "passive"))
      (node (ref "C258") (pin "1") (pinfunction "1_1") (pintype "passive"))
      (node (ref "C259") (pin "1") (pinfunction "1_1") (pintype "passive"))
      (node (ref "C26") (pin "1") (pinfunction "1_1") (pintype "passive"))
      (node (ref "C260") (pin "1") (pinfunction "1_1") (pintype "passive"))
      (node (ref "C261") (pin "1") (pinfunction "1_1") (pintype "passive"))
      (node (ref "C262") (pin "1") (pinfunction "1_1") (pintype "passive"))
      (node (ref "C263") (pin "1") (pinfunction "1_1") (pintype "passive"))
      (node (ref "C264") (pin "1") (pinfunction "1_1") (pintype "passive"))
      (node (ref "C265") (pin "1") (pinfunction "1_1") (pintype "passive"))
      (node (ref "C266") (pin "1") (pinfunction "1_1") (pintype "passive"))
      (node (ref "C267") (pin "1") (pinfunction "1_1") (pintype "passive"))
      (node (ref "C268") (pin "1") (pinfunction "1_1") (pintype "passive"))
      (node (ref "C269") (pin "1") (pinfunction "1_1") (pintype "passive"))
      (node (ref "C27") (pin "1") (pinfunction "1_1") (pintype "passive"))
      (node (ref "C270") (pin "1") (pinfunction "1_1") (pintype "passive"))
      (node (ref "C271") (pin "1") (pinfunction "1_1") (pintype "passive"))
      (node (ref "C272") (pin "1") (pinfunction "1_1") (pintype "passive"))
      (node (ref "C273") (pin "1") (pinfunction "1_1") (pintype "passive"))
      (node (ref "C274") (pin "1") (pinfunction "1_1") (pintype "passive"))
      (node (ref "C275") (pin "1") (pinfunction "1_1") (pintype "passive"))
      (node (ref "C276") (pin "1") (pinfunction "1_1") (pintype "passive"))
      (node (ref "C277") (pin "1") (pinfunction "1_1") (pintype "passive"))
      (node (ref "C278") (pin "1") (pinfunction "1_1") (pintype "passive"))
      (node (ref "C279") (pin "1") (pinfunction "1_1") (pintype "passive"))
      (node (ref "C280") (pin "1") (pinfunction "1_1") (pintype "passive"))
      (node (ref "C281") (pin "1") (pinfunction "1_1") (pintype "passive"))
      (node (ref "C282") (pin "1") (pinfunction "1_1") (pintype "passive"))
      (node (ref "C283") (pin "1") (pinfunction "1_1") (pintype "passive"))
      (node (ref "C284") (pin "1") (pinfunction "1_1") (pintype "passive"))
      (node (ref "C285") (pin "1") (pinfunction "1_1") (pintype "passive"))
      (node (ref "C286") (pin "1") (pinfunction "1_1") (pintype "passive"))
      (node (ref "C287") (pin "1") (pinfunction "1_1") (pintype "passive"))
      (node (ref "C288") (pin "1") (pinfunction "1_1") (pintype "passive"))
      (node (ref "C289") (pin "1") (pinfunction "1_1") (pintype "passive"))
      (node (ref "C290") (pin "1") (pinfunction "1_1") (pintype "passive"))
      (node (ref "C291") (pin "1") (pinfunction "1_1") (pintype "passive"))
      (node (ref "C292") (pin "1") (pinfunction "1_1") (pintype "passive"))
      (node (ref "C293") (pin "1") (pinfunction "1_1") (pintype "passive"))
      (node (ref "C294") (pin "1") (pinfunction "1_1") (pintype "passive"))
      (node (ref "C295") (pin "1") (pinfunction "1_1") (pintype "passive"))
      (node (ref "C296") (pin "1") (pinfunction "1_1") (pintype "passive"))
      (node (ref "C297") (pin "1") (pinfunction "1_1") (pintype "passive"))
      (node (ref "C298") (pin "1") (pinfunction "1_1") (pintype "passive"))
      (node (ref "C299") (pin "1") (pinfunction "1_1") (pintype "passive"))
      (node (ref "C30") (pin "1") (pinfunction "1_1") (pintype "passive"))
      (node (ref "C300") (pin "1") (pinfunction "1_1") (pintype "passive"))
      (node (ref "C301") (pin "1") (pinfunction "1_1") (pintype "passive"))
      (node (ref "C302") (pin "1") (pinfunction "1_1") (pintype "passive"))
      (node (ref "C303") (pin "1") (pinfunction "1_1") (pintype "passive"))
      (node (ref "C304") (pin "1") (pinfunction "1_1") (pintype "passive"))
      (node (ref "C305") (pin "1") (pinfunction "1_1") (pintype "passive"))
      (node (ref "C306") (pin "1") (pinfunction "1_1") (pintype "passive"))
      (node (ref "C307") (pin "1") (pinfunction "1_1") (pintype "passive"))
      (node (ref "C308") (pin "1") (pinfunction "1_1") (pintype "passive"))
      (node (ref "C309") (pin "1") (pinfunction "1_1") (pintype "passive"))
      (node (ref "C31") (pin "1") (pinfunction "1_1") (pintype "passive"))
      (node (ref "C310") (pin "1") (pinfunction "1_1") (pintype "passive"))
      (node (ref "C311") (pin "1") (pinfunction "1_1") (pintype "passive"))
      (node (ref "C312") (pin "1") (pinfunction "1_1") (pintype "passive"))
      (node (ref "C313") (pin "1") (pinfunction "1_1") (pintype "passive"))
      (node (ref "C314") (pin "1") (pinfunction "1_1") (pintype "passive"))
      (node (ref "C315") (pin "1") (pinfunction "1_1") (pintype "passive"))
      (node (ref "C316") (pin "1") (pinfunction "1_1") (pintype "passive"))
      (node (ref "C317") (pin "1") (pinfunction "1_1") (pintype "passive"))
      (node (ref "C318") (pin "1") (pinfunction "1_1") (pintype "passive"))
      (node (ref "C319") (pin "1") (pinfunction "1_1") (pintype "passive"))
      (node (ref "C322") (pin "1") (pinfunction "1_1") (pintype "passive"))
      (node (ref "C36") (pin "1") (pinfunction "1_1") (pintype "passive"))
      (node (ref "C42") (pin "1") (pinfunction "1_1") (pintype "passive"))
      (node (ref "C43") (pin "1") (pinfunction "1_1") (pintype "passive"))
      (node (ref "C44") (pin "1") (pinfunction "1_1") (pintype "passive"))
      (node (ref "C45") (pin "1") (pinfunction "1_1") (pintype "passive"))
      (node (ref "C46") (pin "1") (pinfunction "1_1") (pintype "passive"))
      (node (ref "C47") (pin "1") (pinfunction "1_1") (pintype "passive"))
      (node (ref "C48") (pin "1") (pinfunction "1_1") (pintype "passive"))
      (node (ref "C49") (pin "1") (pinfunction "1_1") (pintype "passive"))
      (node (ref "C492") (pin "1") (pinfunction "1_1") (pintype "passive"))
      (node (ref "C493") (pin "1") (pinfunction "1_1") (pintype "passive"))
      (node (ref "C494") (pin "1") (pinfunction "1_1") (pintype "passive"))
      (node (ref "C495") (pin "1") (pinfunction "1_1") (pintype "passive"))
      (node (ref "C496") (pin "1") (pinfunction "1_1") (pintype "passive"))
      (node (ref "C497") (pin "1") (pinfunction "1_1") (pintype "passive"))
      (node (ref "C498") (pin "1") (pinfunction "1_1") (pintype "passive"))
      (node (ref "C499") (pin "1") (pinfunction "1_1") (pintype "passive"))
      (node (ref "C50") (pin "1") (pinfunction "1_1") (pintype "passive"))
      (node (ref "C500") (pin "1") (pinfunction "1_1") (pintype "passive"))
      (node (ref "C501") (pin "1") (pinfunction "1_1") (pintype "passive"))
      (node (ref "C502") (pin "1") (pinfunction "1_1") (pintype "passive"))
      (node (ref "C503") (pin "1") (pinfunction "1_1") (pintype "passive"))
      (node (ref "C504") (pin "1") (pinfunction "1_1") (pintype "passive"))
      (node (ref "C505") (pin "1") (pinfunction "1_1") (pintype "passive"))
      (node (ref "C506") (pin "1") (pinfunction "1_1") (pintype "passive"))
      (node (ref "C507") (pin "1") (pinfunction "1_1") (pintype "passive"))
      (node (ref "C508") (pin "1") (pinfunction "1_1") (pintype "passive"))
      (node (ref "C509") (pin "1") (pinfunction "1_1") (pintype "passive"))
      (node (ref "C51") (pin "1") (pinfunction "1_1") (pintype "passive"))
      (node (ref "C510") (pin "1") (pinfunction "1_1") (pintype "passive"))
      (node (ref "C511") (pin "1") (pinfunction "1_1") (pintype "passive"))
      (node (ref "C512") (pin "1") (pinfunction "1_1") (pintype "passive"))
      (node (ref "C513") (pin "1") (pinfunction "1_1") (pintype "passive"))
      (node (ref "C514") (pin "1") (pinfunction "1_1") (pintype "passive"))
      (node (ref "C515") (pin "1") (pinfunction "1_1") (pintype "passive"))
      (node (ref "C516") (pin "1") (pinfunction "1_1") (pintype "passive"))
      (node (ref "C517") (pin "1") (pinfunction "1_1") (pintype "passive"))
      (node (ref "C518") (pin "1") (pinfunction "1_1") (pintype "passive"))
      (node (ref "C519") (pin "1") (pinfunction "1_1") (pintype "passive"))
      (node (ref "C520") (pin "1") (pinfunction "1_1") (pintype "passive"))
      (node (ref "C521") (pin "1") (pinfunction "1_1") (pintype "passive"))
      (node (ref "C522") (pin "1") (pinfunction "1_1") (pintype "passive"))
      (node (ref "C523") (pin "1") (pinfunction "1_1") (pintype "passive"))
      (node (ref "C524") (pin "1") (pinfunction "1_1") (pintype "passive"))
      (node (ref "C525") (pin "1") (pinfunction "1_1") (pintype "passive"))
      (node (ref "C526") (pin "1") (pinfunction "1_1") (pintype "passive"))
      (node (ref "C527") (pin "1") (pinfunction "1_1") (pintype "passive"))
      (node (ref "C528") (pin "1") (pinfunction "1_1") (pintype "passive"))
      (node (ref "C529") (pin "1") (pinfunction "1_1") (pintype "passive"))
      (node (ref "C530") (pin "1") (pinfunction "1_1") (pintype "passive"))
      (node (ref "C531") (pin "1") (pinfunction "1_1") (pintype "passive"))
      (node (ref "C532") (pin "1") (pinfunction "1_1") (pintype "passive"))
      (node (ref "C533") (pin "1") (pinfunction "1_1") (pintype "passive"))
      (node (ref "C534") (pin "1") (pinfunction "1_1") (pintype "passive"))
      (node (ref "C535") (pin "1") (pinfunction "1_1") (pintype "passive"))
      (node (ref "C536") (pin "1") (pinfunction "1_1") (pintype "passive"))
      (node (ref "C537") (pin "1") (pinfunction "1_1") (pintype "passive"))
      (node (ref "C538") (pin "1") (pinfunction "1_1") (pintype "passive"))
      (node (ref "C539") (pin "1") (pinfunction "1_1") (pintype "passive"))
      (node (ref "C54") (pin "1") (pinfunction "1_1") (pintype "passive"))
      (node (ref "C540") (pin "1") (pinfunction "1_1") (pintype "passive"))
      (node (ref "C541") (pin "1") (pinfunction "1_1") (pintype "passive"))
      (node (ref "C542") (pin "1") (pinfunction "1_1") (pintype "passive"))
      (node (ref "C543") (pin "1") (pinfunction "1_1") (pintype "passive"))
      (node (ref "C544") (pin "1") (pinfunction "1_1") (pintype "passive"))
      (node (ref "C545") (pin "1") (pinfunction "1_1") (pintype "passive"))
      (node (ref "C546") (pin "1") (pinfunction "1_1") (pintype "passive"))
      (node (ref "C547") (pin "1") (pinfunction "1_1") (pintype "passive"))
      (node (ref "C548") (pin "1") (pinfunction "1_1") (pintype "passive"))
      (node (ref "C549") (pin "1") (pinfunction "1_1") (pintype "passive"))
      (node (ref "C55") (pin "1") (pinfunction "1_1") (pintype "passive"))
      (node (ref "C550") (pin "1") (pinfunction "1_1") (pintype "passive"))
      (node (ref "C551") (pin "1") (pinfunction "1_1") (pintype "passive"))
      (node (ref "C552") (pin "1") (pinfunction "1_1") (pintype "passive"))
      (node (ref "C553") (pin "1") (pinfunction "1_1") (pintype "passive"))
      (node (ref "C554") (pin "1") (pinfunction "1_1") (pintype "passive"))
      (node (ref "C555") (pin "1") (pinfunction "1_1") (pintype "passive"))
      (node (ref "C556") (pin "1") (pinfunction "1_1") (pintype "passive"))
      (node (ref "C557") (pin "1") (pinfunction "1_1") (pintype "passive"))
      (node (ref "C558") (pin "1") (pinfunction "1_1") (pintype "passive"))
      (node (ref "C559") (pin "1") (pinfunction "1_1") (pintype "passive"))
      (node (ref "C560") (pin "1") (pinfunction "1_1") (pintype "passive"))
      (node (ref "C561") (pin "1") (pinfunction "1_1") (pintype "passive"))
      (node (ref "C562") (pin "1") (pinfunction "1_1") (pintype "passive"))
      (node (ref "C563") (pin "1") (pinfunction "1_1") (pintype "passive"))
      (node (ref "C564") (pin "1") (pinfunction "1_1") (pintype "passive"))
      (node (ref "C565") (pin "1") (pinfunction "1_1") (pintype "passive"))
      (node (ref "C566") (pin "1") (pinfunction "1_1") (pintype "passive"))
      (node (ref "C567") (pin "1") (pinfunction "1_1") (pintype "passive"))
      (node (ref "C568") (pin "1") (pinfunction "1_1") (pintype "passive"))
      (node (ref "C569") (pin "1") (pinfunction "1_1") (pintype "passive"))
      (node (ref "C570") (pin "1") (pinfunction "1_1") (pintype "passive"))
      (node (ref "C571") (pin "1") (pinfunction "1_1") (pintype "passive"))
      (node (ref "C572") (pin "1") (pinfunction "1_1") (pintype "passive"))
      (node (ref "C573") (pin "1") (pinfunction "1_1") (pintype "passive"))
      (node (ref "C574") (pin "1") (pinfunction "1_1") (pintype "passive"))
      (node (ref "C575") (pin "1") (pinfunction "1_1") (pintype "passive"))
      (node (ref "C576") (pin "1") (pinfunction "1_1") (pintype "passive"))
      (node (ref "C577") (pin "1") (pinfunction "1_1") (pintype "passive"))
      (node (ref "C578") (pin "1") (pinfunction "1_1") (pintype "passive"))
      (node (ref "C579") (pin "1") (pinfunction "1_1") (pintype "passive"))
      (node (ref "C58") (pin "1") (pinfunction "1_1") (pintype "passive"))
      (node (ref "C580") (pin "1") (pinfunction "1_1") (pintype "passive"))
      (node (ref "C581") (pin "1") (pinfunction "1_1") (pintype "passive"))
      (node (ref "C582") (pin "1") (pinfunction "1_1") (pintype "passive"))
      (node (ref "C583") (pin "1") (pinfunction "1_1") (pintype "passive"))
      (node (ref "C584") (pin "1") (pinfunction "1_1") (pintype "passive"))
      (node (ref "C585") (pin "1") (pinfunction "1_1") (pintype "passive"))
      (node (ref "C586") (pin "1") (pinfunction "1_1") (pintype "passive"))
      (node (ref "C587") (pin "1") (pinfunction "1_1") (pintype "passive"))
      (node (ref "C588") (pin "1") (pinfunction "1_1") (pintype "passive"))
      (node (ref "C589") (pin "1") (pinfunction "1_1") (pintype "passive"))
      (node (ref "C59") (pin "1") (pinfunction "1_1") (pintype "passive"))
      (node (ref "C590") (pin "1") (pinfunction "1_1") (pintype "passive"))
      (node (ref "C591") (pin "1") (pinfunction "1_1") (pintype "passive"))
      (node (ref "C62") (pin "1") (pinfunction "1_1") (pintype "passive"))
      (node (ref "C63") (pin "1") (pinfunction "1_1") (pintype "passive"))
      (node (ref "C74") (pin "1") (pinfunction "1_1") (pintype "passive"))
      (node (ref "C75") (pin "1") (pinfunction "1_1") (pintype "passive"))
      (node (ref "C76") (pin "1") (pinfunction "1_1") (pintype "passive"))
      (node (ref "C77") (pin "1") (pinfunction "1_1") (pintype "passive"))
      (node (ref "C78") (pin "1") (pinfunction "1_1") (pintype "passive"))
      (node (ref "C79") (pin "1") (pinfunction "1_1") (pintype "passive"))
      (node (ref "C80") (pin "1") (pinfunction "1_1") (pintype "passive"))
      (node (ref "C81") (pin "1") (pinfunction "1_1") (pintype "passive"))
      (node (ref "C82") (pin "1") (pinfunction "1_1") (pintype "passive"))
      (node (ref "C83") (pin "1") (pinfunction "1_1") (pintype "passive"))
      (node (ref "C86") (pin "1") (pinfunction "1_1") (pintype "passive"))
      (node (ref "C87") (pin "1") (pinfunction "1_1") (pintype "passive"))
      (node (ref "C90") (pin "1") (pinfunction "1_1") (pintype "passive"))
      (node (ref "C91") (pin "1") (pinfunction "1_1") (pintype "passive"))
      (node (ref "C94") (pin "1") (pinfunction "1_1") (pintype "passive"))
      (node (ref "C95") (pin "1") (pinfunction "1_1") (pintype "passive"))
      (node (ref "U1") (pin "11") (pinfunction "VSS_11") (pintype "passive"))
      (node (ref "U1") (pin "12") (pinfunction "NC_12") (pintype "passive"))
      (node (ref "U1") (pin "13") (pinfunction "NC_13") (pintype "passive"))
      (node (ref "U1") (pin "2") (pinfunction "NC_2") (pintype "passive"))
      (node (ref "U1") (pin "3") (pinfunction "NC_3") (pintype "passive"))
      (node (ref "U1") (pin "30") (pinfunction "TEST_30") (pintype "passive"))
      (node (ref "U1") (pin "31") (pinfunction "NC_31") (pintype "passive"))
      (node (ref "U1") (pin "32") (pinfunction "VSS_32") (pintype "passive"))
      (node (ref "U1") (pin "39") (pinfunction "VSS_39") (pintype "passive"))
      (node (ref "U1") (pin "4") (pinfunction "VSS_4") (pintype "passive"))
      (node (ref "U1") (pin "40") (pinfunction "NC_40") (pintype "passive"))
      (node (ref "U1") (pin "41") (pinfunction "NC_41") (pintype "passive"))
      (node (ref "U1") (pin "57") (pinfunction "EP_57") (pintype "passive"))
      (node (ref "U13") (pin "11") (pinfunction "VSS_11") (pintype "passive"))
      (node (ref "U13") (pin "12") (pinfunction "NC_12") (pintype "passive"))
      (node (ref "U13") (pin "13") (pinfunction "NC_13") (pintype "passive"))
      (node (ref "U13") (pin "2") (pinfunction "NC_2") (pintype "passive"))
      (node (ref "U13") (pin "3") (pinfunction "NC_3") (pintype "passive"))
      (node (ref "U13") (pin "30") (pinfunction "TEST_30") (pintype "passive"))
      (node (ref "U13") (pin "31") (pinfunction "NC_31") (pintype "passive"))
      (node (ref "U13") (pin "32") (pinfunction "VSS_32") (pintype "passive"))
      (node (ref "U13") (pin "39") (pinfunction "VSS_39") (pintype "passive"))
      (node (ref "U13") (pin "4") (pinfunction "VSS_4") (pintype "passive"))
      (node (ref "U13") (pin "40") (pinfunction "NC_40") (pintype "passive"))
      (node (ref "U13") (pin "41") (pinfunction "NC_41") (pintype "passive"))
      (node (ref "U13") (pin "57") (pinfunction "EP_57") (pintype "passive"))
      (node (ref "U14") (pin "11") (pinfunction "VSS_11") (pintype "passive"))
      (node (ref "U14") (pin "12") (pinfunction "NC_12") (pintype "passive"))
      (node (ref "U14") (pin "13") (pinfunction "NC_13") (pintype "passive"))
      (node (ref "U14") (pin "2") (pinfunction "NC_2") (pintype "passive"))
      (node (ref "U14") (pin "3") (pinfunction "NC_3") (pintype "passive"))
      (node (ref "U14") (pin "30") (pinfunction "TEST_30") (pintype "passive"))
      (node (ref "U14") (pin "31") (pinfunction "NC_31") (pintype "passive"))
      (node (ref "U14") (pin "32") (pinfunction "VSS_32") (pintype "passive"))
      (node (ref "U14") (pin "39") (pinfunction "VSS_39") (pintype "passive"))
      (node (ref "U14") (pin "4") (pinfunction "VSS_4") (pintype "passive"))
      (node (ref "U14") (pin "40") (pinfunction "NC_40") (pintype "passive"))
      (node (ref "U14") (pin "41") (pinfunction "NC_41") (pintype "passive"))
      (node (ref "U14") (pin "57") (pinfunction "EP_57") (pintype "passive"))
      (node (ref "U17") (pin "11") (pinfunction "VSS_11") (pintype "passive"))
      (node (ref "U17") (pin "12") (pinfunction "NC_12") (pintype "passive"))
      (node (ref "U17") (pin "13") (pinfunction "NC_13") (pintype "passive"))
      (node (ref "U17") (pin "2") (pinfunction "NC_2") (pintype "passive"))
      (node (ref "U17") (pin "3") (pinfunction "NC_3") (pintype "passive"))
      (node (ref "U17") (pin "30") (pinfunction "TEST_30") (pintype "passive"))
      (node (ref "U17") (pin "31") (pinfunction "NC_31") (pintype "passive"))
      (node (ref "U17") (pin "32") (pinfunction "VSS_32") (pintype "passive"))
      (node (ref "U17") (pin "39") (pinfunction "VSS_39") (pintype "passive"))
      (node (ref "U17") (pin "4") (pinfunction "VSS_4") (pintype "passive"))
      (node (ref "U17") (pin "40") (pinfunction "NC_40") (pintype "passive"))
      (node (ref "U17") (pin "41") (pinfunction "NC_41") (pintype "passive"))
      (node (ref "U17") (pin "57") (pinfunction "EP_57") (pintype "passive"))
      (node (ref "U18") (pin "11") (pinfunction "VSS_11") (pintype "passive"))
      (node (ref "U18") (pin "12") (pinfunction "NC_12") (pintype "passive"))
      (node (ref "U18") (pin "13") (pinfunction "NC_13") (pintype "passive"))
      (node (ref "U18") (pin "2") (pinfunction "NC_2") (pintype "passive"))
      (node (ref "U18") (pin "3") (pinfunction "NC_3") (pintype "passive"))
      (node (ref "U18") (pin "30") (pinfunction "TEST_30") (pintype "passive"))
      (node (ref "U18") (pin "31") (pinfunction "NC_31") (pintype "passive"))
      (node (ref "U18") (pin "32") (pinfunction "VSS_32") (pintype "passive"))
      (node (ref "U18") (pin "39") (pinfunction "VSS_39") (pintype "passive"))
      (node (ref "U18") (pin "4") (pinfunction "VSS_4") (pintype "passive"))
      (node (ref "U18") (pin "40") (pinfunction "NC_40") (pintype "passive"))
      (node (ref "U18") (pin "41") (pinfunction "NC_41") (pintype "passive"))
      (node (ref "U18") (pin "57") (pinfunction "EP_57") (pintype "passive"))
      (node (ref "U2") (pin "11") (pinfunction "VSS_11") (pintype "passive"))
      (node (ref "U2") (pin "12") (pinfunction "NC_12") (pintype "passive"))
      (node (ref "U2") (pin "13") (pinfunction "NC_13") (pintype "passive"))
      (node (ref "U2") (pin "2") (pinfunction "NC_2") (pintype "passive"))
      (node (ref "U2") (pin "3") (pinfunction "NC_3") (pintype "passive"))
      (node (ref "U2") (pin "30") (pinfunction "TEST_30") (pintype "passive"))
      (node (ref "U2") (pin "31") (pinfunction "NC_31") (pintype "passive"))
      (node (ref "U2") (pin "32") (pinfunction "VSS_32") (pintype "passive"))
      (node (ref "U2") (pin "39") (pinfunction "VSS_39") (pintype "passive"))
      (node (ref "U2") (pin "4") (pinfunction "VSS_4") (pintype "passive"))
      (node (ref "U2") (pin "40") (pinfunction "NC_40") (pintype "passive"))
      (node (ref "U2") (pin "41") (pinfunction "NC_41") (pintype "passive"))
      (node (ref "U2") (pin "57") (pinfunction "EP_57") (pintype "passive"))
      (node (ref "U21") (pin "11") (pinfunction "VSS_11") (pintype "passive"))
      (node (ref "U21") (pin "12") (pinfunction "NC_12") (pintype "passive"))
      (node (ref "U21") (pin "13") (pinfunction "NC_13") (pintype "passive"))
      (node (ref "U21") (pin "2") (pinfunction "NC_2") (pintype "passive"))
      (node (ref "U21") (pin "3") (pinfunction "NC_3") (pintype "passive"))
      (node (ref "U21") (pin "30") (pinfunction "TEST_30") (pintype "passive"))
      (node (ref "U21") (pin "31") (pinfunction "NC_31") (pintype "passive"))
      (node (ref "U21") (pin "32") (pinfunction "VSS_32") (pintype "passive"))
      (node (ref "U21") (pin "39") (pinfunction "VSS_39") (pintype "passive"))
      (node (ref "U21") (pin "4") (pinfunction "VSS_4") (pintype "passive"))
      (node (ref "U21") (pin "40") (pinfunction "NC_40") (pintype "passive"))
      (node (ref "U21") (pin "41") (pinfunction "NC_41") (pintype "passive"))
      (node (ref "U21") (pin "57") (pinfunction "EP_57") (pintype "passive"))
      (node (ref "U22") (pin "11") (pinfunction "VSS_11") (pintype "passive"))
      (node (ref "U22") (pin "12") (pinfunction "NC_12") (pintype "passive"))
      (node (ref "U22") (pin "13") (pinfunction "NC_13") (pintype "passive"))
      (node (ref "U22") (pin "2") (pinfunction "NC_2") (pintype "passive"))
      (node (ref "U22") (pin "3") (pinfunction "NC_3") (pintype "passive"))
      (node (ref "U22") (pin "30") (pinfunction "TEST_30") (pintype "passive"))
      (node (ref "U22") (pin "31") (pinfunction "NC_31") (pintype "passive"))
      (node (ref "U22") (pin "32") (pinfunction "VSS_32") (pintype "passive"))
      (node (ref "U22") (pin "39") (pinfunction "VSS_39") (pintype "passive"))
      (node (ref "U22") (pin "4") (pinfunction "VSS_4") (pintype "passive"))
      (node (ref "U22") (pin "40") (pinfunction "NC_40") (pintype "passive"))
      (node (ref "U22") (pin "41") (pinfunction "NC_41") (pintype "passive"))
      (node (ref "U22") (pin "57") (pinfunction "EP_57") (pintype "passive"))
      (node (ref "U25") (pin "11") (pinfunction "VSS_11") (pintype "passive"))
      (node (ref "U25") (pin "12") (pinfunction "NC_12") (pintype "passive"))
      (node (ref "U25") (pin "13") (pinfunction "NC_13") (pintype "passive"))
      (node (ref "U25") (pin "2") (pinfunction "NC_2") (pintype "passive"))
      (node (ref "U25") (pin "3") (pinfunction "NC_3") (pintype "passive"))
      (node (ref "U25") (pin "30") (pinfunction "TEST_30") (pintype "passive"))
      (node (ref "U25") (pin "31") (pinfunction "NC_31") (pintype "passive"))
      (node (ref "U25") (pin "32") (pinfunction "VSS_32") (pintype "passive"))
      (node (ref "U25") (pin "39") (pinfunction "VSS_39") (pintype "passive"))
      (node (ref "U25") (pin "4") (pinfunction "VSS_4") (pintype "passive"))
      (node (ref "U25") (pin "40") (pinfunction "NC_40") (pintype "passive"))
      (node (ref "U25") (pin "41") (pinfunction "NC_41") (pintype "passive"))
      (node (ref "U25") (pin "57") (pinfunction "EP_57") (pintype "passive"))
      (node (ref "U26") (pin "11") (pinfunction "VSS_11") (pintype "passive"))
      (node (ref "U26") (pin "12") (pinfunction "NC_12") (pintype "passive"))
      (node (ref "U26") (pin "13") (pinfunction "NC_13") (pintype "passive"))
      (node (ref "U26") (pin "2") (pinfunction "NC_2") (pintype "passive"))
      (node (ref "U26") (pin "3") (pinfunction "NC_3") (pintype "passive"))
      (node (ref "U26") (pin "30") (pinfunction "TEST_30") (pintype "passive"))
      (node (ref "U26") (pin "31") (pinfunction "NC_31") (pintype "passive"))
      (node (ref "U26") (pin "32") (pinfunction "VSS_32") (pintype "passive"))
      (node (ref "U26") (pin "39") (pinfunction "VSS_39") (pintype "passive"))
      (node (ref "U26") (pin "4") (pinfunction "VSS_4") (pintype "passive"))
      (node (ref "U26") (pin "40") (pinfunction "NC_40") (pintype "passive"))
      (node (ref "U26") (pin "41") (pinfunction "NC_41") (pintype "passive"))
      (node (ref "U26") (pin "57") (pinfunction "EP_57") (pintype "passive"))
      (node (ref "U3") (pin "11") (pinfunction "VSS_11") (pintype "passive"))
      (node (ref "U3") (pin "12") (pinfunction "NC_12") (pintype "passive"))
      (node (ref "U3") (pin "13") (pinfunction "NC_13") (pintype "passive"))
      (node (ref "U3") (pin "2") (pinfunction "NC_2") (pintype "passive"))
      (node (ref "U3") (pin "3") (pinfunction "NC_3") (pintype "passive"))
      (node (ref "U3") (pin "30") (pinfunction "TEST_30") (pintype "passive"))
      (node (ref "U3") (pin "31") (pinfunction "NC_31") (pintype "passive"))
      (node (ref "U3") (pin "32") (pinfunction "VSS_32") (pintype "passive"))
      (node (ref "U3") (pin "39") (pinfunction "VSS_39") (pintype "passive"))
      (node (ref "U3") (pin "4") (pinfunction "VSS_4") (pintype "passive"))
      (node (ref "U3") (pin "40") (pinfunction "NC_40") (pintype "passive"))
      (node (ref "U3") (pin "41") (pinfunction "NC_41") (pintype "passive"))
      (node (ref "U3") (pin "57") (pinfunction "EP_57") (pintype "passive"))
      (node (ref "U30") (pin "11") (pinfunction "VSS_11") (pintype "passive"))
      (node (ref "U30") (pin "12") (pinfunction "NC_12") (pintype "passive"))
      (node (ref "U30") (pin "13") (pinfunction "NC_13") (pintype "passive"))
      (node (ref "U30") (pin "2") (pinfunction "NC_2") (pintype "passive"))
      (node (ref "U30") (pin "3") (pinfunction "NC_3") (pintype "passive"))
      (node (ref "U30") (pin "30") (pinfunction "TEST_30") (pintype "passive"))
      (node (ref "U30") (pin "31") (pinfunction "NC_31") (pintype "passive"))
      (node (ref "U30") (pin "32") (pinfunction "VSS_32") (pintype "passive"))
      (node (ref "U30") (pin "39") (pinfunction "VSS_39") (pintype "passive"))
      (node (ref "U30") (pin "4") (pinfunction "VSS_4") (pintype "passive"))
      (node (ref "U30") (pin "40") (pinfunction "NC_40") (pintype "passive"))
      (node (ref "U30") (pin "41") (pinfunction "NC_41") (pintype "passive"))
      (node (ref "U30") (pin "57") (pinfunction "EP_57") (pintype "passive"))
      (node (ref "U31") (pin "11") (pinfunction "VSS_11") (pintype "passive"))
      (node (ref "U31") (pin "12") (pinfunction "NC_12") (pintype "passive"))
      (node (ref "U31") (pin "13") (pinfunction "NC_13") (pintype "passive"))
      (node (ref "U31") (pin "2") (pinfunction "NC_2") (pintype "passive"))
      (node (ref "U31") (pin "3") (pinfunction "NC_3") (pintype "passive"))
      (node (ref "U31") (pin "30") (pinfunction "TEST_30") (pintype "passive"))
      (node (ref "U31") (pin "31") (pinfunction "NC_31") (pintype "passive"))
      (node (ref "U31") (pin "32") (pinfunction "VSS_32") (pintype "passive"))
      (node (ref "U31") (pin "39") (pinfunction "VSS_39") (pintype "passive"))
      (node (ref "U31") (pin "4") (pinfunction "VSS_4") (pintype "passive"))
      (node (ref "U31") (pin "40") (pinfunction "NC_40") (pintype "passive"))
      (node (ref "U31") (pin "41") (pinfunction "NC_41") (pintype "passive"))
      (node (ref "U31") (pin "57") (pinfunction "EP_57") (pintype "passive"))
      (node (ref "U32") (pin "11") (pinfunction "VSS_11") (pintype "passive"))
      (node (ref "U32") (pin "12") (pinfunction "NC_12") (pintype "passive"))
      (node (ref "U32") (pin "13") (pinfunction "NC_13") (pintype "passive"))
      (node (ref "U32") (pin "2") (pinfunction "NC_2") (pintype "passive"))
      (node (ref "U32") (pin "3") (pinfunction "NC_3") (pintype "passive"))
      (node (ref "U32") (pin "30") (pinfunction "TEST_30") (pintype "passive"))
      (node (ref "U32") (pin "31") (pinfunction "NC_31") (pintype "passive"))
      (node (ref "U32") (pin "32") (pinfunction "VSS_32") (pintype "passive"))
      (node (ref "U32") (pin "39") (pinfunction "VSS_39") (pintype "passive"))
      (node (ref "U32") (pin "4") (pinfunction "VSS_4") (pintype "passive"))
      (node (ref "U32") (pin "40") (pinfunction "NC_40") (pintype "passive"))
      (node (ref "U32") (pin "41") (pinfunction "NC_41") (pintype "passive"))
      (node (ref "U32") (pin "57") (pinfunction "EP_57") (pintype "passive"))
      (node (ref "U33") (pin "11") (pinfunction "VSS_11") (pintype "passive"))
      (node (ref "U33") (pin "12") (pinfunction "NC_12") (pintype "passive"))
      (node (ref "U33") (pin "13") (pinfunction "NC_13") (pintype "passive"))
      (node (ref "U33") (pin "2") (pinfunction "NC_2") (pintype "passive"))
      (node (ref "U33") (pin "3") (pinfunction "NC_3") (pintype "passive"))
      (node (ref "U33") (pin "30") (pinfunction "TEST_30") (pintype "passive"))
      (node (ref "U33") (pin "31") (pinfunction "NC_31") (pintype "passive"))
      (node (ref "U33") (pin "32") (pinfunction "VSS_32") (pintype "passive"))
      (node (ref "U33") (pin "39") (pinfunction "VSS_39") (pintype "passive"))
      (node (ref "U33") (pin "4") (pinfunction "VSS_4") (pintype "passive"))
      (node (ref "U33") (pin "40") (pinfunction "NC_40") (pintype "passive"))
      (node (ref "U33") (pin "41") (pinfunction "NC_41") (pintype "passive"))
      (node (ref "U33") (pin "57") (pinfunction "EP_57") (pintype "passive"))
      (node (ref "U4") (pin "11") (pinfunction "VSS_11") (pintype "passive"))
      (node (ref "U4") (pin "12") (pinfunction "NC_12") (pintype "passive"))
      (node (ref "U4") (pin "13") (pinfunction "NC_13") (pintype "passive"))
      (node (ref "U4") (pin "2") (pinfunction "NC_2") (pintype "passive"))
      (node (ref "U4") (pin "3") (pinfunction "NC_3") (pintype "passive"))
      (node (ref "U4") (pin "30") (pinfunction "TEST_30") (pintype "passive"))
      (node (ref "U4") (pin "31") (pinfunction "NC_31") (pintype "passive"))
      (node (ref "U4") (pin "32") (pinfunction "VSS_32") (pintype "passive"))
      (node (ref "U4") (pin "39") (pinfunction "VSS_39") (pintype "passive"))
      (node (ref "U4") (pin "4") (pinfunction "VSS_4") (pintype "passive"))
      (node (ref "U4") (pin "40") (pinfunction "NC_40") (pintype "passive"))
      (node (ref "U4") (pin "41") (pinfunction "NC_41") (pintype "passive"))
      (node (ref "U4") (pin "57") (pinfunction "EP_57") (pintype "passive"))
      (node (ref "YO1") (pin "2") (pinfunction "GND_2") (pintype "passive"))
      (node (ref "YO2") (pin "2") (pinfunction "GND_2") (pintype "passive"))
      (node (ref "YO3") (pin "2") (pinfunction "GND_2") (pintype "passive"))
    )
    (net (code "17") (name "Net-(U1-LOADOUT)") (class "Default")
      (node (ref "TP15") (pin "1") (pinfunction "1_1") (pintype "passive"))
      (node (ref "U1") (pin "38") (pinfunction "LOADOUT_38") (pintype "passive"))
      (node (ref "U2") (pin "5") (pinfunction "LOAD_5") (pintype "passive"))
    )
    (net (code "18") (name "Net-(U1-MISOIN)") (class "Default")
      (node (ref "TP17") (pin "1") (pinfunction "1_1") (pintype "passive"))
      (node (ref "U1") (pin "36") (pinfunction "MISOIN_36") (pintype "passive"))
      (node (ref "U2") (pin "7") (pinfunction "MISO_7") (pintype "passive"))
    )
    (net (code "19") (name "Net-(U1-MOSIOUT)") (class "Default")
      (node (ref "TP26") (pin "1") (pinfunction "1_1") (pintype "passive"))
      (node (ref "U1") (pin "35") (pinfunction "MOSIOUT_35") (pintype "passive"))
      (node (ref "U2") (pin "8") (pinfunction "MOSI_8") (pintype "passive"))
    )
    (net (code "20") (name "Net-(U1-RSTNOUT)") (class "Default")
      (node (ref "TP16") (pin "1") (pinfunction "1_1") (pintype "passive"))
      (node (ref "U1") (pin "37") (pinfunction "RSTNOUT_37") (pintype "passive"))
      (node (ref "U2") (pin "6") (pinfunction "RSTN_6") (pintype "passive"))
    )
    (net (code "21") (name "Net-(U1-SCKOUT)") (class "Default")
      (node (ref "TP27") (pin "1") (pinfunction "1_1") (pintype "passive"))
      (node (ref "U1") (pin "34") (pinfunction "SCKOUT_34") (pintype "passive"))
      (node (ref "U2") (pin "9") (pinfunction "SCK_9") (pintype "passive"))
    )
    (net (code "22") (name "Net-(U1-XCLKOUT)") (class "Default")
      (node (ref "TP153") (pin "1") (pinfunction "1_1") (pintype "passive"))
      (node (ref "U1") (pin "33") (pinfunction "XCLKOUT_33") (pintype "passive"))
      (node (ref "U2") (pin "10") (pinfunction "XCLKIN_10") (pintype "passive"))
    )
    (net (code "23") (name "Net-(U2-LOADOUT)") (class "Default")
      (node (ref "TP39") (pin "1") (pinfunction "1_1") (pintype "passive"))
      (node (ref "U2") (pin "38") (pinfunction "LOADOUT_38") (pintype "passive"))
      (node (ref "U3") (pin "5") (pinfunction "LOAD_5") (pintype "passive"))
    )
    (net (code "24") (name "Net-(U2-MISOIN)") (class "Default")
      (node (ref "TP41") (pin "1") (pinfunction "1_1") (pintype "passive"))
      (node (ref "U2") (pin "36") (pinfunction "MISOIN_36") (pintype "passive"))
      (node (ref "U3") (pin "7") (pinfunction "MISO_7") (pintype "passive"))
    )
    (net (code "25") (name "Net-(U2-MOSIOUT)") (class "Default")
      (node (ref "TP42") (pin "1") (pinfunction "1_1") (pintype "passive"))
      (node (ref "U2") (pin "35") (pinfunction "MOSIOUT_35") (pintype "passive"))
      (node (ref "U3") (pin "8") (pinfunction "MOSI_8") (pintype "passive"))
    )
    (net (code "26") (name "Net-(U2-RSTNOUT)") (class "Default")
      (node (ref "TP40") (pin "1") (pinfunction "1_1") (pintype "passive"))
      (node (ref "U2") (pin "37") (pinfunction "RSTNOUT_37") (pintype "passive"))
      (node (ref "U3") (pin "6") (pinfunction "RSTN_6") (pintype "passive"))
    )
    (net (code "27") (name "Net-(U2-SCKOUT)") (class "Default")
      (node (ref "TP43") (pin "1") (pinfunction "1_1") (pintype "passive"))
      (node (ref "U2") (pin "34") (pinfunction "SCKOUT_34") (pintype "passive"))
      (node (ref "U3") (pin "9") (pinfunction "SCK_9") (pintype "passive"))
    )
    (net (code "28") (name "Net-(U2-XCLKOUT)") (class "Default")
      (node (ref "TP44") (pin "1") (pinfunction "1_1") (pintype "passive"))
      (node (ref "U2") (pin "33") (pinfunction "XCLKOUT_33") (pintype "passive"))
      (node (ref "U3") (pin "10") (pinfunction "XCLKIN_10") (pintype "passive"))
    )
    (net (code "29") (name "Net-(U3-LOADOUT)") (class "Default")
      (node (ref "TP56") (pin "1") (pinfunction "1_1") (pintype "passive"))
      (node (ref "U3") (pin "38") (pinfunction "LOADOUT_38") (pintype "passive"))
      (node (ref "U4") (pin "5") (pinfunction "LOAD_5") (pintype "passive"))
    )
    (net (code "30") (name "Net-(U3-MISOIN)") (class "Default")
      (node (ref "TP58") (pin "1") (pinfunction "1_1") (pintype "passive"))
      (node (ref "U3") (pin "36") (pinfunction "MISOIN_36") (pintype "passive"))
      (node (ref "U4") (pin "7") (pinfunction "MISO_7") (pintype "passive"))
    )
    (net (code "31") (name "Net-(U3-MOSIOUT)") (class "Default")
      (node (ref "TP59") (pin "1") (pinfunction "1_1") (pintype "passive"))
      (node (ref "U3") (pin "35") (pinfunction "MOSIOUT_35") (pintype "passive"))
      (node (ref "U4") (pin "8") (pinfunction "MOSI_8") (pintype "passive"))
    )
    (net (code "32") (name "Net-(U3-RSTNOUT)") (class "Default")
      (node (ref "TP57") (pin "1") (pinfunction "1_1") (pintype "passive"))
      (node (ref "U3") (pin "37") (pinfunction "RSTNOUT_37") (pintype "passive"))
      (node (ref "U4") (pin "6") (pinfunction "RSTN_6") (pintype "passive"))
    )
    (net (code "33") (name "Net-(U3-SCKOUT)") (class "Default")
      (node (ref "TP60") (pin "1") (pinfunction "1_1") (pintype "passive"))
      (node (ref "U3") (pin "34") (pinfunction "SCKOUT_34") (pintype "passive"))
      (node (ref "U4") (pin "9") (pinfunction "SCK_9") (pintype "passive"))
    )
    (net (code "34") (name "Net-(U3-XCLKOUT)") (class "Default")
      (node (ref "TP61") (pin "1") (pinfunction "1_1") (pintype "passive"))
      (node (ref "U3") (pin "33") (pinfunction "XCLKOUT_33") (pintype "passive"))
      (node (ref "U4") (pin "10") (pinfunction "XCLKIN_10") (pintype "passive"))
    )
    (net (code "35") (name "Net-(U13-LOAD)") (class "Default")
      (node (ref "TP73") (pin "1") (pinfunction "1_1") (pintype "passive"))
      (node (ref "U13") (pin "5") (pinfunction "LOAD_5") (pintype "passive"))
      (node (ref "U4") (pin "38") (pinfunction "LOADOUT_38") (pintype "passive"))
    )
    (net (code "36") (name "Net-(U13-LOADOUT)") (class "Default")
      (node (ref "TP105") (pin "1") (pinfunction "1_1") (pintype "passive"))
      (node (ref "U13") (pin "38") (pinfunction "LOADOUT_38") (pintype "passive"))
      (node (ref "U14") (pin "5") (pinfunction "LOAD_5") (pintype "passive"))
    )
    (net (code "37") (name "Net-(U13-MISO)") (class "Default")
      (node (ref "TP75") (pin "1") (pinfunction "1_1") (pintype "passive"))
      (node (ref "U13") (pin "7") (pinfunction "MISO_7") (pintype "passive"))
      (node (ref "U4") (pin "36") (pinfunction "MISOIN_36") (pintype "passive"))
    )
    (net (code "38") (name "Net-(U13-MISOIN)") (class "Default")
      (node (ref "TP111") (pin "1") (pinfunction "1_1") (pintype "passive"))
      (node (ref "U13") (pin "36") (pinfunction "MISOIN_36") (pintype "passive"))
      (node (ref "U14") (pin "7") (pinfunction "MISO_7") (pintype "passive"))
    )
    (net (code "39") (name "Net-(U13-MOSI)") (class "Default")
      (node (ref "TP76") (pin "1") (pinfunction "1_1") (pintype "passive"))
      (node (ref "U13") (pin "8") (pinfunction "MOSI_8") (pintype "passive"))
      (node (ref "U4") (pin "35") (pinfunction "MOSIOUT_35") (pintype "passive"))
    )
    (net (code "40") (name "Net-(U13-MOSIOUT)") (class "Default")
      (node (ref "TP114") (pin "1") (pinfunction "1_1") (pintype "passive"))
      (node (ref "U13") (pin "35") (pinfunction "MOSIOUT_35") (pintype "passive"))
      (node (ref "U14") (pin "8") (pinfunction "MOSI_8") (pintype "passive"))
    )
    (net (code "41") (name "Net-(U13-RSTN)") (class "Default")
      (node (ref "TP74") (pin "1") (pinfunction "1_1") (pintype "passive"))
      (node (ref "U13") (pin "6") (pinfunction "RSTN_6") (pintype "passive"))
      (node (ref "U4") (pin "37") (pinfunction "RSTNOUT_37") (pintype "passive"))
    )
    (net (code "42") (name "Net-(U13-RSTNOUT)") (class "Default")
      (node (ref "TP108") (pin "1") (pinfunction "1_1") (pintype "passive"))
      (node (ref "U13") (pin "37") (pinfunction "RSTNOUT_37") (pintype "passive"))
      (node (ref "U14") (pin "6") (pinfunction "RSTN_6") (pintype "passive"))
    )
    (net (code "43") (name "Net-(U13-SCK)") (class "Default")
      (node (ref "TP77") (pin "1") (pinfunction "1_1") (pintype "passive"))
      (node (ref "U13") (pin "9") (pinfunction "SCK_9") (pintype "passive"))
      (node (ref "U4") (pin "34") (pinfunction "SCKOUT_34") (pintype "passive"))
    )
    (net (code "44") (name "Net-(U13-SCKOUT)") (class "Default")
      (node (ref "TP118") (pin "1") (pinfunction "1_1") (pintype "passive"))
      (node (ref "U13") (pin "34") (pinfunction "SCKOUT_34") (pintype "passive"))
      (node (ref "U14") (pin "9") (pinfunction "SCK_9") (pintype "passive"))
    )
    (net (code "45") (name "Net-(U13-XCLKIN)") (class "Default")
      (node (ref "TP78") (pin "1") (pinfunction "1_1") (pintype "passive"))
      (node (ref "U13") (pin "10") (pinfunction "XCLKIN_10") (pintype "passive"))
      (node (ref "U4") (pin "33") (pinfunction "XCLKOUT_33") (pintype "passive"))
    )
    (net (code "46") (name "Net-(U13-XCLKOUT)") (class "Default")
      (node (ref "TP122") (pin "1") (pinfunction "1_1") (pintype "passive"))
      (node (ref "U13") (pin "33") (pinfunction "XCLKOUT_33") (pintype "passive"))
      (node (ref "U14") (pin "10") (pinfunction "XCLKIN_10") (pintype "passive"))
    )
    (net (code "47") (name "Net-(U14-LOADOUT)") (class "Default")
      (node (ref "TP106") (pin "1") (pinfunction "1_1") (pintype "passive"))
      (node (ref "U14") (pin "38") (pinfunction "LOADOUT_38") (pintype "passive"))
      (node (ref "U17") (pin "5") (pinfunction "LOAD_5") (pintype "passive"))
    )
    (net (code "48") (name "Net-(U14-MISOIN)") (class "Default")
      (node (ref "TP112") (pin "1") (pinfunction "1_1") (pintype "passive"))
      (node (ref "U14") (pin "36") (pinfunction "MISOIN_36") (pintype "passive"))
      (node (ref "U17") (pin "7") (pinfunction "MISO_7") (pintype "passive"))
    )
    (net (code "49") (name "Net-(U14-MOSIOUT)") (class "Default")
      (node (ref "TP115") (pin "1") (pinfunction "1_1") (pintype "passive"))
      (node (ref "U14") (pin "35") (pinfunction "MOSIOUT_35") (pintype "passive"))
      (node (ref "U17") (pin "8") (pinfunction "MOSI_8") (pintype "passive"))
    )
    (net (code "50") (name "Net-(U14-RSTNOUT)") (class "Default")
      (node (ref "TP109") (pin "1") (pinfunction "1_1") (pintype "passive"))
      (node (ref "U14") (pin "37") (pinfunction "RSTNOUT_37") (pintype "passive"))
      (node (ref "U17") (pin "6") (pinfunction "RSTN_6") (pintype "passive"))
    )
    (net (code "51") (name "Net-(U14-SCKOUT)") (class "Default")
      (node (ref "TP119") (pin "1") (pinfunction "1_1") (pintype "passive"))
      (node (ref "U14") (pin "34") (pinfunction "SCKOUT_34") (pintype "passive"))
      (node (ref "U17") (pin "9") (pinfunction "SCK_9") (pintype "passive"))
    )
    (net (code "52") (name "Net-(U14-XCLKOUT)") (class "Default")
      (node (ref "TP130") (pin "1") (pinfunction "1_1") (pintype "passive"))
      (node (ref "U14") (pin "33") (pinfunction "XCLKOUT_33") (pintype "passive"))
      (node (ref "U17") (pin "10") (pinfunction "XCLKIN_10") (pintype "passive"))
    )
    (net (code "53") (name "Net-(U17-LOADOUT)") (class "Default")
      (node (ref "TP107") (pin "1") (pinfunction "1_1") (pintype "passive"))
      (node (ref "U17") (pin "38") (pinfunction "LOADOUT_38") (pintype "passive"))
      (node (ref "U18") (pin "5") (pinfunction "LOAD_5") (pintype "passive"))
    )
    (net (code "54") (name "Net-(U17-MISOIN)") (class "Default")
      (node (ref "TP113") (pin "1") (pinfunction "1_1") (pintype "passive"))
      (node (ref "U17") (pin "36") (pinfunction "MISOIN_36") (pintype "passive"))
      (node (ref "U18") (pin "7") (pinfunction "MISO_7") (pintype "passive"))
    )
    (net (code "55") (name "Net-(U17-MOSIOUT)") (class "Default")
      (node (ref "TP116") (pin "1") (pinfunction "1_1") (pintype "passive"))
      (node (ref "U17") (pin "35") (pinfunction "MOSIOUT_35") (pintype "passive"))
      (node (ref "U18") (pin "8") (pinfunction "MOSI_8") (pintype "passive"))
    )
    (net (code "56") (name "Net-(U17-RSTNOUT)") (class "Default")
      (node (ref "TP110") (pin "1") (pinfunction "1_1") (pintype "passive"))
      (node (ref "U17") (pin "37") (pinfunction "RSTNOUT_37") (pintype "passive"))
      (node (ref "U18") (pin "6") (pinfunction "RSTN_6") (pintype "passive"))
    )
    (net (code "57") (name "Net-(U17-SCKOUT)") (class "Default")
      (node (ref "TP120") (pin "1") (pinfunction "1_1") (pintype "passive"))
      (node (ref "U17") (pin "34") (pinfunction "SCKOUT_34") (pintype "passive"))
      (node (ref "U18") (pin "9") (pinfunction "SCK_9") (pintype "passive"))
    )
    (net (code "58") (name "Net-(U17-XCLKOUT)") (class "Default")
      (node (ref "TP133") (pin "1") (pinfunction "1_1") (pintype "passive"))
      (node (ref "U17") (pin "33") (pinfunction "XCLKOUT_33") (pintype "passive"))
      (node (ref "U18") (pin "10") (pinfunction "XCLKIN_10") (pintype "passive"))
    )
    (net (code "59") (name "Net-(U21-LOADOUT)") (class "Default")
      (node (ref "TP202") (pin "1") (pinfunction "1_1") (pintype "passive"))
      (node (ref "U21") (pin "38") (pinfunction "LOADOUT_38") (pintype "passive"))
      (node (ref "U22") (pin "5") (pinfunction "LOAD_5") (pintype "passive"))
    )
    (net (code "60") (name "Net-(U21-MISOIN)") (class "Default")
      (node (ref "TP216") (pin "1") (pinfunction "1_1") (pintype "passive"))
      (node (ref "U21") (pin "36") (pinfunction "MISOIN_36") (pintype "passive"))
      (node (ref "U22") (pin "7") (pinfunction "MISO_7") (pintype "passive"))
    )
    (net (code "61") (name "Net-(U21-MOSIOUT)") (class "Default")
      (node (ref "TP223") (pin "1") (pinfunction "1_1") (pintype "passive"))
      (node (ref "U21") (pin "35") (pinfunction "MOSIOUT_35") (pintype "passive"))
      (node (ref "U22") (pin "8") (pinfunction "MOSI_8") (pintype "passive"))
    )
    (net (code "62") (name "Net-(U21-RSTNOUT)") (class "Default")
      (node (ref "TP209") (pin "1") (pinfunction "1_1") (pintype "passive"))
      (node (ref "U21") (pin "37") (pinfunction "RSTNOUT_37") (pintype "passive"))
      (node (ref "U22") (pin "6") (pinfunction "RSTN_6") (pintype "passive"))
    )
    (net (code "63") (name "Net-(U21-SCKOUT)") (class "Default")
      (node (ref "TP231") (pin "1") (pinfunction "1_1") (pintype "passive"))
      (node (ref "U21") (pin "34") (pinfunction "SCKOUT_34") (pintype "passive"))
      (node (ref "U22") (pin "9") (pinfunction "SCK_9") (pintype "passive"))
    )
    (net (code "64") (name "Net-(U21-XCLKOUT)") (class "Default")
      (node (ref "TP304") (pin "1") (pinfunction "1_1") (pintype "passive"))
      (node (ref "U21") (pin "33") (pinfunction "XCLKOUT_33") (pintype "passive"))
      (node (ref "U22") (pin "10") (pinfunction "XCLKIN_10") (pintype "passive"))
    )
    (net (code "65") (name "Net-(U22-LOADOUT)") (class "Default")
      (node (ref "TP203") (pin "1") (pinfunction "1_1") (pintype "passive"))
      (node (ref "U22") (pin "38") (pinfunction "LOADOUT_38") (pintype "passive"))
      (node (ref "U25") (pin "5") (pinfunction "LOAD_5") (pintype "passive"))
    )
    (net (code "66") (name "Net-(U22-MISOIN)") (class "Default")
      (node (ref "TP217") (pin "1") (pinfunction "1_1") (pintype "passive"))
      (node (ref "U22") (pin "36") (pinfunction "MISOIN_36") (pintype "passive"))
      (node (ref "U25") (pin "7") (pinfunction "MISO_7") (pintype "passive"))
    )
    (net (code "67") (name "Net-(U22-MOSIOUT)") (class "Default")
      (node (ref "TP224") (pin "1") (pinfunction "1_1") (pintype "passive"))
      (node (ref "U22") (pin "35") (pinfunction "MOSIOUT_35") (pintype "passive"))
      (node (ref "U25") (pin "8") (pinfunction "MOSI_8") (pintype "passive"))
    )
    (net (code "68") (name "Net-(U22-RSTNOUT)") (class "Default")
      (node (ref "TP210") (pin "1") (pinfunction "1_1") (pintype "passive"))
      (node (ref "U22") (pin "37") (pinfunction "RSTNOUT_37") (pintype "passive"))
      (node (ref "U25") (pin "6") (pinfunction "RSTN_6") (pintype "passive"))
    )
    (net (code "69") (name "Net-(U22-SCKOUT)") (class "Default")
      (node (ref "TP232") (pin "1") (pinfunction "1_1") (pintype "passive"))
      (node (ref "U22") (pin "34") (pinfunction "SCKOUT_34") (pintype "passive"))
      (node (ref "U25") (pin "9") (pinfunction "SCK_9") (pintype "passive"))
    )
    (net (code "70") (name "Net-(U22-XCLKOUT)") (class "Default")
      (node (ref "TP239") (pin "1") (pinfunction "1_1") (pintype "passive"))
      (node (ref "U22") (pin "33") (pinfunction "XCLKOUT_33") (pintype "passive"))
      (node (ref "U25") (pin "10") (pinfunction "XCLKIN_10") (pintype "passive"))
    )
    (net (code "71") (name "Net-(U25-LOADOUT)") (class "Default")
      (node (ref "TP204") (pin "1") (pinfunction "1_1") (pintype "passive"))
      (node (ref "U25") (pin "38") (pinfunction "LOADOUT_38") (pintype "passive"))
      (node (ref "U26") (pin "5") (pinfunction "LOAD_5") (pintype "passive"))
    )
    (net (code "72") (name "Net-(U25-MISOIN)") (class "Default")
      (node (ref "TP218") (pin "1") (pinfunction "1_1") (pintype "passive"))
      (node (ref "U25") (pin "36") (pinfunction "MISOIN_36") (pintype "passive"))
      (node (ref "U26") (pin "7") (pinfunction "MISO_7") (pintype "passive"))
    )
    (net (code "73") (name "Net-(U25-MOSIOUT)") (class "Default")
      (node (ref "TP225") (pin "1") (pinfunction "1_1") (pintype "passive"))
      (node (ref "U25") (pin "35") (pinfunction "MOSIOUT_35") (pintype "passive"))
      (node (ref "U26") (pin "8") (pinfunction "MOSI_8") (pintype "passive"))
    )
    (net (code "74") (name "Net-(U25-RSTNOUT)") (class "Default")
      (node (ref "TP211") (pin "1") (pinfunction "1_1") (pintype "passive"))
      (node (ref "U25") (pin "37") (pinfunction "RSTNOUT_37") (pintype "passive"))
      (node (ref "U26") (pin "6") (pinfunction "RSTN_6") (pintype "passive"))
    )
    (net (code "75") (name "Net-(U25-SCKOUT)") (class "Default")
      (node (ref "TP233") (pin "1") (pinfunction "1_1") (pintype "passive"))
      (node (ref "U25") (pin "34") (pinfunction "SCKOUT_34") (pintype "passive"))
      (node (ref "U26") (pin "9") (pinfunction "SCK_9") (pintype "passive"))
    )
    (net (code "76") (name "Net-(U25-XCLKOUT)") (class "Default")
      (node (ref "TP240") (pin "1") (pinfunction "1_1") (pintype "passive"))
      (node (ref "U25") (pin "33") (pinfunction "XCLKOUT_33") (pintype "passive"))
      (node (ref "U26") (pin "10") (pinfunction "XCLKIN_10") (pintype "passive"))
    )
    (net (code "77") (name "Net-(U26-LOADOUT)") (class "Default")
      (node (ref "TP205") (pin "1") (pinfunction "1_1") (pintype "passive"))
      (node (ref "U26") (pin "38") (pinfunction "LOADOUT_38") (pintype "passive"))
      (node (ref "U30") (pin "5") (pinfunction "LOAD_5") (pintype "passive"))
    )
    (net (code "78") (name "Net-(U26-MISOIN)") (class "Default")
      (node (ref "TP219") (pin "1") (pinfunction "1_1") (pintype "passive"))
      (node (ref "U26") (pin "36") (pinfunction "MISOIN_36") (pintype "passive"))
      (node (ref "U30") (pin "7") (pinfunction "MISO_7") (pintype "passive"))
    )
    (net (code "79") (name "Net-(U26-MOSIOUT)") (class "Default")
      (node (ref "TP226") (pin "1") (pinfunction "1_1") (pintype "passive"))
      (node (ref "U26") (pin "35") (pinfunction "MOSIOUT_35") (pintype "passive"))
      (node (ref "U30") (pin "8") (pinfunction "MOSI_8") (pintype "passive"))
    )
    (net (code "80") (name "Net-(U26-RSTNOUT)") (class "Default")
      (node (ref "TP212") (pin "1") (pinfunction "1_1") (pintype "passive"))
      (node (ref "U26") (pin "37") (pinfunction "RSTNOUT_37") (pintype "passive"))
      (node (ref "U30") (pin "6") (pinfunction "RSTN_6") (pintype "passive"))
    )
    (net (code "81") (name "Net-(U26-SCKOUT)") (class "Default")
      (node (ref "TP234") (pin "1") (pinfunction "1_1") (pintype "passive"))
      (node (ref "U26") (pin "34") (pinfunction "SCKOUT_34") (pintype "passive"))
      (node (ref "U30") (pin "9") (pinfunction "SCK_9") (pintype "passive"))
    )
    (net (code "82") (name "Net-(U26-XCLKOUT)") (class "Default")
      (node (ref "TP241") (pin "1") (pinfunction "1_1") (pintype "passive"))
      (node (ref "U26") (pin "33") (pinfunction "XCLKOUT_33") (pintype "passive"))
      (node (ref "U30") (pin "10") (pinfunction "XCLKIN_10") (pintype "passive"))
    )
    (net (code "83") (name "Net-(U30-LOADOUT)") (class "Default")
      (node (ref "TP206") (pin "1") (pinfunction "1_1") (pintype "passive"))
      (node (ref "U30") (pin "38") (pinfunction "LOADOUT_38") (pintype "passive"))
      (node (ref "U31") (pin "5") (pinfunction "LOAD_5") (pintype "passive"))
    )
    (net (code "84") (name "Net-(U30-MISOIN)") (class "Default")
      (node (ref "TP220") (pin "1") (pinfunction "1_1") (pintype "passive"))
      (node (ref "U30") (pin "36") (pinfunction "MISOIN_36") (pintype "passive"))
      (node (ref "U31") (pin "7") (pinfunction "MISO_7") (pintype "passive"))
    )
    (net (code "85") (name "Net-(U30-MOSIOUT)") (class "Default")
      (node (ref "TP227") (pin "1") (pinfunction "1_1") (pintype "passive"))
      (node (ref "U30") (pin "35") (pinfunction "MOSIOUT_35") (pintype "passive"))
      (node (ref "U31") (pin "8") (pinfunction "MOSI_8") (pintype "passive"))
    )
    (net (code "86") (name "Net-(U30-RSTNOUT)") (class "Default")
      (node (ref "TP213") (pin "1") (pinfunction "1_1") (pintype "passive"))
      (node (ref "U30") (pin "37") (pinfunction "RSTNOUT_37") (pintype "passive"))
      (node (ref "U31") (pin "6") (pinfunction "RSTN_6") (pintype "passive"))
    )
    (net (code "87") (name "Net-(U30-SCKOUT)") (class "Default")
      (node (ref "TP235") (pin "1") (pinfunction "1_1") (pintype "passive"))
      (node (ref "U30") (pin "34") (pinfunction "SCKOUT_34") (pintype "passive"))
      (node (ref "U31") (pin "9") (pinfunction "SCK_9") (pintype "passive"))
    )
    (net (code "88") (name "Net-(U30-XCLKOUT)") (class "Default")
      (node (ref "TP242") (pin "1") (pinfunction "1_1") (pintype "passive"))
      (node (ref "U30") (pin "33") (pinfunction "XCLKOUT_33") (pintype "passive"))
      (node (ref "U31") (pin "10") (pinfunction "XCLKIN_10") (pintype "passive"))
    )
    (net (code "89") (name "Net-(U31-LOADOUT)") (class "Default")
      (node (ref "TP207") (pin "1") (pinfunction "1_1") (pintype "passive"))
      (node (ref "U31") (pin "38") (pinfunction "LOADOUT_38") (pintype "passive"))
      (node (ref "U32") (pin "5") (pinfunction "LOAD_5") (pintype "passive"))
    )
    (net (code "90") (name "Net-(U31-MISOIN)") (class "Default")
      (node (ref "TP221") (pin "1") (pinfunction "1_1") (pintype "passive"))
      (node (ref "U31") (pin "36") (pinfunction "MISOIN_36") (pintype "passive"))
      (node (ref "U32") (pin "7") (pinfunction "MISO_7") (pintype "passive"))
    )
    (net (code "91") (name "Net-(U31-MOSIOUT)") (class "Default")
      (node (ref "TP228") (pin "1") (pinfunction "1_1") (pintype "passive"))
      (node (ref "U31") (pin "35") (pinfunction "MOSIOUT_35") (pintype "passive"))
      (node (ref "U32") (pin "8") (pinfunction "MOSI_8") (pintype "passive"))
    )
    (net (code "92") (name "Net-(U31-RSTNOUT)") (class "Default")
      (node (ref "TP214") (pin "1") (pinfunction "1_1") (pintype "passive"))
      (node (ref "U31") (pin "37") (pinfunction "RSTNOUT_37") (pintype "passive"))
      (node (ref "U32") (pin "6") (pinfunction "RSTN_6") (pintype "passive"))
    )
    (net (code "93") (name "Net-(U31-SCKOUT)") (class "Default")
      (node (ref "TP236") (pin "1") (pinfunction "1_1") (pintype "passive"))
      (node (ref "U31") (pin "34") (pinfunction "SCKOUT_34") (pintype "passive"))
      (node (ref "U32") (pin "9") (pinfunction "SCK_9") (pintype "passive"))
    )
    (net (code "94") (name "Net-(U31-XCLKOUT)") (class "Default")
      (node (ref "TP243") (pin "1") (pinfunction "1_1") (pintype "passive"))
      (node (ref "U31") (pin "33") (pinfunction "XCLKOUT_33") (pintype "passive"))
      (node (ref "U32") (pin "10") (pinfunction "XCLKIN_10") (pintype "passive"))
    )
    (net (code "95") (name "Net-(U32-LOADOUT)") (class "Default")
      (node (ref "TP208") (pin "1") (pinfunction "1_1") (pintype "passive"))
      (node (ref "U32") (pin "38") (pinfunction "LOADOUT_38") (pintype "passive"))
      (node (ref "U33") (pin "5") (pinfunction "LOAD_5") (pintype "passive"))
    )
    (net (code "96") (name "Net-(U32-MISOIN)") (class "Default")
      (node (ref "TP222") (pin "1") (pinfunction "1_1") (pintype "passive"))
      (node (ref "U32") (pin "36") (pinfunction "MISOIN_36") (pintype "passive"))
      (node (ref "U33") (pin "7") (pinfunction "MISO_7") (pintype "passive"))
    )
    (net (code "97") (name "Net-(U32-MOSIOUT)") (class "Default")
      (node (ref "TP229") (pin "1") (pinfunction "1_1") (pintype "passive"))
      (node (ref "U32") (pin "35") (pinfunction "MOSIOUT_35") (pintype "passive"))
      (node (ref "U33") (pin "8") (pinfunction "MOSI_8") (pintype "passive"))
    )
    (net (code "98") (name "Net-(U32-RSTNOUT)") (class "Default")
      (node (ref "TP215") (pin "1") (pinfunction "1_1") (pintype "passive"))
      (node (ref "U32") (pin "37") (pinfunction "RSTNOUT_37") (pintype "passive"))
      (node (ref "U33") (pin "6") (pinfunction "RSTN_6") (pintype "passive"))
    )
    (net (code "99") (name "Net-(U32-SCKOUT)") (class "Default")
      (node (ref "TP237") (pin "1") (pinfunction "1_1") (pintype "passive"))
      (node (ref "U32") (pin "34") (pinfunction "SCKOUT_34") (pintype "passive"))
      (node (ref "U33") (pin "9") (pinfunction "SCK_9") (pintype "passive"))
    )
    (net (code "100") (name "Net-(U32-XCLKOUT)") (class "Default")
      (node (ref "TP244") (pin "1") (pinfunction "1_1") (pintype "passive"))
      (node (ref "U32") (pin "33") (pinfunction "XCLKOUT_33") (pintype "passive"))
      (node (ref "U33") (pin "10") (pinfunction "XCLKIN_10") (pintype "passive"))
    )
    (net (code "101") (name "Net-(U33-LOADOUT)") (class "Default")
      (node (ref "TP3") (pin "1") (pinfunction "1_1") (pintype "passive"))
      (node (ref "U33") (pin "38") (pinfunction "LOADOUT_38") (pintype "passive"))
    )
    (net (code "102") (name "Net-(U33-MISOIN)") (class "Default")
      (node (ref "R19") (pin "1") (pinfunction "1_1") (pintype "passive"))
      (node (ref "U33") (pin "36") (pinfunction "MISOIN_36") (pintype "passive"))
    )
    (net (code "103") (name "Net-(U33-MOSIOUT)") (class "Default")
      (node (ref "R19") (pin "2") (pinfunction "2_2") (pintype "passive"))
      (node (ref "U33") (pin "35") (pinfunction "MOSIOUT_35") (pintype "passive"))
    )
    (net (code "104") (name "Net-(U33-RSTNOUT)") (class "Default")
      (node (ref "TP295") (pin "1") (pinfunction "1_1") (pintype "passive"))
      (node (ref "U33") (pin "37") (pinfunction "RSTNOUT_37") (pintype "passive"))
    )
    (net (code "105") (name "Net-(U33-SCKOUT)") (class "Default")
      (node (ref "TP296") (pin "1") (pinfunction "1_1") (pintype "passive"))
      (node (ref "U33") (pin "34") (pinfunction "SCKOUT_34") (pintype "passive"))
    )
    (net (code "106") (name "Net-(U33-XCLKOUT)") (class "Default")
      (node (ref "TP297") (pin "1") (pinfunction "1_1") (pintype "passive"))
      (node (ref "U33") (pin "33") (pinfunction "XCLKOUT_33") (pintype "passive"))
    )
  )
)
